# bms_108_Cell.net
KiCad netlist of a schematic drawn in EAGLE
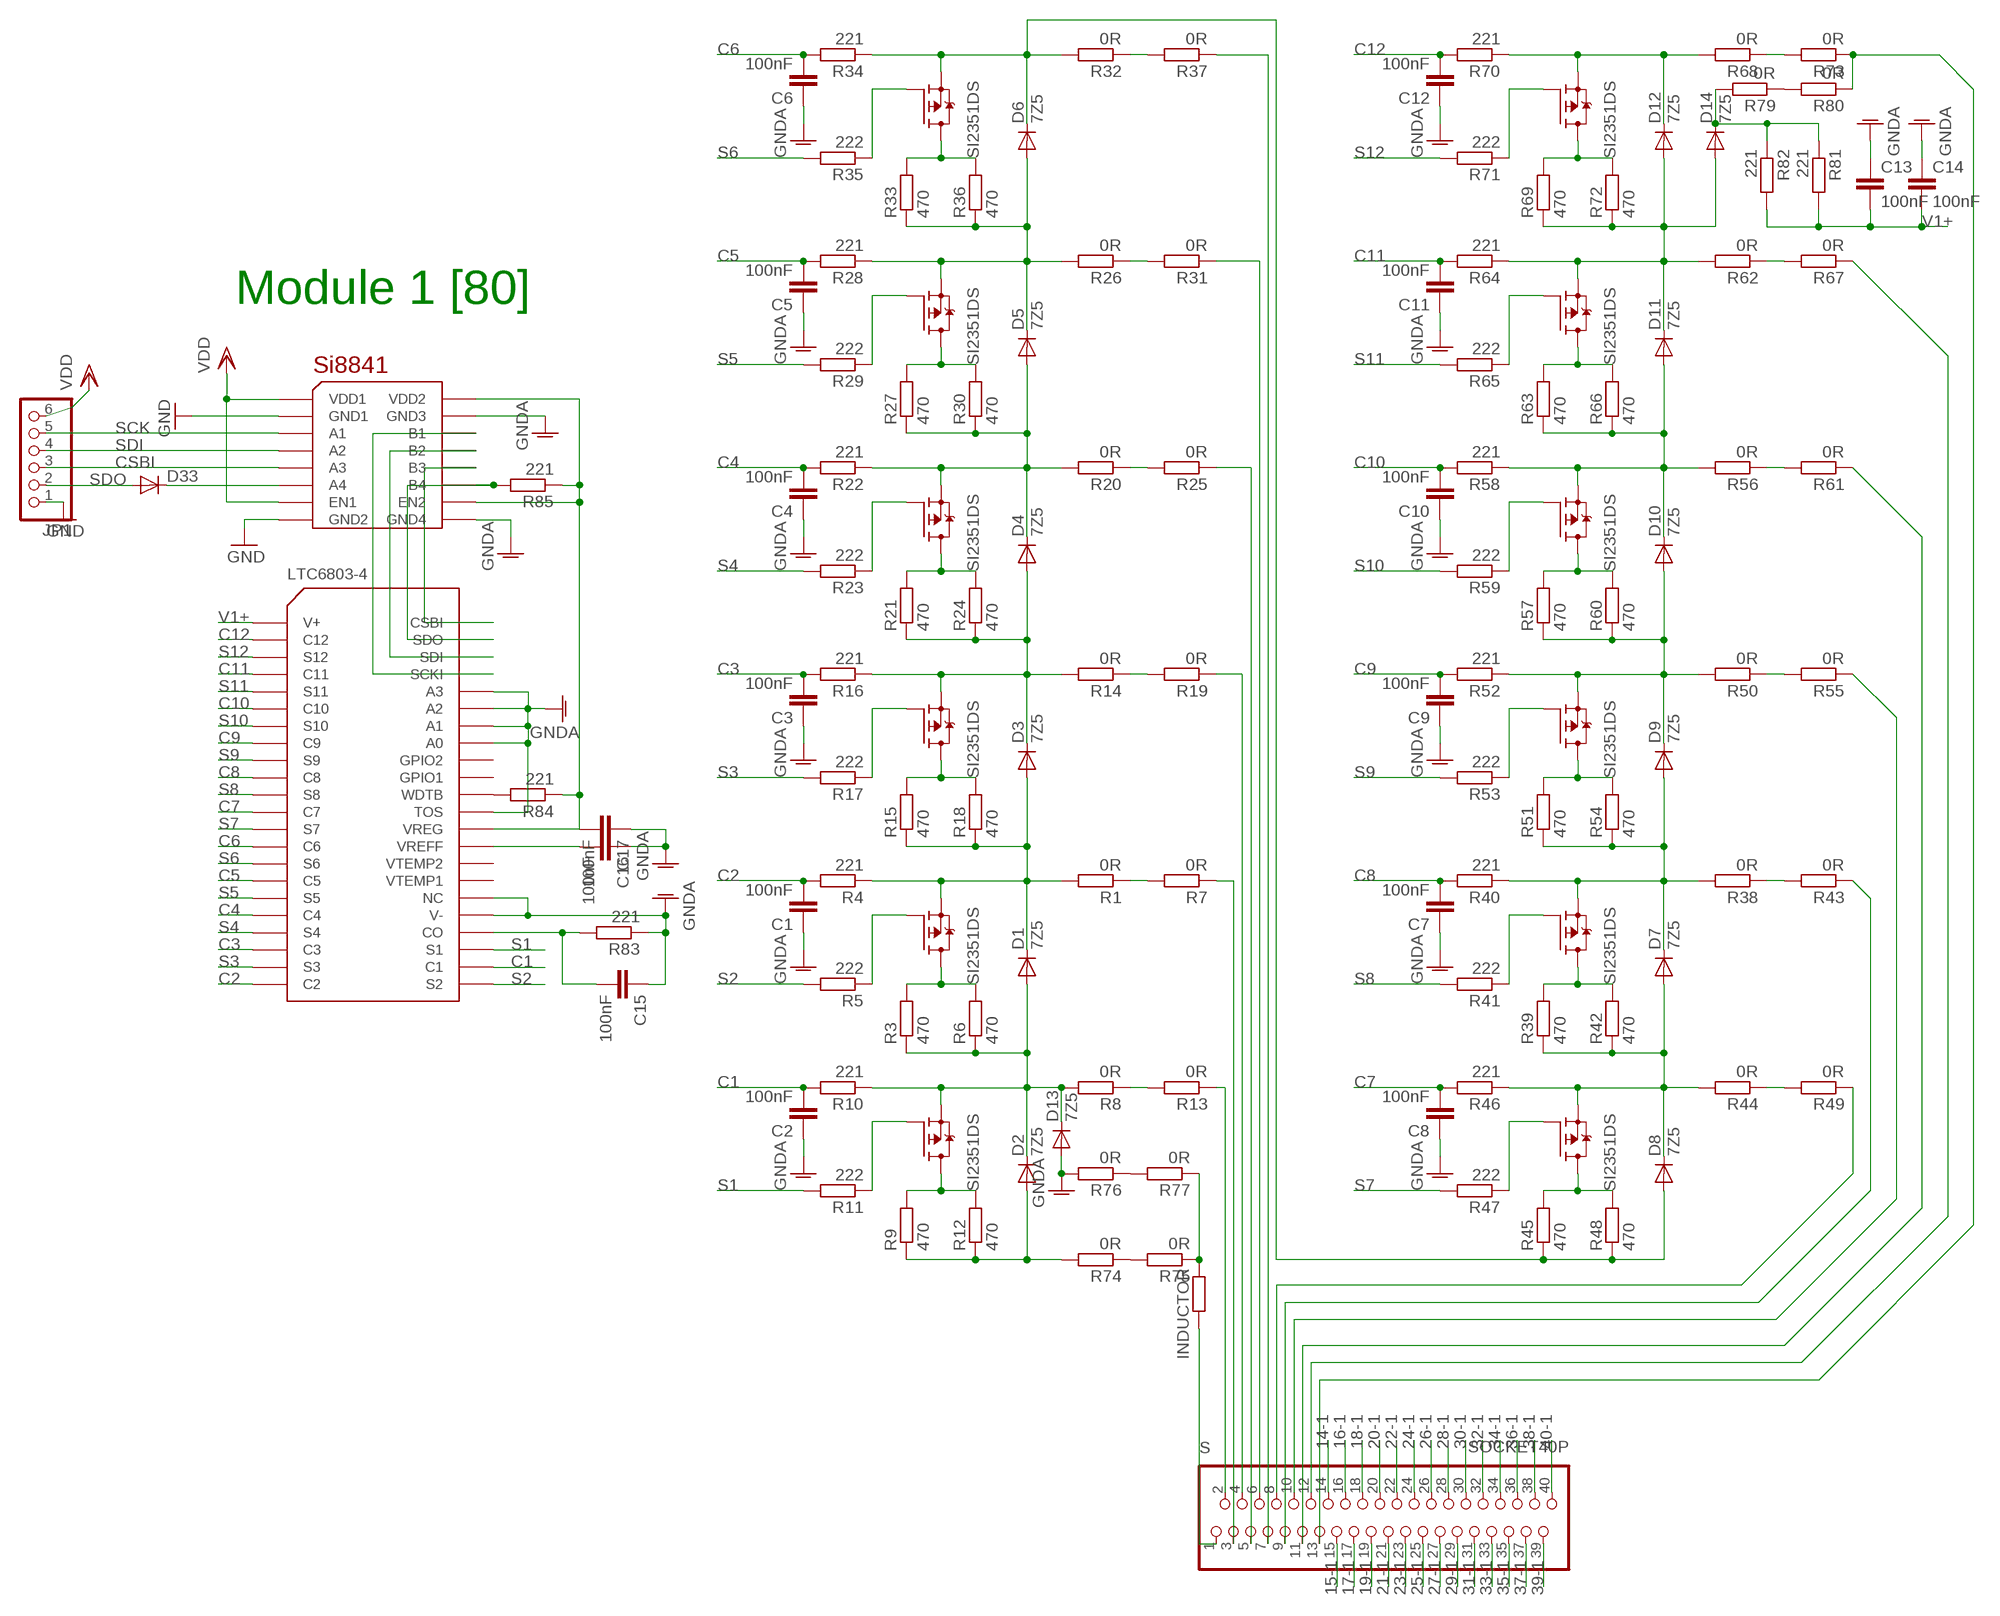
[diagram p0: schematic, sheet 1]
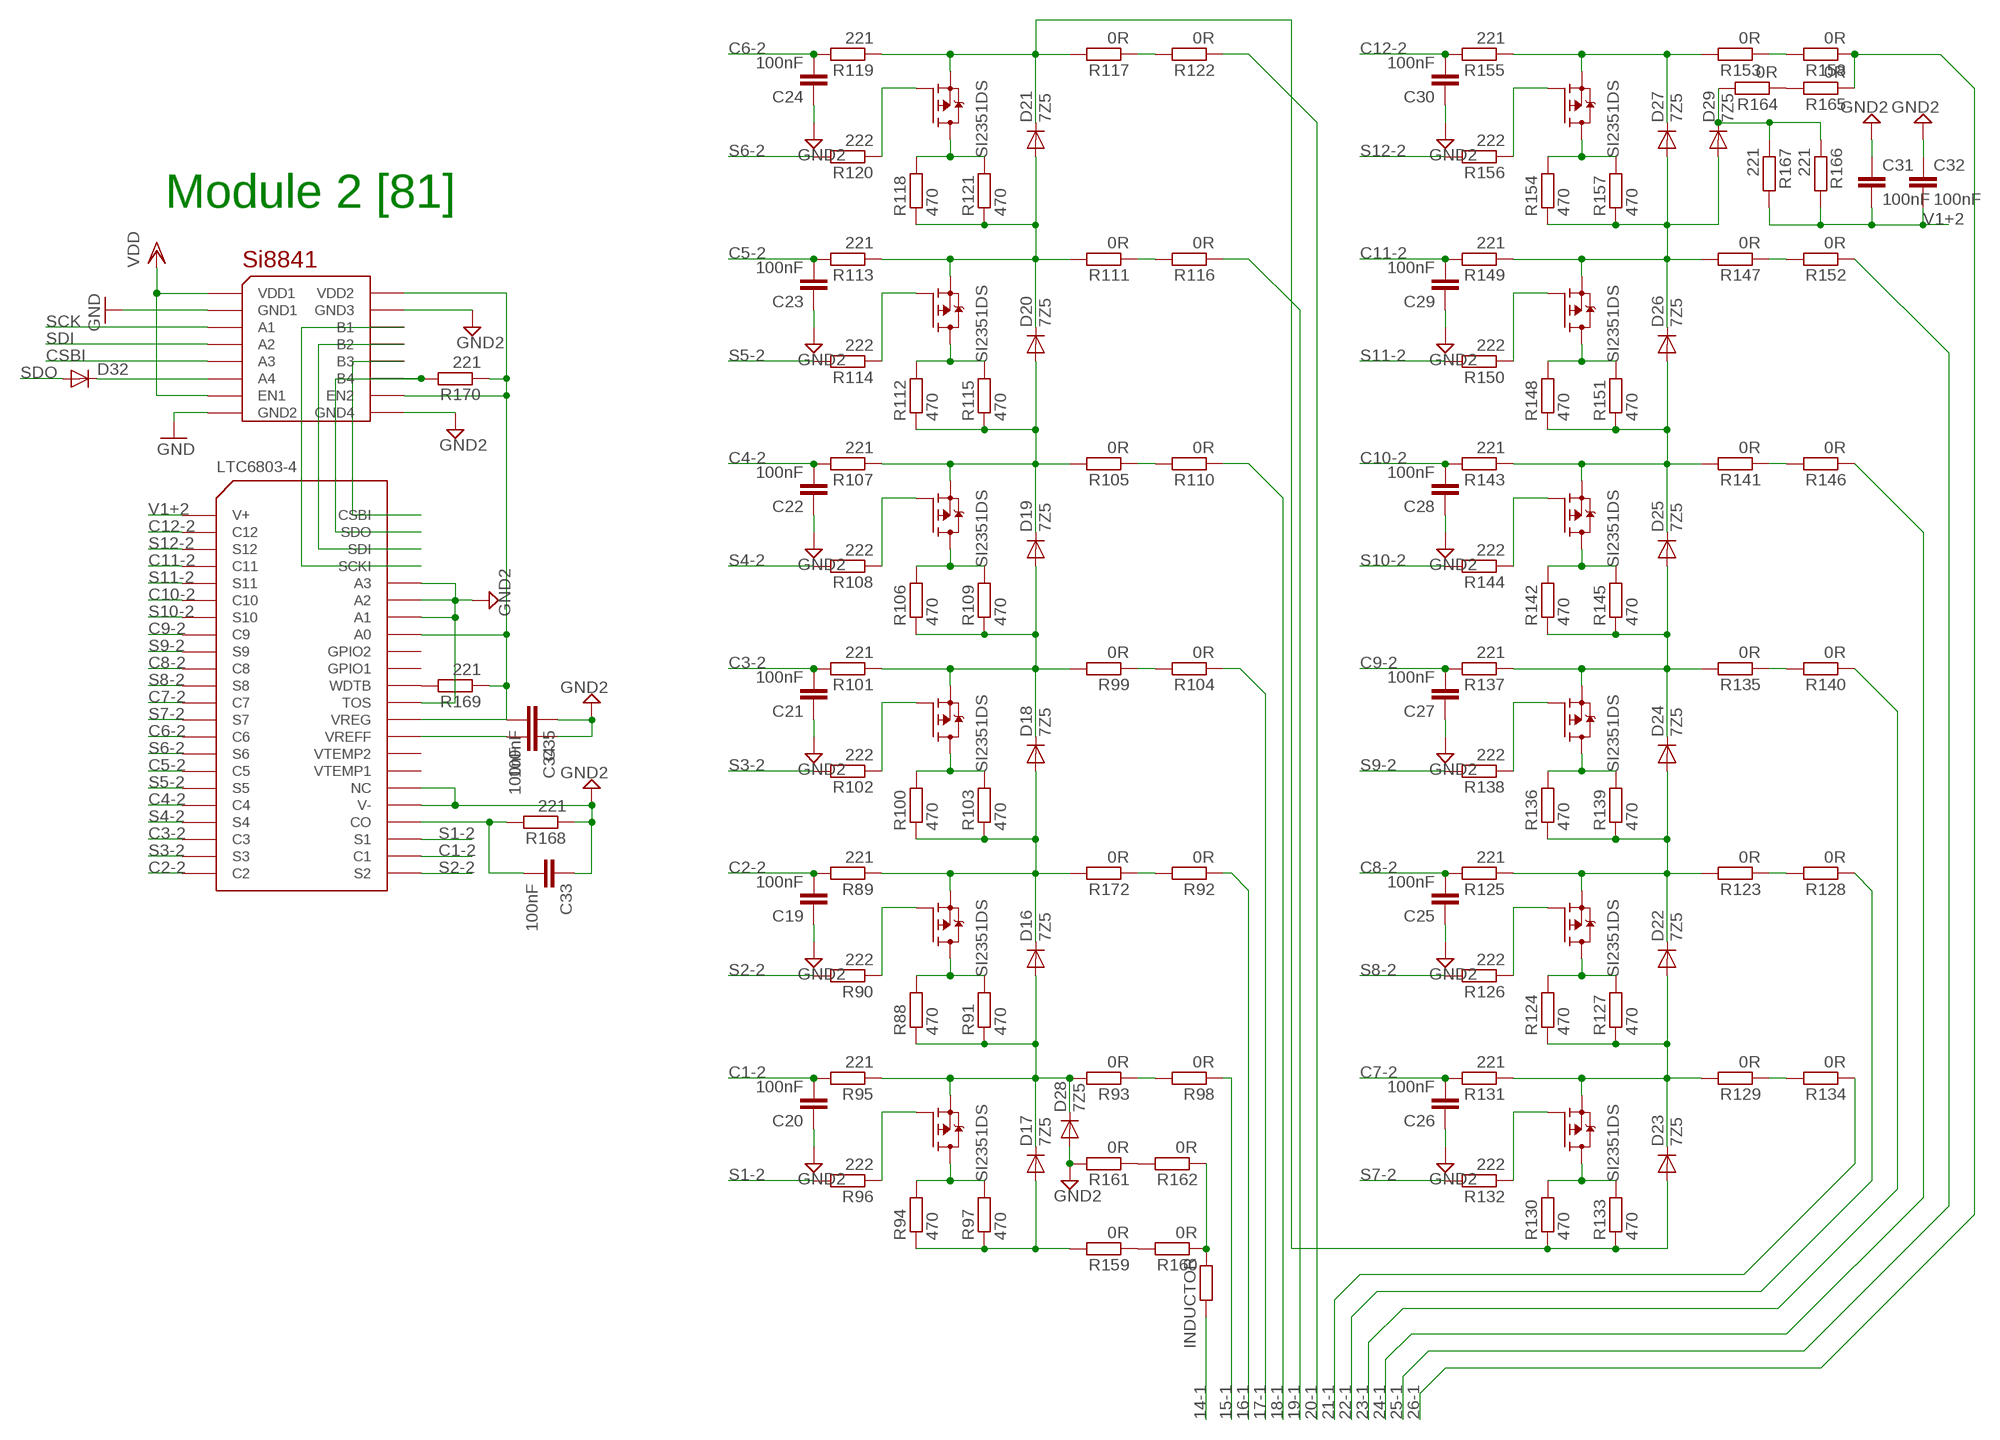
[diagram p1: schematic, sheet 2]
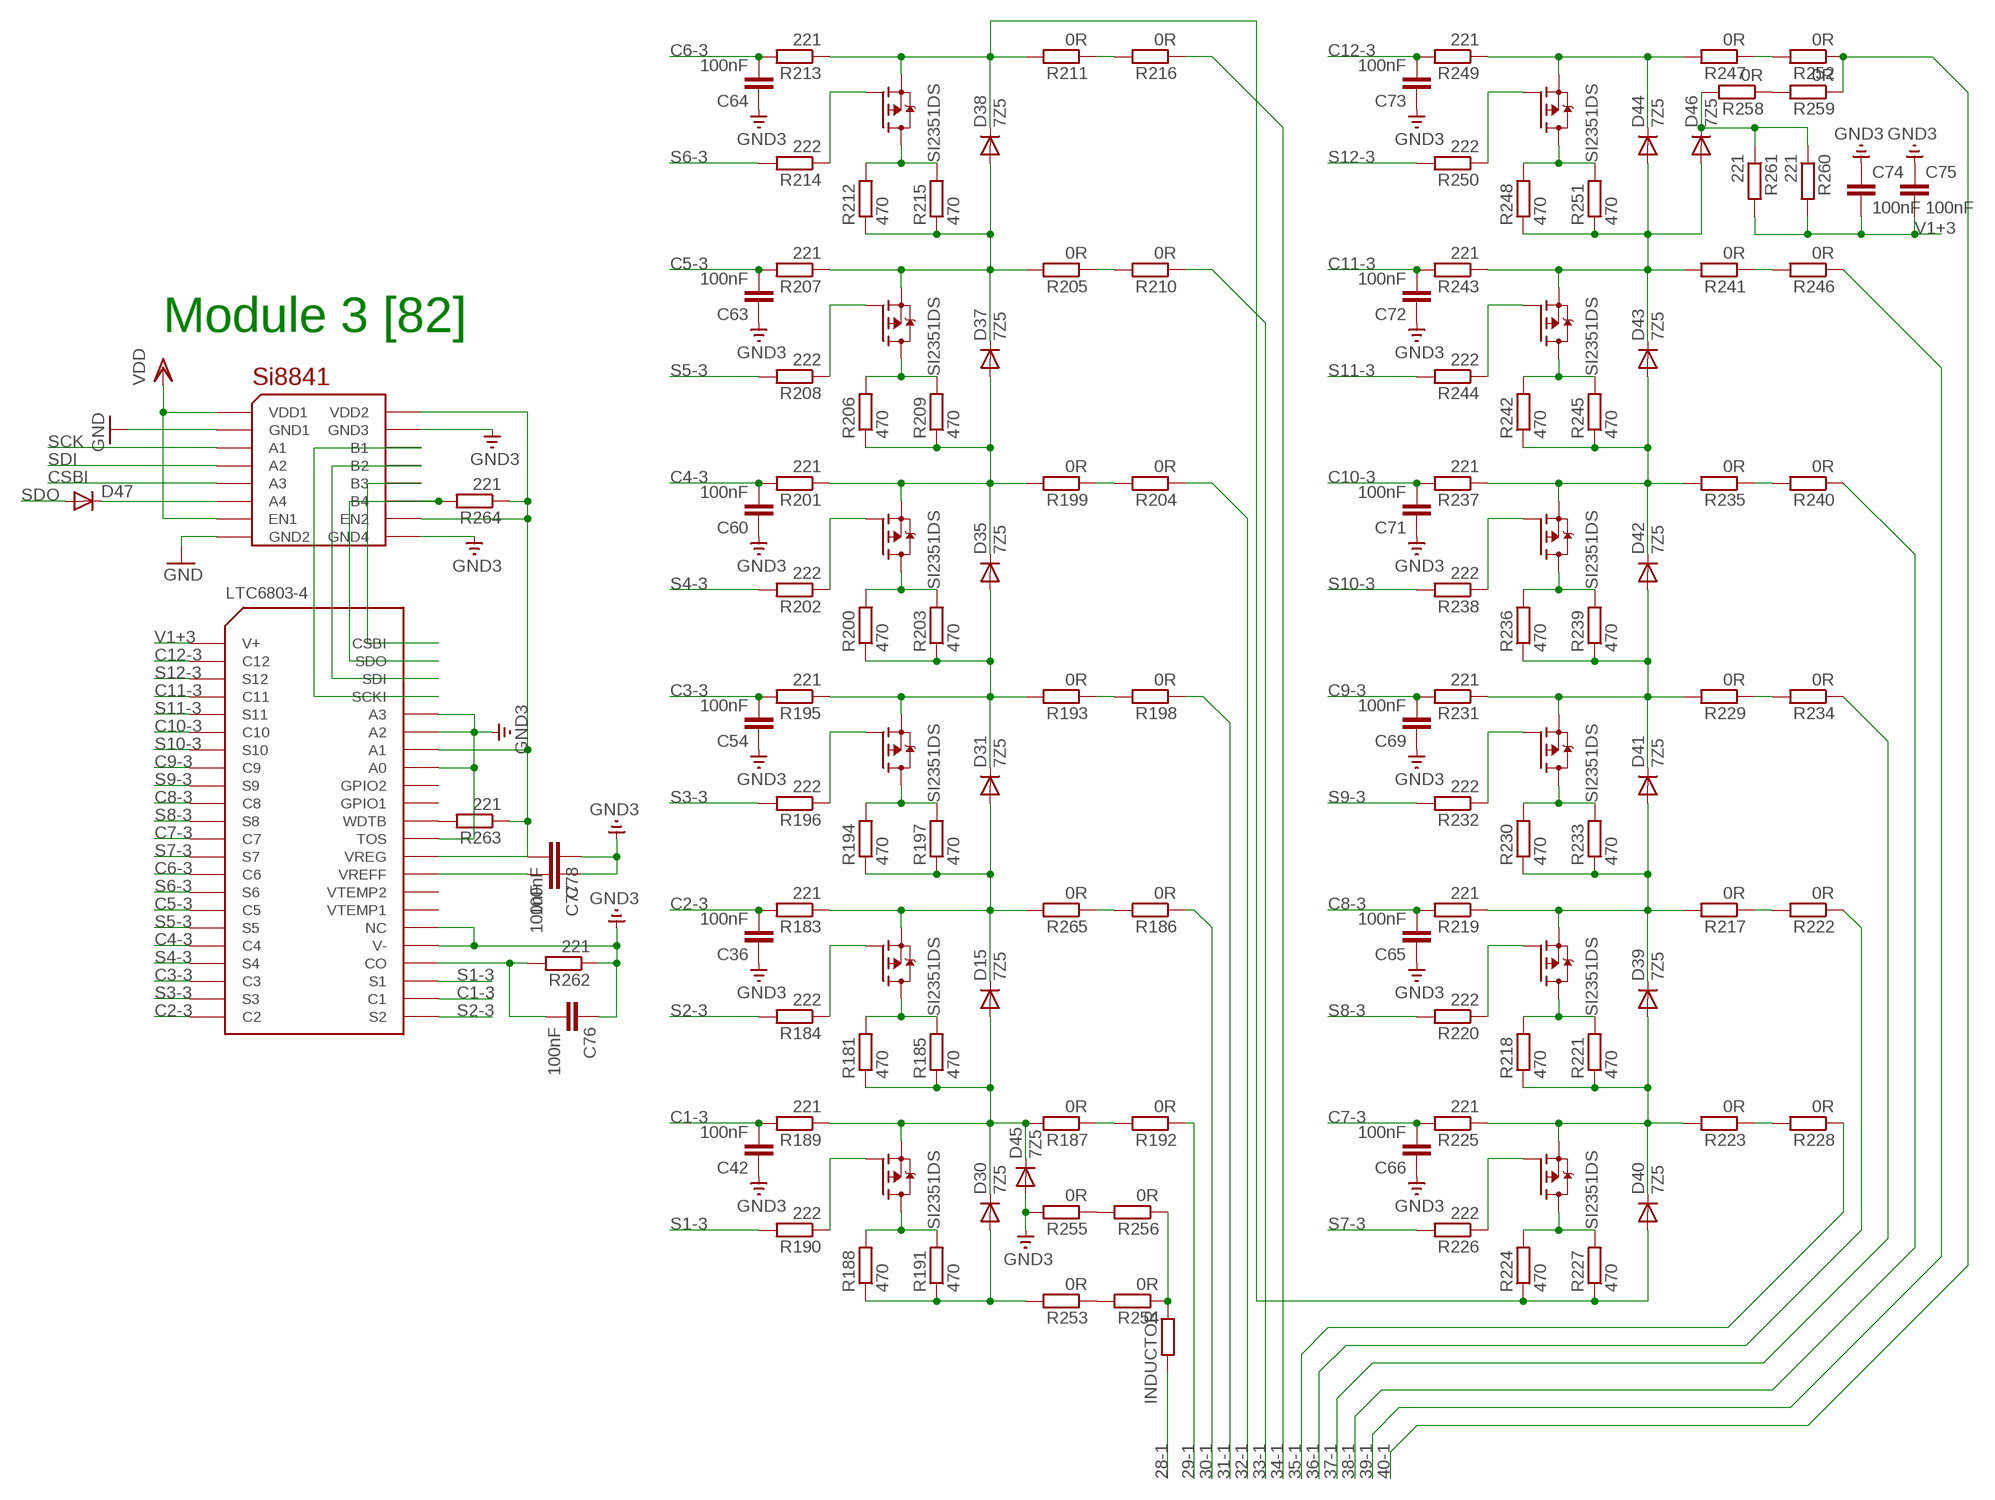
[diagram p2: schematic, sheet 3]
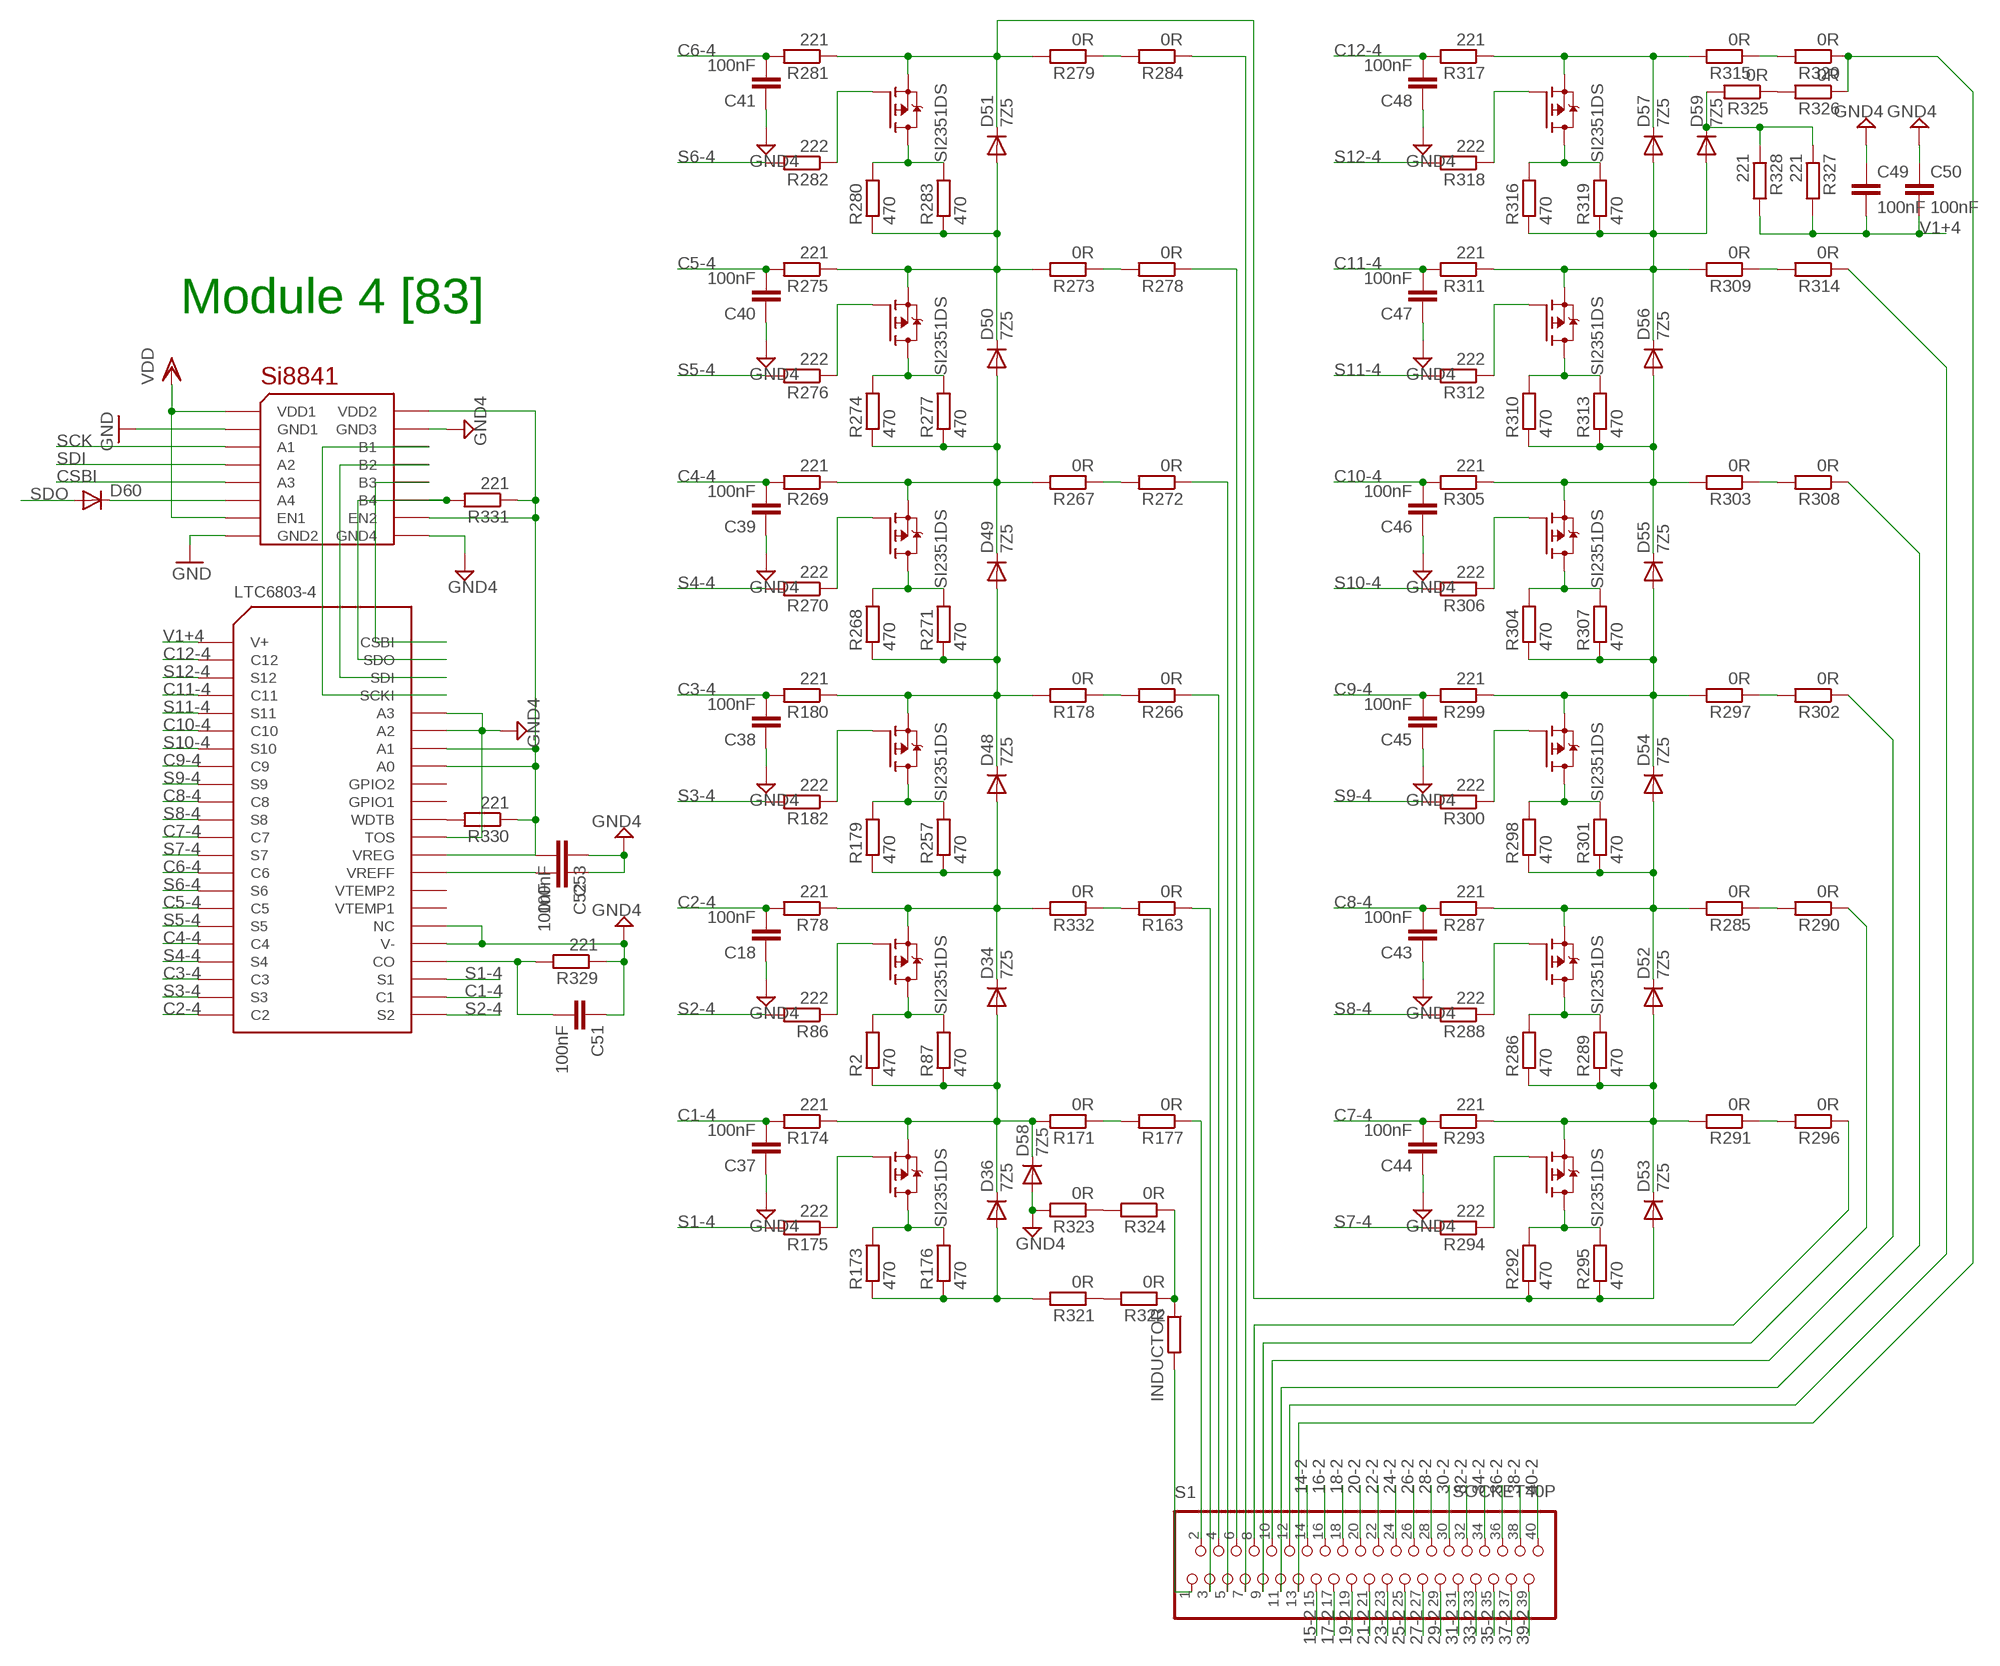
[diagram p3: schematic, sheet 4]
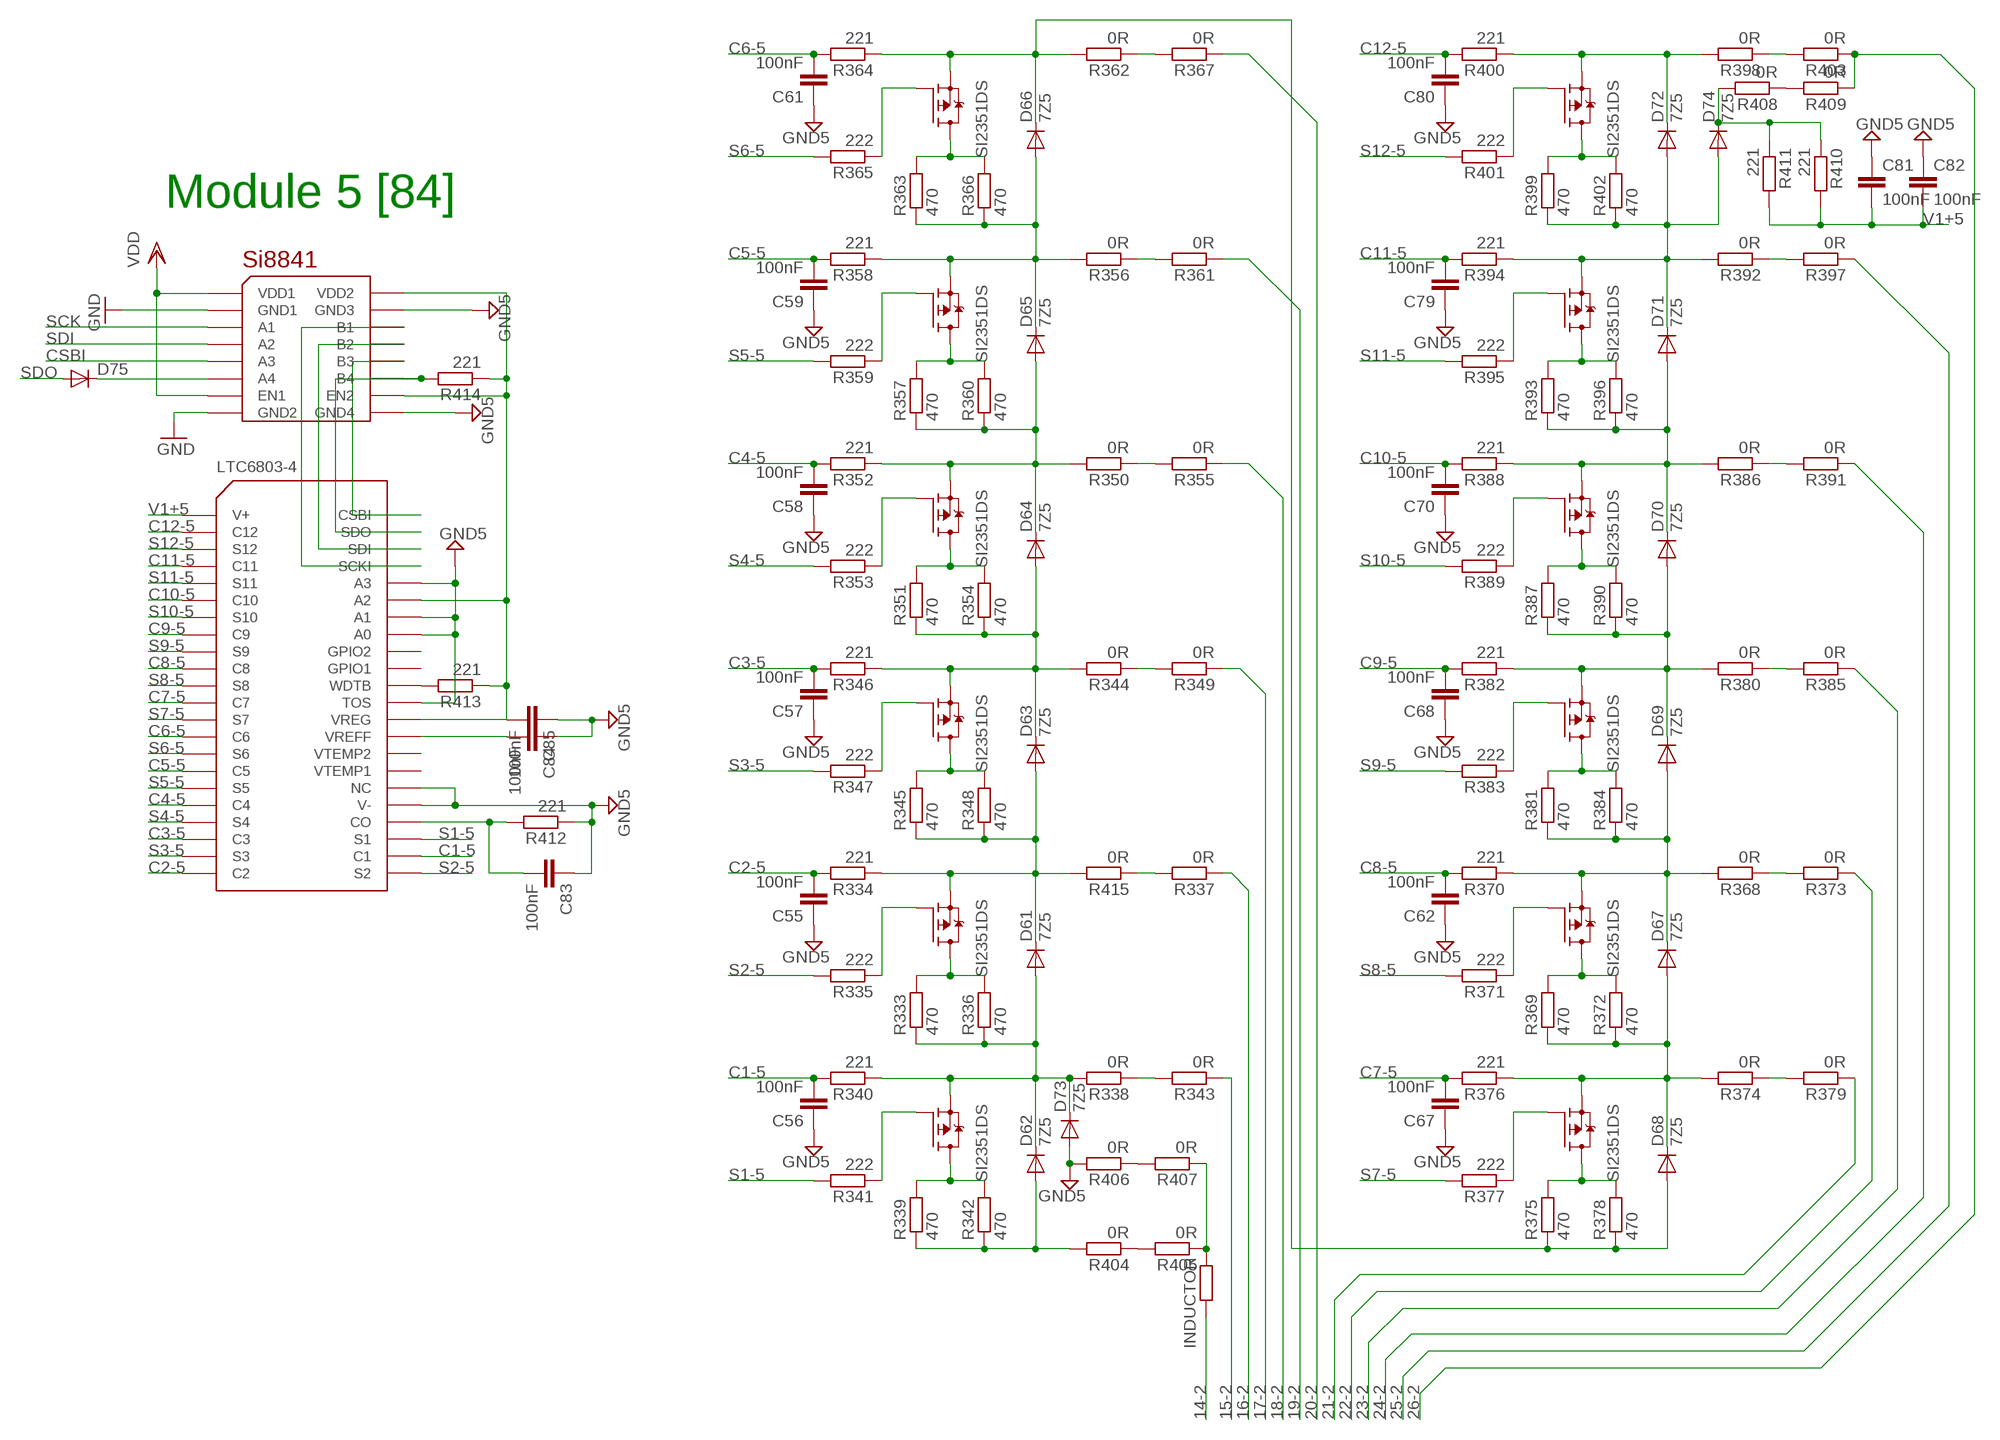
[diagram p4: schematic, sheet 5]
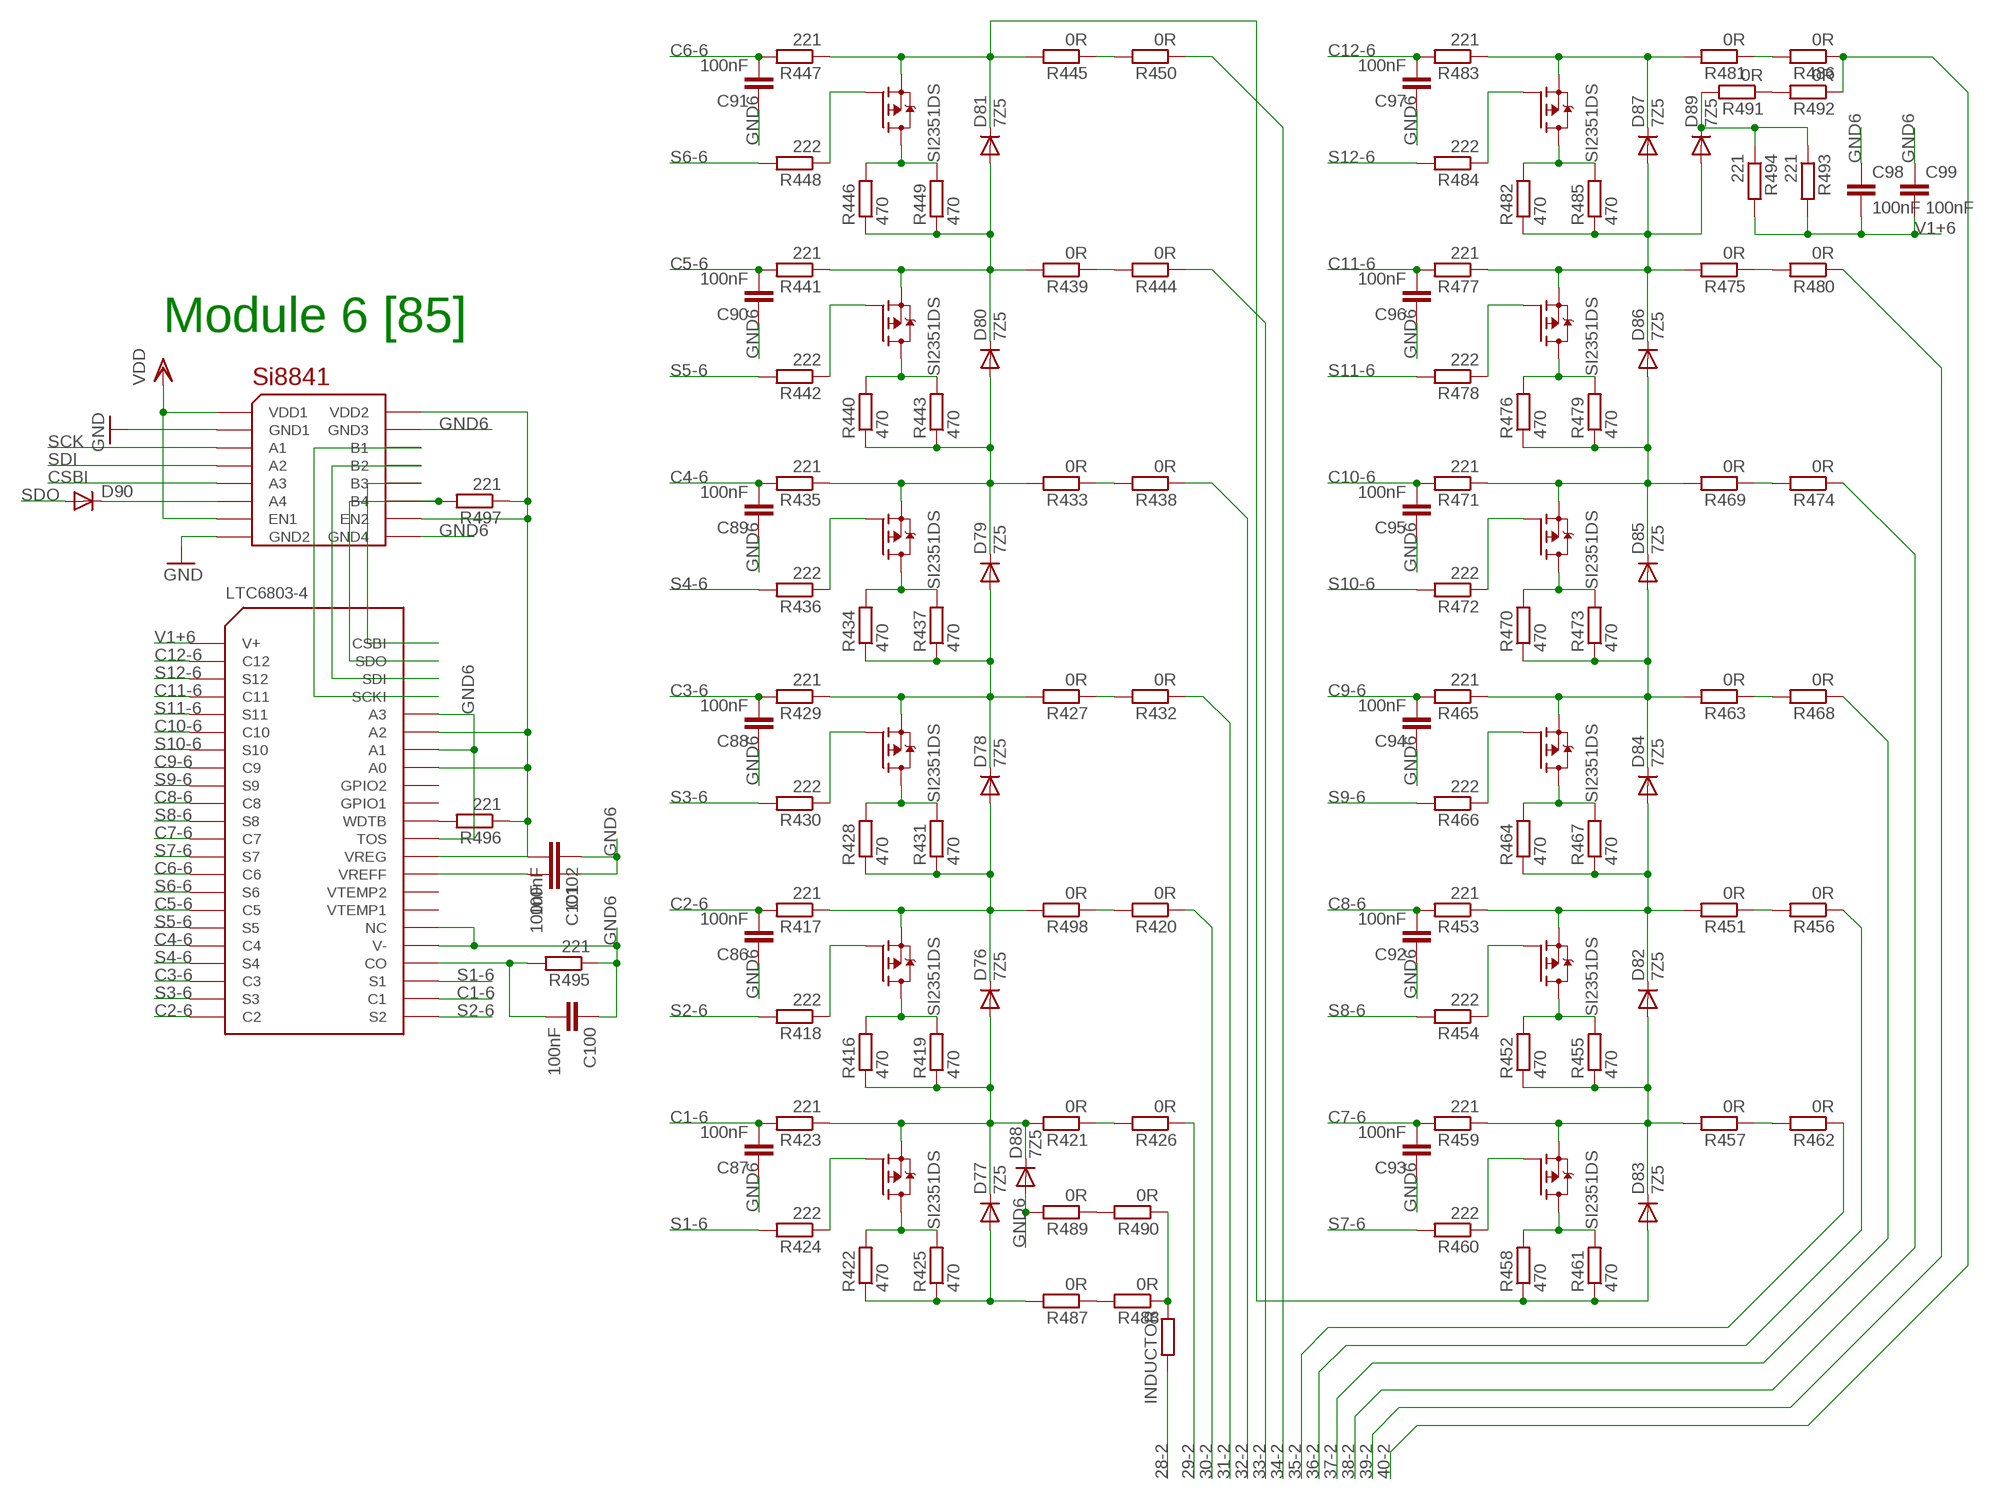
[diagram p5: schematic, sheet 6]
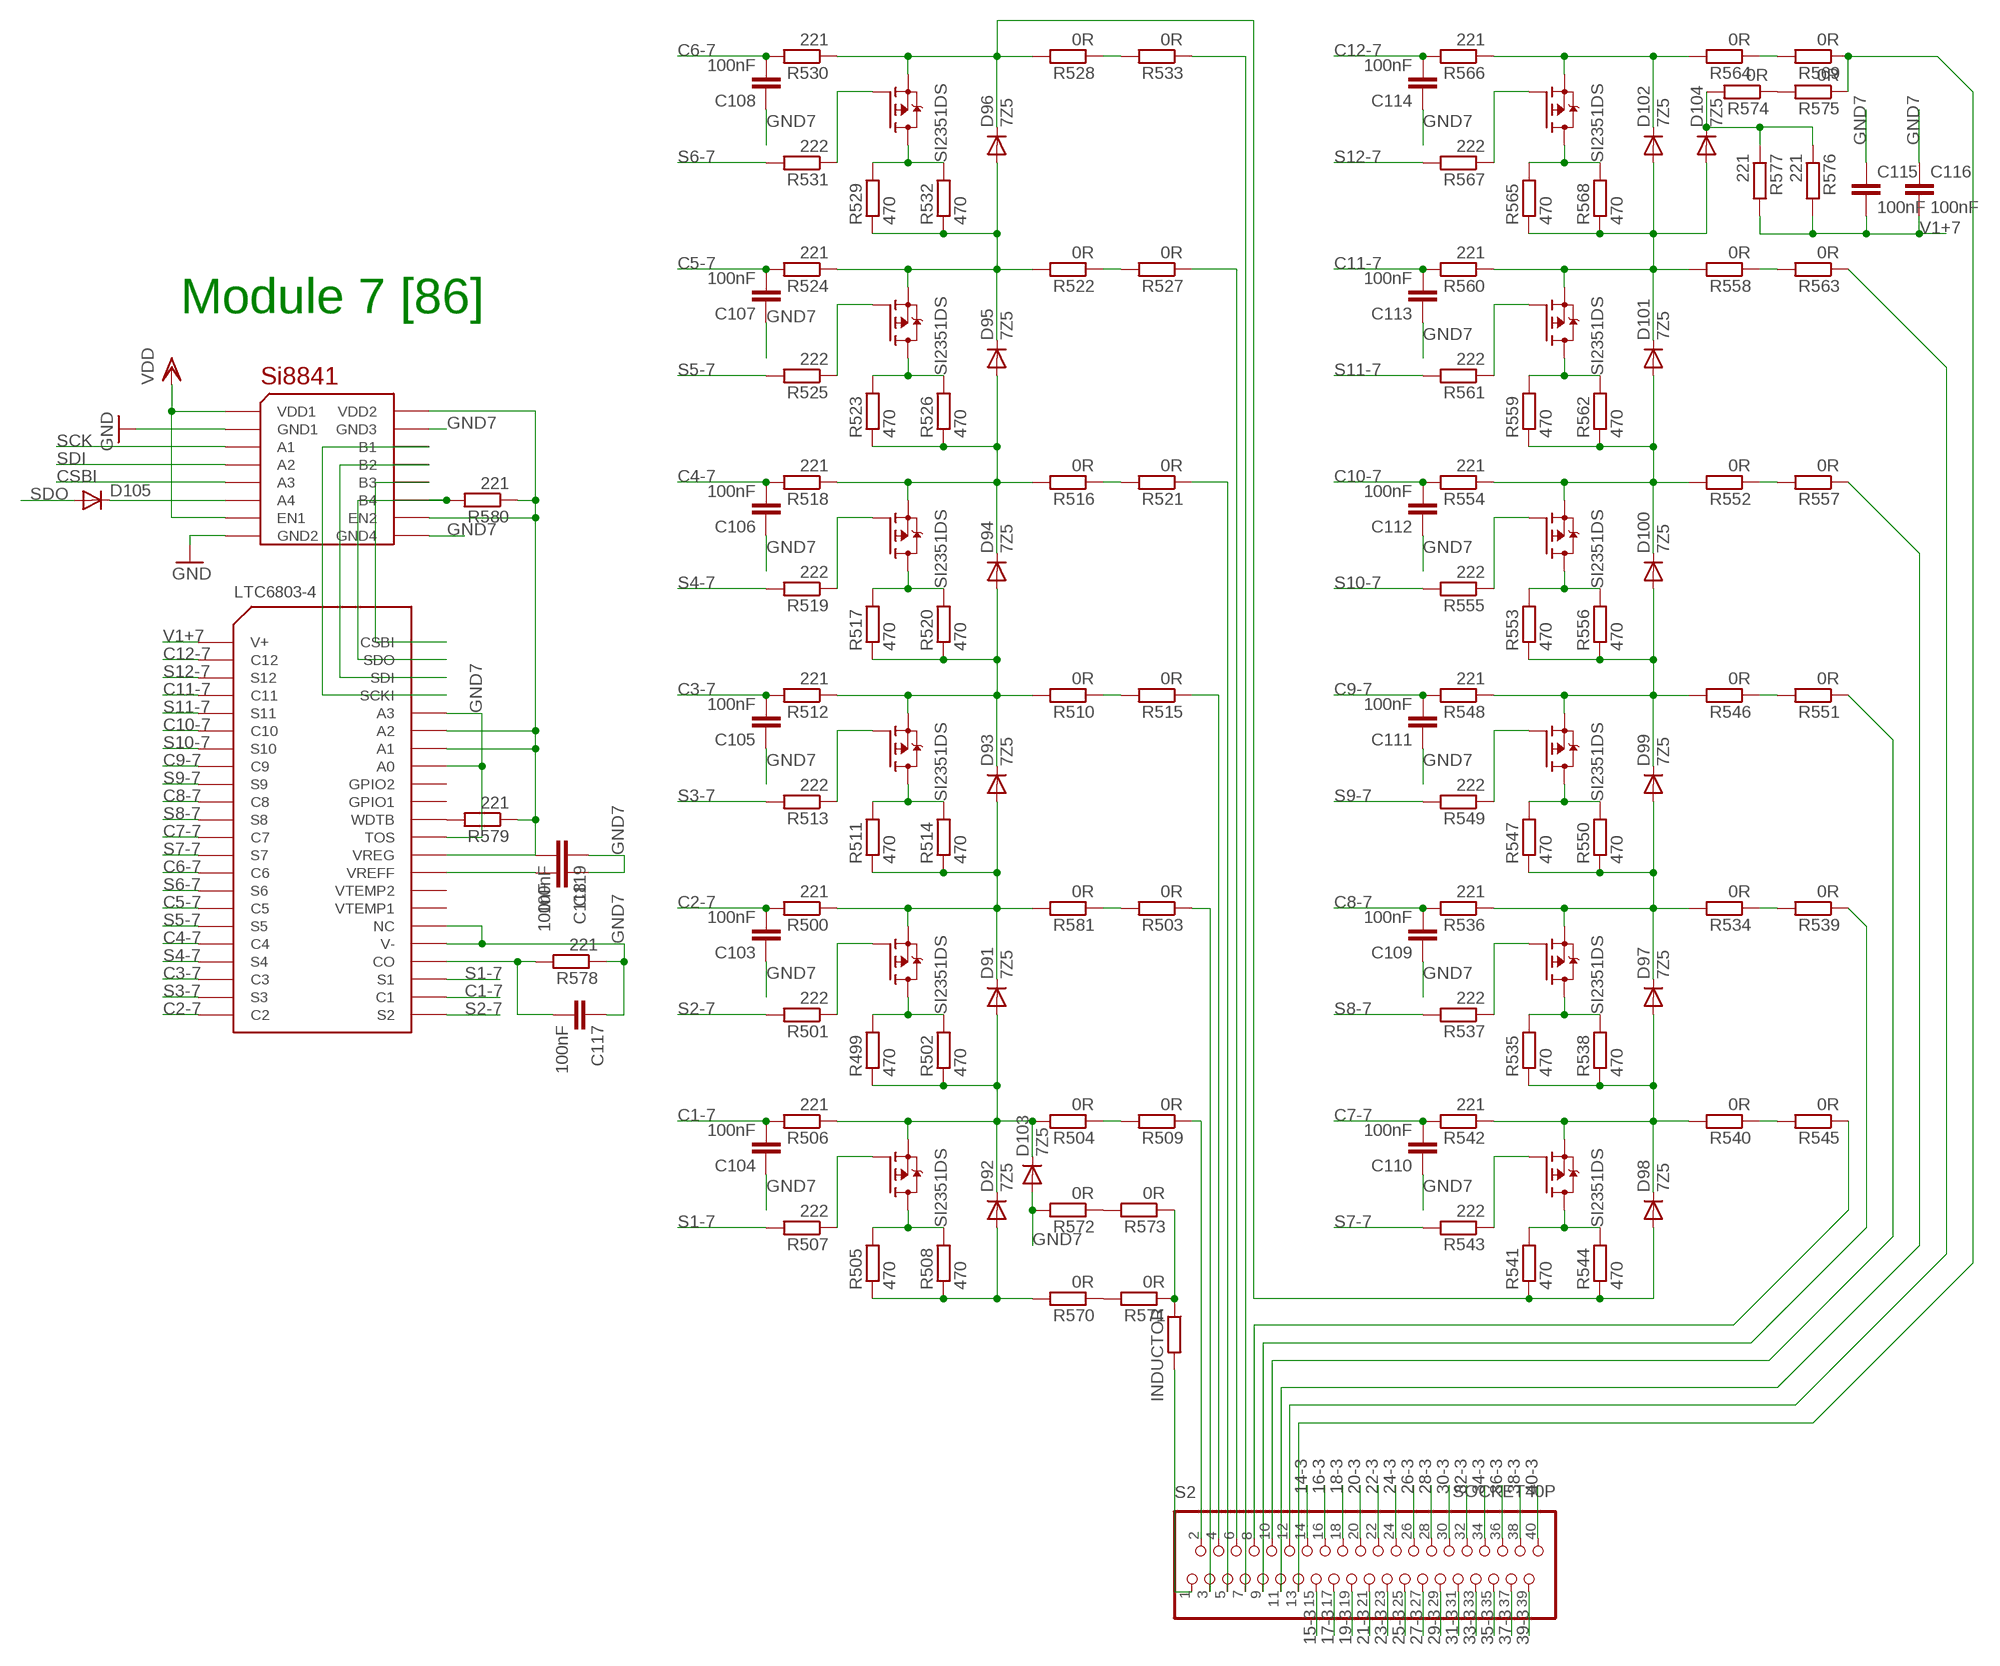
[diagram p6: schematic, sheet 7]
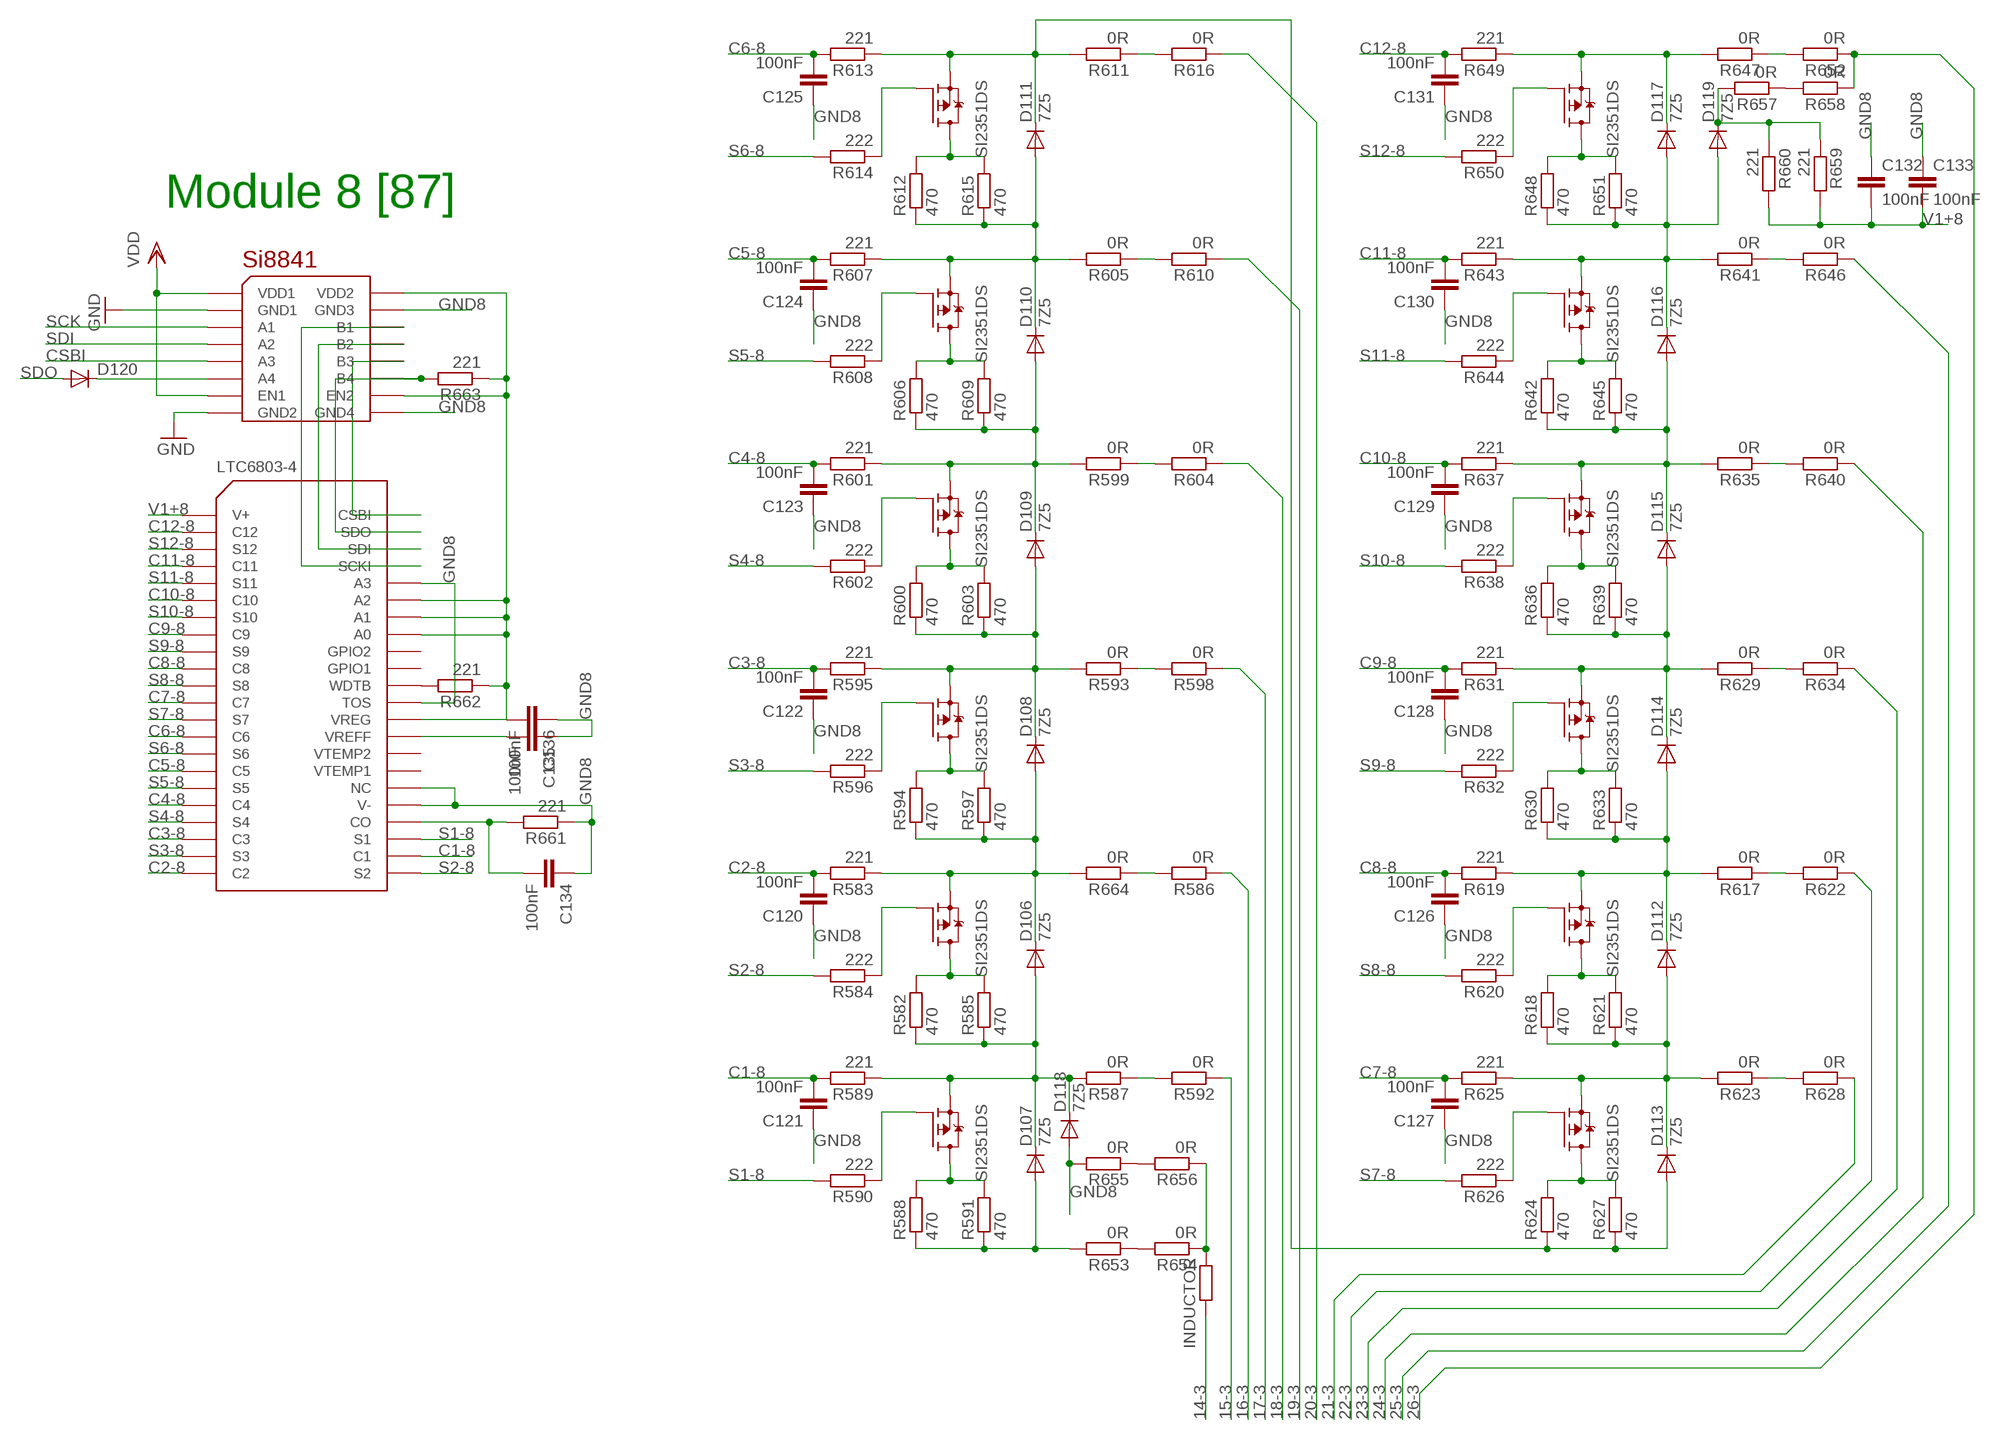
[diagram p7: schematic, sheet 8]
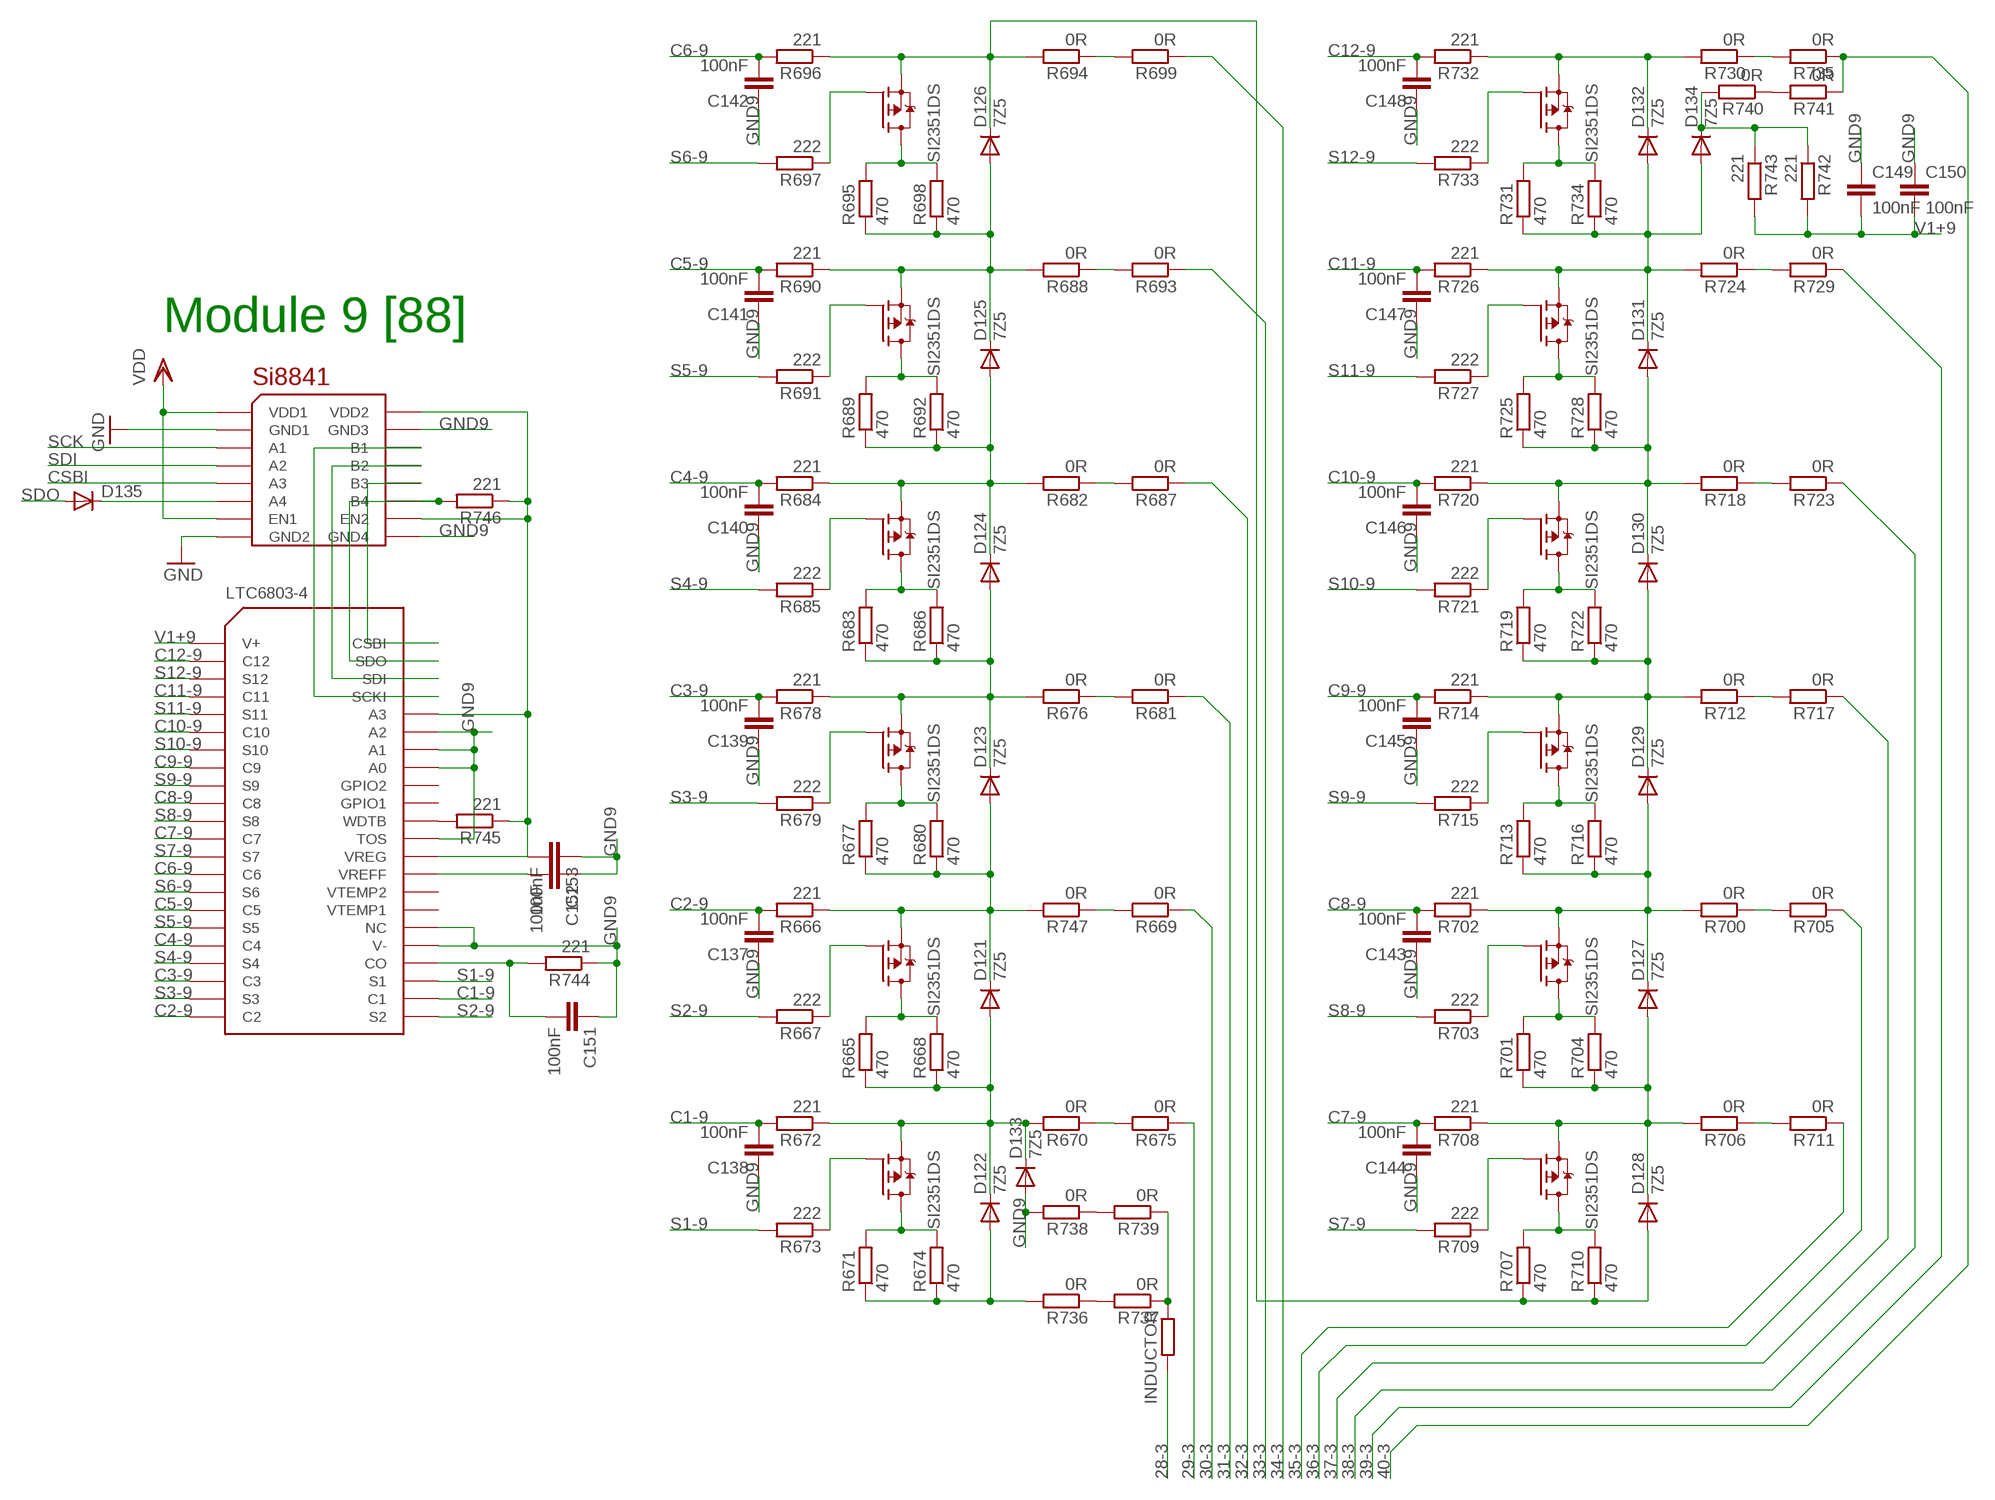
[diagram p8: schematic, sheet 9]

(export (version "E")
  (design (tool "Eeschema 10.0.6"))
  (components
    (comp (ref "C86")
      (value "100nF")
      (footprint "eagle-import:C0805K")
      (libsource (lib "eagle-import") (part "C-EUC0805K"))
    )
    (comp (ref "C87")
      (value "100nF")
      (footprint "eagle-import:C0805K")
      (libsource (lib "eagle-import") (part "C-EUC0805K"))
    )
    (comp (ref "C88")
      (value "100nF")
      (footprint "eagle-import:C0805K")
      (libsource (lib "eagle-import") (part "C-EUC0805K"))
    )
    (comp (ref "C89")
      (value "100nF")
      (footprint "eagle-import:C0805K")
      (libsource (lib "eagle-import") (part "C-EUC0805K"))
    )
    (comp (ref "C90")
      (value "100nF")
      (footprint "eagle-import:C0805K")
      (libsource (lib "eagle-import") (part "C-EUC0805K"))
    )
    (comp (ref "C91")
      (value "100nF")
      (footprint "eagle-import:C0805K")
      (libsource (lib "eagle-import") (part "C-EUC0805K"))
    )
    (comp (ref "C92")
      (value "100nF")
      (footprint "eagle-import:C0805K")
      (libsource (lib "eagle-import") (part "C-EUC0805K"))
    )
    (comp (ref "C93")
      (value "100nF")
      (footprint "eagle-import:C0805K")
      (libsource (lib "eagle-import") (part "C-EUC0805K"))
    )
    (comp (ref "C94")
      (value "100nF")
      (footprint "eagle-import:C0805K")
      (libsource (lib "eagle-import") (part "C-EUC0805K"))
    )
    (comp (ref "C95")
      (value "100nF")
      (footprint "eagle-import:C0805K")
      (libsource (lib "eagle-import") (part "C-EUC0805K"))
    )
    (comp (ref "C96")
      (value "100nF")
      (footprint "eagle-import:C0805K")
      (libsource (lib "eagle-import") (part "C-EUC0805K"))
    )
    (comp (ref "C97")
      (value "100nF")
      (footprint "eagle-import:C0805K")
      (libsource (lib "eagle-import") (part "C-EUC0805K"))
    )
    (comp (ref "C98")
      (value "100nF")
      (footprint "eagle-import:C0805K")
      (libsource (lib "eagle-import") (part "C-EUC0805K"))
    )
    (comp (ref "C99")
      (value "100nF")
      (footprint "eagle-import:C0805K")
      (libsource (lib "eagle-import") (part "C-EUC0805K"))
    )
    (comp (ref "C100")
      (value "100nF")
      (footprint "eagle-import:C0805K")
      (libsource (lib "eagle-import") (part "C-EUC0805K"))
    )
    (comp (ref "C101")
      (value "100nF")
      (footprint "eagle-import:C0805K")
      (libsource (lib "eagle-import") (part "C-EUC0805K"))
    )
    (comp (ref "C102")
      (value "100nF")
      (footprint "eagle-import:C0805K")
      (libsource (lib "eagle-import") (part "C-EUC0805K"))
    )
    (comp (ref "D76")
      (value "7Z5")
      (footprint "eagle-import:SMB")
      (libsource (lib "eagle-import") (part "DIODE-SMB"))
    )
    (comp (ref "D77")
      (value "7Z5")
      (footprint "eagle-import:SMB")
      (libsource (lib "eagle-import") (part "DIODE-SMB"))
    )
    (comp (ref "D78")
      (value "7Z5")
      (footprint "eagle-import:SMB")
      (libsource (lib "eagle-import") (part "DIODE-SMB"))
    )
    (comp (ref "D79")
      (value "7Z5")
      (footprint "eagle-import:SMB")
      (libsource (lib "eagle-import") (part "DIODE-SMB"))
    )
    (comp (ref "D80")
      (value "7Z5")
      (footprint "eagle-import:SMB")
      (libsource (lib "eagle-import") (part "DIODE-SMB"))
    )
    (comp (ref "D81")
      (value "7Z5")
      (footprint "eagle-import:SMB")
      (libsource (lib "eagle-import") (part "DIODE-SMB"))
    )
    (comp (ref "D82")
      (value "7Z5")
      (footprint "eagle-import:SMB")
      (libsource (lib "eagle-import") (part "DIODE-SMB"))
    )
    (comp (ref "D83")
      (value "7Z5")
      (footprint "eagle-import:SMB")
      (libsource (lib "eagle-import") (part "DIODE-SMB"))
    )
    (comp (ref "D84")
      (value "7Z5")
      (footprint "eagle-import:SMB")
      (libsource (lib "eagle-import") (part "DIODE-SMB"))
    )
    (comp (ref "D85")
      (value "7Z5")
      (footprint "eagle-import:SMB")
      (libsource (lib "eagle-import") (part "DIODE-SMB"))
    )
    (comp (ref "D86")
      (value "7Z5")
      (footprint "eagle-import:SMB")
      (libsource (lib "eagle-import") (part "DIODE-SMB"))
    )
    (comp (ref "D87")
      (value "7Z5")
      (footprint "eagle-import:SMB")
      (libsource (lib "eagle-import") (part "DIODE-SMB"))
    )
    (comp (ref "D88")
      (value "7Z5")
      (footprint "eagle-import:SMB")
      (libsource (lib "eagle-import") (part "DIODE-SMB"))
    )
    (comp (ref "D89")
      (value "7Z5")
      (footprint "eagle-import:SMB")
      (libsource (lib "eagle-import") (part "DIODE-SMB"))
    )
    (comp (ref "D90")
      (value "DIODE-SOD123")
      (footprint "eagle-import:SOD123")
      (libsource (lib "eagle-import") (part "DIODE-SOD123"))
    )
    (comp (ref "R416")
      (value "470")
      (footprint "eagle-import:R6332")
      (libsource (lib "eagle-import") (part "R-EU_R6332"))
    )
    (comp (ref "R417")
      (value "221")
      (footprint "eagle-import:R0805")
      (libsource (lib "eagle-import") (part "R-EU_R0805"))
    )
    (comp (ref "R418")
      (value "222")
      (footprint "eagle-import:R0805")
      (libsource (lib "eagle-import") (part "R-EU_R0805"))
    )
    (comp (ref "R419")
      (value "470")
      (footprint "eagle-import:R6332")
      (libsource (lib "eagle-import") (part "R-EU_R6332"))
    )
    (comp (ref "R420")
      (value "0R")
      (footprint "eagle-import:M1206")
      (libsource (lib "eagle-import") (part "R-EU_M1206"))
    )
    (comp (ref "R421")
      (value "0R")
      (footprint "eagle-import:M1206")
      (libsource (lib "eagle-import") (part "R-EU_M1206"))
    )
    (comp (ref "R422")
      (value "470")
      (footprint "eagle-import:R6332")
      (libsource (lib "eagle-import") (part "R-EU_R6332"))
    )
    (comp (ref "R423")
      (value "221")
      (footprint "eagle-import:R0805")
      (libsource (lib "eagle-import") (part "R-EU_R0805"))
    )
    (comp (ref "R424")
      (value "222")
      (footprint "eagle-import:R0805")
      (libsource (lib "eagle-import") (part "R-EU_R0805"))
    )
    (comp (ref "R425")
      (value "470")
      (footprint "eagle-import:R6332")
      (libsource (lib "eagle-import") (part "R-EU_R6332"))
    )
    (comp (ref "R426")
      (value "0R")
      (footprint "eagle-import:M1206")
      (libsource (lib "eagle-import") (part "R-EU_M1206"))
    )
    (comp (ref "R427")
      (value "0R")
      (footprint "eagle-import:M1206")
      (libsource (lib "eagle-import") (part "R-EU_M1206"))
    )
    (comp (ref "R428")
      (value "470")
      (footprint "eagle-import:R6332")
      (libsource (lib "eagle-import") (part "R-EU_R6332"))
    )
    (comp (ref "R429")
      (value "221")
      (footprint "eagle-import:R0805")
      (libsource (lib "eagle-import") (part "R-EU_R0805"))
    )
    (comp (ref "R430")
      (value "222")
      (footprint "eagle-import:R0805")
      (libsource (lib "eagle-import") (part "R-EU_R0805"))
    )
    (comp (ref "R431")
      (value "470")
      (footprint "eagle-import:R6332")
      (libsource (lib "eagle-import") (part "R-EU_R6332"))
    )
    (comp (ref "R432")
      (value "0R")
      (footprint "eagle-import:M1206")
      (libsource (lib "eagle-import") (part "R-EU_M1206"))
    )
    (comp (ref "R433")
      (value "0R")
      (footprint "eagle-import:M1206")
      (libsource (lib "eagle-import") (part "R-EU_M1206"))
    )
    (comp (ref "R434")
      (value "470")
      (footprint "eagle-import:R6332")
      (libsource (lib "eagle-import") (part "R-EU_R6332"))
    )
    (comp (ref "R435")
      (value "221")
      (footprint "eagle-import:R0805")
      (libsource (lib "eagle-import") (part "R-EU_R0805"))
    )
    (comp (ref "R436")
      (value "222")
      (footprint "eagle-import:R0805")
      (libsource (lib "eagle-import") (part "R-EU_R0805"))
    )
    (comp (ref "R437")
      (value "470")
      (footprint "eagle-import:R6332")
      (libsource (lib "eagle-import") (part "R-EU_R6332"))
    )
    (comp (ref "R438")
      (value "0R")
      (footprint "eagle-import:M1206")
      (libsource (lib "eagle-import") (part "R-EU_M1206"))
    )
    (comp (ref "R439")
      (value "0R")
      (footprint "eagle-import:M1206")
      (libsource (lib "eagle-import") (part "R-EU_M1206"))
    )
    (comp (ref "R440")
      (value "470")
      (footprint "eagle-import:R6332")
      (libsource (lib "eagle-import") (part "R-EU_R6332"))
    )
    (comp (ref "R441")
      (value "221")
      (footprint "eagle-import:R0805")
      (libsource (lib "eagle-import") (part "R-EU_R0805"))
    )
    (comp (ref "R442")
      (value "222")
      (footprint "eagle-import:R0805")
      (libsource (lib "eagle-import") (part "R-EU_R0805"))
    )
    (comp (ref "R443")
      (value "470")
      (footprint "eagle-import:R6332")
      (libsource (lib "eagle-import") (part "R-EU_R6332"))
    )
    (comp (ref "R444")
      (value "0R")
      (footprint "eagle-import:M1206")
      (libsource (lib "eagle-import") (part "R-EU_M1206"))
    )
    (comp (ref "R445")
      (value "0R")
      (footprint "eagle-import:M1206")
      (libsource (lib "eagle-import") (part "R-EU_M1206"))
    )
    (comp (ref "R446")
      (value "470")
      (footprint "eagle-import:R6332")
      (libsource (lib "eagle-import") (part "R-EU_R6332"))
    )
    (comp (ref "R447")
      (value "221")
      (footprint "eagle-import:R0805")
      (libsource (lib "eagle-import") (part "R-EU_R0805"))
    )
    (comp (ref "R448")
      (value "222")
      (footprint "eagle-import:R0805")
      (libsource (lib "eagle-import") (part "R-EU_R0805"))
    )
    (comp (ref "R449")
      (value "470")
      (footprint "eagle-import:R6332")
      (libsource (lib "eagle-import") (part "R-EU_R6332"))
    )
    (comp (ref "R450")
      (value "0R")
      (footprint "eagle-import:M1206")
      (libsource (lib "eagle-import") (part "R-EU_M1206"))
    )
    (comp (ref "R451")
      (value "0R")
      (footprint "eagle-import:M1206")
      (libsource (lib "eagle-import") (part "R-EU_M1206"))
    )
    (comp (ref "R452")
      (value "470")
      (footprint "eagle-import:R6332")
      (libsource (lib "eagle-import") (part "R-EU_R6332"))
    )
    (comp (ref "R453")
      (value "221")
      (footprint "eagle-import:R0805")
      (libsource (lib "eagle-import") (part "R-EU_R0805"))
    )
    (comp (ref "R454")
      (value "222")
      (footprint "eagle-import:R0805")
      (libsource (lib "eagle-import") (part "R-EU_R0805"))
    )
    (comp (ref "R455")
      (value "470")
      (footprint "eagle-import:R6332")
      (libsource (lib "eagle-import") (part "R-EU_R6332"))
    )
    (comp (ref "R456")
      (value "0R")
      (footprint "eagle-import:M1206")
      (libsource (lib "eagle-import") (part "R-EU_M1206"))
    )
    (comp (ref "R457")
      (value "0R")
      (footprint "eagle-import:M1206")
      (libsource (lib "eagle-import") (part "R-EU_M1206"))
    )
    (comp (ref "R458")
      (value "470")
      (footprint "eagle-import:R6332")
      (libsource (lib "eagle-import") (part "R-EU_R6332"))
    )
    (comp (ref "R459")
      (value "221")
      (footprint "eagle-import:R0805")
      (libsource (lib "eagle-import") (part "R-EU_R0805"))
    )
    (comp (ref "R460")
      (value "222")
      (footprint "eagle-import:R0805")
      (libsource (lib "eagle-import") (part "R-EU_R0805"))
    )
    (comp (ref "R461")
      (value "470")
      (footprint "eagle-import:R6332")
      (libsource (lib "eagle-import") (part "R-EU_R6332"))
    )
    (comp (ref "R462")
      (value "0R")
      (footprint "eagle-import:M1206")
      (libsource (lib "eagle-import") (part "R-EU_M1206"))
    )
    (comp (ref "R463")
      (value "0R")
      (footprint "eagle-import:M1206")
      (libsource (lib "eagle-import") (part "R-EU_M1206"))
    )
    (comp (ref "R464")
      (value "470")
      (footprint "eagle-import:R6332")
      (libsource (lib "eagle-import") (part "R-EU_R6332"))
    )
    (comp (ref "R465")
      (value "221")
      (footprint "eagle-import:R0805")
      (libsource (lib "eagle-import") (part "R-EU_R0805"))
    )
    (comp (ref "R466")
      (value "222")
      (footprint "eagle-import:R0805")
      (libsource (lib "eagle-import") (part "R-EU_R0805"))
    )
    (comp (ref "R467")
      (value "470")
      (footprint "eagle-import:R6332")
      (libsource (lib "eagle-import") (part "R-EU_R6332"))
    )
    (comp (ref "R468")
      (value "0R")
      (footprint "eagle-import:M1206")
      (libsource (lib "eagle-import") (part "R-EU_M1206"))
    )
    (comp (ref "R469")
      (value "0R")
      (footprint "eagle-import:M1206")
      (libsource (lib "eagle-import") (part "R-EU_M1206"))
    )
    (comp (ref "R470")
      (value "470")
      (footprint "eagle-import:R6332")
      (libsource (lib "eagle-import") (part "R-EU_R6332"))
    )
    (comp (ref "R471")
      (value "221")
      (footprint "eagle-import:R0805")
      (libsource (lib "eagle-import") (part "R-EU_R0805"))
    )
    (comp (ref "R472")
      (value "222")
      (footprint "eagle-import:R0805")
      (libsource (lib "eagle-import") (part "R-EU_R0805"))
    )
    (comp (ref "R473")
      (value "470")
      (footprint "eagle-import:R6332")
      (libsource (lib "eagle-import") (part "R-EU_R6332"))
    )
    (comp (ref "R474")
      (value "0R")
      (footprint "eagle-import:M1206")
      (libsource (lib "eagle-import") (part "R-EU_M1206"))
    )
    (comp (ref "R475")
      (value "0R")
      (footprint "eagle-import:M1206")
      (libsource (lib "eagle-import") (part "R-EU_M1206"))
    )
    (comp (ref "R476")
      (value "470")
      (footprint "eagle-import:R6332")
      (libsource (lib "eagle-import") (part "R-EU_R6332"))
    )
    (comp (ref "R477")
      (value "221")
      (footprint "eagle-import:R0805")
      (libsource (lib "eagle-import") (part "R-EU_R0805"))
    )
    (comp (ref "R478")
      (value "222")
      (footprint "eagle-import:R0805")
      (libsource (lib "eagle-import") (part "R-EU_R0805"))
    )
    (comp (ref "R479")
      (value "470")
      (footprint "eagle-import:R6332")
      (libsource (lib "eagle-import") (part "R-EU_R6332"))
    )
    (comp (ref "R480")
      (value "0R")
      (footprint "eagle-import:M1206")
      (libsource (lib "eagle-import") (part "R-EU_M1206"))
    )
    (comp (ref "R481")
      (value "0R")
      (footprint "eagle-import:M1206")
      (libsource (lib "eagle-import") (part "R-EU_M1206"))
    )
    (comp (ref "R482")
      (value "470")
      (footprint "eagle-import:R6332")
      (libsource (lib "eagle-import") (part "R-EU_R6332"))
    )
    (comp (ref "R483")
      (value "221")
      (footprint "eagle-import:R0805")
      (libsource (lib "eagle-import") (part "R-EU_R0805"))
    )
    (comp (ref "R484")
      (value "222")
      (footprint "eagle-import:R0805")
      (libsource (lib "eagle-import") (part "R-EU_R0805"))
    )
    (comp (ref "R485")
      (value "470")
      (footprint "eagle-import:R6332")
      (libsource (lib "eagle-import") (part "R-EU_R6332"))
    )
    (comp (ref "R486")
      (value "0R")
      (footprint "eagle-import:M1206")
      (libsource (lib "eagle-import") (part "R-EU_M1206"))
    )
    (comp (ref "R487")
      (value "0R")
      (footprint "eagle-import:M1206")
      (libsource (lib "eagle-import") (part "R-EU_M1206"))
    )
    (comp (ref "R488")
      (value "0R")
      (footprint "eagle-import:M1206")
      (libsource (lib "eagle-import") (part "R-EU_M1206"))
    )
    (comp (ref "R489")
      (value "0R")
      (footprint "eagle-import:M1206")
      (libsource (lib "eagle-import") (part "R-EU_M1206"))
    )
    (comp (ref "R490")
      (value "0R")
      (footprint "eagle-import:M1206")
      (libsource (lib "eagle-import") (part "R-EU_M1206"))
    )
    (comp (ref "R491")
      (value "0R")
      (footprint "eagle-import:M1206")
      (libsource (lib "eagle-import") (part "R-EU_M1206"))
    )
    (comp (ref "R492")
      (value "0R")
      (footprint "eagle-import:M1206")
      (libsource (lib "eagle-import") (part "R-EU_M1206"))
    )
    (comp (ref "R493")
      (value "221")
      (footprint "eagle-import:R0805")
      (libsource (lib "eagle-import") (part "R-EU_R0805"))
    )
    (comp (ref "R494")
      (value "221")
      (footprint "eagle-import:R0805")
      (libsource (lib "eagle-import") (part "R-EU_R0805"))
    )
    (comp (ref "R495")
      (value "221")
      (footprint "eagle-import:R0805")
      (libsource (lib "eagle-import") (part "R-EU_R0805"))
    )
    (comp (ref "R496")
      (value "221")
      (footprint "eagle-import:R0805")
      (libsource (lib "eagle-import") (part "R-EU_R0805"))
    )
    (comp (ref "R497")
      (value "221")
      (footprint "eagle-import:R0805")
      (libsource (lib "eagle-import") (part "R-EU_R0805"))
    )
    (comp (ref "R498")
      (value "0R")
      (footprint "eagle-import:M1206")
      (libsource (lib "eagle-import") (part "R-EU_M1206"))
    )
    (comp (ref "U$76")
      (value "LTC6803-4")
      (footprint "eagle-import:SSOP44")
      (libsource (lib "eagle-import") (part "LTC6803-4"))
    )
    (comp (ref "U$77")
      (value "SI8841")
      (footprint "eagle-import:SO16")
      (libsource (lib "eagle-import") (part "SI8841"))
    )
    (comp (ref "U$78")
      (value "SI2351DS")
      (footprint "eagle-import:SOT23")
      (libsource (lib "eagle-import") (part "SI2351DS"))
    )
    (comp (ref "U$79")
      (value "SI2351DS")
      (footprint "eagle-import:SOT23")
      (libsource (lib "eagle-import") (part "SI2351DS"))
    )
    (comp (ref "U$80")
      (value "SI2351DS")
      (footprint "eagle-import:SOT23")
      (libsource (lib "eagle-import") (part "SI2351DS"))
    )
    (comp (ref "U$81")
      (value "SI2351DS")
      (footprint "eagle-import:SOT23")
      (libsource (lib "eagle-import") (part "SI2351DS"))
    )
    (comp (ref "U$82")
      (value "SI2351DS")
      (footprint "eagle-import:SOT23")
      (libsource (lib "eagle-import") (part "SI2351DS"))
    )
    (comp (ref "U$83")
      (value "SI2351DS")
      (footprint "eagle-import:SOT23")
      (libsource (lib "eagle-import") (part "SI2351DS"))
    )
    (comp (ref "U$84")
      (value "SI2351DS")
      (footprint "eagle-import:SOT23")
      (libsource (lib "eagle-import") (part "SI2351DS"))
    )
    (comp (ref "U$85")
      (value "SI2351DS")
      (footprint "eagle-import:SOT23")
      (libsource (lib "eagle-import") (part "SI2351DS"))
    )
    (comp (ref "U$86")
      (value "SI2351DS")
      (footprint "eagle-import:SOT23")
      (libsource (lib "eagle-import") (part "SI2351DS"))
    )
    (comp (ref "U$87")
      (value "SI2351DS")
      (footprint "eagle-import:SOT23")
      (libsource (lib "eagle-import") (part "SI2351DS"))
    )
    (comp (ref "U$88")
      (value "SI2351DS")
      (footprint "eagle-import:SOT23")
      (libsource (lib "eagle-import") (part "SI2351DS"))
    )
    (comp (ref "U$89")
      (value "SI2351DS")
      (footprint "eagle-import:SOT23")
      (libsource (lib "eagle-import") (part "SI2351DS"))
    )
    (comp (ref "U$90")
      (value "INDUCTOR")
      (footprint "eagle-import:L2012C")
      (libsource (lib "eagle-import") (part "INDUCTOR"))
    )
    (comp (ref "C55")
      (value "100nF")
      (footprint "eagle-import:C0805K")
      (libsource (lib "eagle-import") (part "C-EUC0805K"))
    )
    (comp (ref "C56")
      (value "100nF")
      (footprint "eagle-import:C0805K")
      (libsource (lib "eagle-import") (part "C-EUC0805K"))
    )
    (comp (ref "C57")
      (value "100nF")
      (footprint "eagle-import:C0805K")
      (libsource (lib "eagle-import") (part "C-EUC0805K"))
    )
    (comp (ref "C58")
      (value "100nF")
      (footprint "eagle-import:C0805K")
      (libsource (lib "eagle-import") (part "C-EUC0805K"))
    )
    (comp (ref "C59")
      (value "100nF")
      (footprint "eagle-import:C0805K")
      (libsource (lib "eagle-import") (part "C-EUC0805K"))
    )
    (comp (ref "C61")
      (value "100nF")
      (footprint "eagle-import:C0805K")
      (libsource (lib "eagle-import") (part "C-EUC0805K"))
    )
    (comp (ref "C62")
      (value "100nF")
      (footprint "eagle-import:C0805K")
      (libsource (lib "eagle-import") (part "C-EUC0805K"))
    )
    (comp (ref "C67")
      (value "100nF")
      (footprint "eagle-import:C0805K")
      (libsource (lib "eagle-import") (part "C-EUC0805K"))
    )
    (comp (ref "C68")
      (value "100nF")
      (footprint "eagle-import:C0805K")
      (libsource (lib "eagle-import") (part "C-EUC0805K"))
    )
    (comp (ref "C70")
      (value "100nF")
      (footprint "eagle-import:C0805K")
      (libsource (lib "eagle-import") (part "C-EUC0805K"))
    )
    (comp (ref "C79")
      (value "100nF")
      (footprint "eagle-import:C0805K")
      (libsource (lib "eagle-import") (part "C-EUC0805K"))
    )
    (comp (ref "C80")
      (value "100nF")
      (footprint "eagle-import:C0805K")
      (libsource (lib "eagle-import") (part "C-EUC0805K"))
    )
    (comp (ref "C81")
      (value "100nF")
      (footprint "eagle-import:C0805K")
      (libsource (lib "eagle-import") (part "C-EUC0805K"))
    )
    (comp (ref "C82")
      (value "100nF")
      (footprint "eagle-import:C0805K")
      (libsource (lib "eagle-import") (part "C-EUC0805K"))
    )
    (comp (ref "C83")
      (value "100nF")
      (footprint "eagle-import:C0805K")
      (libsource (lib "eagle-import") (part "C-EUC0805K"))
    )
    (comp (ref "C84")
      (value "100nF")
      (footprint "eagle-import:C0805K")
      (libsource (lib "eagle-import") (part "C-EUC0805K"))
    )
    (comp (ref "C85")
      (value "100nF")
      (footprint "eagle-import:C0805K")
      (libsource (lib "eagle-import") (part "C-EUC0805K"))
    )
    (comp (ref "D61")
      (value "7Z5")
      (footprint "eagle-import:SMB")
      (libsource (lib "eagle-import") (part "DIODE-SMB"))
    )
    (comp (ref "D62")
      (value "7Z5")
      (footprint "eagle-import:SMB")
      (libsource (lib "eagle-import") (part "DIODE-SMB"))
    )
    (comp (ref "D63")
      (value "7Z5")
      (footprint "eagle-import:SMB")
      (libsource (lib "eagle-import") (part "DIODE-SMB"))
    )
    (comp (ref "D64")
      (value "7Z5")
      (footprint "eagle-import:SMB")
      (libsource (lib "eagle-import") (part "DIODE-SMB"))
    )
    (comp (ref "D65")
      (value "7Z5")
      (footprint "eagle-import:SMB")
      (libsource (lib "eagle-import") (part "DIODE-SMB"))
    )
    (comp (ref "D66")
      (value "7Z5")
      (footprint "eagle-import:SMB")
      (libsource (lib "eagle-import") (part "DIODE-SMB"))
    )
    (comp (ref "D67")
      (value "7Z5")
      (footprint "eagle-import:SMB")
      (libsource (lib "eagle-import") (part "DIODE-SMB"))
    )
    (comp (ref "D68")
      (value "7Z5")
      (footprint "eagle-import:SMB")
      (libsource (lib "eagle-import") (part "DIODE-SMB"))
    )
    (comp (ref "D69")
      (value "7Z5")
      (footprint "eagle-import:SMB")
      (libsource (lib "eagle-import") (part "DIODE-SMB"))
    )
    (comp (ref "D70")
      (value "7Z5")
      (footprint "eagle-import:SMB")
      (libsource (lib "eagle-import") (part "DIODE-SMB"))
    )
    (comp (ref "D71")
      (value "7Z5")
      (footprint "eagle-import:SMB")
      (libsource (lib "eagle-import") (part "DIODE-SMB"))
    )
    (comp (ref "D72")
      (value "7Z5")
      (footprint "eagle-import:SMB")
      (libsource (lib "eagle-import") (part "DIODE-SMB"))
    )
    (comp (ref "D73")
      (value "7Z5")
      (footprint "eagle-import:SMB")
      (libsource (lib "eagle-import") (part "DIODE-SMB"))
    )
    (comp (ref "D74")
      (value "7Z5")
      (footprint "eagle-import:SMB")
      (libsource (lib "eagle-import") (part "DIODE-SMB"))
    )
    (comp (ref "D75")
      (value "DIODE-SOD123")
      (footprint "eagle-import:SOD123")
      (libsource (lib "eagle-import") (part "DIODE-SOD123"))
    )
    (comp (ref "R333")
      (value "470")
      (footprint "eagle-import:R6332")
      (libsource (lib "eagle-import") (part "R-EU_R6332"))
    )
    (comp (ref "R334")
      (value "221")
      (footprint "eagle-import:R0805")
      (libsource (lib "eagle-import") (part "R-EU_R0805"))
    )
    (comp (ref "R335")
      (value "222")
      (footprint "eagle-import:R0805")
      (libsource (lib "eagle-import") (part "R-EU_R0805"))
    )
    (comp (ref "R336")
      (value "470")
      (footprint "eagle-import:R6332")
      (libsource (lib "eagle-import") (part "R-EU_R6332"))
    )
    (comp (ref "R337")
      (value "0R")
      (footprint "eagle-import:M1206")
      (libsource (lib "eagle-import") (part "R-EU_M1206"))
    )
    (comp (ref "R338")
      (value "0R")
      (footprint "eagle-import:M1206")
      (libsource (lib "eagle-import") (part "R-EU_M1206"))
    )
    (comp (ref "R339")
      (value "470")
      (footprint "eagle-import:R6332")
      (libsource (lib "eagle-import") (part "R-EU_R6332"))
    )
    (comp (ref "R340")
      (value "221")
      (footprint "eagle-import:R0805")
      (libsource (lib "eagle-import") (part "R-EU_R0805"))
    )
    (comp (ref "R341")
      (value "222")
      (footprint "eagle-import:R0805")
      (libsource (lib "eagle-import") (part "R-EU_R0805"))
    )
    (comp (ref "R342")
      (value "470")
      (footprint "eagle-import:R6332")
      (libsource (lib "eagle-import") (part "R-EU_R6332"))
    )
    (comp (ref "R343")
      (value "0R")
      (footprint "eagle-import:M1206")
      (libsource (lib "eagle-import") (part "R-EU_M1206"))
    )
    (comp (ref "R344")
      (value "0R")
      (footprint "eagle-import:M1206")
      (libsource (lib "eagle-import") (part "R-EU_M1206"))
    )
    (comp (ref "R345")
      (value "470")
      (footprint "eagle-import:R6332")
      (libsource (lib "eagle-import") (part "R-EU_R6332"))
    )
    (comp (ref "R346")
      (value "221")
      (footprint "eagle-import:R0805")
      (libsource (lib "eagle-import") (part "R-EU_R0805"))
    )
    (comp (ref "R347")
      (value "222")
      (footprint "eagle-import:R0805")
      (libsource (lib "eagle-import") (part "R-EU_R0805"))
    )
    (comp (ref "R348")
      (value "470")
      (footprint "eagle-import:R6332")
      (libsource (lib "eagle-import") (part "R-EU_R6332"))
    )
    (comp (ref "R349")
      (value "0R")
      (footprint "eagle-import:M1206")
      (libsource (lib "eagle-import") (part "R-EU_M1206"))
    )
    (comp (ref "R350")
      (value "0R")
      (footprint "eagle-import:M1206")
      (libsource (lib "eagle-import") (part "R-EU_M1206"))
    )
    (comp (ref "R351")
      (value "470")
      (footprint "eagle-import:R6332")
      (libsource (lib "eagle-import") (part "R-EU_R6332"))
    )
    (comp (ref "R352")
      (value "221")
      (footprint "eagle-import:R0805")
      (libsource (lib "eagle-import") (part "R-EU_R0805"))
    )
    (comp (ref "R353")
      (value "222")
      (footprint "eagle-import:R0805")
      (libsource (lib "eagle-import") (part "R-EU_R0805"))
    )
    (comp (ref "R354")
      (value "470")
      (footprint "eagle-import:R6332")
      (libsource (lib "eagle-import") (part "R-EU_R6332"))
    )
    (comp (ref "R355")
      (value "0R")
      (footprint "eagle-import:M1206")
      (libsource (lib "eagle-import") (part "R-EU_M1206"))
    )
    (comp (ref "R356")
      (value "0R")
      (footprint "eagle-import:M1206")
      (libsource (lib "eagle-import") (part "R-EU_M1206"))
    )
    (comp (ref "R357")
      (value "470")
      (footprint "eagle-import:R6332")
      (libsource (lib "eagle-import") (part "R-EU_R6332"))
    )
    (comp (ref "R358")
      (value "221")
      (footprint "eagle-import:R0805")
      (libsource (lib "eagle-import") (part "R-EU_R0805"))
    )
    (comp (ref "R359")
      (value "222")
      (footprint "eagle-import:R0805")
      (libsource (lib "eagle-import") (part "R-EU_R0805"))
    )
    (comp (ref "R360")
      (value "470")
      (footprint "eagle-import:R6332")
      (libsource (lib "eagle-import") (part "R-EU_R6332"))
    )
    (comp (ref "R361")
      (value "0R")
      (footprint "eagle-import:M1206")
      (libsource (lib "eagle-import") (part "R-EU_M1206"))
    )
    (comp (ref "R362")
      (value "0R")
      (footprint "eagle-import:M1206")
      (libsource (lib "eagle-import") (part "R-EU_M1206"))
    )
    (comp (ref "R363")
      (value "470")
      (footprint "eagle-import:R6332")
      (libsource (lib "eagle-import") (part "R-EU_R6332"))
    )
    (comp (ref "R364")
      (value "221")
      (footprint "eagle-import:R0805")
      (libsource (lib "eagle-import") (part "R-EU_R0805"))
    )
    (comp (ref "R365")
      (value "222")
      (footprint "eagle-import:R0805")
      (libsource (lib "eagle-import") (part "R-EU_R0805"))
    )
    (comp (ref "R366")
      (value "470")
      (footprint "eagle-import:R6332")
      (libsource (lib "eagle-import") (part "R-EU_R6332"))
    )
    (comp (ref "R367")
      (value "0R")
      (footprint "eagle-import:M1206")
      (libsource (lib "eagle-import") (part "R-EU_M1206"))
    )
    (comp (ref "R368")
      (value "0R")
      (footprint "eagle-import:M1206")
      (libsource (lib "eagle-import") (part "R-EU_M1206"))
    )
    (comp (ref "R369")
      (value "470")
      (footprint "eagle-import:R6332")
      (libsource (lib "eagle-import") (part "R-EU_R6332"))
    )
    (comp (ref "R370")
      (value "221")
      (footprint "eagle-import:R0805")
      (libsource (lib "eagle-import") (part "R-EU_R0805"))
    )
    (comp (ref "R371")
      (value "222")
      (footprint "eagle-import:R0805")
      (libsource (lib "eagle-import") (part "R-EU_R0805"))
    )
    (comp (ref "R372")
      (value "470")
      (footprint "eagle-import:R6332")
      (libsource (lib "eagle-import") (part "R-EU_R6332"))
    )
    (comp (ref "R373")
      (value "0R")
      (footprint "eagle-import:M1206")
      (libsource (lib "eagle-import") (part "R-EU_M1206"))
    )
    (comp (ref "R374")
      (value "0R")
      (footprint "eagle-import:M1206")
      (libsource (lib "eagle-import") (part "R-EU_M1206"))
    )
    (comp (ref "R375")
      (value "470")
      (footprint "eagle-import:R6332")
      (libsource (lib "eagle-import") (part "R-EU_R6332"))
    )
    (comp (ref "R376")
      (value "221")
      (footprint "eagle-import:R0805")
      (libsource (lib "eagle-import") (part "R-EU_R0805"))
    )
    (comp (ref "R377")
      (value "222")
      (footprint "eagle-import:R0805")
      (libsource (lib "eagle-import") (part "R-EU_R0805"))
    )
    (comp (ref "R378")
      (value "470")
      (footprint "eagle-import:R6332")
      (libsource (lib "eagle-import") (part "R-EU_R6332"))
    )
    (comp (ref "R379")
      (value "0R")
      (footprint "eagle-import:M1206")
      (libsource (lib "eagle-import") (part "R-EU_M1206"))
    )
    (comp (ref "R380")
      (value "0R")
      (footprint "eagle-import:M1206")
      (libsource (lib "eagle-import") (part "R-EU_M1206"))
    )
    (comp (ref "R381")
      (value "470")
      (footprint "eagle-import:R6332")
      (libsource (lib "eagle-import") (part "R-EU_R6332"))
    )
    (comp (ref "R382")
      (value "221")
      (footprint "eagle-import:R0805")
      (libsource (lib "eagle-import") (part "R-EU_R0805"))
    )
    (comp (ref "R383")
      (value "222")
      (footprint "eagle-import:R0805")
      (libsource (lib "eagle-import") (part "R-EU_R0805"))
    )
    (comp (ref "R384")
      (value "470")
      (footprint "eagle-import:R6332")
      (libsource (lib "eagle-import") (part "R-EU_R6332"))
    )
    (comp (ref "R385")
      (value "0R")
      (footprint "eagle-import:M1206")
      (libsource (lib "eagle-import") (part "R-EU_M1206"))
    )
    (comp (ref "R386")
      (value "0R")
      (footprint "eagle-import:M1206")
      (libsource (lib "eagle-import") (part "R-EU_M1206"))
    )
    (comp (ref "R387")
      (value "470")
      (footprint "eagle-import:R6332")
      (libsource (lib "eagle-import") (part "R-EU_R6332"))
    )
    (comp (ref "R388")
      (value "221")
      (footprint "eagle-import:R0805")
      (libsource (lib "eagle-import") (part "R-EU_R0805"))
    )
    (comp (ref "R389")
      (value "222")
      (footprint "eagle-import:R0805")
      (libsource (lib "eagle-import") (part "R-EU_R0805"))
    )
    (comp (ref "R390")
      (value "470")
      (footprint "eagle-import:R6332")
      (libsource (lib "eagle-import") (part "R-EU_R6332"))
    )
    (comp (ref "R391")
      (value "0R")
      (footprint "eagle-import:M1206")
      (libsource (lib "eagle-import") (part "R-EU_M1206"))
    )
    (comp (ref "R392")
      (value "0R")
      (footprint "eagle-import:M1206")
      (libsource (lib "eagle-import") (part "R-EU_M1206"))
    )
    (comp (ref "R393")
      (value "470")
      (footprint "eagle-import:R6332")
      (libsource (lib "eagle-import") (part "R-EU_R6332"))
    )
    (comp (ref "R394")
      (value "221")
      (footprint "eagle-import:R0805")
      (libsource (lib "eagle-import") (part "R-EU_R0805"))
    )
    (comp (ref "R395")
      (value "222")
      (footprint "eagle-import:R0805")
      (libsource (lib "eagle-import") (part "R-EU_R0805"))
    )
    (comp (ref "R396")
      (value "470")
      (footprint "eagle-import:R6332")
      (libsource (lib "eagle-import") (part "R-EU_R6332"))
    )
    (comp (ref "R397")
      (value "0R")
      (footprint "eagle-import:M1206")
      (libsource (lib "eagle-import") (part "R-EU_M1206"))
    )
    (comp (ref "R398")
      (value "0R")
      (footprint "eagle-import:M1206")
      (libsource (lib "eagle-import") (part "R-EU_M1206"))
    )
    (comp (ref "R399")
      (value "470")
      (footprint "eagle-import:R6332")
      (libsource (lib "eagle-import") (part "R-EU_R6332"))
    )
    (comp (ref "R400")
      (value "221")
      (footprint "eagle-import:R0805")
      (libsource (lib "eagle-import") (part "R-EU_R0805"))
    )
    (comp (ref "R401")
      (value "222")
      (footprint "eagle-import:R0805")
      (libsource (lib "eagle-import") (part "R-EU_R0805"))
    )
    (comp (ref "R402")
      (value "470")
      (footprint "eagle-import:R6332")
      (libsource (lib "eagle-import") (part "R-EU_R6332"))
    )
    (comp (ref "R403")
      (value "0R")
      (footprint "eagle-import:M1206")
      (libsource (lib "eagle-import") (part "R-EU_M1206"))
    )
    (comp (ref "R404")
      (value "0R")
      (footprint "eagle-import:M1206")
      (libsource (lib "eagle-import") (part "R-EU_M1206"))
    )
    (comp (ref "R405")
      (value "0R")
      (footprint "eagle-import:M1206")
      (libsource (lib "eagle-import") (part "R-EU_M1206"))
    )
    (comp (ref "R406")
      (value "0R")
      (footprint "eagle-import:M1206")
      (libsource (lib "eagle-import") (part "R-EU_M1206"))
    )
    (comp (ref "R407")
      (value "0R")
      (footprint "eagle-import:M1206")
      (libsource (lib "eagle-import") (part "R-EU_M1206"))
    )
    (comp (ref "R408")
      (value "0R")
      (footprint "eagle-import:M1206")
      (libsource (lib "eagle-import") (part "R-EU_M1206"))
    )
    (comp (ref "R409")
      (value "0R")
      (footprint "eagle-import:M1206")
      (libsource (lib "eagle-import") (part "R-EU_M1206"))
    )
    (comp (ref "R410")
      (value "221")
      (footprint "eagle-import:R0805")
      (libsource (lib "eagle-import") (part "R-EU_R0805"))
    )
    (comp (ref "R411")
      (value "221")
      (footprint "eagle-import:R0805")
      (libsource (lib "eagle-import") (part "R-EU_R0805"))
    )
    (comp (ref "R412")
      (value "221")
      (footprint "eagle-import:R0805")
      (libsource (lib "eagle-import") (part "R-EU_R0805"))
    )
    (comp (ref "R413")
      (value "221")
      (footprint "eagle-import:R0805")
      (libsource (lib "eagle-import") (part "R-EU_R0805"))
    )
    (comp (ref "R414")
      (value "221")
      (footprint "eagle-import:R0805")
      (libsource (lib "eagle-import") (part "R-EU_R0805"))
    )
    (comp (ref "R415")
      (value "0R")
      (footprint "eagle-import:M1206")
      (libsource (lib "eagle-import") (part "R-EU_M1206"))
    )
    (comp (ref "U$61")
      (value "LTC6803-4")
      (footprint "eagle-import:SSOP44")
      (libsource (lib "eagle-import") (part "LTC6803-4"))
    )
    (comp (ref "U$62")
      (value "SI8841")
      (footprint "eagle-import:SO16")
      (libsource (lib "eagle-import") (part "SI8841"))
    )
    (comp (ref "U$63")
      (value "SI2351DS")
      (footprint "eagle-import:SOT23")
      (libsource (lib "eagle-import") (part "SI2351DS"))
    )
    (comp (ref "U$64")
      (value "SI2351DS")
      (footprint "eagle-import:SOT23")
      (libsource (lib "eagle-import") (part "SI2351DS"))
    )
    (comp (ref "U$65")
      (value "SI2351DS")
      (footprint "eagle-import:SOT23")
      (libsource (lib "eagle-import") (part "SI2351DS"))
    )
    (comp (ref "U$66")
      (value "SI2351DS")
      (footprint "eagle-import:SOT23")
      (libsource (lib "eagle-import") (part "SI2351DS"))
    )
    (comp (ref "U$67")
      (value "SI2351DS")
      (footprint "eagle-import:SOT23")
      (libsource (lib "eagle-import") (part "SI2351DS"))
    )
    (comp (ref "U$68")
      (value "SI2351DS")
      (footprint "eagle-import:SOT23")
      (libsource (lib "eagle-import") (part "SI2351DS"))
    )
    (comp (ref "U$69")
      (value "SI2351DS")
      (footprint "eagle-import:SOT23")
      (libsource (lib "eagle-import") (part "SI2351DS"))
    )
    (comp (ref "U$70")
      (value "SI2351DS")
      (footprint "eagle-import:SOT23")
      (libsource (lib "eagle-import") (part "SI2351DS"))
    )
    (comp (ref "U$71")
      (value "SI2351DS")
      (footprint "eagle-import:SOT23")
      (libsource (lib "eagle-import") (part "SI2351DS"))
    )
    (comp (ref "U$72")
      (value "SI2351DS")
      (footprint "eagle-import:SOT23")
      (libsource (lib "eagle-import") (part "SI2351DS"))
    )
    (comp (ref "U$73")
      (value "SI2351DS")
      (footprint "eagle-import:SOT23")
      (libsource (lib "eagle-import") (part "SI2351DS"))
    )
    (comp (ref "U$74")
      (value "SI2351DS")
      (footprint "eagle-import:SOT23")
      (libsource (lib "eagle-import") (part "SI2351DS"))
    )
    (comp (ref "U$75")
      (value "INDUCTOR")
      (footprint "eagle-import:L2012C")
      (libsource (lib "eagle-import") (part "INDUCTOR"))
    )
    (comp (ref "C1")
      (value "100nF")
      (footprint "eagle-import:C0805K")
      (libsource (lib "eagle-import") (part "C-EUC0805K"))
    )
    (comp (ref "C2")
      (value "100nF")
      (footprint "eagle-import:C0805K")
      (libsource (lib "eagle-import") (part "C-EUC0805K"))
    )
    (comp (ref "C3")
      (value "100nF")
      (footprint "eagle-import:C0805K")
      (libsource (lib "eagle-import") (part "C-EUC0805K"))
    )
    (comp (ref "C4")
      (value "100nF")
      (footprint "eagle-import:C0805K")
      (libsource (lib "eagle-import") (part "C-EUC0805K"))
    )
    (comp (ref "C5")
      (value "100nF")
      (footprint "eagle-import:C0805K")
      (libsource (lib "eagle-import") (part "C-EUC0805K"))
    )
    (comp (ref "C6")
      (value "100nF")
      (footprint "eagle-import:C0805K")
      (libsource (lib "eagle-import") (part "C-EUC0805K"))
    )
    (comp (ref "C7")
      (value "100nF")
      (footprint "eagle-import:C0805K")
      (libsource (lib "eagle-import") (part "C-EUC0805K"))
    )
    (comp (ref "C8")
      (value "100nF")
      (footprint "eagle-import:C0805K")
      (libsource (lib "eagle-import") (part "C-EUC0805K"))
    )
    (comp (ref "C9")
      (value "100nF")
      (footprint "eagle-import:C0805K")
      (libsource (lib "eagle-import") (part "C-EUC0805K"))
    )
    (comp (ref "C10")
      (value "100nF")
      (footprint "eagle-import:C0805K")
      (libsource (lib "eagle-import") (part "C-EUC0805K"))
    )
    (comp (ref "C11")
      (value "100nF")
      (footprint "eagle-import:C0805K")
      (libsource (lib "eagle-import") (part "C-EUC0805K"))
    )
    (comp (ref "C12")
      (value "100nF")
      (footprint "eagle-import:C0805K")
      (libsource (lib "eagle-import") (part "C-EUC0805K"))
    )
    (comp (ref "C13")
      (value "100nF")
      (footprint "eagle-import:C0805K")
      (libsource (lib "eagle-import") (part "C-EUC0805K"))
    )
    (comp (ref "C14")
      (value "100nF")
      (footprint "eagle-import:C0805K")
      (libsource (lib "eagle-import") (part "C-EUC0805K"))
    )
    (comp (ref "C15")
      (value "100nF")
      (footprint "eagle-import:C0805K")
      (libsource (lib "eagle-import") (part "C-EUC0805K"))
    )
    (comp (ref "C16")
      (value "100nF")
      (footprint "eagle-import:C0805K")
      (libsource (lib "eagle-import") (part "C-EUC0805K"))
    )
    (comp (ref "C17")
      (value "100nF")
      (footprint "eagle-import:C0805K")
      (libsource (lib "eagle-import") (part "C-EUC0805K"))
    )
    (comp (ref "D1")
      (value "7Z5")
      (footprint "eagle-import:SMB")
      (libsource (lib "eagle-import") (part "DIODE-SMB"))
    )
    (comp (ref "D2")
      (value "7Z5")
      (footprint "eagle-import:SMB")
      (libsource (lib "eagle-import") (part "DIODE-SMB"))
    )
    (comp (ref "D3")
      (value "7Z5")
      (footprint "eagle-import:SMB")
      (libsource (lib "eagle-import") (part "DIODE-SMB"))
    )
    (comp (ref "D4")
      (value "7Z5")
      (footprint "eagle-import:SMB")
      (libsource (lib "eagle-import") (part "DIODE-SMB"))
    )
    (comp (ref "D5")
      (value "7Z5")
      (footprint "eagle-import:SMB")
      (libsource (lib "eagle-import") (part "DIODE-SMB"))
    )
    (comp (ref "D6")
      (value "7Z5")
      (footprint "eagle-import:SMB")
      (libsource (lib "eagle-import") (part "DIODE-SMB"))
    )
    (comp (ref "D7")
      (value "7Z5")
      (footprint "eagle-import:SMB")
      (libsource (lib "eagle-import") (part "DIODE-SMB"))
    )
    (comp (ref "D8")
      (value "7Z5")
      (footprint "eagle-import:SMB")
      (libsource (lib "eagle-import") (part "DIODE-SMB"))
    )
    (comp (ref "D9")
      (value "7Z5")
      (footprint "eagle-import:SMB")
      (libsource (lib "eagle-import") (part "DIODE-SMB"))
    )
    (comp (ref "D10")
      (value "7Z5")
      (footprint "eagle-import:SMB")
      (libsource (lib "eagle-import") (part "DIODE-SMB"))
    )
    (comp (ref "D11")
      (value "7Z5")
      (footprint "eagle-import:SMB")
      (libsource (lib "eagle-import") (part "DIODE-SMB"))
    )
    (comp (ref "D12")
      (value "7Z5")
      (footprint "eagle-import:SMB")
      (libsource (lib "eagle-import") (part "DIODE-SMB"))
    )
    (comp (ref "D13")
      (value "7Z5")
      (footprint "eagle-import:SMB")
      (libsource (lib "eagle-import") (part "DIODE-SMB"))
    )
    (comp (ref "D14")
      (value "7Z5")
      (footprint "eagle-import:SMB")
      (libsource (lib "eagle-import") (part "DIODE-SMB"))
    )
    (comp (ref "D33")
      (value "DIODE-SOD123")
      (footprint "eagle-import:SOD123")
      (libsource (lib "eagle-import") (part "DIODE-SOD123"))
    )
    (comp (ref "JP1")
      (value "PINHD-1X6")
      (footprint "eagle-import:1X06")
      (libsource (lib "eagle-import") (part "PINHD-1X6"))
    )
    (comp (ref "R1")
      (value "0R")
      (footprint "eagle-import:M1206")
      (libsource (lib "eagle-import") (part "R-EU_M1206"))
    )
    (comp (ref "R3")
      (value "470")
      (footprint "eagle-import:R6332")
      (libsource (lib "eagle-import") (part "R-EU_R6332"))
    )
    (comp (ref "R4")
      (value "221")
      (footprint "eagle-import:R0805")
      (libsource (lib "eagle-import") (part "R-EU_R0805"))
    )
    (comp (ref "R5")
      (value "222")
      (footprint "eagle-import:R0805")
      (libsource (lib "eagle-import") (part "R-EU_R0805"))
    )
    (comp (ref "R6")
      (value "470")
      (footprint "eagle-import:R6332")
      (libsource (lib "eagle-import") (part "R-EU_R6332"))
    )
    (comp (ref "R7")
      (value "0R")
      (footprint "eagle-import:M1206")
      (libsource (lib "eagle-import") (part "R-EU_M1206"))
    )
    (comp (ref "R8")
      (value "0R")
      (footprint "eagle-import:M1206")
      (libsource (lib "eagle-import") (part "R-EU_M1206"))
    )
    (comp (ref "R9")
      (value "470")
      (footprint "eagle-import:R6332")
      (libsource (lib "eagle-import") (part "R-EU_R6332"))
    )
    (comp (ref "R10")
      (value "221")
      (footprint "eagle-import:R0805")
      (libsource (lib "eagle-import") (part "R-EU_R0805"))
    )
    (comp (ref "R11")
      (value "222")
      (footprint "eagle-import:R0805")
      (libsource (lib "eagle-import") (part "R-EU_R0805"))
    )
    (comp (ref "R12")
      (value "470")
      (footprint "eagle-import:R6332")
      (libsource (lib "eagle-import") (part "R-EU_R6332"))
    )
    (comp (ref "R13")
      (value "0R")
      (footprint "eagle-import:M1206")
      (libsource (lib "eagle-import") (part "R-EU_M1206"))
    )
    (comp (ref "R14")
      (value "0R")
      (footprint "eagle-import:M1206")
      (libsource (lib "eagle-import") (part "R-EU_M1206"))
    )
    (comp (ref "R15")
      (value "470")
      (footprint "eagle-import:R6332")
      (libsource (lib "eagle-import") (part "R-EU_R6332"))
    )
    (comp (ref "R16")
      (value "221")
      (footprint "eagle-import:R0805")
      (libsource (lib "eagle-import") (part "R-EU_R0805"))
    )
    (comp (ref "R17")
      (value "222")
      (footprint "eagle-import:R0805")
      (libsource (lib "eagle-import") (part "R-EU_R0805"))
    )
    (comp (ref "R18")
      (value "470")
      (footprint "eagle-import:R6332")
      (libsource (lib "eagle-import") (part "R-EU_R6332"))
    )
    (comp (ref "R19")
      (value "0R")
      (footprint "eagle-import:M1206")
      (libsource (lib "eagle-import") (part "R-EU_M1206"))
    )
    (comp (ref "R20")
      (value "0R")
      (footprint "eagle-import:M1206")
      (libsource (lib "eagle-import") (part "R-EU_M1206"))
    )
    (comp (ref "R21")
      (value "470")
      (footprint "eagle-import:R6332")
      (libsource (lib "eagle-import") (part "R-EU_R6332"))
    )
    (comp (ref "R22")
      (value "221")
      (footprint "eagle-import:R0805")
      (libsource (lib "eagle-import") (part "R-EU_R0805"))
    )
    (comp (ref "R23")
      (value "222")
      (footprint "eagle-import:R0805")
      (libsource (lib "eagle-import") (part "R-EU_R0805"))
    )
    (comp (ref "R24")
      (value "470")
      (footprint "eagle-import:R6332")
      (libsource (lib "eagle-import") (part "R-EU_R6332"))
    )
    (comp (ref "R25")
      (value "0R")
      (footprint "eagle-import:M1206")
      (libsource (lib "eagle-import") (part "R-EU_M1206"))
    )
    (comp (ref "R26")
      (value "0R")
      (footprint "eagle-import:M1206")
      (libsource (lib "eagle-import") (part "R-EU_M1206"))
    )
    (comp (ref "R27")
      (value "470")
      (footprint "eagle-import:R6332")
      (libsource (lib "eagle-import") (part "R-EU_R6332"))
    )
    (comp (ref "R28")
      (value "221")
      (footprint "eagle-import:R0805")
      (libsource (lib "eagle-import") (part "R-EU_R0805"))
    )
    (comp (ref "R29")
      (value "222")
      (footprint "eagle-import:R0805")
      (libsource (lib "eagle-import") (part "R-EU_R0805"))
    )
    (comp (ref "R30")
      (value "470")
      (footprint "eagle-import:R6332")
      (libsource (lib "eagle-import") (part "R-EU_R6332"))
    )
    (comp (ref "R31")
      (value "0R")
      (footprint "eagle-import:M1206")
      (libsource (lib "eagle-import") (part "R-EU_M1206"))
    )
    (comp (ref "R32")
      (value "0R")
      (footprint "eagle-import:M1206")
      (libsource (lib "eagle-import") (part "R-EU_M1206"))
    )
    (comp (ref "R33")
      (value "470")
      (footprint "eagle-import:R6332")
      (libsource (lib "eagle-import") (part "R-EU_R6332"))
    )
    (comp (ref "R34")
      (value "221")
      (footprint "eagle-import:R0805")
      (libsource (lib "eagle-import") (part "R-EU_R0805"))
    )
    (comp (ref "R35")
      (value "222")
      (footprint "eagle-import:R0805")
      (libsource (lib "eagle-import") (part "R-EU_R0805"))
    )
    (comp (ref "R36")
      (value "470")
      (footprint "eagle-import:R6332")
      (libsource (lib "eagle-import") (part "R-EU_R6332"))
    )
    (comp (ref "R37")
      (value "0R")
      (footprint "eagle-import:M1206")
      (libsource (lib "eagle-import") (part "R-EU_M1206"))
    )
    (comp (ref "R38")
      (value "0R")
      (footprint "eagle-import:M1206")
      (libsource (lib "eagle-import") (part "R-EU_M1206"))
    )
    (comp (ref "R39")
      (value "470")
      (footprint "eagle-import:R6332")
      (libsource (lib "eagle-import") (part "R-EU_R6332"))
    )
    (comp (ref "R40")
      (value "221")
      (footprint "eagle-import:R0805")
      (libsource (lib "eagle-import") (part "R-EU_R0805"))
    )
    (comp (ref "R41")
      (value "222")
      (footprint "eagle-import:R0805")
      (libsource (lib "eagle-import") (part "R-EU_R0805"))
    )
    (comp (ref "R42")
      (value "470")
      (footprint "eagle-import:R6332")
      (libsource (lib "eagle-import") (part "R-EU_R6332"))
    )
    (comp (ref "R43")
      (value "0R")
      (footprint "eagle-import:M1206")
      (libsource (lib "eagle-import") (part "R-EU_M1206"))
    )
    (comp (ref "R44")
      (value "0R")
      (footprint "eagle-import:M1206")
      (libsource (lib "eagle-import") (part "R-EU_M1206"))
    )
    (comp (ref "R45")
      (value "470")
      (footprint "eagle-import:R6332")
      (libsource (lib "eagle-import") (part "R-EU_R6332"))
    )
    (comp (ref "R46")
      (value "221")
      (footprint "eagle-import:R0805")
      (libsource (lib "eagle-import") (part "R-EU_R0805"))
    )
    (comp (ref "R47")
      (value "222")
      (footprint "eagle-import:R0805")
      (libsource (lib "eagle-import") (part "R-EU_R0805"))
    )
    (comp (ref "R48")
      (value "470")
      (footprint "eagle-import:R6332")
      (libsource (lib "eagle-import") (part "R-EU_R6332"))
    )
    (comp (ref "R49")
      (value "0R")
      (footprint "eagle-import:M1206")
      (libsource (lib "eagle-import") (part "R-EU_M1206"))
    )
    (comp (ref "R50")
      (value "0R")
      (footprint "eagle-import:M1206")
      (libsource (lib "eagle-import") (part "R-EU_M1206"))
    )
    (comp (ref "R51")
      (value "470")
      (footprint "eagle-import:R6332")
      (libsource (lib "eagle-import") (part "R-EU_R6332"))
    )
    (comp (ref "R52")
      (value "221")
      (footprint "eagle-import:R0805")
      (libsource (lib "eagle-import") (part "R-EU_R0805"))
    )
    (comp (ref "R53")
      (value "222")
      (footprint "eagle-import:R0805")
      (libsource (lib "eagle-import") (part "R-EU_R0805"))
    )
    (comp (ref "R54")
      (value "470")
      (footprint "eagle-import:R6332")
      (libsource (lib "eagle-import") (part "R-EU_R6332"))
    )
    (comp (ref "R55")
      (value "0R")
      (footprint "eagle-import:M1206")
      (libsource (lib "eagle-import") (part "R-EU_M1206"))
    )
    (comp (ref "R56")
      (value "0R")
      (footprint "eagle-import:M1206")
      (libsource (lib "eagle-import") (part "R-EU_M1206"))
    )
    (comp (ref "R57")
      (value "470")
      (footprint "eagle-import:R6332")
      (libsource (lib "eagle-import") (part "R-EU_R6332"))
    )
    (comp (ref "R58")
      (value "221")
      (footprint "eagle-import:R0805")
      (libsource (lib "eagle-import") (part "R-EU_R0805"))
    )
    (comp (ref "R59")
      (value "222")
      (footprint "eagle-import:R0805")
      (libsource (lib "eagle-import") (part "R-EU_R0805"))
    )
    (comp (ref "R60")
      (value "470")
      (footprint "eagle-import:R6332")
      (libsource (lib "eagle-import") (part "R-EU_R6332"))
    )
    (comp (ref "R61")
      (value "0R")
      (footprint "eagle-import:M1206")
      (libsource (lib "eagle-import") (part "R-EU_M1206"))
    )
    (comp (ref "R62")
      (value "0R")
      (footprint "eagle-import:M1206")
      (libsource (lib "eagle-import") (part "R-EU_M1206"))
    )
    (comp (ref "R63")
      (value "470")
      (footprint "eagle-import:R6332")
      (libsource (lib "eagle-import") (part "R-EU_R6332"))
    )
    (comp (ref "R64")
      (value "221")
      (footprint "eagle-import:R0805")
      (libsource (lib "eagle-import") (part "R-EU_R0805"))
    )
    (comp (ref "R65")
      (value "222")
      (footprint "eagle-import:R0805")
      (libsource (lib "eagle-import") (part "R-EU_R0805"))
    )
    (comp (ref "R66")
      (value "470")
      (footprint "eagle-import:R6332")
      (libsource (lib "eagle-import") (part "R-EU_R6332"))
    )
    (comp (ref "R67")
      (value "0R")
      (footprint "eagle-import:M1206")
      (libsource (lib "eagle-import") (part "R-EU_M1206"))
    )
    (comp (ref "R68")
      (value "0R")
      (footprint "eagle-import:M1206")
      (libsource (lib "eagle-import") (part "R-EU_M1206"))
    )
    (comp (ref "R69")
      (value "470")
      (footprint "eagle-import:R6332")
      (libsource (lib "eagle-import") (part "R-EU_R6332"))
    )
    (comp (ref "R70")
      (value "221")
      (footprint "eagle-import:R0805")
      (libsource (lib "eagle-import") (part "R-EU_R0805"))
    )
    (comp (ref "R71")
      (value "222")
      (footprint "eagle-import:R0805")
      (libsource (lib "eagle-import") (part "R-EU_R0805"))
    )
    (comp (ref "R72")
      (value "470")
      (footprint "eagle-import:R6332")
      (libsource (lib "eagle-import") (part "R-EU_R6332"))
    )
    (comp (ref "R73")
      (value "0R")
      (footprint "eagle-import:M1206")
      (libsource (lib "eagle-import") (part "R-EU_M1206"))
    )
    (comp (ref "R74")
      (value "0R")
      (footprint "eagle-import:M1206")
      (libsource (lib "eagle-import") (part "R-EU_M1206"))
    )
    (comp (ref "R75")
      (value "0R")
      (footprint "eagle-import:M1206")
      (libsource (lib "eagle-import") (part "R-EU_M1206"))
    )
    (comp (ref "R76")
      (value "0R")
      (footprint "eagle-import:M1206")
      (libsource (lib "eagle-import") (part "R-EU_M1206"))
    )
    (comp (ref "R77")
      (value "0R")
      (footprint "eagle-import:M1206")
      (libsource (lib "eagle-import") (part "R-EU_M1206"))
    )
    (comp (ref "R79")
      (value "0R")
      (footprint "eagle-import:M1206")
      (libsource (lib "eagle-import") (part "R-EU_M1206"))
    )
    (comp (ref "R80")
      (value "0R")
      (footprint "eagle-import:M1206")
      (libsource (lib "eagle-import") (part "R-EU_M1206"))
    )
    (comp (ref "R81")
      (value "221")
      (footprint "eagle-import:R0805")
      (libsource (lib "eagle-import") (part "R-EU_R0805"))
    )
    (comp (ref "R82")
      (value "221")
      (footprint "eagle-import:R0805")
      (libsource (lib "eagle-import") (part "R-EU_R0805"))
    )
    (comp (ref "R83")
      (value "221")
      (footprint "eagle-import:R0805")
      (libsource (lib "eagle-import") (part "R-EU_R0805"))
    )
    (comp (ref "R84")
      (value "221")
      (footprint "eagle-import:R0805")
      (libsource (lib "eagle-import") (part "R-EU_R0805"))
    )
    (comp (ref "R85")
      (value "221")
      (footprint "eagle-import:R0805")
      (libsource (lib "eagle-import") (part "R-EU_R0805"))
    )
    (comp (ref "S")
      (value "SOCKET40P")
      (footprint "eagle-import:40PIN")
      (libsource (lib "eagle-import") (part "SOCKET40P"))
    )
    (comp (ref "U$1")
      (value "LTC6803-4")
      (footprint "eagle-import:SSOP44")
      (libsource (lib "eagle-import") (part "LTC6803-4"))
    )
    (comp (ref "U$2")
      (value "SI8841")
      (footprint "eagle-import:SO16")
      (libsource (lib "eagle-import") (part "SI8841"))
    )
    (comp (ref "U$3")
      (value "SI2351DS")
      (footprint "eagle-import:SOT23")
      (libsource (lib "eagle-import") (part "SI2351DS"))
    )
    (comp (ref "U$4")
      (value "SI2351DS")
      (footprint "eagle-import:SOT23")
      (libsource (lib "eagle-import") (part "SI2351DS"))
    )
    (comp (ref "U$5")
      (value "SI2351DS")
      (footprint "eagle-import:SOT23")
      (libsource (lib "eagle-import") (part "SI2351DS"))
    )
    (comp (ref "U$6")
      (value "SI2351DS")
      (footprint "eagle-import:SOT23")
      (libsource (lib "eagle-import") (part "SI2351DS"))
    )
    (comp (ref "U$7")
      (value "SI2351DS")
      (footprint "eagle-import:SOT23")
      (libsource (lib "eagle-import") (part "SI2351DS"))
    )
    (comp (ref "U$8")
      (value "SI2351DS")
      (footprint "eagle-import:SOT23")
      (libsource (lib "eagle-import") (part "SI2351DS"))
    )
    (comp (ref "U$9")
      (value "SI2351DS")
      (footprint "eagle-import:SOT23")
      (libsource (lib "eagle-import") (part "SI2351DS"))
    )
    (comp (ref "U$10")
      (value "SI2351DS")
      (footprint "eagle-import:SOT23")
      (libsource (lib "eagle-import") (part "SI2351DS"))
    )
    (comp (ref "U$11")
      (value "SI2351DS")
      (footprint "eagle-import:SOT23")
      (libsource (lib "eagle-import") (part "SI2351DS"))
    )
    (comp (ref "U$12")
      (value "SI2351DS")
      (footprint "eagle-import:SOT23")
      (libsource (lib "eagle-import") (part "SI2351DS"))
    )
    (comp (ref "U$13")
      (value "SI2351DS")
      (footprint "eagle-import:SOT23")
      (libsource (lib "eagle-import") (part "SI2351DS"))
    )
    (comp (ref "U$14")
      (value "SI2351DS")
      (footprint "eagle-import:SOT23")
      (libsource (lib "eagle-import") (part "SI2351DS"))
    )
    (comp (ref "U$15")
      (value "INDUCTOR")
      (footprint "eagle-import:L2012C")
      (libsource (lib "eagle-import") (part "INDUCTOR"))
    )
    (comp (ref "C120")
      (value "100nF")
      (footprint "eagle-import:C0805K")
      (libsource (lib "eagle-import") (part "C-EUC0805K"))
    )
    (comp (ref "C121")
      (value "100nF")
      (footprint "eagle-import:C0805K")
      (libsource (lib "eagle-import") (part "C-EUC0805K"))
    )
    (comp (ref "C122")
      (value "100nF")
      (footprint "eagle-import:C0805K")
      (libsource (lib "eagle-import") (part "C-EUC0805K"))
    )
    (comp (ref "C123")
      (value "100nF")
      (footprint "eagle-import:C0805K")
      (libsource (lib "eagle-import") (part "C-EUC0805K"))
    )
    (comp (ref "C124")
      (value "100nF")
      (footprint "eagle-import:C0805K")
      (libsource (lib "eagle-import") (part "C-EUC0805K"))
    )
    (comp (ref "C125")
      (value "100nF")
      (footprint "eagle-import:C0805K")
      (libsource (lib "eagle-import") (part "C-EUC0805K"))
    )
    (comp (ref "C126")
      (value "100nF")
      (footprint "eagle-import:C0805K")
      (libsource (lib "eagle-import") (part "C-EUC0805K"))
    )
    (comp (ref "C127")
      (value "100nF")
      (footprint "eagle-import:C0805K")
      (libsource (lib "eagle-import") (part "C-EUC0805K"))
    )
    (comp (ref "C128")
      (value "100nF")
      (footprint "eagle-import:C0805K")
      (libsource (lib "eagle-import") (part "C-EUC0805K"))
    )
    (comp (ref "C129")
      (value "100nF")
      (footprint "eagle-import:C0805K")
      (libsource (lib "eagle-import") (part "C-EUC0805K"))
    )
    (comp (ref "C130")
      (value "100nF")
      (footprint "eagle-import:C0805K")
      (libsource (lib "eagle-import") (part "C-EUC0805K"))
    )
    (comp (ref "C131")
      (value "100nF")
      (footprint "eagle-import:C0805K")
      (libsource (lib "eagle-import") (part "C-EUC0805K"))
    )
    (comp (ref "C132")
      (value "100nF")
      (footprint "eagle-import:C0805K")
      (libsource (lib "eagle-import") (part "C-EUC0805K"))
    )
    (comp (ref "C133")
      (value "100nF")
      (footprint "eagle-import:C0805K")
      (libsource (lib "eagle-import") (part "C-EUC0805K"))
    )
    (comp (ref "C134")
      (value "100nF")
      (footprint "eagle-import:C0805K")
      (libsource (lib "eagle-import") (part "C-EUC0805K"))
    )
    (comp (ref "C135")
      (value "100nF")
      (footprint "eagle-import:C0805K")
      (libsource (lib "eagle-import") (part "C-EUC0805K"))
    )
    (comp (ref "C136")
      (value "100nF")
      (footprint "eagle-import:C0805K")
      (libsource (lib "eagle-import") (part "C-EUC0805K"))
    )
    (comp (ref "D106")
      (value "7Z5")
      (footprint "eagle-import:SMB")
      (libsource (lib "eagle-import") (part "DIODE-SMB"))
    )
    (comp (ref "D107")
      (value "7Z5")
      (footprint "eagle-import:SMB")
      (libsource (lib "eagle-import") (part "DIODE-SMB"))
    )
    (comp (ref "D108")
      (value "7Z5")
      (footprint "eagle-import:SMB")
      (libsource (lib "eagle-import") (part "DIODE-SMB"))
    )
    (comp (ref "D109")
      (value "7Z5")
      (footprint "eagle-import:SMB")
      (libsource (lib "eagle-import") (part "DIODE-SMB"))
    )
    (comp (ref "D110")
      (value "7Z5")
      (footprint "eagle-import:SMB")
      (libsource (lib "eagle-import") (part "DIODE-SMB"))
    )
    (comp (ref "D111")
      (value "7Z5")
      (footprint "eagle-import:SMB")
      (libsource (lib "eagle-import") (part "DIODE-SMB"))
    )
    (comp (ref "D112")
      (value "7Z5")
      (footprint "eagle-import:SMB")
      (libsource (lib "eagle-import") (part "DIODE-SMB"))
    )
    (comp (ref "D113")
      (value "7Z5")
      (footprint "eagle-import:SMB")
      (libsource (lib "eagle-import") (part "DIODE-SMB"))
    )
    (comp (ref "D114")
      (value "7Z5")
      (footprint "eagle-import:SMB")
      (libsource (lib "eagle-import") (part "DIODE-SMB"))
    )
    (comp (ref "D115")
      (value "7Z5")
      (footprint "eagle-import:SMB")
      (libsource (lib "eagle-import") (part "DIODE-SMB"))
    )
    (comp (ref "D116")
      (value "7Z5")
      (footprint "eagle-import:SMB")
      (libsource (lib "eagle-import") (part "DIODE-SMB"))
    )
    (comp (ref "D117")
      (value "7Z5")
      (footprint "eagle-import:SMB")
      (libsource (lib "eagle-import") (part "DIODE-SMB"))
    )
    (comp (ref "D118")
      (value "7Z5")
      (footprint "eagle-import:SMB")
      (libsource (lib "eagle-import") (part "DIODE-SMB"))
    )
    (comp (ref "D119")
      (value "7Z5")
      (footprint "eagle-import:SMB")
      (libsource (lib "eagle-import") (part "DIODE-SMB"))
    )
    (comp (ref "D120")
      (value "DIODE-SOD123")
      (footprint "eagle-import:SOD123")
      (libsource (lib "eagle-import") (part "DIODE-SOD123"))
    )
    (comp (ref "R582")
      (value "470")
      (footprint "eagle-import:R6332")
      (libsource (lib "eagle-import") (part "R-EU_R6332"))
    )
    (comp (ref "R583")
      (value "221")
      (footprint "eagle-import:R0805")
      (libsource (lib "eagle-import") (part "R-EU_R0805"))
    )
    (comp (ref "R584")
      (value "222")
      (footprint "eagle-import:R0805")
      (libsource (lib "eagle-import") (part "R-EU_R0805"))
    )
    (comp (ref "R585")
      (value "470")
      (footprint "eagle-import:R6332")
      (libsource (lib "eagle-import") (part "R-EU_R6332"))
    )
    (comp (ref "R586")
      (value "0R")
      (footprint "eagle-import:M1206")
      (libsource (lib "eagle-import") (part "R-EU_M1206"))
    )
    (comp (ref "R587")
      (value "0R")
      (footprint "eagle-import:M1206")
      (libsource (lib "eagle-import") (part "R-EU_M1206"))
    )
    (comp (ref "R588")
      (value "470")
      (footprint "eagle-import:R6332")
      (libsource (lib "eagle-import") (part "R-EU_R6332"))
    )
    (comp (ref "R589")
      (value "221")
      (footprint "eagle-import:R0805")
      (libsource (lib "eagle-import") (part "R-EU_R0805"))
    )
    (comp (ref "R590")
      (value "222")
      (footprint "eagle-import:R0805")
      (libsource (lib "eagle-import") (part "R-EU_R0805"))
    )
    (comp (ref "R591")
      (value "470")
      (footprint "eagle-import:R6332")
      (libsource (lib "eagle-import") (part "R-EU_R6332"))
    )
    (comp (ref "R592")
      (value "0R")
      (footprint "eagle-import:M1206")
      (libsource (lib "eagle-import") (part "R-EU_M1206"))
    )
    (comp (ref "R593")
      (value "0R")
      (footprint "eagle-import:M1206")
      (libsource (lib "eagle-import") (part "R-EU_M1206"))
    )
    (comp (ref "R594")
      (value "470")
      (footprint "eagle-import:R6332")
      (libsource (lib "eagle-import") (part "R-EU_R6332"))
    )
    (comp (ref "R595")
      (value "221")
      (footprint "eagle-import:R0805")
      (libsource (lib "eagle-import") (part "R-EU_R0805"))
    )
    (comp (ref "R596")
      (value "222")
      (footprint "eagle-import:R0805")
      (libsource (lib "eagle-import") (part "R-EU_R0805"))
    )
    (comp (ref "R597")
      (value "470")
      (footprint "eagle-import:R6332")
      (libsource (lib "eagle-import") (part "R-EU_R6332"))
    )
    (comp (ref "R598")
      (value "0R")
      (footprint "eagle-import:M1206")
      (libsource (lib "eagle-import") (part "R-EU_M1206"))
    )
    (comp (ref "R599")
      (value "0R")
      (footprint "eagle-import:M1206")
      (libsource (lib "eagle-import") (part "R-EU_M1206"))
    )
    (comp (ref "R600")
      (value "470")
      (footprint "eagle-import:R6332")
      (libsource (lib "eagle-import") (part "R-EU_R6332"))
    )
    (comp (ref "R601")
      (value "221")
      (footprint "eagle-import:R0805")
      (libsource (lib "eagle-import") (part "R-EU_R0805"))
    )
    (comp (ref "R602")
      (value "222")
      (footprint "eagle-import:R0805")
      (libsource (lib "eagle-import") (part "R-EU_R0805"))
    )
    (comp (ref "R603")
      (value "470")
      (footprint "eagle-import:R6332")
      (libsource (lib "eagle-import") (part "R-EU_R6332"))
    )
    (comp (ref "R604")
      (value "0R")
      (footprint "eagle-import:M1206")
      (libsource (lib "eagle-import") (part "R-EU_M1206"))
    )
    (comp (ref "R605")
      (value "0R")
      (footprint "eagle-import:M1206")
      (libsource (lib "eagle-import") (part "R-EU_M1206"))
    )
    (comp (ref "R606")
      (value "470")
      (footprint "eagle-import:R6332")
      (libsource (lib "eagle-import") (part "R-EU_R6332"))
    )
    (comp (ref "R607")
      (value "221")
      (footprint "eagle-import:R0805")
      (libsource (lib "eagle-import") (part "R-EU_R0805"))
    )
    (comp (ref "R608")
      (value "222")
      (footprint "eagle-import:R0805")
      (libsource (lib "eagle-import") (part "R-EU_R0805"))
    )
    (comp (ref "R609")
      (value "470")
      (footprint "eagle-import:R6332")
      (libsource (lib "eagle-import") (part "R-EU_R6332"))
    )
    (comp (ref "R610")
      (value "0R")
      (footprint "eagle-import:M1206")
      (libsource (lib "eagle-import") (part "R-EU_M1206"))
    )
    (comp (ref "R611")
      (value "0R")
      (footprint "eagle-import:M1206")
      (libsource (lib "eagle-import") (part "R-EU_M1206"))
    )
    (comp (ref "R612")
      (value "470")
      (footprint "eagle-import:R6332")
      (libsource (lib "eagle-import") (part "R-EU_R6332"))
    )
    (comp (ref "R613")
      (value "221")
      (footprint "eagle-import:R0805")
      (libsource (lib "eagle-import") (part "R-EU_R0805"))
    )
    (comp (ref "R614")
      (value "222")
      (footprint "eagle-import:R0805")
      (libsource (lib "eagle-import") (part "R-EU_R0805"))
    )
    (comp (ref "R615")
      (value "470")
      (footprint "eagle-import:R6332")
      (libsource (lib "eagle-import") (part "R-EU_R6332"))
    )
    (comp (ref "R616")
      (value "0R")
      (footprint "eagle-import:M1206")
      (libsource (lib "eagle-import") (part "R-EU_M1206"))
    )
    (comp (ref "R617")
      (value "0R")
      (footprint "eagle-import:M1206")
      (libsource (lib "eagle-import") (part "R-EU_M1206"))
    )
    (comp (ref "R618")
      (value "470")
      (footprint "eagle-import:R6332")
      (libsource (lib "eagle-import") (part "R-EU_R6332"))
    )
    (comp (ref "R619")
      (value "221")
      (footprint "eagle-import:R0805")
      (libsource (lib "eagle-import") (part "R-EU_R0805"))
    )
    (comp (ref "R620")
      (value "222")
      (footprint "eagle-import:R0805")
      (libsource (lib "eagle-import") (part "R-EU_R0805"))
    )
    (comp (ref "R621")
      (value "470")
      (footprint "eagle-import:R6332")
      (libsource (lib "eagle-import") (part "R-EU_R6332"))
    )
    (comp (ref "R622")
      (value "0R")
      (footprint "eagle-import:M1206")
      (libsource (lib "eagle-import") (part "R-EU_M1206"))
    )
    (comp (ref "R623")
      (value "0R")
      (footprint "eagle-import:M1206")
      (libsource (lib "eagle-import") (part "R-EU_M1206"))
    )
    (comp (ref "R624")
      (value "470")
      (footprint "eagle-import:R6332")
      (libsource (lib "eagle-import") (part "R-EU_R6332"))
    )
    (comp (ref "R625")
      (value "221")
      (footprint "eagle-import:R0805")
      (libsource (lib "eagle-import") (part "R-EU_R0805"))
    )
    (comp (ref "R626")
      (value "222")
      (footprint "eagle-import:R0805")
      (libsource (lib "eagle-import") (part "R-EU_R0805"))
    )
    (comp (ref "R627")
      (value "470")
      (footprint "eagle-import:R6332")
      (libsource (lib "eagle-import") (part "R-EU_R6332"))
    )
    (comp (ref "R628")
      (value "0R")
      (footprint "eagle-import:M1206")
      (libsource (lib "eagle-import") (part "R-EU_M1206"))
    )
    (comp (ref "R629")
      (value "0R")
      (footprint "eagle-import:M1206")
      (libsource (lib "eagle-import") (part "R-EU_M1206"))
    )
    (comp (ref "R630")
      (value "470")
      (footprint "eagle-import:R6332")
      (libsource (lib "eagle-import") (part "R-EU_R6332"))
    )
    (comp (ref "R631")
      (value "221")
      (footprint "eagle-import:R0805")
      (libsource (lib "eagle-import") (part "R-EU_R0805"))
    )
    (comp (ref "R632")
      (value "222")
      (footprint "eagle-import:R0805")
      (libsource (lib "eagle-import") (part "R-EU_R0805"))
    )
    (comp (ref "R633")
      (value "470")
      (footprint "eagle-import:R6332")
      (libsource (lib "eagle-import") (part "R-EU_R6332"))
    )
    (comp (ref "R634")
      (value "0R")
      (footprint "eagle-import:M1206")
      (libsource (lib "eagle-import") (part "R-EU_M1206"))
    )
    (comp (ref "R635")
      (value "0R")
      (footprint "eagle-import:M1206")
      (libsource (lib "eagle-import") (part "R-EU_M1206"))
    )
    (comp (ref "R636")
      (value "470")
      (footprint "eagle-import:R6332")
      (libsource (lib "eagle-import") (part "R-EU_R6332"))
    )
    (comp (ref "R637")
      (value "221")
      (footprint "eagle-import:R0805")
      (libsource (lib "eagle-import") (part "R-EU_R0805"))
    )
    (comp (ref "R638")
      (value "222")
      (footprint "eagle-import:R0805")
      (libsource (lib "eagle-import") (part "R-EU_R0805"))
    )
    (comp (ref "R639")
      (value "470")
      (footprint "eagle-import:R6332")
      (libsource (lib "eagle-import") (part "R-EU_R6332"))
    )
    (comp (ref "R640")
      (value "0R")
      (footprint "eagle-import:M1206")
      (libsource (lib "eagle-import") (part "R-EU_M1206"))
    )
    (comp (ref "R641")
      (value "0R")
      (footprint "eagle-import:M1206")
      (libsource (lib "eagle-import") (part "R-EU_M1206"))
    )
    (comp (ref "R642")
      (value "470")
      (footprint "eagle-import:R6332")
      (libsource (lib "eagle-import") (part "R-EU_R6332"))
    )
    (comp (ref "R643")
      (value "221")
      (footprint "eagle-import:R0805")
      (libsource (lib "eagle-import") (part "R-EU_R0805"))
    )
    (comp (ref "R644")
      (value "222")
      (footprint "eagle-import:R0805")
      (libsource (lib "eagle-import") (part "R-EU_R0805"))
    )
    (comp (ref "R645")
      (value "470")
      (footprint "eagle-import:R6332")
      (libsource (lib "eagle-import") (part "R-EU_R6332"))
    )
    (comp (ref "R646")
      (value "0R")
      (footprint "eagle-import:M1206")
      (libsource (lib "eagle-import") (part "R-EU_M1206"))
    )
    (comp (ref "R647")
      (value "0R")
      (footprint "eagle-import:M1206")
      (libsource (lib "eagle-import") (part "R-EU_M1206"))
    )
    (comp (ref "R648")
      (value "470")
      (footprint "eagle-import:R6332")
      (libsource (lib "eagle-import") (part "R-EU_R6332"))
    )
    (comp (ref "R649")
      (value "221")
      (footprint "eagle-import:R0805")
      (libsource (lib "eagle-import") (part "R-EU_R0805"))
    )
    (comp (ref "R650")
      (value "222")
      (footprint "eagle-import:R0805")
      (libsource (lib "eagle-import") (part "R-EU_R0805"))
    )
    (comp (ref "R651")
      (value "470")
      (footprint "eagle-import:R6332")
      (libsource (lib "eagle-import") (part "R-EU_R6332"))
    )
    (comp (ref "R652")
      (value "0R")
      (footprint "eagle-import:M1206")
      (libsource (lib "eagle-import") (part "R-EU_M1206"))
    )
    (comp (ref "R653")
      (value "0R")
      (footprint "eagle-import:M1206")
      (libsource (lib "eagle-import") (part "R-EU_M1206"))
    )
    (comp (ref "R654")
      (value "0R")
      (footprint "eagle-import:M1206")
      (libsource (lib "eagle-import") (part "R-EU_M1206"))
    )
    (comp (ref "R655")
      (value "0R")
      (footprint "eagle-import:M1206")
      (libsource (lib "eagle-import") (part "R-EU_M1206"))
    )
    (comp (ref "R656")
      (value "0R")
      (footprint "eagle-import:M1206")
      (libsource (lib "eagle-import") (part "R-EU_M1206"))
    )
    (comp (ref "R657")
      (value "0R")
      (footprint "eagle-import:M1206")
      (libsource (lib "eagle-import") (part "R-EU_M1206"))
    )
    (comp (ref "R658")
      (value "0R")
      (footprint "eagle-import:M1206")
      (libsource (lib "eagle-import") (part "R-EU_M1206"))
    )
    (comp (ref "R659")
      (value "221")
      (footprint "eagle-import:R0805")
      (libsource (lib "eagle-import") (part "R-EU_R0805"))
    )
    (comp (ref "R660")
      (value "221")
      (footprint "eagle-import:R0805")
      (libsource (lib "eagle-import") (part "R-EU_R0805"))
    )
    (comp (ref "R661")
      (value "221")
      (footprint "eagle-import:R0805")
      (libsource (lib "eagle-import") (part "R-EU_R0805"))
    )
    (comp (ref "R662")
      (value "221")
      (footprint "eagle-import:R0805")
      (libsource (lib "eagle-import") (part "R-EU_R0805"))
    )
    (comp (ref "R663")
      (value "221")
      (footprint "eagle-import:R0805")
      (libsource (lib "eagle-import") (part "R-EU_R0805"))
    )
    (comp (ref "R664")
      (value "0R")
      (footprint "eagle-import:M1206")
      (libsource (lib "eagle-import") (part "R-EU_M1206"))
    )
    (comp (ref "U$106")
      (value "LTC6803-4")
      (footprint "eagle-import:SSOP44")
      (libsource (lib "eagle-import") (part "LTC6803-4"))
    )
    (comp (ref "U$107")
      (value "SI8841")
      (footprint "eagle-import:SO16")
      (libsource (lib "eagle-import") (part "SI8841"))
    )
    (comp (ref "U$108")
      (value "SI2351DS")
      (footprint "eagle-import:SOT23")
      (libsource (lib "eagle-import") (part "SI2351DS"))
    )
    (comp (ref "U$109")
      (value "SI2351DS")
      (footprint "eagle-import:SOT23")
      (libsource (lib "eagle-import") (part "SI2351DS"))
    )
    (comp (ref "U$110")
      (value "SI2351DS")
      (footprint "eagle-import:SOT23")
      (libsource (lib "eagle-import") (part "SI2351DS"))
    )
    (comp (ref "U$111")
      (value "SI2351DS")
      (footprint "eagle-import:SOT23")
      (libsource (lib "eagle-import") (part "SI2351DS"))
    )
    (comp (ref "U$112")
      (value "SI2351DS")
      (footprint "eagle-import:SOT23")
      (libsource (lib "eagle-import") (part "SI2351DS"))
    )
    (comp (ref "U$113")
      (value "SI2351DS")
      (footprint "eagle-import:SOT23")
      (libsource (lib "eagle-import") (part "SI2351DS"))
    )
    (comp (ref "U$114")
      (value "SI2351DS")
      (footprint "eagle-import:SOT23")
      (libsource (lib "eagle-import") (part "SI2351DS"))
    )
    (comp (ref "U$115")
      (value "SI2351DS")
      (footprint "eagle-import:SOT23")
      (libsource (lib "eagle-import") (part "SI2351DS"))
    )
    (comp (ref "U$116")
      (value "SI2351DS")
      (footprint "eagle-import:SOT23")
      (libsource (lib "eagle-import") (part "SI2351DS"))
    )
    (comp (ref "U$117")
      (value "SI2351DS")
      (footprint "eagle-import:SOT23")
      (libsource (lib "eagle-import") (part "SI2351DS"))
    )
    (comp (ref "U$118")
      (value "SI2351DS")
      (footprint "eagle-import:SOT23")
      (libsource (lib "eagle-import") (part "SI2351DS"))
    )
    (comp (ref "U$119")
      (value "SI2351DS")
      (footprint "eagle-import:SOT23")
      (libsource (lib "eagle-import") (part "SI2351DS"))
    )
    (comp (ref "U$120")
      (value "INDUCTOR")
      (footprint "eagle-import:L2012C")
      (libsource (lib "eagle-import") (part "INDUCTOR"))
    )
    (comp (ref "C137")
      (value "100nF")
      (footprint "eagle-import:C0805K")
      (libsource (lib "eagle-import") (part "C-EUC0805K"))
    )
    (comp (ref "C138")
      (value "100nF")
      (footprint "eagle-import:C0805K")
      (libsource (lib "eagle-import") (part "C-EUC0805K"))
    )
    (comp (ref "C139")
      (value "100nF")
      (footprint "eagle-import:C0805K")
      (libsource (lib "eagle-import") (part "C-EUC0805K"))
    )
    (comp (ref "C140")
      (value "100nF")
      (footprint "eagle-import:C0805K")
      (libsource (lib "eagle-import") (part "C-EUC0805K"))
    )
    (comp (ref "C141")
      (value "100nF")
      (footprint "eagle-import:C0805K")
      (libsource (lib "eagle-import") (part "C-EUC0805K"))
    )
    (comp (ref "C142")
      (value "100nF")
      (footprint "eagle-import:C0805K")
      (libsource (lib "eagle-import") (part "C-EUC0805K"))
    )
    (comp (ref "C143")
      (value "100nF")
      (footprint "eagle-import:C0805K")
      (libsource (lib "eagle-import") (part "C-EUC0805K"))
    )
    (comp (ref "C144")
      (value "100nF")
      (footprint "eagle-import:C0805K")
      (libsource (lib "eagle-import") (part "C-EUC0805K"))
    )
    (comp (ref "C145")
      (value "100nF")
      (footprint "eagle-import:C0805K")
      (libsource (lib "eagle-import") (part "C-EUC0805K"))
    )
    (comp (ref "C146")
      (value "100nF")
      (footprint "eagle-import:C0805K")
      (libsource (lib "eagle-import") (part "C-EUC0805K"))
    )
    (comp (ref "C147")
      (value "100nF")
      (footprint "eagle-import:C0805K")
      (libsource (lib "eagle-import") (part "C-EUC0805K"))
    )
    (comp (ref "C148")
      (value "100nF")
      (footprint "eagle-import:C0805K")
      (libsource (lib "eagle-import") (part "C-EUC0805K"))
    )
    (comp (ref "C149")
      (value "100nF")
      (footprint "eagle-import:C0805K")
      (libsource (lib "eagle-import") (part "C-EUC0805K"))
    )
    (comp (ref "C150")
      (value "100nF")
      (footprint "eagle-import:C0805K")
      (libsource (lib "eagle-import") (part "C-EUC0805K"))
    )
    (comp (ref "C151")
      (value "100nF")
      (footprint "eagle-import:C0805K")
      (libsource (lib "eagle-import") (part "C-EUC0805K"))
    )
    (comp (ref "C152")
      (value "100nF")
      (footprint "eagle-import:C0805K")
      (libsource (lib "eagle-import") (part "C-EUC0805K"))
    )
    (comp (ref "C153")
      (value "100nF")
      (footprint "eagle-import:C0805K")
      (libsource (lib "eagle-import") (part "C-EUC0805K"))
    )
    (comp (ref "D121")
      (value "7Z5")
      (footprint "eagle-import:SMB")
      (libsource (lib "eagle-import") (part "DIODE-SMB"))
    )
    (comp (ref "D122")
      (value "7Z5")
      (footprint "eagle-import:SMB")
      (libsource (lib "eagle-import") (part "DIODE-SMB"))
    )
    (comp (ref "D123")
      (value "7Z5")
      (footprint "eagle-import:SMB")
      (libsource (lib "eagle-import") (part "DIODE-SMB"))
    )
    (comp (ref "D124")
      (value "7Z5")
      (footprint "eagle-import:SMB")
      (libsource (lib "eagle-import") (part "DIODE-SMB"))
    )
    (comp (ref "D125")
      (value "7Z5")
      (footprint "eagle-import:SMB")
      (libsource (lib "eagle-import") (part "DIODE-SMB"))
    )
    (comp (ref "D126")
      (value "7Z5")
      (footprint "eagle-import:SMB")
      (libsource (lib "eagle-import") (part "DIODE-SMB"))
    )
    (comp (ref "D127")
      (value "7Z5")
      (footprint "eagle-import:SMB")
      (libsource (lib "eagle-import") (part "DIODE-SMB"))
    )
    (comp (ref "D128")
      (value "7Z5")
      (footprint "eagle-import:SMB")
      (libsource (lib "eagle-import") (part "DIODE-SMB"))
    )
    (comp (ref "D129")
      (value "7Z5")
      (footprint "eagle-import:SMB")
      (libsource (lib "eagle-import") (part "DIODE-SMB"))
    )
    (comp (ref "D130")
      (value "7Z5")
      (footprint "eagle-import:SMB")
      (libsource (lib "eagle-import") (part "DIODE-SMB"))
    )
    (comp (ref "D131")
      (value "7Z5")
      (footprint "eagle-import:SMB")
      (libsource (lib "eagle-import") (part "DIODE-SMB"))
    )
    (comp (ref "D132")
      (value "7Z5")
      (footprint "eagle-import:SMB")
      (libsource (lib "eagle-import") (part "DIODE-SMB"))
    )
    (comp (ref "D133")
      (value "7Z5")
      (footprint "eagle-import:SMB")
      (libsource (lib "eagle-import") (part "DIODE-SMB"))
    )
    (comp (ref "D134")
      (value "7Z5")
      (footprint "eagle-import:SMB")
      (libsource (lib "eagle-import") (part "DIODE-SMB"))
    )
    (comp (ref "D135")
      (value "DIODE-SOD123")
      (footprint "eagle-import:SOD123")
      (libsource (lib "eagle-import") (part "DIODE-SOD123"))
    )
    (comp (ref "R665")
      (value "470")
      (footprint "eagle-import:R6332")
      (libsource (lib "eagle-import") (part "R-EU_R6332"))
    )
    (comp (ref "R666")
      (value "221")
      (footprint "eagle-import:R0805")
      (libsource (lib "eagle-import") (part "R-EU_R0805"))
    )
    (comp (ref "R667")
      (value "222")
      (footprint "eagle-import:R0805")
      (libsource (lib "eagle-import") (part "R-EU_R0805"))
    )
    (comp (ref "R668")
      (value "470")
      (footprint "eagle-import:R6332")
      (libsource (lib "eagle-import") (part "R-EU_R6332"))
    )
    (comp (ref "R669")
      (value "0R")
      (footprint "eagle-import:M1206")
      (libsource (lib "eagle-import") (part "R-EU_M1206"))
    )
    (comp (ref "R670")
      (value "0R")
      (footprint "eagle-import:M1206")
      (libsource (lib "eagle-import") (part "R-EU_M1206"))
    )
    (comp (ref "R671")
      (value "470")
      (footprint "eagle-import:R6332")
      (libsource (lib "eagle-import") (part "R-EU_R6332"))
    )
    (comp (ref "R672")
      (value "221")
      (footprint "eagle-import:R0805")
      (libsource (lib "eagle-import") (part "R-EU_R0805"))
    )
    (comp (ref "R673")
      (value "222")
      (footprint "eagle-import:R0805")
      (libsource (lib "eagle-import") (part "R-EU_R0805"))
    )
    (comp (ref "R674")
      (value "470")
      (footprint "eagle-import:R6332")
      (libsource (lib "eagle-import") (part "R-EU_R6332"))
    )
    (comp (ref "R675")
      (value "0R")
      (footprint "eagle-import:M1206")
      (libsource (lib "eagle-import") (part "R-EU_M1206"))
    )
    (comp (ref "R676")
      (value "0R")
      (footprint "eagle-import:M1206")
      (libsource (lib "eagle-import") (part "R-EU_M1206"))
    )
    (comp (ref "R677")
      (value "470")
      (footprint "eagle-import:R6332")
      (libsource (lib "eagle-import") (part "R-EU_R6332"))
    )
    (comp (ref "R678")
      (value "221")
      (footprint "eagle-import:R0805")
      (libsource (lib "eagle-import") (part "R-EU_R0805"))
    )
    (comp (ref "R679")
      (value "222")
      (footprint "eagle-import:R0805")
      (libsource (lib "eagle-import") (part "R-EU_R0805"))
    )
    (comp (ref "R680")
      (value "470")
      (footprint "eagle-import:R6332")
      (libsource (lib "eagle-import") (part "R-EU_R6332"))
    )
    (comp (ref "R681")
      (value "0R")
      (footprint "eagle-import:M1206")
      (libsource (lib "eagle-import") (part "R-EU_M1206"))
    )
    (comp (ref "R682")
      (value "0R")
      (footprint "eagle-import:M1206")
      (libsource (lib "eagle-import") (part "R-EU_M1206"))
    )
    (comp (ref "R683")
      (value "470")
      (footprint "eagle-import:R6332")
      (libsource (lib "eagle-import") (part "R-EU_R6332"))
    )
    (comp (ref "R684")
      (value "221")
      (footprint "eagle-import:R0805")
      (libsource (lib "eagle-import") (part "R-EU_R0805"))
    )
    (comp (ref "R685")
      (value "222")
      (footprint "eagle-import:R0805")
      (libsource (lib "eagle-import") (part "R-EU_R0805"))
    )
    (comp (ref "R686")
      (value "470")
      (footprint "eagle-import:R6332")
      (libsource (lib "eagle-import") (part "R-EU_R6332"))
    )
    (comp (ref "R687")
      (value "0R")
      (footprint "eagle-import:M1206")
      (libsource (lib "eagle-import") (part "R-EU_M1206"))
    )
    (comp (ref "R688")
      (value "0R")
      (footprint "eagle-import:M1206")
      (libsource (lib "eagle-import") (part "R-EU_M1206"))
    )
    (comp (ref "R689")
      (value "470")
      (footprint "eagle-import:R6332")
      (libsource (lib "eagle-import") (part "R-EU_R6332"))
    )
    (comp (ref "R690")
      (value "221")
      (footprint "eagle-import:R0805")
      (libsource (lib "eagle-import") (part "R-EU_R0805"))
    )
    (comp (ref "R691")
      (value "222")
      (footprint "eagle-import:R0805")
      (libsource (lib "eagle-import") (part "R-EU_R0805"))
    )
    (comp (ref "R692")
      (value "470")
      (footprint "eagle-import:R6332")
      (libsource (lib "eagle-import") (part "R-EU_R6332"))
    )
    (comp (ref "R693")
      (value "0R")
      (footprint "eagle-import:M1206")
      (libsource (lib "eagle-import") (part "R-EU_M1206"))
    )
    (comp (ref "R694")
      (value "0R")
      (footprint "eagle-import:M1206")
      (libsource (lib "eagle-import") (part "R-EU_M1206"))
    )
    (comp (ref "R695")
      (value "470")
      (footprint "eagle-import:R6332")
      (libsource (lib "eagle-import") (part "R-EU_R6332"))
    )
    (comp (ref "R696")
      (value "221")
      (footprint "eagle-import:R0805")
      (libsource (lib "eagle-import") (part "R-EU_R0805"))
    )
    (comp (ref "R697")
      (value "222")
      (footprint "eagle-import:R0805")
      (libsource (lib "eagle-import") (part "R-EU_R0805"))
    )
    (comp (ref "R698")
      (value "470")
      (footprint "eagle-import:R6332")
      (libsource (lib "eagle-import") (part "R-EU_R6332"))
    )
    (comp (ref "R699")
      (value "0R")
      (footprint "eagle-import:M1206")
      (libsource (lib "eagle-import") (part "R-EU_M1206"))
    )
    (comp (ref "R700")
      (value "0R")
      (footprint "eagle-import:M1206")
      (libsource (lib "eagle-import") (part "R-EU_M1206"))
    )
    (comp (ref "R701")
      (value "470")
      (footprint "eagle-import:R6332")
      (libsource (lib "eagle-import") (part "R-EU_R6332"))
    )
    (comp (ref "R702")
      (value "221")
      (footprint "eagle-import:R0805")
      (libsource (lib "eagle-import") (part "R-EU_R0805"))
    )
    (comp (ref "R703")
      (value "222")
      (footprint "eagle-import:R0805")
      (libsource (lib "eagle-import") (part "R-EU_R0805"))
    )
    (comp (ref "R704")
      (value "470")
      (footprint "eagle-import:R6332")
      (libsource (lib "eagle-import") (part "R-EU_R6332"))
    )
    (comp (ref "R705")
      (value "0R")
      (footprint "eagle-import:M1206")
      (libsource (lib "eagle-import") (part "R-EU_M1206"))
    )
    (comp (ref "R706")
      (value "0R")
      (footprint "eagle-import:M1206")
      (libsource (lib "eagle-import") (part "R-EU_M1206"))
    )
    (comp (ref "R707")
      (value "470")
      (footprint "eagle-import:R6332")
      (libsource (lib "eagle-import") (part "R-EU_R6332"))
    )
    (comp (ref "R708")
      (value "221")
      (footprint "eagle-import:R0805")
      (libsource (lib "eagle-import") (part "R-EU_R0805"))
    )
    (comp (ref "R709")
      (value "222")
      (footprint "eagle-import:R0805")
      (libsource (lib "eagle-import") (part "R-EU_R0805"))
    )
    (comp (ref "R710")
      (value "470")
      (footprint "eagle-import:R6332")
      (libsource (lib "eagle-import") (part "R-EU_R6332"))
    )
    (comp (ref "R711")
      (value "0R")
      (footprint "eagle-import:M1206")
      (libsource (lib "eagle-import") (part "R-EU_M1206"))
    )
    (comp (ref "R712")
      (value "0R")
      (footprint "eagle-import:M1206")
      (libsource (lib "eagle-import") (part "R-EU_M1206"))
    )
    (comp (ref "R713")
      (value "470")
      (footprint "eagle-import:R6332")
      (libsource (lib "eagle-import") (part "R-EU_R6332"))
    )
    (comp (ref "R714")
      (value "221")
      (footprint "eagle-import:R0805")
      (libsource (lib "eagle-import") (part "R-EU_R0805"))
    )
    (comp (ref "R715")
      (value "222")
      (footprint "eagle-import:R0805")
      (libsource (lib "eagle-import") (part "R-EU_R0805"))
    )
    (comp (ref "R716")
      (value "470")
      (footprint "eagle-import:R6332")
      (libsource (lib "eagle-import") (part "R-EU_R6332"))
    )
    (comp (ref "R717")
      (value "0R")
      (footprint "eagle-import:M1206")
      (libsource (lib "eagle-import") (part "R-EU_M1206"))
    )
    (comp (ref "R718")
      (value "0R")
      (footprint "eagle-import:M1206")
      (libsource (lib "eagle-import") (part "R-EU_M1206"))
    )
    (comp (ref "R719")
      (value "470")
      (footprint "eagle-import:R6332")
      (libsource (lib "eagle-import") (part "R-EU_R6332"))
    )
    (comp (ref "R720")
      (value "221")
      (footprint "eagle-import:R0805")
      (libsource (lib "eagle-import") (part "R-EU_R0805"))
    )
    (comp (ref "R721")
      (value "222")
      (footprint "eagle-import:R0805")
      (libsource (lib "eagle-import") (part "R-EU_R0805"))
    )
    (comp (ref "R722")
      (value "470")
      (footprint "eagle-import:R6332")
      (libsource (lib "eagle-import") (part "R-EU_R6332"))
    )
    (comp (ref "R723")
      (value "0R")
      (footprint "eagle-import:M1206")
      (libsource (lib "eagle-import") (part "R-EU_M1206"))
    )
    (comp (ref "R724")
      (value "0R")
      (footprint "eagle-import:M1206")
      (libsource (lib "eagle-import") (part "R-EU_M1206"))
    )
    (comp (ref "R725")
      (value "470")
      (footprint "eagle-import:R6332")
      (libsource (lib "eagle-import") (part "R-EU_R6332"))
    )
    (comp (ref "R726")
      (value "221")
      (footprint "eagle-import:R0805")
      (libsource (lib "eagle-import") (part "R-EU_R0805"))
    )
    (comp (ref "R727")
      (value "222")
      (footprint "eagle-import:R0805")
      (libsource (lib "eagle-import") (part "R-EU_R0805"))
    )
    (comp (ref "R728")
      (value "470")
      (footprint "eagle-import:R6332")
      (libsource (lib "eagle-import") (part "R-EU_R6332"))
    )
    (comp (ref "R729")
      (value "0R")
      (footprint "eagle-import:M1206")
      (libsource (lib "eagle-import") (part "R-EU_M1206"))
    )
    (comp (ref "R730")
      (value "0R")
      (footprint "eagle-import:M1206")
      (libsource (lib "eagle-import") (part "R-EU_M1206"))
    )
    (comp (ref "R731")
      (value "470")
      (footprint "eagle-import:R6332")
      (libsource (lib "eagle-import") (part "R-EU_R6332"))
    )
    (comp (ref "R732")
      (value "221")
      (footprint "eagle-import:R0805")
      (libsource (lib "eagle-import") (part "R-EU_R0805"))
    )
    (comp (ref "R733")
      (value "222")
      (footprint "eagle-import:R0805")
      (libsource (lib "eagle-import") (part "R-EU_R0805"))
    )
    (comp (ref "R734")
      (value "470")
      (footprint "eagle-import:R6332")
      (libsource (lib "eagle-import") (part "R-EU_R6332"))
    )
    (comp (ref "R735")
      (value "0R")
      (footprint "eagle-import:M1206")
      (libsource (lib "eagle-import") (part "R-EU_M1206"))
    )
    (comp (ref "R736")
      (value "0R")
      (footprint "eagle-import:M1206")
      (libsource (lib "eagle-import") (part "R-EU_M1206"))
    )
    (comp (ref "R737")
      (value "0R")
      (footprint "eagle-import:M1206")
      (libsource (lib "eagle-import") (part "R-EU_M1206"))
    )
    (comp (ref "R738")
      (value "0R")
      (footprint "eagle-import:M1206")
      (libsource (lib "eagle-import") (part "R-EU_M1206"))
    )
    (comp (ref "R739")
      (value "0R")
      (footprint "eagle-import:M1206")
      (libsource (lib "eagle-import") (part "R-EU_M1206"))
    )
    (comp (ref "R740")
      (value "0R")
      (footprint "eagle-import:M1206")
      (libsource (lib "eagle-import") (part "R-EU_M1206"))
    )
    (comp (ref "R741")
      (value "0R")
      (footprint "eagle-import:M1206")
      (libsource (lib "eagle-import") (part "R-EU_M1206"))
    )
    (comp (ref "R742")
      (value "221")
      (footprint "eagle-import:R0805")
      (libsource (lib "eagle-import") (part "R-EU_R0805"))
    )
    (comp (ref "R743")
      (value "221")
      (footprint "eagle-import:R0805")
      (libsource (lib "eagle-import") (part "R-EU_R0805"))
    )
    (comp (ref "R744")
      (value "221")
      (footprint "eagle-import:R0805")
      (libsource (lib "eagle-import") (part "R-EU_R0805"))
    )
    (comp (ref "R745")
      (value "221")
      (footprint "eagle-import:R0805")
      (libsource (lib "eagle-import") (part "R-EU_R0805"))
    )
    (comp (ref "R746")
      (value "221")
      (footprint "eagle-import:R0805")
      (libsource (lib "eagle-import") (part "R-EU_R0805"))
    )
    (comp (ref "R747")
      (value "0R")
      (footprint "eagle-import:M1206")
      (libsource (lib "eagle-import") (part "R-EU_M1206"))
    )
    (comp (ref "U$121")
      (value "LTC6803-4")
      (footprint "eagle-import:SSOP44")
      (libsource (lib "eagle-import") (part "LTC6803-4"))
    )
    (comp (ref "U$122")
      (value "SI8841")
      (footprint "eagle-import:SO16")
      (libsource (lib "eagle-import") (part "SI8841"))
    )
    (comp (ref "U$123")
      (value "SI2351DS")
      (footprint "eagle-import:SOT23")
      (libsource (lib "eagle-import") (part "SI2351DS"))
    )
    (comp (ref "U$124")
      (value "SI2351DS")
      (footprint "eagle-import:SOT23")
      (libsource (lib "eagle-import") (part "SI2351DS"))
    )
    (comp (ref "U$125")
      (value "SI2351DS")
      (footprint "eagle-import:SOT23")
      (libsource (lib "eagle-import") (part "SI2351DS"))
    )
    (comp (ref "U$126")
      (value "SI2351DS")
      (footprint "eagle-import:SOT23")
      (libsource (lib "eagle-import") (part "SI2351DS"))
    )
    (comp (ref "U$127")
      (value "SI2351DS")
      (footprint "eagle-import:SOT23")
      (libsource (lib "eagle-import") (part "SI2351DS"))
    )
    (comp (ref "U$128")
      (value "SI2351DS")
      (footprint "eagle-import:SOT23")
      (libsource (lib "eagle-import") (part "SI2351DS"))
    )
    (comp (ref "U$129")
      (value "SI2351DS")
      (footprint "eagle-import:SOT23")
      (libsource (lib "eagle-import") (part "SI2351DS"))
    )
    (comp (ref "U$130")
      (value "SI2351DS")
      (footprint "eagle-import:SOT23")
      (libsource (lib "eagle-import") (part "SI2351DS"))
    )
    (comp (ref "U$131")
      (value "SI2351DS")
      (footprint "eagle-import:SOT23")
      (libsource (lib "eagle-import") (part "SI2351DS"))
    )
    (comp (ref "U$132")
      (value "SI2351DS")
      (footprint "eagle-import:SOT23")
      (libsource (lib "eagle-import") (part "SI2351DS"))
    )
    (comp (ref "U$133")
      (value "SI2351DS")
      (footprint "eagle-import:SOT23")
      (libsource (lib "eagle-import") (part "SI2351DS"))
    )
    (comp (ref "U$134")
      (value "SI2351DS")
      (footprint "eagle-import:SOT23")
      (libsource (lib "eagle-import") (part "SI2351DS"))
    )
    (comp (ref "U$135")
      (value "INDUCTOR")
      (footprint "eagle-import:L2012C")
      (libsource (lib "eagle-import") (part "INDUCTOR"))
    )
    (comp (ref "C19")
      (value "100nF")
      (footprint "eagle-import:C0805K")
      (libsource (lib "eagle-import") (part "C-EUC0805K"))
    )
    (comp (ref "C20")
      (value "100nF")
      (footprint "eagle-import:C0805K")
      (libsource (lib "eagle-import") (part "C-EUC0805K"))
    )
    (comp (ref "C21")
      (value "100nF")
      (footprint "eagle-import:C0805K")
      (libsource (lib "eagle-import") (part "C-EUC0805K"))
    )
    (comp (ref "C22")
      (value "100nF")
      (footprint "eagle-import:C0805K")
      (libsource (lib "eagle-import") (part "C-EUC0805K"))
    )
    (comp (ref "C23")
      (value "100nF")
      (footprint "eagle-import:C0805K")
      (libsource (lib "eagle-import") (part "C-EUC0805K"))
    )
    (comp (ref "C24")
      (value "100nF")
      (footprint "eagle-import:C0805K")
      (libsource (lib "eagle-import") (part "C-EUC0805K"))
    )
    (comp (ref "C25")
      (value "100nF")
      (footprint "eagle-import:C0805K")
      (libsource (lib "eagle-import") (part "C-EUC0805K"))
    )
    (comp (ref "C26")
      (value "100nF")
      (footprint "eagle-import:C0805K")
      (libsource (lib "eagle-import") (part "C-EUC0805K"))
    )
    (comp (ref "C27")
      (value "100nF")
      (footprint "eagle-import:C0805K")
      (libsource (lib "eagle-import") (part "C-EUC0805K"))
    )
    (comp (ref "C28")
      (value "100nF")
      (footprint "eagle-import:C0805K")
      (libsource (lib "eagle-import") (part "C-EUC0805K"))
    )
    (comp (ref "C29")
      (value "100nF")
      (footprint "eagle-import:C0805K")
      (libsource (lib "eagle-import") (part "C-EUC0805K"))
    )
    (comp (ref "C30")
      (value "100nF")
      (footprint "eagle-import:C0805K")
      (libsource (lib "eagle-import") (part "C-EUC0805K"))
    )
    (comp (ref "C31")
      (value "100nF")
      (footprint "eagle-import:C0805K")
      (libsource (lib "eagle-import") (part "C-EUC0805K"))
    )
    (comp (ref "C32")
      (value "100nF")
      (footprint "eagle-import:C0805K")
      (libsource (lib "eagle-import") (part "C-EUC0805K"))
    )
    (comp (ref "C33")
      (value "100nF")
      (footprint "eagle-import:C0805K")
      (libsource (lib "eagle-import") (part "C-EUC0805K"))
    )
    (comp (ref "C34")
      (value "100nF")
      (footprint "eagle-import:C0805K")
      (libsource (lib "eagle-import") (part "C-EUC0805K"))
    )
    (comp (ref "C35")
      (value "100nF")
      (footprint "eagle-import:C0805K")
      (libsource (lib "eagle-import") (part "C-EUC0805K"))
    )
    (comp (ref "D16")
      (value "7Z5")
      (footprint "eagle-import:SMB")
      (libsource (lib "eagle-import") (part "DIODE-SMB"))
    )
    (comp (ref "D17")
      (value "7Z5")
      (footprint "eagle-import:SMB")
      (libsource (lib "eagle-import") (part "DIODE-SMB"))
    )
    (comp (ref "D18")
      (value "7Z5")
      (footprint "eagle-import:SMB")
      (libsource (lib "eagle-import") (part "DIODE-SMB"))
    )
    (comp (ref "D19")
      (value "7Z5")
      (footprint "eagle-import:SMB")
      (libsource (lib "eagle-import") (part "DIODE-SMB"))
    )
    (comp (ref "D20")
      (value "7Z5")
      (footprint "eagle-import:SMB")
      (libsource (lib "eagle-import") (part "DIODE-SMB"))
    )
    (comp (ref "D21")
      (value "7Z5")
      (footprint "eagle-import:SMB")
      (libsource (lib "eagle-import") (part "DIODE-SMB"))
    )
    (comp (ref "D22")
      (value "7Z5")
      (footprint "eagle-import:SMB")
      (libsource (lib "eagle-import") (part "DIODE-SMB"))
    )
    (comp (ref "D23")
      (value "7Z5")
      (footprint "eagle-import:SMB")
      (libsource (lib "eagle-import") (part "DIODE-SMB"))
    )
    (comp (ref "D24")
      (value "7Z5")
      (footprint "eagle-import:SMB")
      (libsource (lib "eagle-import") (part "DIODE-SMB"))
    )
    (comp (ref "D25")
      (value "7Z5")
      (footprint "eagle-import:SMB")
      (libsource (lib "eagle-import") (part "DIODE-SMB"))
    )
    (comp (ref "D26")
      (value "7Z5")
      (footprint "eagle-import:SMB")
      (libsource (lib "eagle-import") (part "DIODE-SMB"))
    )
    (comp (ref "D27")
      (value "7Z5")
      (footprint "eagle-import:SMB")
      (libsource (lib "eagle-import") (part "DIODE-SMB"))
    )
    (comp (ref "D28")
      (value "7Z5")
      (footprint "eagle-import:SMB")
      (libsource (lib "eagle-import") (part "DIODE-SMB"))
    )
    (comp (ref "D29")
      (value "7Z5")
      (footprint "eagle-import:SMB")
      (libsource (lib "eagle-import") (part "DIODE-SMB"))
    )
    (comp (ref "D32")
      (value "DIODE-SOD123")
      (footprint "eagle-import:SOD123")
      (libsource (lib "eagle-import") (part "DIODE-SOD123"))
    )
    (comp (ref "R88")
      (value "470")
      (footprint "eagle-import:R6332")
      (libsource (lib "eagle-import") (part "R-EU_R6332"))
    )
    (comp (ref "R89")
      (value "221")
      (footprint "eagle-import:R0805")
      (libsource (lib "eagle-import") (part "R-EU_R0805"))
    )
    (comp (ref "R90")
      (value "222")
      (footprint "eagle-import:R0805")
      (libsource (lib "eagle-import") (part "R-EU_R0805"))
    )
    (comp (ref "R91")
      (value "470")
      (footprint "eagle-import:R6332")
      (libsource (lib "eagle-import") (part "R-EU_R6332"))
    )
    (comp (ref "R92")
      (value "0R")
      (footprint "eagle-import:M1206")
      (libsource (lib "eagle-import") (part "R-EU_M1206"))
    )
    (comp (ref "R93")
      (value "0R")
      (footprint "eagle-import:M1206")
      (libsource (lib "eagle-import") (part "R-EU_M1206"))
    )
    (comp (ref "R94")
      (value "470")
      (footprint "eagle-import:R6332")
      (libsource (lib "eagle-import") (part "R-EU_R6332"))
    )
    (comp (ref "R95")
      (value "221")
      (footprint "eagle-import:R0805")
      (libsource (lib "eagle-import") (part "R-EU_R0805"))
    )
    (comp (ref "R96")
      (value "222")
      (footprint "eagle-import:R0805")
      (libsource (lib "eagle-import") (part "R-EU_R0805"))
    )
    (comp (ref "R97")
      (value "470")
      (footprint "eagle-import:R6332")
      (libsource (lib "eagle-import") (part "R-EU_R6332"))
    )
    (comp (ref "R98")
      (value "0R")
      (footprint "eagle-import:M1206")
      (libsource (lib "eagle-import") (part "R-EU_M1206"))
    )
    (comp (ref "R99")
      (value "0R")
      (footprint "eagle-import:M1206")
      (libsource (lib "eagle-import") (part "R-EU_M1206"))
    )
    (comp (ref "R100")
      (value "470")
      (footprint "eagle-import:R6332")
      (libsource (lib "eagle-import") (part "R-EU_R6332"))
    )
    (comp (ref "R101")
      (value "221")
      (footprint "eagle-import:R0805")
      (libsource (lib "eagle-import") (part "R-EU_R0805"))
    )
    (comp (ref "R102")
      (value "222")
      (footprint "eagle-import:R0805")
      (libsource (lib "eagle-import") (part "R-EU_R0805"))
    )
    (comp (ref "R103")
      (value "470")
      (footprint "eagle-import:R6332")
      (libsource (lib "eagle-import") (part "R-EU_R6332"))
    )
    (comp (ref "R104")
      (value "0R")
      (footprint "eagle-import:M1206")
      (libsource (lib "eagle-import") (part "R-EU_M1206"))
    )
    (comp (ref "R105")
      (value "0R")
      (footprint "eagle-import:M1206")
      (libsource (lib "eagle-import") (part "R-EU_M1206"))
    )
    (comp (ref "R106")
      (value "470")
      (footprint "eagle-import:R6332")
      (libsource (lib "eagle-import") (part "R-EU_R6332"))
    )
    (comp (ref "R107")
      (value "221")
      (footprint "eagle-import:R0805")
      (libsource (lib "eagle-import") (part "R-EU_R0805"))
    )
    (comp (ref "R108")
      (value "222")
      (footprint "eagle-import:R0805")
      (libsource (lib "eagle-import") (part "R-EU_R0805"))
    )
    (comp (ref "R109")
      (value "470")
      (footprint "eagle-import:R6332")
      (libsource (lib "eagle-import") (part "R-EU_R6332"))
    )
    (comp (ref "R110")
      (value "0R")
      (footprint "eagle-import:M1206")
      (libsource (lib "eagle-import") (part "R-EU_M1206"))
    )
    (comp (ref "R111")
      (value "0R")
      (footprint "eagle-import:M1206")
      (libsource (lib "eagle-import") (part "R-EU_M1206"))
    )
    (comp (ref "R112")
      (value "470")
      (footprint "eagle-import:R6332")
      (libsource (lib "eagle-import") (part "R-EU_R6332"))
    )
    (comp (ref "R113")
      (value "221")
      (footprint "eagle-import:R0805")
      (libsource (lib "eagle-import") (part "R-EU_R0805"))
    )
    (comp (ref "R114")
      (value "222")
      (footprint "eagle-import:R0805")
      (libsource (lib "eagle-import") (part "R-EU_R0805"))
    )
    (comp (ref "R115")
      (value "470")
      (footprint "eagle-import:R6332")
      (libsource (lib "eagle-import") (part "R-EU_R6332"))
    )
    (comp (ref "R116")
      (value "0R")
      (footprint "eagle-import:M1206")
      (libsource (lib "eagle-import") (part "R-EU_M1206"))
    )
    (comp (ref "R117")
      (value "0R")
      (footprint "eagle-import:M1206")
      (libsource (lib "eagle-import") (part "R-EU_M1206"))
    )
    (comp (ref "R118")
      (value "470")
      (footprint "eagle-import:R6332")
      (libsource (lib "eagle-import") (part "R-EU_R6332"))
    )
    (comp (ref "R119")
      (value "221")
      (footprint "eagle-import:R0805")
      (libsource (lib "eagle-import") (part "R-EU_R0805"))
    )
    (comp (ref "R120")
      (value "222")
      (footprint "eagle-import:R0805")
      (libsource (lib "eagle-import") (part "R-EU_R0805"))
    )
    (comp (ref "R121")
      (value "470")
      (footprint "eagle-import:R6332")
      (libsource (lib "eagle-import") (part "R-EU_R6332"))
    )
    (comp (ref "R122")
      (value "0R")
      (footprint "eagle-import:M1206")
      (libsource (lib "eagle-import") (part "R-EU_M1206"))
    )
    (comp (ref "R123")
      (value "0R")
      (footprint "eagle-import:M1206")
      (libsource (lib "eagle-import") (part "R-EU_M1206"))
    )
    (comp (ref "R124")
      (value "470")
      (footprint "eagle-import:R6332")
      (libsource (lib "eagle-import") (part "R-EU_R6332"))
    )
    (comp (ref "R125")
      (value "221")
      (footprint "eagle-import:R0805")
      (libsource (lib "eagle-import") (part "R-EU_R0805"))
    )
    (comp (ref "R126")
      (value "222")
      (footprint "eagle-import:R0805")
      (libsource (lib "eagle-import") (part "R-EU_R0805"))
    )
    (comp (ref "R127")
      (value "470")
      (footprint "eagle-import:R6332")
      (libsource (lib "eagle-import") (part "R-EU_R6332"))
    )
    (comp (ref "R128")
      (value "0R")
      (footprint "eagle-import:M1206")
      (libsource (lib "eagle-import") (part "R-EU_M1206"))
    )
    (comp (ref "R129")
      (value "0R")
      (footprint "eagle-import:M1206")
      (libsource (lib "eagle-import") (part "R-EU_M1206"))
    )
    (comp (ref "R130")
      (value "470")
      (footprint "eagle-import:R6332")
      (libsource (lib "eagle-import") (part "R-EU_R6332"))
    )
    (comp (ref "R131")
      (value "221")
      (footprint "eagle-import:R0805")
      (libsource (lib "eagle-import") (part "R-EU_R0805"))
    )
    (comp (ref "R132")
      (value "222")
      (footprint "eagle-import:R0805")
      (libsource (lib "eagle-import") (part "R-EU_R0805"))
    )
    (comp (ref "R133")
      (value "470")
      (footprint "eagle-import:R6332")
      (libsource (lib "eagle-import") (part "R-EU_R6332"))
    )
    (comp (ref "R134")
      (value "0R")
      (footprint "eagle-import:M1206")
      (libsource (lib "eagle-import") (part "R-EU_M1206"))
    )
    (comp (ref "R135")
      (value "0R")
      (footprint "eagle-import:M1206")
      (libsource (lib "eagle-import") (part "R-EU_M1206"))
    )
    (comp (ref "R136")
      (value "470")
      (footprint "eagle-import:R6332")
      (libsource (lib "eagle-import") (part "R-EU_R6332"))
    )
    (comp (ref "R137")
      (value "221")
      (footprint "eagle-import:R0805")
      (libsource (lib "eagle-import") (part "R-EU_R0805"))
    )
    (comp (ref "R138")
      (value "222")
      (footprint "eagle-import:R0805")
      (libsource (lib "eagle-import") (part "R-EU_R0805"))
    )
    (comp (ref "R139")
      (value "470")
      (footprint "eagle-import:R6332")
      (libsource (lib "eagle-import") (part "R-EU_R6332"))
    )
    (comp (ref "R140")
      (value "0R")
      (footprint "eagle-import:M1206")
      (libsource (lib "eagle-import") (part "R-EU_M1206"))
    )
    (comp (ref "R141")
      (value "0R")
      (footprint "eagle-import:M1206")
      (libsource (lib "eagle-import") (part "R-EU_M1206"))
    )
    (comp (ref "R142")
      (value "470")
      (footprint "eagle-import:R6332")
      (libsource (lib "eagle-import") (part "R-EU_R6332"))
    )
    (comp (ref "R143")
      (value "221")
      (footprint "eagle-import:R0805")
      (libsource (lib "eagle-import") (part "R-EU_R0805"))
    )
    (comp (ref "R144")
      (value "222")
      (footprint "eagle-import:R0805")
      (libsource (lib "eagle-import") (part "R-EU_R0805"))
    )
    (comp (ref "R145")
      (value "470")
      (footprint "eagle-import:R6332")
      (libsource (lib "eagle-import") (part "R-EU_R6332"))
    )
    (comp (ref "R146")
      (value "0R")
      (footprint "eagle-import:M1206")
      (libsource (lib "eagle-import") (part "R-EU_M1206"))
    )
    (comp (ref "R147")
      (value "0R")
      (footprint "eagle-import:M1206")
      (libsource (lib "eagle-import") (part "R-EU_M1206"))
    )
    (comp (ref "R148")
      (value "470")
      (footprint "eagle-import:R6332")
      (libsource (lib "eagle-import") (part "R-EU_R6332"))
    )
    (comp (ref "R149")
      (value "221")
      (footprint "eagle-import:R0805")
      (libsource (lib "eagle-import") (part "R-EU_R0805"))
    )
    (comp (ref "R150")
      (value "222")
      (footprint "eagle-import:R0805")
      (libsource (lib "eagle-import") (part "R-EU_R0805"))
    )
    (comp (ref "R151")
      (value "470")
      (footprint "eagle-import:R6332")
      (libsource (lib "eagle-import") (part "R-EU_R6332"))
    )
    (comp (ref "R152")
      (value "0R")
      (footprint "eagle-import:M1206")
      (libsource (lib "eagle-import") (part "R-EU_M1206"))
    )
    (comp (ref "R153")
      (value "0R")
      (footprint "eagle-import:M1206")
      (libsource (lib "eagle-import") (part "R-EU_M1206"))
    )
    (comp (ref "R154")
      (value "470")
      (footprint "eagle-import:R6332")
      (libsource (lib "eagle-import") (part "R-EU_R6332"))
    )
    (comp (ref "R155")
      (value "221")
      (footprint "eagle-import:R0805")
      (libsource (lib "eagle-import") (part "R-EU_R0805"))
    )
    (comp (ref "R156")
      (value "222")
      (footprint "eagle-import:R0805")
      (libsource (lib "eagle-import") (part "R-EU_R0805"))
    )
    (comp (ref "R157")
      (value "470")
      (footprint "eagle-import:R6332")
      (libsource (lib "eagle-import") (part "R-EU_R6332"))
    )
    (comp (ref "R158")
      (value "0R")
      (footprint "eagle-import:M1206")
      (libsource (lib "eagle-import") (part "R-EU_M1206"))
    )
    (comp (ref "R159")
      (value "0R")
      (footprint "eagle-import:M1206")
      (libsource (lib "eagle-import") (part "R-EU_M1206"))
    )
    (comp (ref "R160")
      (value "0R")
      (footprint "eagle-import:M1206")
      (libsource (lib "eagle-import") (part "R-EU_M1206"))
    )
    (comp (ref "R161")
      (value "0R")
      (footprint "eagle-import:M1206")
      (libsource (lib "eagle-import") (part "R-EU_M1206"))
    )
    (comp (ref "R162")
      (value "0R")
      (footprint "eagle-import:M1206")
      (libsource (lib "eagle-import") (part "R-EU_M1206"))
    )
    (comp (ref "R164")
      (value "0R")
      (footprint "eagle-import:M1206")
      (libsource (lib "eagle-import") (part "R-EU_M1206"))
    )
    (comp (ref "R165")
      (value "0R")
      (footprint "eagle-import:M1206")
      (libsource (lib "eagle-import") (part "R-EU_M1206"))
    )
    (comp (ref "R166")
      (value "221")
      (footprint "eagle-import:R0805")
      (libsource (lib "eagle-import") (part "R-EU_R0805"))
    )
    (comp (ref "R167")
      (value "221")
      (footprint "eagle-import:R0805")
      (libsource (lib "eagle-import") (part "R-EU_R0805"))
    )
    (comp (ref "R168")
      (value "221")
      (footprint "eagle-import:R0805")
      (libsource (lib "eagle-import") (part "R-EU_R0805"))
    )
    (comp (ref "R169")
      (value "221")
      (footprint "eagle-import:R0805")
      (libsource (lib "eagle-import") (part "R-EU_R0805"))
    )
    (comp (ref "R170")
      (value "221")
      (footprint "eagle-import:R0805")
      (libsource (lib "eagle-import") (part "R-EU_R0805"))
    )
    (comp (ref "R172")
      (value "0R")
      (footprint "eagle-import:M1206")
      (libsource (lib "eagle-import") (part "R-EU_M1206"))
    )
    (comp (ref "U$16")
      (value "LTC6803-4")
      (footprint "eagle-import:SSOP44")
      (libsource (lib "eagle-import") (part "LTC6803-4"))
    )
    (comp (ref "U$17")
      (value "SI8841")
      (footprint "eagle-import:SO16")
      (libsource (lib "eagle-import") (part "SI8841"))
    )
    (comp (ref "U$18")
      (value "SI2351DS")
      (footprint "eagle-import:SOT23")
      (libsource (lib "eagle-import") (part "SI2351DS"))
    )
    (comp (ref "U$19")
      (value "SI2351DS")
      (footprint "eagle-import:SOT23")
      (libsource (lib "eagle-import") (part "SI2351DS"))
    )
    (comp (ref "U$20")
      (value "SI2351DS")
      (footprint "eagle-import:SOT23")
      (libsource (lib "eagle-import") (part "SI2351DS"))
    )
    (comp (ref "U$21")
      (value "SI2351DS")
      (footprint "eagle-import:SOT23")
      (libsource (lib "eagle-import") (part "SI2351DS"))
    )
    (comp (ref "U$22")
      (value "SI2351DS")
      (footprint "eagle-import:SOT23")
      (libsource (lib "eagle-import") (part "SI2351DS"))
    )
    (comp (ref "U$23")
      (value "SI2351DS")
      (footprint "eagle-import:SOT23")
      (libsource (lib "eagle-import") (part "SI2351DS"))
    )
    (comp (ref "U$24")
      (value "SI2351DS")
      (footprint "eagle-import:SOT23")
      (libsource (lib "eagle-import") (part "SI2351DS"))
    )
    (comp (ref "U$25")
      (value "SI2351DS")
      (footprint "eagle-import:SOT23")
      (libsource (lib "eagle-import") (part "SI2351DS"))
    )
    (comp (ref "U$26")
      (value "SI2351DS")
      (footprint "eagle-import:SOT23")
      (libsource (lib "eagle-import") (part "SI2351DS"))
    )
    (comp (ref "U$27")
      (value "SI2351DS")
      (footprint "eagle-import:SOT23")
      (libsource (lib "eagle-import") (part "SI2351DS"))
    )
    (comp (ref "U$28")
      (value "SI2351DS")
      (footprint "eagle-import:SOT23")
      (libsource (lib "eagle-import") (part "SI2351DS"))
    )
    (comp (ref "U$29")
      (value "SI2351DS")
      (footprint "eagle-import:SOT23")
      (libsource (lib "eagle-import") (part "SI2351DS"))
    )
    (comp (ref "U$30")
      (value "INDUCTOR")
      (footprint "eagle-import:L2012C")
      (libsource (lib "eagle-import") (part "INDUCTOR"))
    )
    (comp (ref "C18")
      (value "100nF")
      (footprint "eagle-import:C0805K")
      (libsource (lib "eagle-import") (part "C-EUC0805K"))
    )
    (comp (ref "C37")
      (value "100nF")
      (footprint "eagle-import:C0805K")
      (libsource (lib "eagle-import") (part "C-EUC0805K"))
    )
    (comp (ref "C38")
      (value "100nF")
      (footprint "eagle-import:C0805K")
      (libsource (lib "eagle-import") (part "C-EUC0805K"))
    )
    (comp (ref "C39")
      (value "100nF")
      (footprint "eagle-import:C0805K")
      (libsource (lib "eagle-import") (part "C-EUC0805K"))
    )
    (comp (ref "C40")
      (value "100nF")
      (footprint "eagle-import:C0805K")
      (libsource (lib "eagle-import") (part "C-EUC0805K"))
    )
    (comp (ref "C41")
      (value "100nF")
      (footprint "eagle-import:C0805K")
      (libsource (lib "eagle-import") (part "C-EUC0805K"))
    )
    (comp (ref "C43")
      (value "100nF")
      (footprint "eagle-import:C0805K")
      (libsource (lib "eagle-import") (part "C-EUC0805K"))
    )
    (comp (ref "C44")
      (value "100nF")
      (footprint "eagle-import:C0805K")
      (libsource (lib "eagle-import") (part "C-EUC0805K"))
    )
    (comp (ref "C45")
      (value "100nF")
      (footprint "eagle-import:C0805K")
      (libsource (lib "eagle-import") (part "C-EUC0805K"))
    )
    (comp (ref "C46")
      (value "100nF")
      (footprint "eagle-import:C0805K")
      (libsource (lib "eagle-import") (part "C-EUC0805K"))
    )
    (comp (ref "C47")
      (value "100nF")
      (footprint "eagle-import:C0805K")
      (libsource (lib "eagle-import") (part "C-EUC0805K"))
    )
    (comp (ref "C48")
      (value "100nF")
      (footprint "eagle-import:C0805K")
      (libsource (lib "eagle-import") (part "C-EUC0805K"))
    )
    (comp (ref "C49")
      (value "100nF")
      (footprint "eagle-import:C0805K")
      (libsource (lib "eagle-import") (part "C-EUC0805K"))
    )
    (comp (ref "C50")
      (value "100nF")
      (footprint "eagle-import:C0805K")
      (libsource (lib "eagle-import") (part "C-EUC0805K"))
    )
    (comp (ref "C51")
      (value "100nF")
      (footprint "eagle-import:C0805K")
      (libsource (lib "eagle-import") (part "C-EUC0805K"))
    )
    (comp (ref "C52")
      (value "100nF")
      (footprint "eagle-import:C0805K")
      (libsource (lib "eagle-import") (part "C-EUC0805K"))
    )
    (comp (ref "C53")
      (value "100nF")
      (footprint "eagle-import:C0805K")
      (libsource (lib "eagle-import") (part "C-EUC0805K"))
    )
    (comp (ref "D34")
      (value "7Z5")
      (footprint "eagle-import:SMB")
      (libsource (lib "eagle-import") (part "DIODE-SMB"))
    )
    (comp (ref "D36")
      (value "7Z5")
      (footprint "eagle-import:SMB")
      (libsource (lib "eagle-import") (part "DIODE-SMB"))
    )
    (comp (ref "D48")
      (value "7Z5")
      (footprint "eagle-import:SMB")
      (libsource (lib "eagle-import") (part "DIODE-SMB"))
    )
    (comp (ref "D49")
      (value "7Z5")
      (footprint "eagle-import:SMB")
      (libsource (lib "eagle-import") (part "DIODE-SMB"))
    )
    (comp (ref "D50")
      (value "7Z5")
      (footprint "eagle-import:SMB")
      (libsource (lib "eagle-import") (part "DIODE-SMB"))
    )
    (comp (ref "D51")
      (value "7Z5")
      (footprint "eagle-import:SMB")
      (libsource (lib "eagle-import") (part "DIODE-SMB"))
    )
    (comp (ref "D52")
      (value "7Z5")
      (footprint "eagle-import:SMB")
      (libsource (lib "eagle-import") (part "DIODE-SMB"))
    )
    (comp (ref "D53")
      (value "7Z5")
      (footprint "eagle-import:SMB")
      (libsource (lib "eagle-import") (part "DIODE-SMB"))
    )
    (comp (ref "D54")
      (value "7Z5")
      (footprint "eagle-import:SMB")
      (libsource (lib "eagle-import") (part "DIODE-SMB"))
    )
    (comp (ref "D55")
      (value "7Z5")
      (footprint "eagle-import:SMB")
      (libsource (lib "eagle-import") (part "DIODE-SMB"))
    )
    (comp (ref "D56")
      (value "7Z5")
      (footprint "eagle-import:SMB")
      (libsource (lib "eagle-import") (part "DIODE-SMB"))
    )
    (comp (ref "D57")
      (value "7Z5")
      (footprint "eagle-import:SMB")
      (libsource (lib "eagle-import") (part "DIODE-SMB"))
    )
    (comp (ref "D58")
      (value "7Z5")
      (footprint "eagle-import:SMB")
      (libsource (lib "eagle-import") (part "DIODE-SMB"))
    )
    (comp (ref "D59")
      (value "7Z5")
      (footprint "eagle-import:SMB")
      (libsource (lib "eagle-import") (part "DIODE-SMB"))
    )
    (comp (ref "D60")
      (value "DIODE-SOD123")
      (footprint "eagle-import:SOD123")
      (libsource (lib "eagle-import") (part "DIODE-SOD123"))
    )
    (comp (ref "R2")
      (value "470")
      (footprint "eagle-import:R6332")
      (libsource (lib "eagle-import") (part "R-EU_R6332"))
    )
    (comp (ref "R78")
      (value "221")
      (footprint "eagle-import:R0805")
      (libsource (lib "eagle-import") (part "R-EU_R0805"))
    )
    (comp (ref "R86")
      (value "222")
      (footprint "eagle-import:R0805")
      (libsource (lib "eagle-import") (part "R-EU_R0805"))
    )
    (comp (ref "R87")
      (value "470")
      (footprint "eagle-import:R6332")
      (libsource (lib "eagle-import") (part "R-EU_R6332"))
    )
    (comp (ref "R163")
      (value "0R")
      (footprint "eagle-import:M1206")
      (libsource (lib "eagle-import") (part "R-EU_M1206"))
    )
    (comp (ref "R171")
      (value "0R")
      (footprint "eagle-import:M1206")
      (libsource (lib "eagle-import") (part "R-EU_M1206"))
    )
    (comp (ref "R173")
      (value "470")
      (footprint "eagle-import:R6332")
      (libsource (lib "eagle-import") (part "R-EU_R6332"))
    )
    (comp (ref "R174")
      (value "221")
      (footprint "eagle-import:R0805")
      (libsource (lib "eagle-import") (part "R-EU_R0805"))
    )
    (comp (ref "R175")
      (value "222")
      (footprint "eagle-import:R0805")
      (libsource (lib "eagle-import") (part "R-EU_R0805"))
    )
    (comp (ref "R176")
      (value "470")
      (footprint "eagle-import:R6332")
      (libsource (lib "eagle-import") (part "R-EU_R6332"))
    )
    (comp (ref "R177")
      (value "0R")
      (footprint "eagle-import:M1206")
      (libsource (lib "eagle-import") (part "R-EU_M1206"))
    )
    (comp (ref "R178")
      (value "0R")
      (footprint "eagle-import:M1206")
      (libsource (lib "eagle-import") (part "R-EU_M1206"))
    )
    (comp (ref "R179")
      (value "470")
      (footprint "eagle-import:R6332")
      (libsource (lib "eagle-import") (part "R-EU_R6332"))
    )
    (comp (ref "R180")
      (value "221")
      (footprint "eagle-import:R0805")
      (libsource (lib "eagle-import") (part "R-EU_R0805"))
    )
    (comp (ref "R182")
      (value "222")
      (footprint "eagle-import:R0805")
      (libsource (lib "eagle-import") (part "R-EU_R0805"))
    )
    (comp (ref "R257")
      (value "470")
      (footprint "eagle-import:R6332")
      (libsource (lib "eagle-import") (part "R-EU_R6332"))
    )
    (comp (ref "R266")
      (value "0R")
      (footprint "eagle-import:M1206")
      (libsource (lib "eagle-import") (part "R-EU_M1206"))
    )
    (comp (ref "R267")
      (value "0R")
      (footprint "eagle-import:M1206")
      (libsource (lib "eagle-import") (part "R-EU_M1206"))
    )
    (comp (ref "R268")
      (value "470")
      (footprint "eagle-import:R6332")
      (libsource (lib "eagle-import") (part "R-EU_R6332"))
    )
    (comp (ref "R269")
      (value "221")
      (footprint "eagle-import:R0805")
      (libsource (lib "eagle-import") (part "R-EU_R0805"))
    )
    (comp (ref "R270")
      (value "222")
      (footprint "eagle-import:R0805")
      (libsource (lib "eagle-import") (part "R-EU_R0805"))
    )
    (comp (ref "R271")
      (value "470")
      (footprint "eagle-import:R6332")
      (libsource (lib "eagle-import") (part "R-EU_R6332"))
    )
    (comp (ref "R272")
      (value "0R")
      (footprint "eagle-import:M1206")
      (libsource (lib "eagle-import") (part "R-EU_M1206"))
    )
    (comp (ref "R273")
      (value "0R")
      (footprint "eagle-import:M1206")
      (libsource (lib "eagle-import") (part "R-EU_M1206"))
    )
    (comp (ref "R274")
      (value "470")
      (footprint "eagle-import:R6332")
      (libsource (lib "eagle-import") (part "R-EU_R6332"))
    )
    (comp (ref "R275")
      (value "221")
      (footprint "eagle-import:R0805")
      (libsource (lib "eagle-import") (part "R-EU_R0805"))
    )
    (comp (ref "R276")
      (value "222")
      (footprint "eagle-import:R0805")
      (libsource (lib "eagle-import") (part "R-EU_R0805"))
    )
    (comp (ref "R277")
      (value "470")
      (footprint "eagle-import:R6332")
      (libsource (lib "eagle-import") (part "R-EU_R6332"))
    )
    (comp (ref "R278")
      (value "0R")
      (footprint "eagle-import:M1206")
      (libsource (lib "eagle-import") (part "R-EU_M1206"))
    )
    (comp (ref "R279")
      (value "0R")
      (footprint "eagle-import:M1206")
      (libsource (lib "eagle-import") (part "R-EU_M1206"))
    )
    (comp (ref "R280")
      (value "470")
      (footprint "eagle-import:R6332")
      (libsource (lib "eagle-import") (part "R-EU_R6332"))
    )
    (comp (ref "R281")
      (value "221")
      (footprint "eagle-import:R0805")
      (libsource (lib "eagle-import") (part "R-EU_R0805"))
    )
    (comp (ref "R282")
      (value "222")
      (footprint "eagle-import:R0805")
      (libsource (lib "eagle-import") (part "R-EU_R0805"))
    )
    (comp (ref "R283")
      (value "470")
      (footprint "eagle-import:R6332")
      (libsource (lib "eagle-import") (part "R-EU_R6332"))
    )
    (comp (ref "R284")
      (value "0R")
      (footprint "eagle-import:M1206")
      (libsource (lib "eagle-import") (part "R-EU_M1206"))
    )
    (comp (ref "R285")
      (value "0R")
      (footprint "eagle-import:M1206")
      (libsource (lib "eagle-import") (part "R-EU_M1206"))
    )
    (comp (ref "R286")
      (value "470")
      (footprint "eagle-import:R6332")
      (libsource (lib "eagle-import") (part "R-EU_R6332"))
    )
    (comp (ref "R287")
      (value "221")
      (footprint "eagle-import:R0805")
      (libsource (lib "eagle-import") (part "R-EU_R0805"))
    )
    (comp (ref "R288")
      (value "222")
      (footprint "eagle-import:R0805")
      (libsource (lib "eagle-import") (part "R-EU_R0805"))
    )
    (comp (ref "R289")
      (value "470")
      (footprint "eagle-import:R6332")
      (libsource (lib "eagle-import") (part "R-EU_R6332"))
    )
    (comp (ref "R290")
      (value "0R")
      (footprint "eagle-import:M1206")
      (libsource (lib "eagle-import") (part "R-EU_M1206"))
    )
    (comp (ref "R291")
      (value "0R")
      (footprint "eagle-import:M1206")
      (libsource (lib "eagle-import") (part "R-EU_M1206"))
    )
    (comp (ref "R292")
      (value "470")
      (footprint "eagle-import:R6332")
      (libsource (lib "eagle-import") (part "R-EU_R6332"))
    )
    (comp (ref "R293")
      (value "221")
      (footprint "eagle-import:R0805")
      (libsource (lib "eagle-import") (part "R-EU_R0805"))
    )
    (comp (ref "R294")
      (value "222")
      (footprint "eagle-import:R0805")
      (libsource (lib "eagle-import") (part "R-EU_R0805"))
    )
    (comp (ref "R295")
      (value "470")
      (footprint "eagle-import:R6332")
      (libsource (lib "eagle-import") (part "R-EU_R6332"))
    )
    (comp (ref "R296")
      (value "0R")
      (footprint "eagle-import:M1206")
      (libsource (lib "eagle-import") (part "R-EU_M1206"))
    )
    (comp (ref "R297")
      (value "0R")
      (footprint "eagle-import:M1206")
      (libsource (lib "eagle-import") (part "R-EU_M1206"))
    )
    (comp (ref "R298")
      (value "470")
      (footprint "eagle-import:R6332")
      (libsource (lib "eagle-import") (part "R-EU_R6332"))
    )
    (comp (ref "R299")
      (value "221")
      (footprint "eagle-import:R0805")
      (libsource (lib "eagle-import") (part "R-EU_R0805"))
    )
    (comp (ref "R300")
      (value "222")
      (footprint "eagle-import:R0805")
      (libsource (lib "eagle-import") (part "R-EU_R0805"))
    )
    (comp (ref "R301")
      (value "470")
      (footprint "eagle-import:R6332")
      (libsource (lib "eagle-import") (part "R-EU_R6332"))
    )
    (comp (ref "R302")
      (value "0R")
      (footprint "eagle-import:M1206")
      (libsource (lib "eagle-import") (part "R-EU_M1206"))
    )
    (comp (ref "R303")
      (value "0R")
      (footprint "eagle-import:M1206")
      (libsource (lib "eagle-import") (part "R-EU_M1206"))
    )
    (comp (ref "R304")
      (value "470")
      (footprint "eagle-import:R6332")
      (libsource (lib "eagle-import") (part "R-EU_R6332"))
    )
    (comp (ref "R305")
      (value "221")
      (footprint "eagle-import:R0805")
      (libsource (lib "eagle-import") (part "R-EU_R0805"))
    )
    (comp (ref "R306")
      (value "222")
      (footprint "eagle-import:R0805")
      (libsource (lib "eagle-import") (part "R-EU_R0805"))
    )
    (comp (ref "R307")
      (value "470")
      (footprint "eagle-import:R6332")
      (libsource (lib "eagle-import") (part "R-EU_R6332"))
    )
    (comp (ref "R308")
      (value "0R")
      (footprint "eagle-import:M1206")
      (libsource (lib "eagle-import") (part "R-EU_M1206"))
    )
    (comp (ref "R309")
      (value "0R")
      (footprint "eagle-import:M1206")
      (libsource (lib "eagle-import") (part "R-EU_M1206"))
    )
    (comp (ref "R310")
      (value "470")
      (footprint "eagle-import:R6332")
      (libsource (lib "eagle-import") (part "R-EU_R6332"))
    )
    (comp (ref "R311")
      (value "221")
      (footprint "eagle-import:R0805")
      (libsource (lib "eagle-import") (part "R-EU_R0805"))
    )
    (comp (ref "R312")
      (value "222")
      (footprint "eagle-import:R0805")
      (libsource (lib "eagle-import") (part "R-EU_R0805"))
    )
    (comp (ref "R313")
      (value "470")
      (footprint "eagle-import:R6332")
      (libsource (lib "eagle-import") (part "R-EU_R6332"))
    )
    (comp (ref "R314")
      (value "0R")
      (footprint "eagle-import:M1206")
      (libsource (lib "eagle-import") (part "R-EU_M1206"))
    )
    (comp (ref "R315")
      (value "0R")
      (footprint "eagle-import:M1206")
      (libsource (lib "eagle-import") (part "R-EU_M1206"))
    )
    (comp (ref "R316")
      (value "470")
      (footprint "eagle-import:R6332")
      (libsource (lib "eagle-import") (part "R-EU_R6332"))
    )
    (comp (ref "R317")
      (value "221")
      (footprint "eagle-import:R0805")
      (libsource (lib "eagle-import") (part "R-EU_R0805"))
    )
    (comp (ref "R318")
      (value "222")
      (footprint "eagle-import:R0805")
      (libsource (lib "eagle-import") (part "R-EU_R0805"))
    )
    (comp (ref "R319")
      (value "470")
      (footprint "eagle-import:R6332")
      (libsource (lib "eagle-import") (part "R-EU_R6332"))
    )
    (comp (ref "R320")
      (value "0R")
      (footprint "eagle-import:M1206")
      (libsource (lib "eagle-import") (part "R-EU_M1206"))
    )
    (comp (ref "R321")
      (value "0R")
      (footprint "eagle-import:M1206")
      (libsource (lib "eagle-import") (part "R-EU_M1206"))
    )
    (comp (ref "R322")
      (value "0R")
      (footprint "eagle-import:M1206")
      (libsource (lib "eagle-import") (part "R-EU_M1206"))
    )
    (comp (ref "R323")
      (value "0R")
      (footprint "eagle-import:M1206")
      (libsource (lib "eagle-import") (part "R-EU_M1206"))
    )
    (comp (ref "R324")
      (value "0R")
      (footprint "eagle-import:M1206")
      (libsource (lib "eagle-import") (part "R-EU_M1206"))
    )
    (comp (ref "R325")
      (value "0R")
      (footprint "eagle-import:M1206")
      (libsource (lib "eagle-import") (part "R-EU_M1206"))
    )
    (comp (ref "R326")
      (value "0R")
      (footprint "eagle-import:M1206")
      (libsource (lib "eagle-import") (part "R-EU_M1206"))
    )
    (comp (ref "R327")
      (value "221")
      (footprint "eagle-import:R0805")
      (libsource (lib "eagle-import") (part "R-EU_R0805"))
    )
    (comp (ref "R328")
      (value "221")
      (footprint "eagle-import:R0805")
      (libsource (lib "eagle-import") (part "R-EU_R0805"))
    )
    (comp (ref "R329")
      (value "221")
      (footprint "eagle-import:R0805")
      (libsource (lib "eagle-import") (part "R-EU_R0805"))
    )
    (comp (ref "R330")
      (value "221")
      (footprint "eagle-import:R0805")
      (libsource (lib "eagle-import") (part "R-EU_R0805"))
    )
    (comp (ref "R331")
      (value "221")
      (footprint "eagle-import:R0805")
      (libsource (lib "eagle-import") (part "R-EU_R0805"))
    )
    (comp (ref "R332")
      (value "0R")
      (footprint "eagle-import:M1206")
      (libsource (lib "eagle-import") (part "R-EU_M1206"))
    )
    (comp (ref "S1")
      (value "SOCKET40P")
      (footprint "eagle-import:40PIN")
      (libsource (lib "eagle-import") (part "SOCKET40P"))
    )
    (comp (ref "U$31")
      (value "LTC6803-4")
      (footprint "eagle-import:SSOP44")
      (libsource (lib "eagle-import") (part "LTC6803-4"))
    )
    (comp (ref "U$32")
      (value "SI8841")
      (footprint "eagle-import:SO16")
      (libsource (lib "eagle-import") (part "SI8841"))
    )
    (comp (ref "U$33")
      (value "SI2351DS")
      (footprint "eagle-import:SOT23")
      (libsource (lib "eagle-import") (part "SI2351DS"))
    )
    (comp (ref "U$43")
      (value "SI2351DS")
      (footprint "eagle-import:SOT23")
      (libsource (lib "eagle-import") (part "SI2351DS"))
    )
    (comp (ref "U$44")
      (value "SI2351DS")
      (footprint "eagle-import:SOT23")
      (libsource (lib "eagle-import") (part "SI2351DS"))
    )
    (comp (ref "U$51")
      (value "SI2351DS")
      (footprint "eagle-import:SOT23")
      (libsource (lib "eagle-import") (part "SI2351DS"))
    )
    (comp (ref "U$52")
      (value "SI2351DS")
      (footprint "eagle-import:SOT23")
      (libsource (lib "eagle-import") (part "SI2351DS"))
    )
    (comp (ref "U$53")
      (value "SI2351DS")
      (footprint "eagle-import:SOT23")
      (libsource (lib "eagle-import") (part "SI2351DS"))
    )
    (comp (ref "U$54")
      (value "SI2351DS")
      (footprint "eagle-import:SOT23")
      (libsource (lib "eagle-import") (part "SI2351DS"))
    )
    (comp (ref "U$55")
      (value "SI2351DS")
      (footprint "eagle-import:SOT23")
      (libsource (lib "eagle-import") (part "SI2351DS"))
    )
    (comp (ref "U$56")
      (value "SI2351DS")
      (footprint "eagle-import:SOT23")
      (libsource (lib "eagle-import") (part "SI2351DS"))
    )
    (comp (ref "U$57")
      (value "SI2351DS")
      (footprint "eagle-import:SOT23")
      (libsource (lib "eagle-import") (part "SI2351DS"))
    )
    (comp (ref "U$58")
      (value "SI2351DS")
      (footprint "eagle-import:SOT23")
      (libsource (lib "eagle-import") (part "SI2351DS"))
    )
    (comp (ref "U$59")
      (value "SI2351DS")
      (footprint "eagle-import:SOT23")
      (libsource (lib "eagle-import") (part "SI2351DS"))
    )
    (comp (ref "U$60")
      (value "INDUCTOR")
      (footprint "eagle-import:L2012C")
      (libsource (lib "eagle-import") (part "INDUCTOR"))
    )
    (comp (ref "C103")
      (value "100nF")
      (footprint "eagle-import:C0805K")
      (libsource (lib "eagle-import") (part "C-EUC0805K"))
    )
    (comp (ref "C104")
      (value "100nF")
      (footprint "eagle-import:C0805K")
      (libsource (lib "eagle-import") (part "C-EUC0805K"))
    )
    (comp (ref "C105")
      (value "100nF")
      (footprint "eagle-import:C0805K")
      (libsource (lib "eagle-import") (part "C-EUC0805K"))
    )
    (comp (ref "C106")
      (value "100nF")
      (footprint "eagle-import:C0805K")
      (libsource (lib "eagle-import") (part "C-EUC0805K"))
    )
    (comp (ref "C107")
      (value "100nF")
      (footprint "eagle-import:C0805K")
      (libsource (lib "eagle-import") (part "C-EUC0805K"))
    )
    (comp (ref "C108")
      (value "100nF")
      (footprint "eagle-import:C0805K")
      (libsource (lib "eagle-import") (part "C-EUC0805K"))
    )
    (comp (ref "C109")
      (value "100nF")
      (footprint "eagle-import:C0805K")
      (libsource (lib "eagle-import") (part "C-EUC0805K"))
    )
    (comp (ref "C110")
      (value "100nF")
      (footprint "eagle-import:C0805K")
      (libsource (lib "eagle-import") (part "C-EUC0805K"))
    )
    (comp (ref "C111")
      (value "100nF")
      (footprint "eagle-import:C0805K")
      (libsource (lib "eagle-import") (part "C-EUC0805K"))
    )
    (comp (ref "C112")
      (value "100nF")
      (footprint "eagle-import:C0805K")
      (libsource (lib "eagle-import") (part "C-EUC0805K"))
    )
    (comp (ref "C113")
      (value "100nF")
      (footprint "eagle-import:C0805K")
      (libsource (lib "eagle-import") (part "C-EUC0805K"))
    )
    (comp (ref "C114")
      (value "100nF")
      (footprint "eagle-import:C0805K")
      (libsource (lib "eagle-import") (part "C-EUC0805K"))
    )
    (comp (ref "C115")
      (value "100nF")
      (footprint "eagle-import:C0805K")
      (libsource (lib "eagle-import") (part "C-EUC0805K"))
    )
    (comp (ref "C116")
      (value "100nF")
      (footprint "eagle-import:C0805K")
      (libsource (lib "eagle-import") (part "C-EUC0805K"))
    )
    (comp (ref "C117")
      (value "100nF")
      (footprint "eagle-import:C0805K")
      (libsource (lib "eagle-import") (part "C-EUC0805K"))
    )
    (comp (ref "C118")
      (value "100nF")
      (footprint "eagle-import:C0805K")
      (libsource (lib "eagle-import") (part "C-EUC0805K"))
    )
    (comp (ref "C119")
      (value "100nF")
      (footprint "eagle-import:C0805K")
      (libsource (lib "eagle-import") (part "C-EUC0805K"))
    )
    (comp (ref "D91")
      (value "7Z5")
      (footprint "eagle-import:SMB")
      (libsource (lib "eagle-import") (part "DIODE-SMB"))
    )
    (comp (ref "D92")
      (value "7Z5")
      (footprint "eagle-import:SMB")
      (libsource (lib "eagle-import") (part "DIODE-SMB"))
    )
    (comp (ref "D93")
      (value "7Z5")
      (footprint "eagle-import:SMB")
      (libsource (lib "eagle-import") (part "DIODE-SMB"))
    )
    (comp (ref "D94")
      (value "7Z5")
      (footprint "eagle-import:SMB")
      (libsource (lib "eagle-import") (part "DIODE-SMB"))
    )
    (comp (ref "D95")
      (value "7Z5")
      (footprint "eagle-import:SMB")
      (libsource (lib "eagle-import") (part "DIODE-SMB"))
    )
    (comp (ref "D96")
      (value "7Z5")
      (footprint "eagle-import:SMB")
      (libsource (lib "eagle-import") (part "DIODE-SMB"))
    )
    (comp (ref "D97")
      (value "7Z5")
      (footprint "eagle-import:SMB")
      (libsource (lib "eagle-import") (part "DIODE-SMB"))
    )
    (comp (ref "D98")
      (value "7Z5")
      (footprint "eagle-import:SMB")
      (libsource (lib "eagle-import") (part "DIODE-SMB"))
    )
    (comp (ref "D99")
      (value "7Z5")
      (footprint "eagle-import:SMB")
      (libsource (lib "eagle-import") (part "DIODE-SMB"))
    )
    (comp (ref "D100")
      (value "7Z5")
      (footprint "eagle-import:SMB")
      (libsource (lib "eagle-import") (part "DIODE-SMB"))
    )
    (comp (ref "D101")
      (value "7Z5")
      (footprint "eagle-import:SMB")
      (libsource (lib "eagle-import") (part "DIODE-SMB"))
    )
    (comp (ref "D102")
      (value "7Z5")
      (footprint "eagle-import:SMB")
      (libsource (lib "eagle-import") (part "DIODE-SMB"))
    )
    (comp (ref "D103")
      (value "7Z5")
      (footprint "eagle-import:SMB")
      (libsource (lib "eagle-import") (part "DIODE-SMB"))
    )
    (comp (ref "D104")
      (value "7Z5")
      (footprint "eagle-import:SMB")
      (libsource (lib "eagle-import") (part "DIODE-SMB"))
    )
    (comp (ref "D105")
      (value "DIODE-SOD123")
      (footprint "eagle-import:SOD123")
      (libsource (lib "eagle-import") (part "DIODE-SOD123"))
    )
    (comp (ref "R499")
      (value "470")
      (footprint "eagle-import:R6332")
      (libsource (lib "eagle-import") (part "R-EU_R6332"))
    )
    (comp (ref "R500")
      (value "221")
      (footprint "eagle-import:R0805")
      (libsource (lib "eagle-import") (part "R-EU_R0805"))
    )
    (comp (ref "R501")
      (value "222")
      (footprint "eagle-import:R0805")
      (libsource (lib "eagle-import") (part "R-EU_R0805"))
    )
    (comp (ref "R502")
      (value "470")
      (footprint "eagle-import:R6332")
      (libsource (lib "eagle-import") (part "R-EU_R6332"))
    )
    (comp (ref "R503")
      (value "0R")
      (footprint "eagle-import:M1206")
      (libsource (lib "eagle-import") (part "R-EU_M1206"))
    )
    (comp (ref "R504")
      (value "0R")
      (footprint "eagle-import:M1206")
      (libsource (lib "eagle-import") (part "R-EU_M1206"))
    )
    (comp (ref "R505")
      (value "470")
      (footprint "eagle-import:R6332")
      (libsource (lib "eagle-import") (part "R-EU_R6332"))
    )
    (comp (ref "R506")
      (value "221")
      (footprint "eagle-import:R0805")
      (libsource (lib "eagle-import") (part "R-EU_R0805"))
    )
    (comp (ref "R507")
      (value "222")
      (footprint "eagle-import:R0805")
      (libsource (lib "eagle-import") (part "R-EU_R0805"))
    )
    (comp (ref "R508")
      (value "470")
      (footprint "eagle-import:R6332")
      (libsource (lib "eagle-import") (part "R-EU_R6332"))
    )
    (comp (ref "R509")
      (value "0R")
      (footprint "eagle-import:M1206")
      (libsource (lib "eagle-import") (part "R-EU_M1206"))
    )
    (comp (ref "R510")
      (value "0R")
      (footprint "eagle-import:M1206")
      (libsource (lib "eagle-import") (part "R-EU_M1206"))
    )
    (comp (ref "R511")
      (value "470")
      (footprint "eagle-import:R6332")
      (libsource (lib "eagle-import") (part "R-EU_R6332"))
    )
    (comp (ref "R512")
      (value "221")
      (footprint "eagle-import:R0805")
      (libsource (lib "eagle-import") (part "R-EU_R0805"))
    )
    (comp (ref "R513")
      (value "222")
      (footprint "eagle-import:R0805")
      (libsource (lib "eagle-import") (part "R-EU_R0805"))
    )
    (comp (ref "R514")
      (value "470")
      (footprint "eagle-import:R6332")
      (libsource (lib "eagle-import") (part "R-EU_R6332"))
    )
    (comp (ref "R515")
      (value "0R")
      (footprint "eagle-import:M1206")
      (libsource (lib "eagle-import") (part "R-EU_M1206"))
    )
    (comp (ref "R516")
      (value "0R")
      (footprint "eagle-import:M1206")
      (libsource (lib "eagle-import") (part "R-EU_M1206"))
    )
    (comp (ref "R517")
      (value "470")
      (footprint "eagle-import:R6332")
      (libsource (lib "eagle-import") (part "R-EU_R6332"))
    )
    (comp (ref "R518")
      (value "221")
      (footprint "eagle-import:R0805")
      (libsource (lib "eagle-import") (part "R-EU_R0805"))
    )
    (comp (ref "R519")
      (value "222")
      (footprint "eagle-import:R0805")
      (libsource (lib "eagle-import") (part "R-EU_R0805"))
    )
    (comp (ref "R520")
      (value "470")
      (footprint "eagle-import:R6332")
      (libsource (lib "eagle-import") (part "R-EU_R6332"))
    )
    (comp (ref "R521")
      (value "0R")
      (footprint "eagle-import:M1206")
      (libsource (lib "eagle-import") (part "R-EU_M1206"))
    )
    (comp (ref "R522")
      (value "0R")
      (footprint "eagle-import:M1206")
      (libsource (lib "eagle-import") (part "R-EU_M1206"))
    )
    (comp (ref "R523")
      (value "470")
      (footprint "eagle-import:R6332")
      (libsource (lib "eagle-import") (part "R-EU_R6332"))
    )
    (comp (ref "R524")
      (value "221")
      (footprint "eagle-import:R0805")
      (libsource (lib "eagle-import") (part "R-EU_R0805"))
    )
    (comp (ref "R525")
      (value "222")
      (footprint "eagle-import:R0805")
      (libsource (lib "eagle-import") (part "R-EU_R0805"))
    )
    (comp (ref "R526")
      (value "470")
      (footprint "eagle-import:R6332")
      (libsource (lib "eagle-import") (part "R-EU_R6332"))
    )
    (comp (ref "R527")
      (value "0R")
      (footprint "eagle-import:M1206")
      (libsource (lib "eagle-import") (part "R-EU_M1206"))
    )
    (comp (ref "R528")
      (value "0R")
      (footprint "eagle-import:M1206")
      (libsource (lib "eagle-import") (part "R-EU_M1206"))
    )
    (comp (ref "R529")
      (value "470")
      (footprint "eagle-import:R6332")
      (libsource (lib "eagle-import") (part "R-EU_R6332"))
    )
    (comp (ref "R530")
      (value "221")
      (footprint "eagle-import:R0805")
      (libsource (lib "eagle-import") (part "R-EU_R0805"))
    )
    (comp (ref "R531")
      (value "222")
      (footprint "eagle-import:R0805")
      (libsource (lib "eagle-import") (part "R-EU_R0805"))
    )
    (comp (ref "R532")
      (value "470")
      (footprint "eagle-import:R6332")
      (libsource (lib "eagle-import") (part "R-EU_R6332"))
    )
    (comp (ref "R533")
      (value "0R")
      (footprint "eagle-import:M1206")
      (libsource (lib "eagle-import") (part "R-EU_M1206"))
    )
    (comp (ref "R534")
      (value "0R")
      (footprint "eagle-import:M1206")
      (libsource (lib "eagle-import") (part "R-EU_M1206"))
    )
    (comp (ref "R535")
      (value "470")
      (footprint "eagle-import:R6332")
      (libsource (lib "eagle-import") (part "R-EU_R6332"))
    )
    (comp (ref "R536")
      (value "221")
      (footprint "eagle-import:R0805")
      (libsource (lib "eagle-import") (part "R-EU_R0805"))
    )
    (comp (ref "R537")
      (value "222")
      (footprint "eagle-import:R0805")
      (libsource (lib "eagle-import") (part "R-EU_R0805"))
    )
    (comp (ref "R538")
      (value "470")
      (footprint "eagle-import:R6332")
      (libsource (lib "eagle-import") (part "R-EU_R6332"))
    )
    (comp (ref "R539")
      (value "0R")
      (footprint "eagle-import:M1206")
      (libsource (lib "eagle-import") (part "R-EU_M1206"))
    )
    (comp (ref "R540")
      (value "0R")
      (footprint "eagle-import:M1206")
      (libsource (lib "eagle-import") (part "R-EU_M1206"))
    )
    (comp (ref "R541")
      (value "470")
      (footprint "eagle-import:R6332")
      (libsource (lib "eagle-import") (part "R-EU_R6332"))
    )
    (comp (ref "R542")
      (value "221")
      (footprint "eagle-import:R0805")
      (libsource (lib "eagle-import") (part "R-EU_R0805"))
    )
    (comp (ref "R543")
      (value "222")
      (footprint "eagle-import:R0805")
      (libsource (lib "eagle-import") (part "R-EU_R0805"))
    )
    (comp (ref "R544")
      (value "470")
      (footprint "eagle-import:R6332")
      (libsource (lib "eagle-import") (part "R-EU_R6332"))
    )
    (comp (ref "R545")
      (value "0R")
      (footprint "eagle-import:M1206")
      (libsource (lib "eagle-import") (part "R-EU_M1206"))
    )
    (comp (ref "R546")
      (value "0R")
      (footprint "eagle-import:M1206")
      (libsource (lib "eagle-import") (part "R-EU_M1206"))
    )
    (comp (ref "R547")
      (value "470")
      (footprint "eagle-import:R6332")
      (libsource (lib "eagle-import") (part "R-EU_R6332"))
    )
    (comp (ref "R548")
      (value "221")
      (footprint "eagle-import:R0805")
      (libsource (lib "eagle-import") (part "R-EU_R0805"))
    )
    (comp (ref "R549")
      (value "222")
      (footprint "eagle-import:R0805")
      (libsource (lib "eagle-import") (part "R-EU_R0805"))
    )
    (comp (ref "R550")
      (value "470")
      (footprint "eagle-import:R6332")
      (libsource (lib "eagle-import") (part "R-EU_R6332"))
    )
    (comp (ref "R551")
      (value "0R")
      (footprint "eagle-import:M1206")
      (libsource (lib "eagle-import") (part "R-EU_M1206"))
    )
    (comp (ref "R552")
      (value "0R")
      (footprint "eagle-import:M1206")
      (libsource (lib "eagle-import") (part "R-EU_M1206"))
    )
    (comp (ref "R553")
      (value "470")
      (footprint "eagle-import:R6332")
      (libsource (lib "eagle-import") (part "R-EU_R6332"))
    )
    (comp (ref "R554")
      (value "221")
      (footprint "eagle-import:R0805")
      (libsource (lib "eagle-import") (part "R-EU_R0805"))
    )
    (comp (ref "R555")
      (value "222")
      (footprint "eagle-import:R0805")
      (libsource (lib "eagle-import") (part "R-EU_R0805"))
    )
    (comp (ref "R556")
      (value "470")
      (footprint "eagle-import:R6332")
      (libsource (lib "eagle-import") (part "R-EU_R6332"))
    )
    (comp (ref "R557")
      (value "0R")
      (footprint "eagle-import:M1206")
      (libsource (lib "eagle-import") (part "R-EU_M1206"))
    )
    (comp (ref "R558")
      (value "0R")
      (footprint "eagle-import:M1206")
      (libsource (lib "eagle-import") (part "R-EU_M1206"))
    )
    (comp (ref "R559")
      (value "470")
      (footprint "eagle-import:R6332")
      (libsource (lib "eagle-import") (part "R-EU_R6332"))
    )
    (comp (ref "R560")
      (value "221")
      (footprint "eagle-import:R0805")
      (libsource (lib "eagle-import") (part "R-EU_R0805"))
    )
    (comp (ref "R561")
      (value "222")
      (footprint "eagle-import:R0805")
      (libsource (lib "eagle-import") (part "R-EU_R0805"))
    )
    (comp (ref "R562")
      (value "470")
      (footprint "eagle-import:R6332")
      (libsource (lib "eagle-import") (part "R-EU_R6332"))
    )
    (comp (ref "R563")
      (value "0R")
      (footprint "eagle-import:M1206")
      (libsource (lib "eagle-import") (part "R-EU_M1206"))
    )
    (comp (ref "R564")
      (value "0R")
      (footprint "eagle-import:M1206")
      (libsource (lib "eagle-import") (part "R-EU_M1206"))
    )
    (comp (ref "R565")
      (value "470")
      (footprint "eagle-import:R6332")
      (libsource (lib "eagle-import") (part "R-EU_R6332"))
    )
    (comp (ref "R566")
      (value "221")
      (footprint "eagle-import:R0805")
      (libsource (lib "eagle-import") (part "R-EU_R0805"))
    )
    (comp (ref "R567")
      (value "222")
      (footprint "eagle-import:R0805")
      (libsource (lib "eagle-import") (part "R-EU_R0805"))
    )
    (comp (ref "R568")
      (value "470")
      (footprint "eagle-import:R6332")
      (libsource (lib "eagle-import") (part "R-EU_R6332"))
    )
    (comp (ref "R569")
      (value "0R")
      (footprint "eagle-import:M1206")
      (libsource (lib "eagle-import") (part "R-EU_M1206"))
    )
    (comp (ref "R570")
      (value "0R")
      (footprint "eagle-import:M1206")
      (libsource (lib "eagle-import") (part "R-EU_M1206"))
    )
    (comp (ref "R571")
      (value "0R")
      (footprint "eagle-import:M1206")
      (libsource (lib "eagle-import") (part "R-EU_M1206"))
    )
    (comp (ref "R572")
      (value "0R")
      (footprint "eagle-import:M1206")
      (libsource (lib "eagle-import") (part "R-EU_M1206"))
    )
    (comp (ref "R573")
      (value "0R")
      (footprint "eagle-import:M1206")
      (libsource (lib "eagle-import") (part "R-EU_M1206"))
    )
    (comp (ref "R574")
      (value "0R")
      (footprint "eagle-import:M1206")
      (libsource (lib "eagle-import") (part "R-EU_M1206"))
    )
    (comp (ref "R575")
      (value "0R")
      (footprint "eagle-import:M1206")
      (libsource (lib "eagle-import") (part "R-EU_M1206"))
    )
    (comp (ref "R576")
      (value "221")
      (footprint "eagle-import:R0805")
      (libsource (lib "eagle-import") (part "R-EU_R0805"))
    )
    (comp (ref "R577")
      (value "221")
      (footprint "eagle-import:R0805")
      (libsource (lib "eagle-import") (part "R-EU_R0805"))
    )
    (comp (ref "R578")
      (value "221")
      (footprint "eagle-import:R0805")
      (libsource (lib "eagle-import") (part "R-EU_R0805"))
    )
    (comp (ref "R579")
      (value "221")
      (footprint "eagle-import:R0805")
      (libsource (lib "eagle-import") (part "R-EU_R0805"))
    )
    (comp (ref "R580")
      (value "221")
      (footprint "eagle-import:R0805")
      (libsource (lib "eagle-import") (part "R-EU_R0805"))
    )
    (comp (ref "R581")
      (value "0R")
      (footprint "eagle-import:M1206")
      (libsource (lib "eagle-import") (part "R-EU_M1206"))
    )
    (comp (ref "S2")
      (value "SOCKET40P")
      (footprint "eagle-import:40PIN")
      (libsource (lib "eagle-import") (part "SOCKET40P"))
    )
    (comp (ref "U$91")
      (value "LTC6803-4")
      (footprint "eagle-import:SSOP44")
      (libsource (lib "eagle-import") (part "LTC6803-4"))
    )
    (comp (ref "U$92")
      (value "SI8841")
      (footprint "eagle-import:SO16")
      (libsource (lib "eagle-import") (part "SI8841"))
    )
    (comp (ref "U$93")
      (value "SI2351DS")
      (footprint "eagle-import:SOT23")
      (libsource (lib "eagle-import") (part "SI2351DS"))
    )
    (comp (ref "U$94")
      (value "SI2351DS")
      (footprint "eagle-import:SOT23")
      (libsource (lib "eagle-import") (part "SI2351DS"))
    )
    (comp (ref "U$95")
      (value "SI2351DS")
      (footprint "eagle-import:SOT23")
      (libsource (lib "eagle-import") (part "SI2351DS"))
    )
    (comp (ref "U$96")
      (value "SI2351DS")
      (footprint "eagle-import:SOT23")
      (libsource (lib "eagle-import") (part "SI2351DS"))
    )
    (comp (ref "U$97")
      (value "SI2351DS")
      (footprint "eagle-import:SOT23")
      (libsource (lib "eagle-import") (part "SI2351DS"))
    )
    (comp (ref "U$98")
      (value "SI2351DS")
      (footprint "eagle-import:SOT23")
      (libsource (lib "eagle-import") (part "SI2351DS"))
    )
    (comp (ref "U$99")
      (value "SI2351DS")
      (footprint "eagle-import:SOT23")
      (libsource (lib "eagle-import") (part "SI2351DS"))
    )
    (comp (ref "U$100")
      (value "SI2351DS")
      (footprint "eagle-import:SOT23")
      (libsource (lib "eagle-import") (part "SI2351DS"))
    )
    (comp (ref "U$101")
      (value "SI2351DS")
      (footprint "eagle-import:SOT23")
      (libsource (lib "eagle-import") (part "SI2351DS"))
    )
    (comp (ref "U$102")
      (value "SI2351DS")
      (footprint "eagle-import:SOT23")
      (libsource (lib "eagle-import") (part "SI2351DS"))
    )
    (comp (ref "U$103")
      (value "SI2351DS")
      (footprint "eagle-import:SOT23")
      (libsource (lib "eagle-import") (part "SI2351DS"))
    )
    (comp (ref "U$104")
      (value "SI2351DS")
      (footprint "eagle-import:SOT23")
      (libsource (lib "eagle-import") (part "SI2351DS"))
    )
    (comp (ref "U$105")
      (value "INDUCTOR")
      (footprint "eagle-import:L2012C")
      (libsource (lib "eagle-import") (part "INDUCTOR"))
    )
    (comp (ref "C36")
      (value "100nF")
      (footprint "eagle-import:C0805K")
      (libsource (lib "eagle-import") (part "C-EUC0805K"))
    )
    (comp (ref "C42")
      (value "100nF")
      (footprint "eagle-import:C0805K")
      (libsource (lib "eagle-import") (part "C-EUC0805K"))
    )
    (comp (ref "C54")
      (value "100nF")
      (footprint "eagle-import:C0805K")
      (libsource (lib "eagle-import") (part "C-EUC0805K"))
    )
    (comp (ref "C60")
      (value "100nF")
      (footprint "eagle-import:C0805K")
      (libsource (lib "eagle-import") (part "C-EUC0805K"))
    )
    (comp (ref "C63")
      (value "100nF")
      (footprint "eagle-import:C0805K")
      (libsource (lib "eagle-import") (part "C-EUC0805K"))
    )
    (comp (ref "C64")
      (value "100nF")
      (footprint "eagle-import:C0805K")
      (libsource (lib "eagle-import") (part "C-EUC0805K"))
    )
    (comp (ref "C65")
      (value "100nF")
      (footprint "eagle-import:C0805K")
      (libsource (lib "eagle-import") (part "C-EUC0805K"))
    )
    (comp (ref "C66")
      (value "100nF")
      (footprint "eagle-import:C0805K")
      (libsource (lib "eagle-import") (part "C-EUC0805K"))
    )
    (comp (ref "C69")
      (value "100nF")
      (footprint "eagle-import:C0805K")
      (libsource (lib "eagle-import") (part "C-EUC0805K"))
    )
    (comp (ref "C71")
      (value "100nF")
      (footprint "eagle-import:C0805K")
      (libsource (lib "eagle-import") (part "C-EUC0805K"))
    )
    (comp (ref "C72")
      (value "100nF")
      (footprint "eagle-import:C0805K")
      (libsource (lib "eagle-import") (part "C-EUC0805K"))
    )
    (comp (ref "C73")
      (value "100nF")
      (footprint "eagle-import:C0805K")
      (libsource (lib "eagle-import") (part "C-EUC0805K"))
    )
    (comp (ref "C74")
      (value "100nF")
      (footprint "eagle-import:C0805K")
      (libsource (lib "eagle-import") (part "C-EUC0805K"))
    )
    (comp (ref "C75")
      (value "100nF")
      (footprint "eagle-import:C0805K")
      (libsource (lib "eagle-import") (part "C-EUC0805K"))
    )
    (comp (ref "C76")
      (value "100nF")
      (footprint "eagle-import:C0805K")
      (libsource (lib "eagle-import") (part "C-EUC0805K"))
    )
    (comp (ref "C77")
      (value "100nF")
      (footprint "eagle-import:C0805K")
      (libsource (lib "eagle-import") (part "C-EUC0805K"))
    )
    (comp (ref "C78")
      (value "100nF")
      (footprint "eagle-import:C0805K")
      (libsource (lib "eagle-import") (part "C-EUC0805K"))
    )
    (comp (ref "D15")
      (value "7Z5")
      (footprint "eagle-import:SMB")
      (libsource (lib "eagle-import") (part "DIODE-SMB"))
    )
    (comp (ref "D30")
      (value "7Z5")
      (footprint "eagle-import:SMB")
      (libsource (lib "eagle-import") (part "DIODE-SMB"))
    )
    (comp (ref "D31")
      (value "7Z5")
      (footprint "eagle-import:SMB")
      (libsource (lib "eagle-import") (part "DIODE-SMB"))
    )
    (comp (ref "D35")
      (value "7Z5")
      (footprint "eagle-import:SMB")
      (libsource (lib "eagle-import") (part "DIODE-SMB"))
    )
    (comp (ref "D37")
      (value "7Z5")
      (footprint "eagle-import:SMB")
      (libsource (lib "eagle-import") (part "DIODE-SMB"))
    )
    (comp (ref "D38")
      (value "7Z5")
      (footprint "eagle-import:SMB")
      (libsource (lib "eagle-import") (part "DIODE-SMB"))
    )
    (comp (ref "D39")
      (value "7Z5")
      (footprint "eagle-import:SMB")
      (libsource (lib "eagle-import") (part "DIODE-SMB"))
    )
    (comp (ref "D40")
      (value "7Z5")
      (footprint "eagle-import:SMB")
      (libsource (lib "eagle-import") (part "DIODE-SMB"))
    )
    (comp (ref "D41")
      (value "7Z5")
      (footprint "eagle-import:SMB")
      (libsource (lib "eagle-import") (part "DIODE-SMB"))
    )
    (comp (ref "D42")
      (value "7Z5")
      (footprint "eagle-import:SMB")
      (libsource (lib "eagle-import") (part "DIODE-SMB"))
    )
    (comp (ref "D43")
      (value "7Z5")
      (footprint "eagle-import:SMB")
      (libsource (lib "eagle-import") (part "DIODE-SMB"))
    )
    (comp (ref "D44")
      (value "7Z5")
      (footprint "eagle-import:SMB")
      (libsource (lib "eagle-import") (part "DIODE-SMB"))
    )
    (comp (ref "D45")
      (value "7Z5")
      (footprint "eagle-import:SMB")
      (libsource (lib "eagle-import") (part "DIODE-SMB"))
    )
    (comp (ref "D46")
      (value "7Z5")
      (footprint "eagle-import:SMB")
      (libsource (lib "eagle-import") (part "DIODE-SMB"))
    )
    (comp (ref "D47")
      (value "DIODE-SOD123")
      (footprint "eagle-import:SOD123")
      (libsource (lib "eagle-import") (part "DIODE-SOD123"))
    )
    (comp (ref "R181")
      (value "470")
      (footprint "eagle-import:R6332")
      (libsource (lib "eagle-import") (part "R-EU_R6332"))
    )
    (comp (ref "R183")
      (value "221")
      (footprint "eagle-import:R0805")
      (libsource (lib "eagle-import") (part "R-EU_R0805"))
    )
    (comp (ref "R184")
      (value "222")
      (footprint "eagle-import:R0805")
      (libsource (lib "eagle-import") (part "R-EU_R0805"))
    )
    (comp (ref "R185")
      (value "470")
      (footprint "eagle-import:R6332")
      (libsource (lib "eagle-import") (part "R-EU_R6332"))
    )
    (comp (ref "R186")
      (value "0R")
      (footprint "eagle-import:M1206")
      (libsource (lib "eagle-import") (part "R-EU_M1206"))
    )
    (comp (ref "R187")
      (value "0R")
      (footprint "eagle-import:M1206")
      (libsource (lib "eagle-import") (part "R-EU_M1206"))
    )
    (comp (ref "R188")
      (value "470")
      (footprint "eagle-import:R6332")
      (libsource (lib "eagle-import") (part "R-EU_R6332"))
    )
    (comp (ref "R189")
      (value "221")
      (footprint "eagle-import:R0805")
      (libsource (lib "eagle-import") (part "R-EU_R0805"))
    )
    (comp (ref "R190")
      (value "222")
      (footprint "eagle-import:R0805")
      (libsource (lib "eagle-import") (part "R-EU_R0805"))
    )
    (comp (ref "R191")
      (value "470")
      (footprint "eagle-import:R6332")
      (libsource (lib "eagle-import") (part "R-EU_R6332"))
    )
    (comp (ref "R192")
      (value "0R")
      (footprint "eagle-import:M1206")
      (libsource (lib "eagle-import") (part "R-EU_M1206"))
    )
    (comp (ref "R193")
      (value "0R")
      (footprint "eagle-import:M1206")
      (libsource (lib "eagle-import") (part "R-EU_M1206"))
    )
    (comp (ref "R194")
      (value "470")
      (footprint "eagle-import:R6332")
      (libsource (lib "eagle-import") (part "R-EU_R6332"))
    )
    (comp (ref "R195")
      (value "221")
      (footprint "eagle-import:R0805")
      (libsource (lib "eagle-import") (part "R-EU_R0805"))
    )
    (comp (ref "R196")
      (value "222")
      (footprint "eagle-import:R0805")
      (libsource (lib "eagle-import") (part "R-EU_R0805"))
    )
    (comp (ref "R197")
      (value "470")
      (footprint "eagle-import:R6332")
      (libsource (lib "eagle-import") (part "R-EU_R6332"))
    )
    (comp (ref "R198")
      (value "0R")
      (footprint "eagle-import:M1206")
      (libsource (lib "eagle-import") (part "R-EU_M1206"))
    )
    (comp (ref "R199")
      (value "0R")
      (footprint "eagle-import:M1206")
      (libsource (lib "eagle-import") (part "R-EU_M1206"))
    )
    (comp (ref "R200")
      (value "470")
      (footprint "eagle-import:R6332")
      (libsource (lib "eagle-import") (part "R-EU_R6332"))
    )
    (comp (ref "R201")
      (value "221")
      (footprint "eagle-import:R0805")
      (libsource (lib "eagle-import") (part "R-EU_R0805"))
    )
    (comp (ref "R202")
      (value "222")
      (footprint "eagle-import:R0805")
      (libsource (lib "eagle-import") (part "R-EU_R0805"))
    )
    (comp (ref "R203")
      (value "470")
      (footprint "eagle-import:R6332")
      (libsource (lib "eagle-import") (part "R-EU_R6332"))
    )
    (comp (ref "R204")
      (value "0R")
      (footprint "eagle-import:M1206")
      (libsource (lib "eagle-import") (part "R-EU_M1206"))
    )
    (comp (ref "R205")
      (value "0R")
      (footprint "eagle-import:M1206")
      (libsource (lib "eagle-import") (part "R-EU_M1206"))
    )
    (comp (ref "R206")
      (value "470")
      (footprint "eagle-import:R6332")
      (libsource (lib "eagle-import") (part "R-EU_R6332"))
    )
    (comp (ref "R207")
      (value "221")
      (footprint "eagle-import:R0805")
      (libsource (lib "eagle-import") (part "R-EU_R0805"))
    )
    (comp (ref "R208")
      (value "222")
      (footprint "eagle-import:R0805")
      (libsource (lib "eagle-import") (part "R-EU_R0805"))
    )
    (comp (ref "R209")
      (value "470")
      (footprint "eagle-import:R6332")
      (libsource (lib "eagle-import") (part "R-EU_R6332"))
    )
    (comp (ref "R210")
      (value "0R")
      (footprint "eagle-import:M1206")
      (libsource (lib "eagle-import") (part "R-EU_M1206"))
    )
    (comp (ref "R211")
      (value "0R")
      (footprint "eagle-import:M1206")
      (libsource (lib "eagle-import") (part "R-EU_M1206"))
    )
    (comp (ref "R212")
      (value "470")
      (footprint "eagle-import:R6332")
      (libsource (lib "eagle-import") (part "R-EU_R6332"))
    )
    (comp (ref "R213")
      (value "221")
      (footprint "eagle-import:R0805")
      (libsource (lib "eagle-import") (part "R-EU_R0805"))
    )
    (comp (ref "R214")
      (value "222")
      (footprint "eagle-import:R0805")
      (libsource (lib "eagle-import") (part "R-EU_R0805"))
    )
    (comp (ref "R215")
      (value "470")
      (footprint "eagle-import:R6332")
      (libsource (lib "eagle-import") (part "R-EU_R6332"))
    )
    (comp (ref "R216")
      (value "0R")
      (footprint "eagle-import:M1206")
      (libsource (lib "eagle-import") (part "R-EU_M1206"))
    )
    (comp (ref "R217")
      (value "0R")
      (footprint "eagle-import:M1206")
      (libsource (lib "eagle-import") (part "R-EU_M1206"))
    )
    (comp (ref "R218")
      (value "470")
      (footprint "eagle-import:R6332")
      (libsource (lib "eagle-import") (part "R-EU_R6332"))
    )
    (comp (ref "R219")
      (value "221")
      (footprint "eagle-import:R0805")
      (libsource (lib "eagle-import") (part "R-EU_R0805"))
    )
    (comp (ref "R220")
      (value "222")
      (footprint "eagle-import:R0805")
      (libsource (lib "eagle-import") (part "R-EU_R0805"))
    )
    (comp (ref "R221")
      (value "470")
      (footprint "eagle-import:R6332")
      (libsource (lib "eagle-import") (part "R-EU_R6332"))
    )
    (comp (ref "R222")
      (value "0R")
      (footprint "eagle-import:M1206")
      (libsource (lib "eagle-import") (part "R-EU_M1206"))
    )
    (comp (ref "R223")
      (value "0R")
      (footprint "eagle-import:M1206")
      (libsource (lib "eagle-import") (part "R-EU_M1206"))
    )
    (comp (ref "R224")
      (value "470")
      (footprint "eagle-import:R6332")
      (libsource (lib "eagle-import") (part "R-EU_R6332"))
    )
    (comp (ref "R225")
      (value "221")
      (footprint "eagle-import:R0805")
      (libsource (lib "eagle-import") (part "R-EU_R0805"))
    )
    (comp (ref "R226")
      (value "222")
      (footprint "eagle-import:R0805")
      (libsource (lib "eagle-import") (part "R-EU_R0805"))
    )
    (comp (ref "R227")
      (value "470")
      (footprint "eagle-import:R6332")
      (libsource (lib "eagle-import") (part "R-EU_R6332"))
    )
    (comp (ref "R228")
      (value "0R")
      (footprint "eagle-import:M1206")
      (libsource (lib "eagle-import") (part "R-EU_M1206"))
    )
    (comp (ref "R229")
      (value "0R")
      (footprint "eagle-import:M1206")
      (libsource (lib "eagle-import") (part "R-EU_M1206"))
    )
    (comp (ref "R230")
      (value "470")
      (footprint "eagle-import:R6332")
      (libsource (lib "eagle-import") (part "R-EU_R6332"))
    )
    (comp (ref "R231")
      (value "221")
      (footprint "eagle-import:R0805")
      (libsource (lib "eagle-import") (part "R-EU_R0805"))
    )
    (comp (ref "R232")
      (value "222")
      (footprint "eagle-import:R0805")
      (libsource (lib "eagle-import") (part "R-EU_R0805"))
    )
    (comp (ref "R233")
      (value "470")
      (footprint "eagle-import:R6332")
      (libsource (lib "eagle-import") (part "R-EU_R6332"))
    )
    (comp (ref "R234")
      (value "0R")
      (footprint "eagle-import:M1206")
      (libsource (lib "eagle-import") (part "R-EU_M1206"))
    )
    (comp (ref "R235")
      (value "0R")
      (footprint "eagle-import:M1206")
      (libsource (lib "eagle-import") (part "R-EU_M1206"))
    )
    (comp (ref "R236")
      (value "470")
      (footprint "eagle-import:R6332")
      (libsource (lib "eagle-import") (part "R-EU_R6332"))
    )
    (comp (ref "R237")
      (value "221")
      (footprint "eagle-import:R0805")
      (libsource (lib "eagle-import") (part "R-EU_R0805"))
    )
    (comp (ref "R238")
      (value "222")
      (footprint "eagle-import:R0805")
      (libsource (lib "eagle-import") (part "R-EU_R0805"))
    )
    (comp (ref "R239")
      (value "470")
      (footprint "eagle-import:R6332")
      (libsource (lib "eagle-import") (part "R-EU_R6332"))
    )
    (comp (ref "R240")
      (value "0R")
      (footprint "eagle-import:M1206")
      (libsource (lib "eagle-import") (part "R-EU_M1206"))
    )
    (comp (ref "R241")
      (value "0R")
      (footprint "eagle-import:M1206")
      (libsource (lib "eagle-import") (part "R-EU_M1206"))
    )
    (comp (ref "R242")
      (value "470")
      (footprint "eagle-import:R6332")
      (libsource (lib "eagle-import") (part "R-EU_R6332"))
    )
    (comp (ref "R243")
      (value "221")
      (footprint "eagle-import:R0805")
      (libsource (lib "eagle-import") (part "R-EU_R0805"))
    )
    (comp (ref "R244")
      (value "222")
      (footprint "eagle-import:R0805")
      (libsource (lib "eagle-import") (part "R-EU_R0805"))
    )
    (comp (ref "R245")
      (value "470")
      (footprint "eagle-import:R6332")
      (libsource (lib "eagle-import") (part "R-EU_R6332"))
    )
    (comp (ref "R246")
      (value "0R")
      (footprint "eagle-import:M1206")
      (libsource (lib "eagle-import") (part "R-EU_M1206"))
    )
    (comp (ref "R247")
      (value "0R")
      (footprint "eagle-import:M1206")
      (libsource (lib "eagle-import") (part "R-EU_M1206"))
    )
    (comp (ref "R248")
      (value "470")
      (footprint "eagle-import:R6332")
      (libsource (lib "eagle-import") (part "R-EU_R6332"))
    )
    (comp (ref "R249")
      (value "221")
      (footprint "eagle-import:R0805")
      (libsource (lib "eagle-import") (part "R-EU_R0805"))
    )
    (comp (ref "R250")
      (value "222")
      (footprint "eagle-import:R0805")
      (libsource (lib "eagle-import") (part "R-EU_R0805"))
    )
    (comp (ref "R251")
      (value "470")
      (footprint "eagle-import:R6332")
      (libsource (lib "eagle-import") (part "R-EU_R6332"))
    )
    (comp (ref "R252")
      (value "0R")
      (footprint "eagle-import:M1206")
      (libsource (lib "eagle-import") (part "R-EU_M1206"))
    )
    (comp (ref "R253")
      (value "0R")
      (footprint "eagle-import:M1206")
      (libsource (lib "eagle-import") (part "R-EU_M1206"))
    )
    (comp (ref "R254")
      (value "0R")
      (footprint "eagle-import:M1206")
      (libsource (lib "eagle-import") (part "R-EU_M1206"))
    )
    (comp (ref "R255")
      (value "0R")
      (footprint "eagle-import:M1206")
      (libsource (lib "eagle-import") (part "R-EU_M1206"))
    )
    (comp (ref "R256")
      (value "0R")
      (footprint "eagle-import:M1206")
      (libsource (lib "eagle-import") (part "R-EU_M1206"))
    )
    (comp (ref "R258")
      (value "0R")
      (footprint "eagle-import:M1206")
      (libsource (lib "eagle-import") (part "R-EU_M1206"))
    )
    (comp (ref "R259")
      (value "0R")
      (footprint "eagle-import:M1206")
      (libsource (lib "eagle-import") (part "R-EU_M1206"))
    )
    (comp (ref "R260")
      (value "221")
      (footprint "eagle-import:R0805")
      (libsource (lib "eagle-import") (part "R-EU_R0805"))
    )
    (comp (ref "R261")
      (value "221")
      (footprint "eagle-import:R0805")
      (libsource (lib "eagle-import") (part "R-EU_R0805"))
    )
    (comp (ref "R262")
      (value "221")
      (footprint "eagle-import:R0805")
      (libsource (lib "eagle-import") (part "R-EU_R0805"))
    )
    (comp (ref "R263")
      (value "221")
      (footprint "eagle-import:R0805")
      (libsource (lib "eagle-import") (part "R-EU_R0805"))
    )
    (comp (ref "R264")
      (value "221")
      (footprint "eagle-import:R0805")
      (libsource (lib "eagle-import") (part "R-EU_R0805"))
    )
    (comp (ref "R265")
      (value "0R")
      (footprint "eagle-import:M1206")
      (libsource (lib "eagle-import") (part "R-EU_M1206"))
    )
    (comp (ref "U$34")
      (value "LTC6803-4")
      (footprint "eagle-import:SSOP44")
      (libsource (lib "eagle-import") (part "LTC6803-4"))
    )
    (comp (ref "U$35")
      (value "SI8841")
      (footprint "eagle-import:SO16")
      (libsource (lib "eagle-import") (part "SI8841"))
    )
    (comp (ref "U$36")
      (value "SI2351DS")
      (footprint "eagle-import:SOT23")
      (libsource (lib "eagle-import") (part "SI2351DS"))
    )
    (comp (ref "U$37")
      (value "SI2351DS")
      (footprint "eagle-import:SOT23")
      (libsource (lib "eagle-import") (part "SI2351DS"))
    )
    (comp (ref "U$38")
      (value "SI2351DS")
      (footprint "eagle-import:SOT23")
      (libsource (lib "eagle-import") (part "SI2351DS"))
    )
    (comp (ref "U$39")
      (value "SI2351DS")
      (footprint "eagle-import:SOT23")
      (libsource (lib "eagle-import") (part "SI2351DS"))
    )
    (comp (ref "U$40")
      (value "SI2351DS")
      (footprint "eagle-import:SOT23")
      (libsource (lib "eagle-import") (part "SI2351DS"))
    )
    (comp (ref "U$41")
      (value "SI2351DS")
      (footprint "eagle-import:SOT23")
      (libsource (lib "eagle-import") (part "SI2351DS"))
    )
    (comp (ref "U$42")
      (value "SI2351DS")
      (footprint "eagle-import:SOT23")
      (libsource (lib "eagle-import") (part "SI2351DS"))
    )
    (comp (ref "U$45")
      (value "SI2351DS")
      (footprint "eagle-import:SOT23")
      (libsource (lib "eagle-import") (part "SI2351DS"))
    )
    (comp (ref "U$46")
      (value "SI2351DS")
      (footprint "eagle-import:SOT23")
      (libsource (lib "eagle-import") (part "SI2351DS"))
    )
    (comp (ref "U$47")
      (value "SI2351DS")
      (footprint "eagle-import:SOT23")
      (libsource (lib "eagle-import") (part "SI2351DS"))
    )
    (comp (ref "U$48")
      (value "SI2351DS")
      (footprint "eagle-import:SOT23")
      (libsource (lib "eagle-import") (part "SI2351DS"))
    )
    (comp (ref "U$49")
      (value "SI2351DS")
      (footprint "eagle-import:SOT23")
      (libsource (lib "eagle-import") (part "SI2351DS"))
    )
    (comp (ref "U$50")
      (value "INDUCTOR")
      (footprint "eagle-import:L2012C")
      (libsource (lib "eagle-import") (part "INDUCTOR"))
    )
  )
  (nets
    (net (code "1") (name "14-1") (class "Default")
      (node (ref "S") (pin "14") (pinfunction "14_14") (pintype "passive"))
      (node (ref "U$30") (pin "2") (pinfunction "2_2") (pintype "passive"))
    )
    (net (code "2") (name "14-2") (class "Default")
      (node (ref "S1") (pin "14") (pinfunction "14_14") (pintype "passive"))
      (node (ref "U$75") (pin "2") (pinfunction "2_2") (pintype "passive"))
    )
    (net (code "3") (name "14-3") (class "Default")
      (node (ref "S2") (pin "14") (pinfunction "14_14") (pintype "passive"))
      (node (ref "U$120") (pin "2") (pinfunction "2_2") (pintype "passive"))
    )
    (net (code "4") (name "15-1") (class "Default")
      (node (ref "R98") (pin "1") (pinfunction "1_1") (pintype "passive"))
      (node (ref "S") (pin "15") (pinfunction "15_15") (pintype "passive"))
    )
    (net (code "5") (name "15-2") (class "Default")
      (node (ref "R343") (pin "1") (pinfunction "1_1") (pintype "passive"))
      (node (ref "S1") (pin "15") (pinfunction "15_15") (pintype "passive"))
    )
    (net (code "6") (name "15-3") (class "Default")
      (node (ref "R592") (pin "1") (pinfunction "1_1") (pintype "passive"))
      (node (ref "S2") (pin "15") (pinfunction "15_15") (pintype "passive"))
    )
    (net (code "7") (name "16-1") (class "Default")
      (node (ref "R92") (pin "1") (pinfunction "1_1") (pintype "passive"))
      (node (ref "S") (pin "16") (pinfunction "16_16") (pintype "passive"))
    )
    (net (code "8") (name "16-2") (class "Default")
      (node (ref "R337") (pin "1") (pinfunction "1_1") (pintype "passive"))
      (node (ref "S1") (pin "16") (pinfunction "16_16") (pintype "passive"))
    )
    (net (code "9") (name "16-3") (class "Default")
      (node (ref "R586") (pin "1") (pinfunction "1_1") (pintype "passive"))
      (node (ref "S2") (pin "16") (pinfunction "16_16") (pintype "passive"))
    )
    (net (code "10") (name "17-1") (class "Default")
      (node (ref "R104") (pin "1") (pinfunction "1_1") (pintype "passive"))
      (node (ref "S") (pin "17") (pinfunction "17_17") (pintype "passive"))
    )
    (net (code "11") (name "17-2") (class "Default")
      (node (ref "R349") (pin "1") (pinfunction "1_1") (pintype "passive"))
      (node (ref "S1") (pin "17") (pinfunction "17_17") (pintype "passive"))
    )
    (net (code "12") (name "17-3") (class "Default")
      (node (ref "R598") (pin "1") (pinfunction "1_1") (pintype "passive"))
      (node (ref "S2") (pin "17") (pinfunction "17_17") (pintype "passive"))
    )
    (net (code "13") (name "18-1") (class "Default")
      (node (ref "R110") (pin "1") (pinfunction "1_1") (pintype "passive"))
      (node (ref "S") (pin "18") (pinfunction "18_18") (pintype "passive"))
    )
    (net (code "14") (name "18-2") (class "Default")
      (node (ref "R355") (pin "1") (pinfunction "1_1") (pintype "passive"))
      (node (ref "S1") (pin "18") (pinfunction "18_18") (pintype "passive"))
    )
    (net (code "15") (name "18-3") (class "Default")
      (node (ref "R604") (pin "1") (pinfunction "1_1") (pintype "passive"))
      (node (ref "S2") (pin "18") (pinfunction "18_18") (pintype "passive"))
    )
    (net (code "16") (name "19-1") (class "Default")
      (node (ref "R116") (pin "1") (pinfunction "1_1") (pintype "passive"))
      (node (ref "S") (pin "19") (pinfunction "19_19") (pintype "passive"))
    )
    (net (code "17") (name "19-2") (class "Default")
      (node (ref "R361") (pin "1") (pinfunction "1_1") (pintype "passive"))
      (node (ref "S1") (pin "19") (pinfunction "19_19") (pintype "passive"))
    )
    (net (code "18") (name "19-3") (class "Default")
      (node (ref "R610") (pin "1") (pinfunction "1_1") (pintype "passive"))
      (node (ref "S2") (pin "19") (pinfunction "19_19") (pintype "passive"))
    )
    (net (code "19") (name "20-1") (class "Default")
      (node (ref "R122") (pin "1") (pinfunction "1_1") (pintype "passive"))
      (node (ref "S") (pin "20") (pinfunction "20_20") (pintype "passive"))
    )
    (net (code "20") (name "20-2") (class "Default")
      (node (ref "R367") (pin "1") (pinfunction "1_1") (pintype "passive"))
      (node (ref "S1") (pin "20") (pinfunction "20_20") (pintype "passive"))
    )
    (net (code "21") (name "20-3") (class "Default")
      (node (ref "R616") (pin "1") (pinfunction "1_1") (pintype "passive"))
      (node (ref "S2") (pin "20") (pinfunction "20_20") (pintype "passive"))
    )
    (net (code "22") (name "21-1") (class "Default")
      (node (ref "R134") (pin "1") (pinfunction "1_1") (pintype "passive"))
      (node (ref "S") (pin "21") (pinfunction "21_21") (pintype "passive"))
    )
    (net (code "23") (name "21-2") (class "Default")
      (node (ref "R379") (pin "1") (pinfunction "1_1") (pintype "passive"))
      (node (ref "S1") (pin "21") (pinfunction "21_21") (pintype "passive"))
    )
    (net (code "24") (name "21-3") (class "Default")
      (node (ref "R628") (pin "1") (pinfunction "1_1") (pintype "passive"))
      (node (ref "S2") (pin "21") (pinfunction "21_21") (pintype "passive"))
    )
    (net (code "25") (name "22-1") (class "Default")
      (node (ref "R128") (pin "1") (pinfunction "1_1") (pintype "passive"))
      (node (ref "S") (pin "22") (pinfunction "22_22") (pintype "passive"))
    )
    (net (code "26") (name "22-2") (class "Default")
      (node (ref "R373") (pin "1") (pinfunction "1_1") (pintype "passive"))
      (node (ref "S1") (pin "22") (pinfunction "22_22") (pintype "passive"))
    )
    (net (code "27") (name "22-3") (class "Default")
      (node (ref "R622") (pin "1") (pinfunction "1_1") (pintype "passive"))
      (node (ref "S2") (pin "22") (pinfunction "22_22") (pintype "passive"))
    )
    (net (code "28") (name "23-1") (class "Default")
      (node (ref "R140") (pin "1") (pinfunction "1_1") (pintype "passive"))
      (node (ref "S") (pin "23") (pinfunction "23_23") (pintype "passive"))
    )
    (net (code "29") (name "23-2") (class "Default")
      (node (ref "R385") (pin "1") (pinfunction "1_1") (pintype "passive"))
      (node (ref "S1") (pin "23") (pinfunction "23_23") (pintype "passive"))
    )
    (net (code "30") (name "23-3") (class "Default")
      (node (ref "R634") (pin "1") (pinfunction "1_1") (pintype "passive"))
      (node (ref "S2") (pin "23") (pinfunction "23_23") (pintype "passive"))
    )
    (net (code "31") (name "24-1") (class "Default")
      (node (ref "R146") (pin "1") (pinfunction "1_1") (pintype "passive"))
      (node (ref "S") (pin "24") (pinfunction "24_24") (pintype "passive"))
    )
    (net (code "32") (name "24-2") (class "Default")
      (node (ref "R391") (pin "1") (pinfunction "1_1") (pintype "passive"))
      (node (ref "S1") (pin "24") (pinfunction "24_24") (pintype "passive"))
    )
    (net (code "33") (name "24-3") (class "Default")
      (node (ref "R640") (pin "1") (pinfunction "1_1") (pintype "passive"))
      (node (ref "S2") (pin "24") (pinfunction "24_24") (pintype "passive"))
    )
    (net (code "34") (name "25-1") (class "Default")
      (node (ref "R152") (pin "1") (pinfunction "1_1") (pintype "passive"))
      (node (ref "S") (pin "25") (pinfunction "25_25") (pintype "passive"))
    )
    (net (code "35") (name "25-2") (class "Default")
      (node (ref "R397") (pin "1") (pinfunction "1_1") (pintype "passive"))
      (node (ref "S1") (pin "25") (pinfunction "25_25") (pintype "passive"))
    )
    (net (code "36") (name "25-3") (class "Default")
      (node (ref "R646") (pin "1") (pinfunction "1_1") (pintype "passive"))
      (node (ref "S2") (pin "25") (pinfunction "25_25") (pintype "passive"))
    )
    (net (code "37") (name "26-1") (class "Default")
      (node (ref "R158") (pin "1") (pinfunction "1_1") (pintype "passive"))
      (node (ref "R165") (pin "1") (pinfunction "1_1") (pintype "passive"))
      (node (ref "S") (pin "26") (pinfunction "26_26") (pintype "passive"))
    )
    (net (code "38") (name "26-2") (class "Default")
      (node (ref "R403") (pin "1") (pinfunction "1_1") (pintype "passive"))
      (node (ref "R409") (pin "1") (pinfunction "1_1") (pintype "passive"))
      (node (ref "S1") (pin "26") (pinfunction "26_26") (pintype "passive"))
    )
    (net (code "39") (name "26-3") (class "Default")
      (node (ref "R652") (pin "1") (pinfunction "1_1") (pintype "passive"))
      (node (ref "R658") (pin "1") (pinfunction "1_1") (pintype "passive"))
      (node (ref "S2") (pin "26") (pinfunction "26_26") (pintype "passive"))
    )
    (net (code "40") (name "27-1") (class "Default")
      (node (ref "S") (pin "27") (pinfunction "27_27") (pintype "passive"))
    )
    (net (code "41") (name "27-2") (class "Default")
      (node (ref "S1") (pin "27") (pinfunction "27_27") (pintype "passive"))
    )
    (net (code "42") (name "27-3") (class "Default")
      (node (ref "S2") (pin "27") (pinfunction "27_27") (pintype "passive"))
    )
    (net (code "43") (name "28-1") (class "Default")
      (node (ref "S") (pin "28") (pinfunction "28_28") (pintype "passive"))
      (node (ref "U$50") (pin "2") (pinfunction "2_2") (pintype "passive"))
    )
    (net (code "44") (name "28-2") (class "Default")
      (node (ref "S1") (pin "28") (pinfunction "28_28") (pintype "passive"))
      (node (ref "U$90") (pin "2") (pinfunction "2_2") (pintype "passive"))
    )
    (net (code "45") (name "28-3") (class "Default")
      (node (ref "S2") (pin "28") (pinfunction "28_28") (pintype "passive"))
      (node (ref "U$135") (pin "2") (pinfunction "2_2") (pintype "passive"))
    )
    (net (code "46") (name "29-1") (class "Default")
      (node (ref "R192") (pin "1") (pinfunction "1_1") (pintype "passive"))
      (node (ref "S") (pin "29") (pinfunction "29_29") (pintype "passive"))
    )
    (net (code "47") (name "29-2") (class "Default")
      (node (ref "R426") (pin "1") (pinfunction "1_1") (pintype "passive"))
      (node (ref "S1") (pin "29") (pinfunction "29_29") (pintype "passive"))
    )
    (net (code "48") (name "29-3") (class "Default")
      (node (ref "R675") (pin "1") (pinfunction "1_1") (pintype "passive"))
      (node (ref "S2") (pin "29") (pinfunction "29_29") (pintype "passive"))
    )
    (net (code "49") (name "30-1") (class "Default")
      (node (ref "R186") (pin "1") (pinfunction "1_1") (pintype "passive"))
      (node (ref "S") (pin "30") (pinfunction "30_30") (pintype "passive"))
    )
    (net (code "50") (name "30-2") (class "Default")
      (node (ref "R420") (pin "1") (pinfunction "1_1") (pintype "passive"))
      (node (ref "S1") (pin "30") (pinfunction "30_30") (pintype "passive"))
    )
    (net (code "51") (name "30-3") (class "Default")
      (node (ref "R669") (pin "1") (pinfunction "1_1") (pintype "passive"))
      (node (ref "S2") (pin "30") (pinfunction "30_30") (pintype "passive"))
    )
    (net (code "52") (name "31-1") (class "Default")
      (node (ref "R198") (pin "1") (pinfunction "1_1") (pintype "passive"))
      (node (ref "S") (pin "31") (pinfunction "31_31") (pintype "passive"))
    )
    (net (code "53") (name "31-2") (class "Default")
      (node (ref "R432") (pin "1") (pinfunction "1_1") (pintype "passive"))
      (node (ref "S1") (pin "31") (pinfunction "31_31") (pintype "passive"))
    )
    (net (code "54") (name "31-3") (class "Default")
      (node (ref "R681") (pin "1") (pinfunction "1_1") (pintype "passive"))
      (node (ref "S2") (pin "31") (pinfunction "31_31") (pintype "passive"))
    )
    (net (code "55") (name "32-1") (class "Default")
      (node (ref "R204") (pin "1") (pinfunction "1_1") (pintype "passive"))
      (node (ref "S") (pin "32") (pinfunction "32_32") (pintype "passive"))
    )
    (net (code "56") (name "32-2") (class "Default")
      (node (ref "R438") (pin "1") (pinfunction "1_1") (pintype "passive"))
      (node (ref "S1") (pin "32") (pinfunction "32_32") (pintype "passive"))
    )
    (net (code "57") (name "32-3") (class "Default")
      (node (ref "R687") (pin "1") (pinfunction "1_1") (pintype "passive"))
      (node (ref "S2") (pin "32") (pinfunction "32_32") (pintype "passive"))
    )
    (net (code "58") (name "33-1") (class "Default")
      (node (ref "R210") (pin "1") (pinfunction "1_1") (pintype "passive"))
      (node (ref "S") (pin "33") (pinfunction "33_33") (pintype "passive"))
    )
    (net (code "59") (name "33-2") (class "Default")
      (node (ref "R444") (pin "1") (pinfunction "1_1") (pintype "passive"))
      (node (ref "S1") (pin "33") (pinfunction "33_33") (pintype "passive"))
    )
    (net (code "60") (name "33-3") (class "Default")
      (node (ref "R693") (pin "1") (pinfunction "1_1") (pintype "passive"))
      (node (ref "S2") (pin "33") (pinfunction "33_33") (pintype "passive"))
    )
    (net (code "61") (name "34-1") (class "Default")
      (node (ref "R216") (pin "1") (pinfunction "1_1") (pintype "passive"))
      (node (ref "S") (pin "34") (pinfunction "34_34") (pintype "passive"))
    )
    (net (code "62") (name "34-2") (class "Default")
      (node (ref "R450") (pin "1") (pinfunction "1_1") (pintype "passive"))
      (node (ref "S1") (pin "34") (pinfunction "34_34") (pintype "passive"))
    )
    (net (code "63") (name "34-3") (class "Default")
      (node (ref "R699") (pin "1") (pinfunction "1_1") (pintype "passive"))
      (node (ref "S2") (pin "34") (pinfunction "34_34") (pintype "passive"))
    )
    (net (code "64") (name "35-1") (class "Default")
      (node (ref "R228") (pin "1") (pinfunction "1_1") (pintype "passive"))
      (node (ref "S") (pin "35") (pinfunction "35_35") (pintype "passive"))
    )
    (net (code "65") (name "35-2") (class "Default")
      (node (ref "R462") (pin "1") (pinfunction "1_1") (pintype "passive"))
      (node (ref "S1") (pin "35") (pinfunction "35_35") (pintype "passive"))
    )
    (net (code "66") (name "35-3") (class "Default")
      (node (ref "R711") (pin "1") (pinfunction "1_1") (pintype "passive"))
      (node (ref "S2") (pin "35") (pinfunction "35_35") (pintype "passive"))
    )
    (net (code "67") (name "36-1") (class "Default")
      (node (ref "R222") (pin "1") (pinfunction "1_1") (pintype "passive"))
      (node (ref "S") (pin "36") (pinfunction "36_36") (pintype "passive"))
    )
    (net (code "68") (name "36-2") (class "Default")
      (node (ref "R456") (pin "1") (pinfunction "1_1") (pintype "passive"))
      (node (ref "S1") (pin "36") (pinfunction "36_36") (pintype "passive"))
    )
    (net (code "69") (name "36-3") (class "Default")
      (node (ref "R705") (pin "1") (pinfunction "1_1") (pintype "passive"))
      (node (ref "S2") (pin "36") (pinfunction "36_36") (pintype "passive"))
    )
    (net (code "70") (name "37-1") (class "Default")
      (node (ref "R234") (pin "1") (pinfunction "1_1") (pintype "passive"))
      (node (ref "S") (pin "37") (pinfunction "37_37") (pintype "passive"))
    )
    (net (code "71") (name "37-2") (class "Default")
      (node (ref "R468") (pin "1") (pinfunction "1_1") (pintype "passive"))
      (node (ref "S1") (pin "37") (pinfunction "37_37") (pintype "passive"))
    )
    (net (code "72") (name "37-3") (class "Default")
      (node (ref "R717") (pin "1") (pinfunction "1_1") (pintype "passive"))
      (node (ref "S2") (pin "37") (pinfunction "37_37") (pintype "passive"))
    )
    (net (code "73") (name "38-1") (class "Default")
      (node (ref "R240") (pin "1") (pinfunction "1_1") (pintype "passive"))
      (node (ref "S") (pin "38") (pinfunction "38_38") (pintype "passive"))
    )
    (net (code "74") (name "38-2") (class "Default")
      (node (ref "R474") (pin "1") (pinfunction "1_1") (pintype "passive"))
      (node (ref "S1") (pin "38") (pinfunction "38_38") (pintype "passive"))
    )
    (net (code "75") (name "38-3") (class "Default")
      (node (ref "R723") (pin "1") (pinfunction "1_1") (pintype "passive"))
      (node (ref "S2") (pin "38") (pinfunction "38_38") (pintype "passive"))
    )
    (net (code "76") (name "39-1") (class "Default")
      (node (ref "R246") (pin "1") (pinfunction "1_1") (pintype "passive"))
      (node (ref "S") (pin "39") (pinfunction "39_39") (pintype "passive"))
    )
    (net (code "77") (name "39-2") (class "Default")
      (node (ref "R480") (pin "1") (pinfunction "1_1") (pintype "passive"))
      (node (ref "S1") (pin "39") (pinfunction "39_39") (pintype "passive"))
    )
    (net (code "78") (name "39-3") (class "Default")
      (node (ref "R729") (pin "1") (pinfunction "1_1") (pintype "passive"))
      (node (ref "S2") (pin "39") (pinfunction "39_39") (pintype "passive"))
    )
    (net (code "79") (name "40-1") (class "Default")
      (node (ref "R252") (pin "1") (pinfunction "1_1") (pintype "passive"))
      (node (ref "R259") (pin "1") (pinfunction "1_1") (pintype "passive"))
      (node (ref "S") (pin "40") (pinfunction "40_40") (pintype "passive"))
    )
    (net (code "80") (name "40-2") (class "Default")
      (node (ref "R486") (pin "1") (pinfunction "1_1") (pintype "passive"))
      (node (ref "R492") (pin "1") (pinfunction "1_1") (pintype "passive"))
      (node (ref "S1") (pin "40") (pinfunction "40_40") (pintype "passive"))
    )
    (net (code "81") (name "40-3") (class "Default")
      (node (ref "R735") (pin "1") (pinfunction "1_1") (pintype "passive"))
      (node (ref "R741") (pin "1") (pinfunction "1_1") (pintype "passive"))
      (node (ref "S2") (pin "40") (pinfunction "40_40") (pintype "passive"))
    )
    (net (code "82") (name "C1") (class "Default")
      (node (ref "C2") (pin "2") (pinfunction "2_2") (pintype "passive"))
      (node (ref "R10") (pin "2") (pinfunction "2_2") (pintype "passive"))
      (node (ref "U$1") (pin "24") (pinfunction "C1_24") (pintype "bidirectional"))
    )
    (net (code "83") (name "C1-2") (class "Default")
      (node (ref "C20") (pin "2") (pinfunction "2_2") (pintype "passive"))
      (node (ref "R95") (pin "2") (pinfunction "2_2") (pintype "passive"))
      (node (ref "U$16") (pin "24") (pinfunction "C1_24") (pintype "bidirectional"))
    )
    (net (code "84") (name "C1-3") (class "Default")
      (node (ref "C42") (pin "2") (pinfunction "2_2") (pintype "passive"))
      (node (ref "R189") (pin "2") (pinfunction "2_2") (pintype "passive"))
      (node (ref "U$34") (pin "24") (pinfunction "C1_24") (pintype "bidirectional"))
    )
    (net (code "85") (name "C1-4") (class "Default")
      (node (ref "C37") (pin "2") (pinfunction "2_2") (pintype "passive"))
      (node (ref "R174") (pin "2") (pinfunction "2_2") (pintype "passive"))
      (node (ref "U$31") (pin "24") (pinfunction "C1_24") (pintype "bidirectional"))
    )
    (net (code "86") (name "C1-5") (class "Default")
      (node (ref "C56") (pin "2") (pinfunction "2_2") (pintype "passive"))
      (node (ref "R340") (pin "2") (pinfunction "2_2") (pintype "passive"))
      (node (ref "U$61") (pin "24") (pinfunction "C1_24") (pintype "bidirectional"))
    )
    (net (code "87") (name "C1-6") (class "Default")
      (node (ref "C87") (pin "2") (pinfunction "2_2") (pintype "passive"))
      (node (ref "R423") (pin "2") (pinfunction "2_2") (pintype "passive"))
      (node (ref "U$76") (pin "24") (pinfunction "C1_24") (pintype "bidirectional"))
    )
    (net (code "88") (name "C1-7") (class "Default")
      (node (ref "C104") (pin "2") (pinfunction "2_2") (pintype "passive"))
      (node (ref "R506") (pin "2") (pinfunction "2_2") (pintype "passive"))
      (node (ref "U$91") (pin "24") (pinfunction "C1_24") (pintype "bidirectional"))
    )
    (net (code "89") (name "C1-8") (class "Default")
      (node (ref "C121") (pin "2") (pinfunction "2_2") (pintype "passive"))
      (node (ref "R589") (pin "2") (pinfunction "2_2") (pintype "passive"))
      (node (ref "U$106") (pin "24") (pinfunction "C1_24") (pintype "bidirectional"))
    )
    (net (code "90") (name "C1-9") (class "Default")
      (node (ref "C138") (pin "2") (pinfunction "2_2") (pintype "passive"))
      (node (ref "R672") (pin "2") (pinfunction "2_2") (pintype "passive"))
      (node (ref "U$121") (pin "24") (pinfunction "C1_24") (pintype "bidirectional"))
    )
    (net (code "91") (name "C2") (class "Default")
      (node (ref "C1") (pin "2") (pinfunction "2_2") (pintype "passive"))
      (node (ref "R4") (pin "2") (pinfunction "2_2") (pintype "passive"))
      (node (ref "U$1") (pin "P$22") (pinfunction "C2_P$22") (pintype "bidirectional"))
    )
    (net (code "92") (name "C2-2") (class "Default")
      (node (ref "C19") (pin "2") (pinfunction "2_2") (pintype "passive"))
      (node (ref "R89") (pin "2") (pinfunction "2_2") (pintype "passive"))
      (node (ref "U$16") (pin "P$22") (pinfunction "C2_P$22") (pintype "bidirectional"))
    )
    (net (code "93") (name "C2-3") (class "Default")
      (node (ref "C36") (pin "2") (pinfunction "2_2") (pintype "passive"))
      (node (ref "R183") (pin "2") (pinfunction "2_2") (pintype "passive"))
      (node (ref "U$34") (pin "P$22") (pinfunction "C2_P$22") (pintype "bidirectional"))
    )
    (net (code "94") (name "C2-4") (class "Default")
      (node (ref "C18") (pin "2") (pinfunction "2_2") (pintype "passive"))
      (node (ref "R78") (pin "2") (pinfunction "2_2") (pintype "passive"))
      (node (ref "U$31") (pin "P$22") (pinfunction "C2_P$22") (pintype "bidirectional"))
    )
    (net (code "95") (name "C2-5") (class "Default")
      (node (ref "C55") (pin "2") (pinfunction "2_2") (pintype "passive"))
      (node (ref "R334") (pin "2") (pinfunction "2_2") (pintype "passive"))
      (node (ref "U$61") (pin "P$22") (pinfunction "C2_P$22") (pintype "bidirectional"))
    )
    (net (code "96") (name "C2-6") (class "Default")
      (node (ref "C86") (pin "2") (pinfunction "2_2") (pintype "passive"))
      (node (ref "R417") (pin "2") (pinfunction "2_2") (pintype "passive"))
      (node (ref "U$76") (pin "P$22") (pinfunction "C2_P$22") (pintype "bidirectional"))
    )
    (net (code "97") (name "C2-7") (class "Default")
      (node (ref "C103") (pin "2") (pinfunction "2_2") (pintype "passive"))
      (node (ref "R500") (pin "2") (pinfunction "2_2") (pintype "passive"))
      (node (ref "U$91") (pin "P$22") (pinfunction "C2_P$22") (pintype "bidirectional"))
    )
    (net (code "98") (name "C2-8") (class "Default")
      (node (ref "C120") (pin "2") (pinfunction "2_2") (pintype "passive"))
      (node (ref "R583") (pin "2") (pinfunction "2_2") (pintype "passive"))
      (node (ref "U$106") (pin "P$22") (pinfunction "C2_P$22") (pintype "bidirectional"))
    )
    (net (code "99") (name "C2-9") (class "Default")
      (node (ref "C137") (pin "2") (pinfunction "2_2") (pintype "passive"))
      (node (ref "R666") (pin "2") (pinfunction "2_2") (pintype "passive"))
      (node (ref "U$121") (pin "P$22") (pinfunction "C2_P$22") (pintype "bidirectional"))
    )
    (net (code "100") (name "C3") (class "Default")
      (node (ref "C3") (pin "2") (pinfunction "2_2") (pintype "passive"))
      (node (ref "R16") (pin "2") (pinfunction "2_2") (pintype "passive"))
      (node (ref "U$1") (pin "P$20") (pinfunction "C3_P$20") (pintype "bidirectional"))
    )
    (net (code "101") (name "C3-2") (class "Default")
      (node (ref "C21") (pin "2") (pinfunction "2_2") (pintype "passive"))
      (node (ref "R101") (pin "2") (pinfunction "2_2") (pintype "passive"))
      (node (ref "U$16") (pin "P$20") (pinfunction "C3_P$20") (pintype "bidirectional"))
    )
    (net (code "102") (name "C3-3") (class "Default")
      (node (ref "C54") (pin "2") (pinfunction "2_2") (pintype "passive"))
      (node (ref "R195") (pin "2") (pinfunction "2_2") (pintype "passive"))
      (node (ref "U$34") (pin "P$20") (pinfunction "C3_P$20") (pintype "bidirectional"))
    )
    (net (code "103") (name "C3-4") (class "Default")
      (node (ref "C38") (pin "2") (pinfunction "2_2") (pintype "passive"))
      (node (ref "R180") (pin "2") (pinfunction "2_2") (pintype "passive"))
      (node (ref "U$31") (pin "P$20") (pinfunction "C3_P$20") (pintype "bidirectional"))
    )
    (net (code "104") (name "C3-5") (class "Default")
      (node (ref "C57") (pin "2") (pinfunction "2_2") (pintype "passive"))
      (node (ref "R346") (pin "2") (pinfunction "2_2") (pintype "passive"))
      (node (ref "U$61") (pin "P$20") (pinfunction "C3_P$20") (pintype "bidirectional"))
    )
    (net (code "105") (name "C3-6") (class "Default")
      (node (ref "C88") (pin "2") (pinfunction "2_2") (pintype "passive"))
      (node (ref "R429") (pin "2") (pinfunction "2_2") (pintype "passive"))
      (node (ref "U$76") (pin "P$20") (pinfunction "C3_P$20") (pintype "bidirectional"))
    )
    (net (code "106") (name "C3-7") (class "Default")
      (node (ref "C105") (pin "2") (pinfunction "2_2") (pintype "passive"))
      (node (ref "R512") (pin "2") (pinfunction "2_2") (pintype "passive"))
      (node (ref "U$91") (pin "P$20") (pinfunction "C3_P$20") (pintype "bidirectional"))
    )
    (net (code "107") (name "C3-8") (class "Default")
      (node (ref "C122") (pin "2") (pinfunction "2_2") (pintype "passive"))
      (node (ref "R595") (pin "2") (pinfunction "2_2") (pintype "passive"))
      (node (ref "U$106") (pin "P$20") (pinfunction "C3_P$20") (pintype "bidirectional"))
    )
    (net (code "108") (name "C3-9") (class "Default")
      (node (ref "C139") (pin "2") (pinfunction "2_2") (pintype "passive"))
      (node (ref "R678") (pin "2") (pinfunction "2_2") (pintype "passive"))
      (node (ref "U$121") (pin "P$20") (pinfunction "C3_P$20") (pintype "bidirectional"))
    )
    (net (code "109") (name "C4") (class "Default")
      (node (ref "C4") (pin "2") (pinfunction "2_2") (pintype "passive"))
      (node (ref "R22") (pin "2") (pinfunction "2_2") (pintype "passive"))
      (node (ref "U$1") (pin "P$18") (pinfunction "C4_P$18") (pintype "bidirectional"))
    )
    (net (code "110") (name "C4-2") (class "Default")
      (node (ref "C22") (pin "2") (pinfunction "2_2") (pintype "passive"))
      (node (ref "R107") (pin "2") (pinfunction "2_2") (pintype "passive"))
      (node (ref "U$16") (pin "P$18") (pinfunction "C4_P$18") (pintype "bidirectional"))
    )
    (net (code "111") (name "C4-3") (class "Default")
      (node (ref "C60") (pin "2") (pinfunction "2_2") (pintype "passive"))
      (node (ref "R201") (pin "2") (pinfunction "2_2") (pintype "passive"))
      (node (ref "U$34") (pin "P$18") (pinfunction "C4_P$18") (pintype "bidirectional"))
    )
    (net (code "112") (name "C4-4") (class "Default")
      (node (ref "C39") (pin "2") (pinfunction "2_2") (pintype "passive"))
      (node (ref "R269") (pin "2") (pinfunction "2_2") (pintype "passive"))
      (node (ref "U$31") (pin "P$18") (pinfunction "C4_P$18") (pintype "bidirectional"))
    )
    (net (code "113") (name "C4-5") (class "Default")
      (node (ref "C58") (pin "2") (pinfunction "2_2") (pintype "passive"))
      (node (ref "R352") (pin "2") (pinfunction "2_2") (pintype "passive"))
      (node (ref "U$61") (pin "P$18") (pinfunction "C4_P$18") (pintype "bidirectional"))
    )
    (net (code "114") (name "C4-6") (class "Default")
      (node (ref "C89") (pin "2") (pinfunction "2_2") (pintype "passive"))
      (node (ref "R435") (pin "2") (pinfunction "2_2") (pintype "passive"))
      (node (ref "U$76") (pin "P$18") (pinfunction "C4_P$18") (pintype "bidirectional"))
    )
    (net (code "115") (name "C4-7") (class "Default")
      (node (ref "C106") (pin "2") (pinfunction "2_2") (pintype "passive"))
      (node (ref "R518") (pin "2") (pinfunction "2_2") (pintype "passive"))
      (node (ref "U$91") (pin "P$18") (pinfunction "C4_P$18") (pintype "bidirectional"))
    )
    (net (code "116") (name "C4-8") (class "Default")
      (node (ref "C123") (pin "2") (pinfunction "2_2") (pintype "passive"))
      (node (ref "R601") (pin "2") (pinfunction "2_2") (pintype "passive"))
      (node (ref "U$106") (pin "P$18") (pinfunction "C4_P$18") (pintype "bidirectional"))
    )
    (net (code "117") (name "C4-9") (class "Default")
      (node (ref "C140") (pin "2") (pinfunction "2_2") (pintype "passive"))
      (node (ref "R684") (pin "2") (pinfunction "2_2") (pintype "passive"))
      (node (ref "U$121") (pin "P$18") (pinfunction "C4_P$18") (pintype "bidirectional"))
    )
    (net (code "118") (name "C5") (class "Default")
      (node (ref "C5") (pin "2") (pinfunction "2_2") (pintype "passive"))
      (node (ref "R28") (pin "2") (pinfunction "2_2") (pintype "passive"))
      (node (ref "U$1") (pin "P$16") (pinfunction "C5_P$16") (pintype "bidirectional"))
    )
    (net (code "119") (name "C5-2") (class "Default")
      (node (ref "C23") (pin "2") (pinfunction "2_2") (pintype "passive"))
      (node (ref "R113") (pin "2") (pinfunction "2_2") (pintype "passive"))
      (node (ref "U$16") (pin "P$16") (pinfunction "C5_P$16") (pintype "bidirectional"))
    )
    (net (code "120") (name "C5-3") (class "Default")
      (node (ref "C63") (pin "2") (pinfunction "2_2") (pintype "passive"))
      (node (ref "R207") (pin "2") (pinfunction "2_2") (pintype "passive"))
      (node (ref "U$34") (pin "P$16") (pinfunction "C5_P$16") (pintype "bidirectional"))
    )
    (net (code "121") (name "C5-4") (class "Default")
      (node (ref "C40") (pin "2") (pinfunction "2_2") (pintype "passive"))
      (node (ref "R275") (pin "2") (pinfunction "2_2") (pintype "passive"))
      (node (ref "U$31") (pin "P$16") (pinfunction "C5_P$16") (pintype "bidirectional"))
    )
    (net (code "122") (name "C5-5") (class "Default")
      (node (ref "C59") (pin "2") (pinfunction "2_2") (pintype "passive"))
      (node (ref "R358") (pin "2") (pinfunction "2_2") (pintype "passive"))
      (node (ref "U$61") (pin "P$16") (pinfunction "C5_P$16") (pintype "bidirectional"))
    )
    (net (code "123") (name "C5-6") (class "Default")
      (node (ref "C90") (pin "2") (pinfunction "2_2") (pintype "passive"))
      (node (ref "R441") (pin "2") (pinfunction "2_2") (pintype "passive"))
      (node (ref "U$76") (pin "P$16") (pinfunction "C5_P$16") (pintype "bidirectional"))
    )
    (net (code "124") (name "C5-7") (class "Default")
      (node (ref "C107") (pin "2") (pinfunction "2_2") (pintype "passive"))
      (node (ref "R524") (pin "2") (pinfunction "2_2") (pintype "passive"))
      (node (ref "U$91") (pin "P$16") (pinfunction "C5_P$16") (pintype "bidirectional"))
    )
    (net (code "125") (name "C5-8") (class "Default")
      (node (ref "C124") (pin "2") (pinfunction "2_2") (pintype "passive"))
      (node (ref "R607") (pin "2") (pinfunction "2_2") (pintype "passive"))
      (node (ref "U$106") (pin "P$16") (pinfunction "C5_P$16") (pintype "bidirectional"))
    )
    (net (code "126") (name "C5-9") (class "Default")
      (node (ref "C141") (pin "2") (pinfunction "2_2") (pintype "passive"))
      (node (ref "R690") (pin "2") (pinfunction "2_2") (pintype "passive"))
      (node (ref "U$121") (pin "P$16") (pinfunction "C5_P$16") (pintype "bidirectional"))
    )
    (net (code "127") (name "C6") (class "Default")
      (node (ref "C6") (pin "2") (pinfunction "2_2") (pintype "passive"))
      (node (ref "R34") (pin "2") (pinfunction "2_2") (pintype "passive"))
      (node (ref "U$1") (pin "P$14") (pinfunction "C6_P$14") (pintype "bidirectional"))
    )
    (net (code "128") (name "C6-2") (class "Default")
      (node (ref "C24") (pin "2") (pinfunction "2_2") (pintype "passive"))
      (node (ref "R119") (pin "2") (pinfunction "2_2") (pintype "passive"))
      (node (ref "U$16") (pin "P$14") (pinfunction "C6_P$14") (pintype "bidirectional"))
    )
    (net (code "129") (name "C6-3") (class "Default")
      (node (ref "C64") (pin "2") (pinfunction "2_2") (pintype "passive"))
      (node (ref "R213") (pin "2") (pinfunction "2_2") (pintype "passive"))
      (node (ref "U$34") (pin "P$14") (pinfunction "C6_P$14") (pintype "bidirectional"))
    )
    (net (code "130") (name "C6-4") (class "Default")
      (node (ref "C41") (pin "2") (pinfunction "2_2") (pintype "passive"))
      (node (ref "R281") (pin "2") (pinfunction "2_2") (pintype "passive"))
      (node (ref "U$31") (pin "P$14") (pinfunction "C6_P$14") (pintype "bidirectional"))
    )
    (net (code "131") (name "C6-5") (class "Default")
      (node (ref "C61") (pin "2") (pinfunction "2_2") (pintype "passive"))
      (node (ref "R364") (pin "2") (pinfunction "2_2") (pintype "passive"))
      (node (ref "U$61") (pin "P$14") (pinfunction "C6_P$14") (pintype "bidirectional"))
    )
    (net (code "132") (name "C6-6") (class "Default")
      (node (ref "C91") (pin "2") (pinfunction "2_2") (pintype "passive"))
      (node (ref "R447") (pin "2") (pinfunction "2_2") (pintype "passive"))
      (node (ref "U$76") (pin "P$14") (pinfunction "C6_P$14") (pintype "bidirectional"))
    )
    (net (code "133") (name "C6-7") (class "Default")
      (node (ref "C108") (pin "2") (pinfunction "2_2") (pintype "passive"))
      (node (ref "R530") (pin "2") (pinfunction "2_2") (pintype "passive"))
      (node (ref "U$91") (pin "P$14") (pinfunction "C6_P$14") (pintype "bidirectional"))
    )
    (net (code "134") (name "C6-8") (class "Default")
      (node (ref "C125") (pin "2") (pinfunction "2_2") (pintype "passive"))
      (node (ref "R613") (pin "2") (pinfunction "2_2") (pintype "passive"))
      (node (ref "U$106") (pin "P$14") (pinfunction "C6_P$14") (pintype "bidirectional"))
    )
    (net (code "135") (name "C6-9") (class "Default")
      (node (ref "C142") (pin "2") (pinfunction "2_2") (pintype "passive"))
      (node (ref "R696") (pin "2") (pinfunction "2_2") (pintype "passive"))
      (node (ref "U$121") (pin "P$14") (pinfunction "C6_P$14") (pintype "bidirectional"))
    )
    (net (code "136") (name "C7") (class "Default")
      (node (ref "C8") (pin "2") (pinfunction "2_2") (pintype "passive"))
      (node (ref "R46") (pin "2") (pinfunction "2_2") (pintype "passive"))
      (node (ref "U$1") (pin "P$12") (pinfunction "C7_P$12") (pintype "bidirectional"))
    )
    (net (code "137") (name "C7-2") (class "Default")
      (node (ref "C26") (pin "2") (pinfunction "2_2") (pintype "passive"))
      (node (ref "R131") (pin "2") (pinfunction "2_2") (pintype "passive"))
      (node (ref "U$16") (pin "P$12") (pinfunction "C7_P$12") (pintype "bidirectional"))
    )
    (net (code "138") (name "C7-3") (class "Default")
      (node (ref "C66") (pin "2") (pinfunction "2_2") (pintype "passive"))
      (node (ref "R225") (pin "2") (pinfunction "2_2") (pintype "passive"))
      (node (ref "U$34") (pin "P$12") (pinfunction "C7_P$12") (pintype "bidirectional"))
    )
    (net (code "139") (name "C7-4") (class "Default")
      (node (ref "C44") (pin "2") (pinfunction "2_2") (pintype "passive"))
      (node (ref "R293") (pin "2") (pinfunction "2_2") (pintype "passive"))
      (node (ref "U$31") (pin "P$12") (pinfunction "C7_P$12") (pintype "bidirectional"))
    )
    (net (code "140") (name "C7-5") (class "Default")
      (node (ref "C67") (pin "2") (pinfunction "2_2") (pintype "passive"))
      (node (ref "R376") (pin "2") (pinfunction "2_2") (pintype "passive"))
      (node (ref "U$61") (pin "P$12") (pinfunction "C7_P$12") (pintype "bidirectional"))
    )
    (net (code "141") (name "C7-6") (class "Default")
      (node (ref "C93") (pin "2") (pinfunction "2_2") (pintype "passive"))
      (node (ref "R459") (pin "2") (pinfunction "2_2") (pintype "passive"))
      (node (ref "U$76") (pin "P$12") (pinfunction "C7_P$12") (pintype "bidirectional"))
    )
    (net (code "142") (name "C7-7") (class "Default")
      (node (ref "C110") (pin "2") (pinfunction "2_2") (pintype "passive"))
      (node (ref "R542") (pin "2") (pinfunction "2_2") (pintype "passive"))
      (node (ref "U$91") (pin "P$12") (pinfunction "C7_P$12") (pintype "bidirectional"))
    )
    (net (code "143") (name "C7-8") (class "Default")
      (node (ref "C127") (pin "2") (pinfunction "2_2") (pintype "passive"))
      (node (ref "R625") (pin "2") (pinfunction "2_2") (pintype "passive"))
      (node (ref "U$106") (pin "P$12") (pinfunction "C7_P$12") (pintype "bidirectional"))
    )
    (net (code "144") (name "C7-9") (class "Default")
      (node (ref "C144") (pin "2") (pinfunction "2_2") (pintype "passive"))
      (node (ref "R708") (pin "2") (pinfunction "2_2") (pintype "passive"))
      (node (ref "U$121") (pin "P$12") (pinfunction "C7_P$12") (pintype "bidirectional"))
    )
    (net (code "145") (name "C8") (class "Default")
      (node (ref "C7") (pin "2") (pinfunction "2_2") (pintype "passive"))
      (node (ref "R40") (pin "2") (pinfunction "2_2") (pintype "passive"))
      (node (ref "U$1") (pin "P$10") (pinfunction "C8_P$10") (pintype "bidirectional"))
    )
    (net (code "146") (name "C8-2") (class "Default")
      (node (ref "C25") (pin "2") (pinfunction "2_2") (pintype "passive"))
      (node (ref "R125") (pin "2") (pinfunction "2_2") (pintype "passive"))
      (node (ref "U$16") (pin "P$10") (pinfunction "C8_P$10") (pintype "bidirectional"))
    )
    (net (code "147") (name "C8-3") (class "Default")
      (node (ref "C65") (pin "2") (pinfunction "2_2") (pintype "passive"))
      (node (ref "R219") (pin "2") (pinfunction "2_2") (pintype "passive"))
      (node (ref "U$34") (pin "P$10") (pinfunction "C8_P$10") (pintype "bidirectional"))
    )
    (net (code "148") (name "C8-4") (class "Default")
      (node (ref "C43") (pin "2") (pinfunction "2_2") (pintype "passive"))
      (node (ref "R287") (pin "2") (pinfunction "2_2") (pintype "passive"))
      (node (ref "U$31") (pin "P$10") (pinfunction "C8_P$10") (pintype "bidirectional"))
    )
    (net (code "149") (name "C8-5") (class "Default")
      (node (ref "C62") (pin "2") (pinfunction "2_2") (pintype "passive"))
      (node (ref "R370") (pin "2") (pinfunction "2_2") (pintype "passive"))
      (node (ref "U$61") (pin "P$10") (pinfunction "C8_P$10") (pintype "bidirectional"))
    )
    (net (code "150") (name "C8-6") (class "Default")
      (node (ref "C92") (pin "2") (pinfunction "2_2") (pintype "passive"))
      (node (ref "R453") (pin "2") (pinfunction "2_2") (pintype "passive"))
      (node (ref "U$76") (pin "P$10") (pinfunction "C8_P$10") (pintype "bidirectional"))
    )
    (net (code "151") (name "C8-7") (class "Default")
      (node (ref "C109") (pin "2") (pinfunction "2_2") (pintype "passive"))
      (node (ref "R536") (pin "2") (pinfunction "2_2") (pintype "passive"))
      (node (ref "U$91") (pin "P$10") (pinfunction "C8_P$10") (pintype "bidirectional"))
    )
    (net (code "152") (name "C8-8") (class "Default")
      (node (ref "C126") (pin "2") (pinfunction "2_2") (pintype "passive"))
      (node (ref "R619") (pin "2") (pinfunction "2_2") (pintype "passive"))
      (node (ref "U$106") (pin "P$10") (pinfunction "C8_P$10") (pintype "bidirectional"))
    )
    (net (code "153") (name "C8-9") (class "Default")
      (node (ref "C143") (pin "2") (pinfunction "2_2") (pintype "passive"))
      (node (ref "R702") (pin "2") (pinfunction "2_2") (pintype "passive"))
      (node (ref "U$121") (pin "P$10") (pinfunction "C8_P$10") (pintype "bidirectional"))
    )
    (net (code "154") (name "C9") (class "Default")
      (node (ref "C9") (pin "2") (pinfunction "2_2") (pintype "passive"))
      (node (ref "R52") (pin "2") (pinfunction "2_2") (pintype "passive"))
      (node (ref "U$1") (pin "P$8") (pinfunction "C9_P$8") (pintype "bidirectional"))
    )
    (net (code "155") (name "C9-2") (class "Default")
      (node (ref "C27") (pin "2") (pinfunction "2_2") (pintype "passive"))
      (node (ref "R137") (pin "2") (pinfunction "2_2") (pintype "passive"))
      (node (ref "U$16") (pin "P$8") (pinfunction "C9_P$8") (pintype "bidirectional"))
    )
    (net (code "156") (name "C9-3") (class "Default")
      (node (ref "C69") (pin "2") (pinfunction "2_2") (pintype "passive"))
      (node (ref "R231") (pin "2") (pinfunction "2_2") (pintype "passive"))
      (node (ref "U$34") (pin "P$8") (pinfunction "C9_P$8") (pintype "bidirectional"))
    )
    (net (code "157") (name "C9-4") (class "Default")
      (node (ref "C45") (pin "2") (pinfunction "2_2") (pintype "passive"))
      (node (ref "R299") (pin "2") (pinfunction "2_2") (pintype "passive"))
      (node (ref "U$31") (pin "P$8") (pinfunction "C9_P$8") (pintype "bidirectional"))
    )
    (net (code "158") (name "C9-5") (class "Default")
      (node (ref "C68") (pin "2") (pinfunction "2_2") (pintype "passive"))
      (node (ref "R382") (pin "2") (pinfunction "2_2") (pintype "passive"))
      (node (ref "U$61") (pin "P$8") (pinfunction "C9_P$8") (pintype "bidirectional"))
    )
    (net (code "159") (name "C9-6") (class "Default")
      (node (ref "C94") (pin "2") (pinfunction "2_2") (pintype "passive"))
      (node (ref "R465") (pin "2") (pinfunction "2_2") (pintype "passive"))
      (node (ref "U$76") (pin "P$8") (pinfunction "C9_P$8") (pintype "bidirectional"))
    )
    (net (code "160") (name "C9-7") (class "Default")
      (node (ref "C111") (pin "2") (pinfunction "2_2") (pintype "passive"))
      (node (ref "R548") (pin "2") (pinfunction "2_2") (pintype "passive"))
      (node (ref "U$91") (pin "P$8") (pinfunction "C9_P$8") (pintype "bidirectional"))
    )
    (net (code "161") (name "C9-8") (class "Default")
      (node (ref "C128") (pin "2") (pinfunction "2_2") (pintype "passive"))
      (node (ref "R631") (pin "2") (pinfunction "2_2") (pintype "passive"))
      (node (ref "U$106") (pin "P$8") (pinfunction "C9_P$8") (pintype "bidirectional"))
    )
    (net (code "162") (name "C9-9") (class "Default")
      (node (ref "C145") (pin "2") (pinfunction "2_2") (pintype "passive"))
      (node (ref "R714") (pin "2") (pinfunction "2_2") (pintype "passive"))
      (node (ref "U$121") (pin "P$8") (pinfunction "C9_P$8") (pintype "bidirectional"))
    )
    (net (code "163") (name "C10") (class "Default")
      (node (ref "C10") (pin "2") (pinfunction "2_2") (pintype "passive"))
      (node (ref "R58") (pin "2") (pinfunction "2_2") (pintype "passive"))
      (node (ref "U$1") (pin "P$6") (pinfunction "C10_P$6") (pintype "bidirectional"))
    )
    (net (code "164") (name "C10-2") (class "Default")
      (node (ref "C28") (pin "2") (pinfunction "2_2") (pintype "passive"))
      (node (ref "R143") (pin "2") (pinfunction "2_2") (pintype "passive"))
      (node (ref "U$16") (pin "P$6") (pinfunction "C10_P$6") (pintype "bidirectional"))
    )
    (net (code "165") (name "C10-3") (class "Default")
      (node (ref "C71") (pin "2") (pinfunction "2_2") (pintype "passive"))
      (node (ref "R237") (pin "2") (pinfunction "2_2") (pintype "passive"))
      (node (ref "U$34") (pin "P$6") (pinfunction "C10_P$6") (pintype "bidirectional"))
    )
    (net (code "166") (name "C10-4") (class "Default")
      (node (ref "C46") (pin "2") (pinfunction "2_2") (pintype "passive"))
      (node (ref "R305") (pin "2") (pinfunction "2_2") (pintype "passive"))
      (node (ref "U$31") (pin "P$6") (pinfunction "C10_P$6") (pintype "bidirectional"))
    )
    (net (code "167") (name "C10-5") (class "Default")
      (node (ref "C70") (pin "2") (pinfunction "2_2") (pintype "passive"))
      (node (ref "R388") (pin "2") (pinfunction "2_2") (pintype "passive"))
      (node (ref "U$61") (pin "P$6") (pinfunction "C10_P$6") (pintype "bidirectional"))
    )
    (net (code "168") (name "C10-6") (class "Default")
      (node (ref "C95") (pin "2") (pinfunction "2_2") (pintype "passive"))
      (node (ref "R471") (pin "2") (pinfunction "2_2") (pintype "passive"))
      (node (ref "U$76") (pin "P$6") (pinfunction "C10_P$6") (pintype "bidirectional"))
    )
    (net (code "169") (name "C10-7") (class "Default")
      (node (ref "C112") (pin "2") (pinfunction "2_2") (pintype "passive"))
      (node (ref "R554") (pin "2") (pinfunction "2_2") (pintype "passive"))
      (node (ref "U$91") (pin "P$6") (pinfunction "C10_P$6") (pintype "bidirectional"))
    )
    (net (code "170") (name "C10-8") (class "Default")
      (node (ref "C129") (pin "2") (pinfunction "2_2") (pintype "passive"))
      (node (ref "R637") (pin "2") (pinfunction "2_2") (pintype "passive"))
      (node (ref "U$106") (pin "P$6") (pinfunction "C10_P$6") (pintype "bidirectional"))
    )
    (net (code "171") (name "C10-9") (class "Default")
      (node (ref "C146") (pin "2") (pinfunction "2_2") (pintype "passive"))
      (node (ref "R720") (pin "2") (pinfunction "2_2") (pintype "passive"))
      (node (ref "U$121") (pin "P$6") (pinfunction "C10_P$6") (pintype "bidirectional"))
    )
    (net (code "172") (name "C11") (class "Default")
      (node (ref "C11") (pin "2") (pinfunction "2_2") (pintype "passive"))
      (node (ref "R64") (pin "2") (pinfunction "2_2") (pintype "passive"))
      (node (ref "U$1") (pin "P$4") (pinfunction "C11_P$4") (pintype "bidirectional"))
    )
    (net (code "173") (name "C11-2") (class "Default")
      (node (ref "C29") (pin "2") (pinfunction "2_2") (pintype "passive"))
      (node (ref "R149") (pin "2") (pinfunction "2_2") (pintype "passive"))
      (node (ref "U$16") (pin "P$4") (pinfunction "C11_P$4") (pintype "bidirectional"))
    )
    (net (code "174") (name "C11-3") (class "Default")
      (node (ref "C72") (pin "2") (pinfunction "2_2") (pintype "passive"))
      (node (ref "R243") (pin "2") (pinfunction "2_2") (pintype "passive"))
      (node (ref "U$34") (pin "P$4") (pinfunction "C11_P$4") (pintype "bidirectional"))
    )
    (net (code "175") (name "C11-4") (class "Default")
      (node (ref "C47") (pin "2") (pinfunction "2_2") (pintype "passive"))
      (node (ref "R311") (pin "2") (pinfunction "2_2") (pintype "passive"))
      (node (ref "U$31") (pin "P$4") (pinfunction "C11_P$4") (pintype "bidirectional"))
    )
    (net (code "176") (name "C11-5") (class "Default")
      (node (ref "C79") (pin "2") (pinfunction "2_2") (pintype "passive"))
      (node (ref "R394") (pin "2") (pinfunction "2_2") (pintype "passive"))
      (node (ref "U$61") (pin "P$4") (pinfunction "C11_P$4") (pintype "bidirectional"))
    )
    (net (code "177") (name "C11-6") (class "Default")
      (node (ref "C96") (pin "2") (pinfunction "2_2") (pintype "passive"))
      (node (ref "R477") (pin "2") (pinfunction "2_2") (pintype "passive"))
      (node (ref "U$76") (pin "P$4") (pinfunction "C11_P$4") (pintype "bidirectional"))
    )
    (net (code "178") (name "C11-7") (class "Default")
      (node (ref "C113") (pin "2") (pinfunction "2_2") (pintype "passive"))
      (node (ref "R560") (pin "2") (pinfunction "2_2") (pintype "passive"))
      (node (ref "U$91") (pin "P$4") (pinfunction "C11_P$4") (pintype "bidirectional"))
    )
    (net (code "179") (name "C11-8") (class "Default")
      (node (ref "C130") (pin "2") (pinfunction "2_2") (pintype "passive"))
      (node (ref "R643") (pin "2") (pinfunction "2_2") (pintype "passive"))
      (node (ref "U$106") (pin "P$4") (pinfunction "C11_P$4") (pintype "bidirectional"))
    )
    (net (code "180") (name "C11-9") (class "Default")
      (node (ref "C147") (pin "2") (pinfunction "2_2") (pintype "passive"))
      (node (ref "R726") (pin "2") (pinfunction "2_2") (pintype "passive"))
      (node (ref "U$121") (pin "P$4") (pinfunction "C11_P$4") (pintype "bidirectional"))
    )
    (net (code "181") (name "C12") (class "Default")
      (node (ref "C12") (pin "2") (pinfunction "2_2") (pintype "passive"))
      (node (ref "R70") (pin "2") (pinfunction "2_2") (pintype "passive"))
      (node (ref "U$1") (pin "P$2") (pinfunction "C12_P$2") (pintype "bidirectional"))
    )
    (net (code "182") (name "C12-2") (class "Default")
      (node (ref "C30") (pin "2") (pinfunction "2_2") (pintype "passive"))
      (node (ref "R155") (pin "2") (pinfunction "2_2") (pintype "passive"))
      (node (ref "U$16") (pin "P$2") (pinfunction "C12_P$2") (pintype "bidirectional"))
    )
    (net (code "183") (name "C12-3") (class "Default")
      (node (ref "C73") (pin "2") (pinfunction "2_2") (pintype "passive"))
      (node (ref "R249") (pin "2") (pinfunction "2_2") (pintype "passive"))
      (node (ref "U$34") (pin "P$2") (pinfunction "C12_P$2") (pintype "bidirectional"))
    )
    (net (code "184") (name "C12-4") (class "Default")
      (node (ref "C48") (pin "2") (pinfunction "2_2") (pintype "passive"))
      (node (ref "R317") (pin "2") (pinfunction "2_2") (pintype "passive"))
      (node (ref "U$31") (pin "P$2") (pinfunction "C12_P$2") (pintype "bidirectional"))
    )
    (net (code "185") (name "C12-5") (class "Default")
      (node (ref "C80") (pin "2") (pinfunction "2_2") (pintype "passive"))
      (node (ref "R400") (pin "2") (pinfunction "2_2") (pintype "passive"))
      (node (ref "U$61") (pin "P$2") (pinfunction "C12_P$2") (pintype "bidirectional"))
    )
    (net (code "186") (name "C12-6") (class "Default")
      (node (ref "C97") (pin "2") (pinfunction "2_2") (pintype "passive"))
      (node (ref "R483") (pin "2") (pinfunction "2_2") (pintype "passive"))
      (node (ref "U$76") (pin "P$2") (pinfunction "C12_P$2") (pintype "bidirectional"))
    )
    (net (code "187") (name "C12-7") (class "Default")
      (node (ref "C114") (pin "2") (pinfunction "2_2") (pintype "passive"))
      (node (ref "R566") (pin "2") (pinfunction "2_2") (pintype "passive"))
      (node (ref "U$91") (pin "P$2") (pinfunction "C12_P$2") (pintype "bidirectional"))
    )
    (net (code "188") (name "C12-8") (class "Default")
      (node (ref "C131") (pin "2") (pinfunction "2_2") (pintype "passive"))
      (node (ref "R649") (pin "2") (pinfunction "2_2") (pintype "passive"))
      (node (ref "U$106") (pin "P$2") (pinfunction "C12_P$2") (pintype "bidirectional"))
    )
    (net (code "189") (name "C12-9") (class "Default")
      (node (ref "C148") (pin "2") (pinfunction "2_2") (pintype "passive"))
      (node (ref "R732") (pin "2") (pinfunction "2_2") (pintype "passive"))
      (node (ref "U$121") (pin "P$2") (pinfunction "C12_P$2") (pintype "bidirectional"))
    )
    (net (code "190") (name "CSBI") (class "Default")
      (node (ref "JP1") (pin "3") (pinfunction "3_3") (pintype "passive"))
      (node (ref "U$107") (pin "5") (pinfunction "A3_5") (pintype "bidirectional"))
      (node (ref "U$122") (pin "5") (pinfunction "A3_5") (pintype "bidirectional"))
      (node (ref "U$17") (pin "5") (pinfunction "A3_5") (pintype "bidirectional"))
      (node (ref "U$2") (pin "5") (pinfunction "A3_5") (pintype "bidirectional"))
      (node (ref "U$32") (pin "5") (pinfunction "A3_5") (pintype "bidirectional"))
      (node (ref "U$35") (pin "5") (pinfunction "A3_5") (pintype "bidirectional"))
      (node (ref "U$62") (pin "5") (pinfunction "A3_5") (pintype "bidirectional"))
      (node (ref "U$77") (pin "5") (pinfunction "A3_5") (pintype "bidirectional"))
      (node (ref "U$92") (pin "5") (pinfunction "A3_5") (pintype "bidirectional"))
    )
    (net (code "191") (name "GND") (class "Default")
      (node (ref "JP1") (pin "1") (pinfunction "1_1") (pintype "passive"))
      (node (ref "U$107") (pin "2") (pinfunction "GND1_2") (pintype "bidirectional"))
      (node (ref "U$107") (pin "8") (pinfunction "GND2_8") (pintype "bidirectional"))
      (node (ref "U$122") (pin "2") (pinfunction "GND1_2") (pintype "bidirectional"))
      (node (ref "U$122") (pin "8") (pinfunction "GND2_8") (pintype "bidirectional"))
      (node (ref "U$17") (pin "2") (pinfunction "GND1_2") (pintype "bidirectional"))
      (node (ref "U$17") (pin "8") (pinfunction "GND2_8") (pintype "bidirectional"))
      (node (ref "U$2") (pin "2") (pinfunction "GND1_2") (pintype "bidirectional"))
      (node (ref "U$2") (pin "8") (pinfunction "GND2_8") (pintype "bidirectional"))
      (node (ref "U$32") (pin "2") (pinfunction "GND1_2") (pintype "bidirectional"))
      (node (ref "U$32") (pin "8") (pinfunction "GND2_8") (pintype "bidirectional"))
      (node (ref "U$35") (pin "2") (pinfunction "GND1_2") (pintype "bidirectional"))
      (node (ref "U$35") (pin "8") (pinfunction "GND2_8") (pintype "bidirectional"))
      (node (ref "U$62") (pin "2") (pinfunction "GND1_2") (pintype "bidirectional"))
      (node (ref "U$62") (pin "8") (pinfunction "GND2_8") (pintype "bidirectional"))
      (node (ref "U$77") (pin "2") (pinfunction "GND1_2") (pintype "bidirectional"))
      (node (ref "U$77") (pin "8") (pinfunction "GND2_8") (pintype "bidirectional"))
      (node (ref "U$92") (pin "2") (pinfunction "GND1_2") (pintype "bidirectional"))
      (node (ref "U$92") (pin "8") (pinfunction "GND2_8") (pintype "bidirectional"))
    )
    (net (code "192") (name "GND2") (class "Default")
      (node (ref "C19") (pin "1") (pinfunction "1_1") (pintype "passive"))
      (node (ref "C20") (pin "1") (pinfunction "1_1") (pintype "passive"))
      (node (ref "C21") (pin "1") (pinfunction "1_1") (pintype "passive"))
      (node (ref "C22") (pin "1") (pinfunction "1_1") (pintype "passive"))
      (node (ref "C23") (pin "1") (pinfunction "1_1") (pintype "passive"))
      (node (ref "C24") (pin "1") (pinfunction "1_1") (pintype "passive"))
      (node (ref "C25") (pin "1") (pinfunction "1_1") (pintype "passive"))
      (node (ref "C26") (pin "1") (pinfunction "1_1") (pintype "passive"))
      (node (ref "C27") (pin "1") (pinfunction "1_1") (pintype "passive"))
      (node (ref "C28") (pin "1") (pinfunction "1_1") (pintype "passive"))
      (node (ref "C29") (pin "1") (pinfunction "1_1") (pintype "passive"))
      (node (ref "C30") (pin "1") (pinfunction "1_1") (pintype "passive"))
      (node (ref "C31") (pin "1") (pinfunction "1_1") (pintype "passive"))
      (node (ref "C32") (pin "1") (pinfunction "1_1") (pintype "passive"))
      (node (ref "C33") (pin "1") (pinfunction "1_1") (pintype "passive"))
      (node (ref "C34") (pin "1") (pinfunction "1_1") (pintype "passive"))
      (node (ref "C35") (pin "1") (pinfunction "1_1") (pintype "passive"))
      (node (ref "D28") (pin "A") (pinfunction "A_A") (pintype "passive"))
      (node (ref "R161") (pin "2") (pinfunction "2_2") (pintype "passive"))
      (node (ref "R168") (pin "1") (pinfunction "1_1") (pintype "passive"))
      (node (ref "U$16") (pin "27") (pinfunction "V-_27") (pintype "bidirectional"))
      (node (ref "U$16") (pin "28") (pinfunction "NC_28") (pintype "bidirectional"))
      (node (ref "U$16") (pin "33") (pinfunction "TOS_33") (pintype "bidirectional"))
      (node (ref "U$16") (pin "38") (pinfunction "A1_38") (pintype "bidirectional"))
      (node (ref "U$16") (pin "39") (pinfunction "A2_39") (pintype "bidirectional"))
      (node (ref "U$16") (pin "40") (pinfunction "A3_40") (pintype "bidirectional"))
      (node (ref "U$17") (pin "15") (pinfunction "GND3_15") (pintype "bidirectional"))
      (node (ref "U$17") (pin "9") (pinfunction "GND4_9") (pintype "bidirectional"))
    )
    (net (code "193") (name "GND3") (class "Default")
      (node (ref "C36") (pin "1") (pinfunction "1_1") (pintype "passive"))
      (node (ref "C42") (pin "1") (pinfunction "1_1") (pintype "passive"))
      (node (ref "C54") (pin "1") (pinfunction "1_1") (pintype "passive"))
      (node (ref "C60") (pin "1") (pinfunction "1_1") (pintype "passive"))
      (node (ref "C63") (pin "1") (pinfunction "1_1") (pintype "passive"))
      (node (ref "C64") (pin "1") (pinfunction "1_1") (pintype "passive"))
      (node (ref "C65") (pin "1") (pinfunction "1_1") (pintype "passive"))
      (node (ref "C66") (pin "1") (pinfunction "1_1") (pintype "passive"))
      (node (ref "C69") (pin "1") (pinfunction "1_1") (pintype "passive"))
      (node (ref "C71") (pin "1") (pinfunction "1_1") (pintype "passive"))
      (node (ref "C72") (pin "1") (pinfunction "1_1") (pintype "passive"))
      (node (ref "C73") (pin "1") (pinfunction "1_1") (pintype "passive"))
      (node (ref "C74") (pin "1") (pinfunction "1_1") (pintype "passive"))
      (node (ref "C75") (pin "1") (pinfunction "1_1") (pintype "passive"))
      (node (ref "C76") (pin "1") (pinfunction "1_1") (pintype "passive"))
      (node (ref "C77") (pin "1") (pinfunction "1_1") (pintype "passive"))
      (node (ref "C78") (pin "1") (pinfunction "1_1") (pintype "passive"))
      (node (ref "D45") (pin "A") (pinfunction "A_A") (pintype "passive"))
      (node (ref "R255") (pin "2") (pinfunction "2_2") (pintype "passive"))
      (node (ref "R262") (pin "1") (pinfunction "1_1") (pintype "passive"))
      (node (ref "U$34") (pin "27") (pinfunction "V-_27") (pintype "bidirectional"))
      (node (ref "U$34") (pin "28") (pinfunction "NC_28") (pintype "bidirectional"))
      (node (ref "U$34") (pin "33") (pinfunction "TOS_33") (pintype "bidirectional"))
      (node (ref "U$34") (pin "37") (pinfunction "A0_37") (pintype "bidirectional"))
      (node (ref "U$34") (pin "39") (pinfunction "A2_39") (pintype "bidirectional"))
      (node (ref "U$34") (pin "40") (pinfunction "A3_40") (pintype "bidirectional"))
      (node (ref "U$35") (pin "15") (pinfunction "GND3_15") (pintype "bidirectional"))
      (node (ref "U$35") (pin "9") (pinfunction "GND4_9") (pintype "bidirectional"))
    )
    (net (code "194") (name "GND4") (class "Default")
      (node (ref "C18") (pin "1") (pinfunction "1_1") (pintype "passive"))
      (node (ref "C37") (pin "1") (pinfunction "1_1") (pintype "passive"))
      (node (ref "C38") (pin "1") (pinfunction "1_1") (pintype "passive"))
      (node (ref "C39") (pin "1") (pinfunction "1_1") (pintype "passive"))
      (node (ref "C40") (pin "1") (pinfunction "1_1") (pintype "passive"))
      (node (ref "C41") (pin "1") (pinfunction "1_1") (pintype "passive"))
      (node (ref "C43") (pin "1") (pinfunction "1_1") (pintype "passive"))
      (node (ref "C44") (pin "1") (pinfunction "1_1") (pintype "passive"))
      (node (ref "C45") (pin "1") (pinfunction "1_1") (pintype "passive"))
      (node (ref "C46") (pin "1") (pinfunction "1_1") (pintype "passive"))
      (node (ref "C47") (pin "1") (pinfunction "1_1") (pintype "passive"))
      (node (ref "C48") (pin "1") (pinfunction "1_1") (pintype "passive"))
      (node (ref "C49") (pin "1") (pinfunction "1_1") (pintype "passive"))
      (node (ref "C50") (pin "1") (pinfunction "1_1") (pintype "passive"))
      (node (ref "C51") (pin "1") (pinfunction "1_1") (pintype "passive"))
      (node (ref "C52") (pin "1") (pinfunction "1_1") (pintype "passive"))
      (node (ref "C53") (pin "1") (pinfunction "1_1") (pintype "passive"))
      (node (ref "D58") (pin "A") (pinfunction "A_A") (pintype "passive"))
      (node (ref "R323") (pin "2") (pinfunction "2_2") (pintype "passive"))
      (node (ref "R329") (pin "1") (pinfunction "1_1") (pintype "passive"))
      (node (ref "U$31") (pin "27") (pinfunction "V-_27") (pintype "bidirectional"))
      (node (ref "U$31") (pin "28") (pinfunction "NC_28") (pintype "bidirectional"))
      (node (ref "U$31") (pin "33") (pinfunction "TOS_33") (pintype "bidirectional"))
      (node (ref "U$31") (pin "39") (pinfunction "A2_39") (pintype "bidirectional"))
      (node (ref "U$31") (pin "40") (pinfunction "A3_40") (pintype "bidirectional"))
      (node (ref "U$32") (pin "15") (pinfunction "GND3_15") (pintype "bidirectional"))
      (node (ref "U$32") (pin "9") (pinfunction "GND4_9") (pintype "bidirectional"))
    )
    (net (code "195") (name "GND5") (class "Default")
      (node (ref "C55") (pin "1") (pinfunction "1_1") (pintype "passive"))
      (node (ref "C56") (pin "1") (pinfunction "1_1") (pintype "passive"))
      (node (ref "C57") (pin "1") (pinfunction "1_1") (pintype "passive"))
      (node (ref "C58") (pin "1") (pinfunction "1_1") (pintype "passive"))
      (node (ref "C59") (pin "1") (pinfunction "1_1") (pintype "passive"))
      (node (ref "C61") (pin "1") (pinfunction "1_1") (pintype "passive"))
      (node (ref "C62") (pin "1") (pinfunction "1_1") (pintype "passive"))
      (node (ref "C67") (pin "1") (pinfunction "1_1") (pintype "passive"))
      (node (ref "C68") (pin "1") (pinfunction "1_1") (pintype "passive"))
      (node (ref "C70") (pin "1") (pinfunction "1_1") (pintype "passive"))
      (node (ref "C79") (pin "1") (pinfunction "1_1") (pintype "passive"))
      (node (ref "C80") (pin "1") (pinfunction "1_1") (pintype "passive"))
      (node (ref "C81") (pin "1") (pinfunction "1_1") (pintype "passive"))
      (node (ref "C82") (pin "1") (pinfunction "1_1") (pintype "passive"))
      (node (ref "C83") (pin "1") (pinfunction "1_1") (pintype "passive"))
      (node (ref "C84") (pin "1") (pinfunction "1_1") (pintype "passive"))
      (node (ref "C85") (pin "1") (pinfunction "1_1") (pintype "passive"))
      (node (ref "D73") (pin "A") (pinfunction "A_A") (pintype "passive"))
      (node (ref "R406") (pin "2") (pinfunction "2_2") (pintype "passive"))
      (node (ref "R412") (pin "1") (pinfunction "1_1") (pintype "passive"))
      (node (ref "U$61") (pin "27") (pinfunction "V-_27") (pintype "bidirectional"))
      (node (ref "U$61") (pin "28") (pinfunction "NC_28") (pintype "bidirectional"))
      (node (ref "U$61") (pin "33") (pinfunction "TOS_33") (pintype "bidirectional"))
      (node (ref "U$61") (pin "37") (pinfunction "A0_37") (pintype "bidirectional"))
      (node (ref "U$61") (pin "38") (pinfunction "A1_38") (pintype "bidirectional"))
      (node (ref "U$61") (pin "40") (pinfunction "A3_40") (pintype "bidirectional"))
      (node (ref "U$62") (pin "15") (pinfunction "GND3_15") (pintype "bidirectional"))
      (node (ref "U$62") (pin "9") (pinfunction "GND4_9") (pintype "bidirectional"))
    )
    (net (code "196") (name "GND6") (class "Default")
      (node (ref "C100") (pin "1") (pinfunction "1_1") (pintype "passive"))
      (node (ref "C101") (pin "1") (pinfunction "1_1") (pintype "passive"))
      (node (ref "C102") (pin "1") (pinfunction "1_1") (pintype "passive"))
      (node (ref "C86") (pin "1") (pinfunction "1_1") (pintype "passive"))
      (node (ref "C87") (pin "1") (pinfunction "1_1") (pintype "passive"))
      (node (ref "C88") (pin "1") (pinfunction "1_1") (pintype "passive"))
      (node (ref "C89") (pin "1") (pinfunction "1_1") (pintype "passive"))
      (node (ref "C90") (pin "1") (pinfunction "1_1") (pintype "passive"))
      (node (ref "C91") (pin "1") (pinfunction "1_1") (pintype "passive"))
      (node (ref "C92") (pin "1") (pinfunction "1_1") (pintype "passive"))
      (node (ref "C93") (pin "1") (pinfunction "1_1") (pintype "passive"))
      (node (ref "C94") (pin "1") (pinfunction "1_1") (pintype "passive"))
      (node (ref "C95") (pin "1") (pinfunction "1_1") (pintype "passive"))
      (node (ref "C96") (pin "1") (pinfunction "1_1") (pintype "passive"))
      (node (ref "C97") (pin "1") (pinfunction "1_1") (pintype "passive"))
      (node (ref "C98") (pin "1") (pinfunction "1_1") (pintype "passive"))
      (node (ref "C99") (pin "1") (pinfunction "1_1") (pintype "passive"))
      (node (ref "D88") (pin "A") (pinfunction "A_A") (pintype "passive"))
      (node (ref "R489") (pin "2") (pinfunction "2_2") (pintype "passive"))
      (node (ref "R495") (pin "1") (pinfunction "1_1") (pintype "passive"))
      (node (ref "U$76") (pin "27") (pinfunction "V-_27") (pintype "bidirectional"))
      (node (ref "U$76") (pin "28") (pinfunction "NC_28") (pintype "bidirectional"))
      (node (ref "U$76") (pin "33") (pinfunction "TOS_33") (pintype "bidirectional"))
      (node (ref "U$76") (pin "38") (pinfunction "A1_38") (pintype "bidirectional"))
      (node (ref "U$76") (pin "40") (pinfunction "A3_40") (pintype "bidirectional"))
      (node (ref "U$77") (pin "15") (pinfunction "GND3_15") (pintype "bidirectional"))
      (node (ref "U$77") (pin "9") (pinfunction "GND4_9") (pintype "bidirectional"))
    )
    (net (code "197") (name "GND7") (class "Default")
      (node (ref "C103") (pin "1") (pinfunction "1_1") (pintype "passive"))
      (node (ref "C104") (pin "1") (pinfunction "1_1") (pintype "passive"))
      (node (ref "C105") (pin "1") (pinfunction "1_1") (pintype "passive"))
      (node (ref "C106") (pin "1") (pinfunction "1_1") (pintype "passive"))
      (node (ref "C107") (pin "1") (pinfunction "1_1") (pintype "passive"))
      (node (ref "C108") (pin "1") (pinfunction "1_1") (pintype "passive"))
      (node (ref "C109") (pin "1") (pinfunction "1_1") (pintype "passive"))
      (node (ref "C110") (pin "1") (pinfunction "1_1") (pintype "passive"))
      (node (ref "C111") (pin "1") (pinfunction "1_1") (pintype "passive"))
      (node (ref "C112") (pin "1") (pinfunction "1_1") (pintype "passive"))
      (node (ref "C113") (pin "1") (pinfunction "1_1") (pintype "passive"))
      (node (ref "C114") (pin "1") (pinfunction "1_1") (pintype "passive"))
      (node (ref "C115") (pin "1") (pinfunction "1_1") (pintype "passive"))
      (node (ref "C116") (pin "1") (pinfunction "1_1") (pintype "passive"))
      (node (ref "C117") (pin "1") (pinfunction "1_1") (pintype "passive"))
      (node (ref "C118") (pin "1") (pinfunction "1_1") (pintype "passive"))
      (node (ref "C119") (pin "1") (pinfunction "1_1") (pintype "passive"))
      (node (ref "D103") (pin "A") (pinfunction "A_A") (pintype "passive"))
      (node (ref "R572") (pin "2") (pinfunction "2_2") (pintype "passive"))
      (node (ref "R578") (pin "1") (pinfunction "1_1") (pintype "passive"))
      (node (ref "U$91") (pin "27") (pinfunction "V-_27") (pintype "bidirectional"))
      (node (ref "U$91") (pin "28") (pinfunction "NC_28") (pintype "bidirectional"))
      (node (ref "U$91") (pin "33") (pinfunction "TOS_33") (pintype "bidirectional"))
      (node (ref "U$91") (pin "37") (pinfunction "A0_37") (pintype "bidirectional"))
      (node (ref "U$91") (pin "40") (pinfunction "A3_40") (pintype "bidirectional"))
      (node (ref "U$92") (pin "15") (pinfunction "GND3_15") (pintype "bidirectional"))
      (node (ref "U$92") (pin "9") (pinfunction "GND4_9") (pintype "bidirectional"))
    )
    (net (code "198") (name "GND8") (class "Default")
      (node (ref "C120") (pin "1") (pinfunction "1_1") (pintype "passive"))
      (node (ref "C121") (pin "1") (pinfunction "1_1") (pintype "passive"))
      (node (ref "C122") (pin "1") (pinfunction "1_1") (pintype "passive"))
      (node (ref "C123") (pin "1") (pinfunction "1_1") (pintype "passive"))
      (node (ref "C124") (pin "1") (pinfunction "1_1") (pintype "passive"))
      (node (ref "C125") (pin "1") (pinfunction "1_1") (pintype "passive"))
      (node (ref "C126") (pin "1") (pinfunction "1_1") (pintype "passive"))
      (node (ref "C127") (pin "1") (pinfunction "1_1") (pintype "passive"))
      (node (ref "C128") (pin "1") (pinfunction "1_1") (pintype "passive"))
      (node (ref "C129") (pin "1") (pinfunction "1_1") (pintype "passive"))
      (node (ref "C130") (pin "1") (pinfunction "1_1") (pintype "passive"))
      (node (ref "C131") (pin "1") (pinfunction "1_1") (pintype "passive"))
      (node (ref "C132") (pin "1") (pinfunction "1_1") (pintype "passive"))
      (node (ref "C133") (pin "1") (pinfunction "1_1") (pintype "passive"))
      (node (ref "C134") (pin "1") (pinfunction "1_1") (pintype "passive"))
      (node (ref "C135") (pin "1") (pinfunction "1_1") (pintype "passive"))
      (node (ref "C136") (pin "1") (pinfunction "1_1") (pintype "passive"))
      (node (ref "D118") (pin "A") (pinfunction "A_A") (pintype "passive"))
      (node (ref "R655") (pin "2") (pinfunction "2_2") (pintype "passive"))
      (node (ref "R661") (pin "1") (pinfunction "1_1") (pintype "passive"))
      (node (ref "U$106") (pin "27") (pinfunction "V-_27") (pintype "bidirectional"))
      (node (ref "U$106") (pin "28") (pinfunction "NC_28") (pintype "bidirectional"))
      (node (ref "U$106") (pin "33") (pinfunction "TOS_33") (pintype "bidirectional"))
      (node (ref "U$106") (pin "40") (pinfunction "A3_40") (pintype "bidirectional"))
      (node (ref "U$107") (pin "15") (pinfunction "GND3_15") (pintype "bidirectional"))
      (node (ref "U$107") (pin "9") (pinfunction "GND4_9") (pintype "bidirectional"))
    )
    (net (code "199") (name "GND9") (class "Default")
      (node (ref "C137") (pin "1") (pinfunction "1_1") (pintype "passive"))
      (node (ref "C138") (pin "1") (pinfunction "1_1") (pintype "passive"))
      (node (ref "C139") (pin "1") (pinfunction "1_1") (pintype "passive"))
      (node (ref "C140") (pin "1") (pinfunction "1_1") (pintype "passive"))
      (node (ref "C141") (pin "1") (pinfunction "1_1") (pintype "passive"))
      (node (ref "C142") (pin "1") (pinfunction "1_1") (pintype "passive"))
      (node (ref "C143") (pin "1") (pinfunction "1_1") (pintype "passive"))
      (node (ref "C144") (pin "1") (pinfunction "1_1") (pintype "passive"))
      (node (ref "C145") (pin "1") (pinfunction "1_1") (pintype "passive"))
      (node (ref "C146") (pin "1") (pinfunction "1_1") (pintype "passive"))
      (node (ref "C147") (pin "1") (pinfunction "1_1") (pintype "passive"))
      (node (ref "C148") (pin "1") (pinfunction "1_1") (pintype "passive"))
      (node (ref "C149") (pin "1") (pinfunction "1_1") (pintype "passive"))
      (node (ref "C150") (pin "1") (pinfunction "1_1") (pintype "passive"))
      (node (ref "C151") (pin "1") (pinfunction "1_1") (pintype "passive"))
      (node (ref "C152") (pin "1") (pinfunction "1_1") (pintype "passive"))
      (node (ref "C153") (pin "1") (pinfunction "1_1") (pintype "passive"))
      (node (ref "D133") (pin "A") (pinfunction "A_A") (pintype "passive"))
      (node (ref "R738") (pin "2") (pinfunction "2_2") (pintype "passive"))
      (node (ref "R744") (pin "1") (pinfunction "1_1") (pintype "passive"))
      (node (ref "U$121") (pin "27") (pinfunction "V-_27") (pintype "bidirectional"))
      (node (ref "U$121") (pin "28") (pinfunction "NC_28") (pintype "bidirectional"))
      (node (ref "U$121") (pin "33") (pinfunction "TOS_33") (pintype "bidirectional"))
      (node (ref "U$121") (pin "37") (pinfunction "A0_37") (pintype "bidirectional"))
      (node (ref "U$121") (pin "38") (pinfunction "A1_38") (pintype "bidirectional"))
      (node (ref "U$121") (pin "39") (pinfunction "A2_39") (pintype "bidirectional"))
      (node (ref "U$122") (pin "15") (pinfunction "GND3_15") (pintype "bidirectional"))
      (node (ref "U$122") (pin "9") (pinfunction "GND4_9") (pintype "bidirectional"))
    )
    (net (code "200") (name "GNDA") (class "Default")
      (node (ref "C1") (pin "1") (pinfunction "1_1") (pintype "passive"))
      (node (ref "C10") (pin "1") (pinfunction "1_1") (pintype "passive"))
      (node (ref "C11") (pin "1") (pinfunction "1_1") (pintype "passive"))
      (node (ref "C12") (pin "1") (pinfunction "1_1") (pintype "passive"))
      (node (ref "C13") (pin "1") (pinfunction "1_1") (pintype "passive"))
      (node (ref "C14") (pin "1") (pinfunction "1_1") (pintype "passive"))
      (node (ref "C15") (pin "1") (pinfunction "1_1") (pintype "passive"))
      (node (ref "C16") (pin "1") (pinfunction "1_1") (pintype "passive"))
      (node (ref "C17") (pin "1") (pinfunction "1_1") (pintype "passive"))
      (node (ref "C2") (pin "1") (pinfunction "1_1") (pintype "passive"))
      (node (ref "C3") (pin "1") (pinfunction "1_1") (pintype "passive"))
      (node (ref "C4") (pin "1") (pinfunction "1_1") (pintype "passive"))
      (node (ref "C5") (pin "1") (pinfunction "1_1") (pintype "passive"))
      (node (ref "C6") (pin "1") (pinfunction "1_1") (pintype "passive"))
      (node (ref "C7") (pin "1") (pinfunction "1_1") (pintype "passive"))
      (node (ref "C8") (pin "1") (pinfunction "1_1") (pintype "passive"))
      (node (ref "C9") (pin "1") (pinfunction "1_1") (pintype "passive"))
      (node (ref "D13") (pin "A") (pinfunction "A_A") (pintype "passive"))
      (node (ref "R76") (pin "2") (pinfunction "2_2") (pintype "passive"))
      (node (ref "R83") (pin "1") (pinfunction "1_1") (pintype "passive"))
      (node (ref "U$1") (pin "27") (pinfunction "V-_27") (pintype "bidirectional"))
      (node (ref "U$1") (pin "28") (pinfunction "NC_28") (pintype "bidirectional"))
      (node (ref "U$1") (pin "33") (pinfunction "TOS_33") (pintype "bidirectional"))
      (node (ref "U$1") (pin "37") (pinfunction "A0_37") (pintype "bidirectional"))
      (node (ref "U$1") (pin "38") (pinfunction "A1_38") (pintype "bidirectional"))
      (node (ref "U$1") (pin "39") (pinfunction "A2_39") (pintype "bidirectional"))
      (node (ref "U$1") (pin "40") (pinfunction "A3_40") (pintype "bidirectional"))
      (node (ref "U$2") (pin "15") (pinfunction "GND3_15") (pintype "bidirectional"))
      (node (ref "U$2") (pin "9") (pinfunction "GND4_9") (pintype "bidirectional"))
    )
    (net (code "201") (name "Net-(D2-PadA)") (class "Default")
      (node (ref "D2") (pin "A") (pinfunction "A_A") (pintype "passive"))
      (node (ref "R12") (pin "1") (pinfunction "1_1") (pintype "passive"))
      (node (ref "R74") (pin "2") (pinfunction "2_2") (pintype "passive"))
      (node (ref "R9") (pin "1") (pinfunction "1_1") (pintype "passive"))
    )
    (net (code "202") (name "Net-(D14-PadC)") (class "Default")
      (node (ref "D14") (pin "C") (pinfunction "C_C") (pintype "passive"))
      (node (ref "R79") (pin "2") (pinfunction "2_2") (pintype "passive"))
      (node (ref "R81") (pin "1") (pinfunction "1_1") (pintype "passive"))
      (node (ref "R82") (pin "1") (pinfunction "1_1") (pintype "passive"))
    )
    (net (code "203") (name "Net-(D17-PadA)") (class "Default")
      (node (ref "D17") (pin "A") (pinfunction "A_A") (pintype "passive"))
      (node (ref "R159") (pin "2") (pinfunction "2_2") (pintype "passive"))
      (node (ref "R94") (pin "1") (pinfunction "1_1") (pintype "passive"))
      (node (ref "R97") (pin "1") (pinfunction "1_1") (pintype "passive"))
    )
    (net (code "204") (name "Net-(D29-PadC)") (class "Default")
      (node (ref "D29") (pin "C") (pinfunction "C_C") (pintype "passive"))
      (node (ref "R164") (pin "2") (pinfunction "2_2") (pintype "passive"))
      (node (ref "R166") (pin "1") (pinfunction "1_1") (pintype "passive"))
      (node (ref "R167") (pin "1") (pinfunction "1_1") (pintype "passive"))
    )
    (net (code "205") (name "Net-(D30-PadA)") (class "Default")
      (node (ref "D30") (pin "A") (pinfunction "A_A") (pintype "passive"))
      (node (ref "R188") (pin "1") (pinfunction "1_1") (pintype "passive"))
      (node (ref "R191") (pin "1") (pinfunction "1_1") (pintype "passive"))
      (node (ref "R253") (pin "2") (pinfunction "2_2") (pintype "passive"))
    )
    (net (code "206") (name "Net-(D36-PadA)") (class "Default")
      (node (ref "D36") (pin "A") (pinfunction "A_A") (pintype "passive"))
      (node (ref "R173") (pin "1") (pinfunction "1_1") (pintype "passive"))
      (node (ref "R176") (pin "1") (pinfunction "1_1") (pintype "passive"))
      (node (ref "R321") (pin "2") (pinfunction "2_2") (pintype "passive"))
    )
    (net (code "207") (name "Net-(D46-PadC)") (class "Default")
      (node (ref "D46") (pin "C") (pinfunction "C_C") (pintype "passive"))
      (node (ref "R258") (pin "2") (pinfunction "2_2") (pintype "passive"))
      (node (ref "R260") (pin "1") (pinfunction "1_1") (pintype "passive"))
      (node (ref "R261") (pin "1") (pinfunction "1_1") (pintype "passive"))
    )
    (net (code "208") (name "Net-(D59-PadC)") (class "Default")
      (node (ref "D59") (pin "C") (pinfunction "C_C") (pintype "passive"))
      (node (ref "R325") (pin "2") (pinfunction "2_2") (pintype "passive"))
      (node (ref "R327") (pin "1") (pinfunction "1_1") (pintype "passive"))
      (node (ref "R328") (pin "1") (pinfunction "1_1") (pintype "passive"))
    )
    (net (code "209") (name "Net-(D62-PadA)") (class "Default")
      (node (ref "D62") (pin "A") (pinfunction "A_A") (pintype "passive"))
      (node (ref "R339") (pin "1") (pinfunction "1_1") (pintype "passive"))
      (node (ref "R342") (pin "1") (pinfunction "1_1") (pintype "passive"))
      (node (ref "R404") (pin "2") (pinfunction "2_2") (pintype "passive"))
    )
    (net (code "210") (name "Net-(D74-PadC)") (class "Default")
      (node (ref "D74") (pin "C") (pinfunction "C_C") (pintype "passive"))
      (node (ref "R408") (pin "2") (pinfunction "2_2") (pintype "passive"))
      (node (ref "R410") (pin "1") (pinfunction "1_1") (pintype "passive"))
      (node (ref "R411") (pin "1") (pinfunction "1_1") (pintype "passive"))
    )
    (net (code "211") (name "Net-(D77-PadA)") (class "Default")
      (node (ref "D77") (pin "A") (pinfunction "A_A") (pintype "passive"))
      (node (ref "R422") (pin "1") (pinfunction "1_1") (pintype "passive"))
      (node (ref "R425") (pin "1") (pinfunction "1_1") (pintype "passive"))
      (node (ref "R487") (pin "2") (pinfunction "2_2") (pintype "passive"))
    )
    (net (code "212") (name "Net-(D89-PadC)") (class "Default")
      (node (ref "D89") (pin "C") (pinfunction "C_C") (pintype "passive"))
      (node (ref "R491") (pin "2") (pinfunction "2_2") (pintype "passive"))
      (node (ref "R493") (pin "1") (pinfunction "1_1") (pintype "passive"))
      (node (ref "R494") (pin "1") (pinfunction "1_1") (pintype "passive"))
    )
    (net (code "213") (name "Net-(D92-PadA)") (class "Default")
      (node (ref "D92") (pin "A") (pinfunction "A_A") (pintype "passive"))
      (node (ref "R505") (pin "1") (pinfunction "1_1") (pintype "passive"))
      (node (ref "R508") (pin "1") (pinfunction "1_1") (pintype "passive"))
      (node (ref "R570") (pin "2") (pinfunction "2_2") (pintype "passive"))
    )
    (net (code "214") (name "Net-(D104-PadC)") (class "Default")
      (node (ref "D104") (pin "C") (pinfunction "C_C") (pintype "passive"))
      (node (ref "R574") (pin "2") (pinfunction "2_2") (pintype "passive"))
      (node (ref "R576") (pin "1") (pinfunction "1_1") (pintype "passive"))
      (node (ref "R577") (pin "1") (pinfunction "1_1") (pintype "passive"))
    )
    (net (code "215") (name "Net-(D107-PadA)") (class "Default")
      (node (ref "D107") (pin "A") (pinfunction "A_A") (pintype "passive"))
      (node (ref "R588") (pin "1") (pinfunction "1_1") (pintype "passive"))
      (node (ref "R591") (pin "1") (pinfunction "1_1") (pintype "passive"))
      (node (ref "R653") (pin "2") (pinfunction "2_2") (pintype "passive"))
    )
    (net (code "216") (name "Net-(D119-PadC)") (class "Default")
      (node (ref "D119") (pin "C") (pinfunction "C_C") (pintype "passive"))
      (node (ref "R657") (pin "2") (pinfunction "2_2") (pintype "passive"))
      (node (ref "R659") (pin "1") (pinfunction "1_1") (pintype "passive"))
      (node (ref "R660") (pin "1") (pinfunction "1_1") (pintype "passive"))
    )
    (net (code "217") (name "Net-(D122-PadA)") (class "Default")
      (node (ref "D122") (pin "A") (pinfunction "A_A") (pintype "passive"))
      (node (ref "R671") (pin "1") (pinfunction "1_1") (pintype "passive"))
      (node (ref "R674") (pin "1") (pinfunction "1_1") (pintype "passive"))
      (node (ref "R736") (pin "2") (pinfunction "2_2") (pintype "passive"))
    )
    (net (code "218") (name "Net-(D134-PadC)") (class "Default")
      (node (ref "D134") (pin "C") (pinfunction "C_C") (pintype "passive"))
      (node (ref "R740") (pin "2") (pinfunction "2_2") (pintype "passive"))
      (node (ref "R742") (pin "1") (pinfunction "1_1") (pintype "passive"))
      (node (ref "R743") (pin "1") (pinfunction "1_1") (pintype "passive"))
    )
    (net (code "219") (name "Net-(R1-Pad1)") (class "Default")
      (node (ref "R1") (pin "1") (pinfunction "1_1") (pintype "passive"))
      (node (ref "R7") (pin "2") (pinfunction "2_2") (pintype "passive"))
    )
    (net (code "220") (name "Net-(R7-Pad1)") (class "Default")
      (node (ref "R7") (pin "1") (pinfunction "1_1") (pintype "passive"))
      (node (ref "S") (pin "3") (pinfunction "3_3") (pintype "passive"))
    )
    (net (code "221") (name "Net-(R13-Pad1)") (class "Default")
      (node (ref "R13") (pin "1") (pinfunction "1_1") (pintype "passive"))
      (node (ref "S") (pin "2") (pinfunction "2_2") (pintype "passive"))
    )
    (net (code "222") (name "Net-(R13-Pad2)") (class "Default")
      (node (ref "R13") (pin "2") (pinfunction "2_2") (pintype "passive"))
      (node (ref "R8") (pin "1") (pinfunction "1_1") (pintype "passive"))
    )
    (net (code "223") (name "Net-(R14-Pad1)") (class "Default")
      (node (ref "R14") (pin "1") (pinfunction "1_1") (pintype "passive"))
      (node (ref "R19") (pin "2") (pinfunction "2_2") (pintype "passive"))
    )
    (net (code "224") (name "Net-(R19-Pad1)") (class "Default")
      (node (ref "R19") (pin "1") (pinfunction "1_1") (pintype "passive"))
      (node (ref "S") (pin "4") (pinfunction "4_4") (pintype "passive"))
    )
    (net (code "225") (name "Net-(R20-Pad1)") (class "Default")
      (node (ref "R20") (pin "1") (pinfunction "1_1") (pintype "passive"))
      (node (ref "R25") (pin "2") (pinfunction "2_2") (pintype "passive"))
    )
    (net (code "226") (name "Net-(R25-Pad1)") (class "Default")
      (node (ref "R25") (pin "1") (pinfunction "1_1") (pintype "passive"))
      (node (ref "S") (pin "5") (pinfunction "5_5") (pintype "passive"))
    )
    (net (code "227") (name "Net-(R26-Pad1)") (class "Default")
      (node (ref "R26") (pin "1") (pinfunction "1_1") (pintype "passive"))
      (node (ref "R31") (pin "2") (pinfunction "2_2") (pintype "passive"))
    )
    (net (code "228") (name "Net-(R31-Pad1)") (class "Default")
      (node (ref "R31") (pin "1") (pinfunction "1_1") (pintype "passive"))
      (node (ref "S") (pin "6") (pinfunction "6_6") (pintype "passive"))
    )
    (net (code "229") (name "Net-(R32-Pad1)") (class "Default")
      (node (ref "R32") (pin "1") (pinfunction "1_1") (pintype "passive"))
      (node (ref "R37") (pin "2") (pinfunction "2_2") (pintype "passive"))
    )
    (net (code "230") (name "Net-(R37-Pad1)") (class "Default")
      (node (ref "R37") (pin "1") (pinfunction "1_1") (pintype "passive"))
      (node (ref "S") (pin "7") (pinfunction "7_7") (pintype "passive"))
    )
    (net (code "231") (name "Net-(R38-Pad1)") (class "Default")
      (node (ref "R38") (pin "1") (pinfunction "1_1") (pintype "passive"))
      (node (ref "R43") (pin "2") (pinfunction "2_2") (pintype "passive"))
    )
    (net (code "232") (name "Net-(R43-Pad1)") (class "Default")
      (node (ref "R43") (pin "1") (pinfunction "1_1") (pintype "passive"))
      (node (ref "S") (pin "9") (pinfunction "9_9") (pintype "passive"))
    )
    (net (code "233") (name "Net-(R44-Pad1)") (class "Default")
      (node (ref "R44") (pin "1") (pinfunction "1_1") (pintype "passive"))
      (node (ref "R49") (pin "2") (pinfunction "2_2") (pintype "passive"))
    )
    (net (code "234") (name "Net-(R49-Pad1)") (class "Default")
      (node (ref "R49") (pin "1") (pinfunction "1_1") (pintype "passive"))
      (node (ref "S") (pin "8") (pinfunction "8_8") (pintype "passive"))
    )
    (net (code "235") (name "Net-(R50-Pad1)") (class "Default")
      (node (ref "R50") (pin "1") (pinfunction "1_1") (pintype "passive"))
      (node (ref "R55") (pin "2") (pinfunction "2_2") (pintype "passive"))
    )
    (net (code "236") (name "Net-(R55-Pad1)") (class "Default")
      (node (ref "R55") (pin "1") (pinfunction "1_1") (pintype "passive"))
      (node (ref "S") (pin "10") (pinfunction "10_10") (pintype "passive"))
    )
    (net (code "237") (name "Net-(R56-Pad1)") (class "Default")
      (node (ref "R56") (pin "1") (pinfunction "1_1") (pintype "passive"))
      (node (ref "R61") (pin "2") (pinfunction "2_2") (pintype "passive"))
    )
    (net (code "238") (name "Net-(R61-Pad1)") (class "Default")
      (node (ref "R61") (pin "1") (pinfunction "1_1") (pintype "passive"))
      (node (ref "S") (pin "11") (pinfunction "11_11") (pintype "passive"))
    )
    (net (code "239") (name "Net-(R62-Pad1)") (class "Default")
      (node (ref "R62") (pin "1") (pinfunction "1_1") (pintype "passive"))
      (node (ref "R67") (pin "2") (pinfunction "2_2") (pintype "passive"))
    )
    (net (code "240") (name "Net-(R67-Pad1)") (class "Default")
      (node (ref "R67") (pin "1") (pinfunction "1_1") (pintype "passive"))
      (node (ref "S") (pin "12") (pinfunction "12_12") (pintype "passive"))
    )
    (net (code "241") (name "Net-(R68-Pad1)") (class "Default")
      (node (ref "R68") (pin "1") (pinfunction "1_1") (pintype "passive"))
      (node (ref "R73") (pin "2") (pinfunction "2_2") (pintype "passive"))
    )
    (net (code "242") (name "Net-(R73-Pad1)") (class "Default")
      (node (ref "R73") (pin "1") (pinfunction "1_1") (pintype "passive"))
      (node (ref "R80") (pin "1") (pinfunction "1_1") (pintype "passive"))
      (node (ref "S") (pin "13") (pinfunction "13_13") (pintype "passive"))
    )
    (net (code "243") (name "Net-(R74-Pad1)") (class "Default")
      (node (ref "R74") (pin "1") (pinfunction "1_1") (pintype "passive"))
      (node (ref "R75") (pin "2") (pinfunction "2_2") (pintype "passive"))
    )
    (net (code "244") (name "Net-(R75-Pad1)") (class "Default")
      (node (ref "R75") (pin "1") (pinfunction "1_1") (pintype "passive"))
      (node (ref "R77") (pin "1") (pinfunction "1_1") (pintype "passive"))
      (node (ref "U$15") (pin "1") (pinfunction "1_1") (pintype "passive"))
    )
    (net (code "245") (name "Net-(R76-Pad1)") (class "Default")
      (node (ref "R76") (pin "1") (pinfunction "1_1") (pintype "passive"))
      (node (ref "R77") (pin "2") (pinfunction "2_2") (pintype "passive"))
    )
    (net (code "246") (name "Net-(R79-Pad1)") (class "Default")
      (node (ref "R79") (pin "1") (pinfunction "1_1") (pintype "passive"))
      (node (ref "R80") (pin "2") (pinfunction "2_2") (pintype "passive"))
    )
    (net (code "247") (name "Net-(R93-Pad1)") (class "Default")
      (node (ref "R93") (pin "1") (pinfunction "1_1") (pintype "passive"))
      (node (ref "R98") (pin "2") (pinfunction "2_2") (pintype "passive"))
    )
    (net (code "248") (name "Net-(R104-Pad2)") (class "Default")
      (node (ref "R104") (pin "2") (pinfunction "2_2") (pintype "passive"))
      (node (ref "R99") (pin "1") (pinfunction "1_1") (pintype "passive"))
    )
    (net (code "249") (name "Net-(R105-Pad1)") (class "Default")
      (node (ref "R105") (pin "1") (pinfunction "1_1") (pintype "passive"))
      (node (ref "R110") (pin "2") (pinfunction "2_2") (pintype "passive"))
    )
    (net (code "250") (name "Net-(R111-Pad1)") (class "Default")
      (node (ref "R111") (pin "1") (pinfunction "1_1") (pintype "passive"))
      (node (ref "R116") (pin "2") (pinfunction "2_2") (pintype "passive"))
    )
    (net (code "251") (name "Net-(R117-Pad1)") (class "Default")
      (node (ref "R117") (pin "1") (pinfunction "1_1") (pintype "passive"))
      (node (ref "R122") (pin "2") (pinfunction "2_2") (pintype "passive"))
    )
    (net (code "252") (name "Net-(R123-Pad1)") (class "Default")
      (node (ref "R123") (pin "1") (pinfunction "1_1") (pintype "passive"))
      (node (ref "R128") (pin "2") (pinfunction "2_2") (pintype "passive"))
    )
    (net (code "253") (name "Net-(R129-Pad1)") (class "Default")
      (node (ref "R129") (pin "1") (pinfunction "1_1") (pintype "passive"))
      (node (ref "R134") (pin "2") (pinfunction "2_2") (pintype "passive"))
    )
    (net (code "254") (name "Net-(R135-Pad1)") (class "Default")
      (node (ref "R135") (pin "1") (pinfunction "1_1") (pintype "passive"))
      (node (ref "R140") (pin "2") (pinfunction "2_2") (pintype "passive"))
    )
    (net (code "255") (name "Net-(R141-Pad1)") (class "Default")
      (node (ref "R141") (pin "1") (pinfunction "1_1") (pintype "passive"))
      (node (ref "R146") (pin "2") (pinfunction "2_2") (pintype "passive"))
    )
    (net (code "256") (name "Net-(R147-Pad1)") (class "Default")
      (node (ref "R147") (pin "1") (pinfunction "1_1") (pintype "passive"))
      (node (ref "R152") (pin "2") (pinfunction "2_2") (pintype "passive"))
    )
    (net (code "257") (name "Net-(R153-Pad1)") (class "Default")
      (node (ref "R153") (pin "1") (pinfunction "1_1") (pintype "passive"))
      (node (ref "R158") (pin "2") (pinfunction "2_2") (pintype "passive"))
    )
    (net (code "258") (name "Net-(R159-Pad1)") (class "Default")
      (node (ref "R159") (pin "1") (pinfunction "1_1") (pintype "passive"))
      (node (ref "R160") (pin "2") (pinfunction "2_2") (pintype "passive"))
    )
    (net (code "259") (name "Net-(R160-Pad1)") (class "Default")
      (node (ref "R160") (pin "1") (pinfunction "1_1") (pintype "passive"))
      (node (ref "R162") (pin "1") (pinfunction "1_1") (pintype "passive"))
      (node (ref "U$30") (pin "1") (pinfunction "1_1") (pintype "passive"))
    )
    (net (code "260") (name "Net-(R161-Pad1)") (class "Default")
      (node (ref "R161") (pin "1") (pinfunction "1_1") (pintype "passive"))
      (node (ref "R162") (pin "2") (pinfunction "2_2") (pintype "passive"))
    )
    (net (code "261") (name "Net-(R163-Pad1)") (class "Default")
      (node (ref "R163") (pin "1") (pinfunction "1_1") (pintype "passive"))
      (node (ref "S1") (pin "3") (pinfunction "3_3") (pintype "passive"))
    )
    (net (code "262") (name "Net-(R163-Pad2)") (class "Default")
      (node (ref "R163") (pin "2") (pinfunction "2_2") (pintype "passive"))
      (node (ref "R332") (pin "1") (pinfunction "1_1") (pintype "passive"))
    )
    (net (code "263") (name "Net-(R164-Pad1)") (class "Default")
      (node (ref "R164") (pin "1") (pinfunction "1_1") (pintype "passive"))
      (node (ref "R165") (pin "2") (pinfunction "2_2") (pintype "passive"))
    )
    (net (code "264") (name "Net-(R171-Pad1)") (class "Default")
      (node (ref "R171") (pin "1") (pinfunction "1_1") (pintype "passive"))
      (node (ref "R177") (pin "2") (pinfunction "2_2") (pintype "passive"))
    )
    (net (code "265") (name "Net-(R172-Pad1)") (class "Default")
      (node (ref "R172") (pin "1") (pinfunction "1_1") (pintype "passive"))
      (node (ref "R92") (pin "2") (pinfunction "2_2") (pintype "passive"))
    )
    (net (code "266") (name "Net-(R177-Pad1)") (class "Default")
      (node (ref "R177") (pin "1") (pinfunction "1_1") (pintype "passive"))
      (node (ref "S1") (pin "2") (pinfunction "2_2") (pintype "passive"))
    )
    (net (code "267") (name "Net-(R178-Pad1)") (class "Default")
      (node (ref "R178") (pin "1") (pinfunction "1_1") (pintype "passive"))
      (node (ref "R266") (pin "2") (pinfunction "2_2") (pintype "passive"))
    )
    (net (code "268") (name "Net-(R186-Pad2)") (class "Default")
      (node (ref "R186") (pin "2") (pinfunction "2_2") (pintype "passive"))
      (node (ref "R265") (pin "1") (pinfunction "1_1") (pintype "passive"))
    )
    (net (code "269") (name "Net-(R187-Pad1)") (class "Default")
      (node (ref "R187") (pin "1") (pinfunction "1_1") (pintype "passive"))
      (node (ref "R192") (pin "2") (pinfunction "2_2") (pintype "passive"))
    )
    (net (code "270") (name "Net-(R193-Pad1)") (class "Default")
      (node (ref "R193") (pin "1") (pinfunction "1_1") (pintype "passive"))
      (node (ref "R198") (pin "2") (pinfunction "2_2") (pintype "passive"))
    )
    (net (code "271") (name "Net-(R199-Pad1)") (class "Default")
      (node (ref "R199") (pin "1") (pinfunction "1_1") (pintype "passive"))
      (node (ref "R204") (pin "2") (pinfunction "2_2") (pintype "passive"))
    )
    (net (code "272") (name "Net-(R205-Pad1)") (class "Default")
      (node (ref "R205") (pin "1") (pinfunction "1_1") (pintype "passive"))
      (node (ref "R210") (pin "2") (pinfunction "2_2") (pintype "passive"))
    )
    (net (code "273") (name "Net-(R211-Pad1)") (class "Default")
      (node (ref "R211") (pin "1") (pinfunction "1_1") (pintype "passive"))
      (node (ref "R216") (pin "2") (pinfunction "2_2") (pintype "passive"))
    )
    (net (code "274") (name "Net-(R217-Pad1)") (class "Default")
      (node (ref "R217") (pin "1") (pinfunction "1_1") (pintype "passive"))
      (node (ref "R222") (pin "2") (pinfunction "2_2") (pintype "passive"))
    )
    (net (code "275") (name "Net-(R223-Pad1)") (class "Default")
      (node (ref "R223") (pin "1") (pinfunction "1_1") (pintype "passive"))
      (node (ref "R228") (pin "2") (pinfunction "2_2") (pintype "passive"))
    )
    (net (code "276") (name "Net-(R229-Pad1)") (class "Default")
      (node (ref "R229") (pin "1") (pinfunction "1_1") (pintype "passive"))
      (node (ref "R234") (pin "2") (pinfunction "2_2") (pintype "passive"))
    )
    (net (code "277") (name "Net-(R235-Pad1)") (class "Default")
      (node (ref "R235") (pin "1") (pinfunction "1_1") (pintype "passive"))
      (node (ref "R240") (pin "2") (pinfunction "2_2") (pintype "passive"))
    )
    (net (code "278") (name "Net-(R241-Pad1)") (class "Default")
      (node (ref "R241") (pin "1") (pinfunction "1_1") (pintype "passive"))
      (node (ref "R246") (pin "2") (pinfunction "2_2") (pintype "passive"))
    )
    (net (code "279") (name "Net-(R247-Pad1)") (class "Default")
      (node (ref "R247") (pin "1") (pinfunction "1_1") (pintype "passive"))
      (node (ref "R252") (pin "2") (pinfunction "2_2") (pintype "passive"))
    )
    (net (code "280") (name "Net-(R253-Pad1)") (class "Default")
      (node (ref "R253") (pin "1") (pinfunction "1_1") (pintype "passive"))
      (node (ref "R254") (pin "2") (pinfunction "2_2") (pintype "passive"))
    )
    (net (code "281") (name "Net-(R254-Pad1)") (class "Default")
      (node (ref "R254") (pin "1") (pinfunction "1_1") (pintype "passive"))
      (node (ref "R256") (pin "1") (pinfunction "1_1") (pintype "passive"))
      (node (ref "U$50") (pin "1") (pinfunction "1_1") (pintype "passive"))
    )
    (net (code "282") (name "Net-(R255-Pad1)") (class "Default")
      (node (ref "R255") (pin "1") (pinfunction "1_1") (pintype "passive"))
      (node (ref "R256") (pin "2") (pinfunction "2_2") (pintype "passive"))
    )
    (net (code "283") (name "Net-(R258-Pad1)") (class "Default")
      (node (ref "R258") (pin "1") (pinfunction "1_1") (pintype "passive"))
      (node (ref "R259") (pin "2") (pinfunction "2_2") (pintype "passive"))
    )
    (net (code "284") (name "Net-(R266-Pad1)") (class "Default")
      (node (ref "R266") (pin "1") (pinfunction "1_1") (pintype "passive"))
      (node (ref "S1") (pin "4") (pinfunction "4_4") (pintype "passive"))
    )
    (net (code "285") (name "Net-(R267-Pad1)") (class "Default")
      (node (ref "R267") (pin "1") (pinfunction "1_1") (pintype "passive"))
      (node (ref "R272") (pin "2") (pinfunction "2_2") (pintype "passive"))
    )
    (net (code "286") (name "Net-(R272-Pad1)") (class "Default")
      (node (ref "R272") (pin "1") (pinfunction "1_1") (pintype "passive"))
      (node (ref "S1") (pin "5") (pinfunction "5_5") (pintype "passive"))
    )
    (net (code "287") (name "Net-(R273-Pad1)") (class "Default")
      (node (ref "R273") (pin "1") (pinfunction "1_1") (pintype "passive"))
      (node (ref "R278") (pin "2") (pinfunction "2_2") (pintype "passive"))
    )
    (net (code "288") (name "Net-(R278-Pad1)") (class "Default")
      (node (ref "R278") (pin "1") (pinfunction "1_1") (pintype "passive"))
      (node (ref "S1") (pin "6") (pinfunction "6_6") (pintype "passive"))
    )
    (net (code "289") (name "Net-(R279-Pad1)") (class "Default")
      (node (ref "R279") (pin "1") (pinfunction "1_1") (pintype "passive"))
      (node (ref "R284") (pin "2") (pinfunction "2_2") (pintype "passive"))
    )
    (net (code "290") (name "Net-(R284-Pad1)") (class "Default")
      (node (ref "R284") (pin "1") (pinfunction "1_1") (pintype "passive"))
      (node (ref "S1") (pin "7") (pinfunction "7_7") (pintype "passive"))
    )
    (net (code "291") (name "Net-(R285-Pad1)") (class "Default")
      (node (ref "R285") (pin "1") (pinfunction "1_1") (pintype "passive"))
      (node (ref "R290") (pin "2") (pinfunction "2_2") (pintype "passive"))
    )
    (net (code "292") (name "Net-(R290-Pad1)") (class "Default")
      (node (ref "R290") (pin "1") (pinfunction "1_1") (pintype "passive"))
      (node (ref "S1") (pin "9") (pinfunction "9_9") (pintype "passive"))
    )
    (net (code "293") (name "Net-(R291-Pad1)") (class "Default")
      (node (ref "R291") (pin "1") (pinfunction "1_1") (pintype "passive"))
      (node (ref "R296") (pin "2") (pinfunction "2_2") (pintype "passive"))
    )
    (net (code "294") (name "Net-(R296-Pad1)") (class "Default")
      (node (ref "R296") (pin "1") (pinfunction "1_1") (pintype "passive"))
      (node (ref "S1") (pin "8") (pinfunction "8_8") (pintype "passive"))
    )
    (net (code "295") (name "Net-(R297-Pad1)") (class "Default")
      (node (ref "R297") (pin "1") (pinfunction "1_1") (pintype "passive"))
      (node (ref "R302") (pin "2") (pinfunction "2_2") (pintype "passive"))
    )
    (net (code "296") (name "Net-(R302-Pad1)") (class "Default")
      (node (ref "R302") (pin "1") (pinfunction "1_1") (pintype "passive"))
      (node (ref "S1") (pin "10") (pinfunction "10_10") (pintype "passive"))
    )
    (net (code "297") (name "Net-(R303-Pad1)") (class "Default")
      (node (ref "R303") (pin "1") (pinfunction "1_1") (pintype "passive"))
      (node (ref "R308") (pin "2") (pinfunction "2_2") (pintype "passive"))
    )
    (net (code "298") (name "Net-(R308-Pad1)") (class "Default")
      (node (ref "R308") (pin "1") (pinfunction "1_1") (pintype "passive"))
      (node (ref "S1") (pin "11") (pinfunction "11_11") (pintype "passive"))
    )
    (net (code "299") (name "Net-(R309-Pad1)") (class "Default")
      (node (ref "R309") (pin "1") (pinfunction "1_1") (pintype "passive"))
      (node (ref "R314") (pin "2") (pinfunction "2_2") (pintype "passive"))
    )
    (net (code "300") (name "Net-(R314-Pad1)") (class "Default")
      (node (ref "R314") (pin "1") (pinfunction "1_1") (pintype "passive"))
      (node (ref "S1") (pin "12") (pinfunction "12_12") (pintype "passive"))
    )
    (net (code "301") (name "Net-(R315-Pad1)") (class "Default")
      (node (ref "R315") (pin "1") (pinfunction "1_1") (pintype "passive"))
      (node (ref "R320") (pin "2") (pinfunction "2_2") (pintype "passive"))
    )
    (net (code "302") (name "Net-(R320-Pad1)") (class "Default")
      (node (ref "R320") (pin "1") (pinfunction "1_1") (pintype "passive"))
      (node (ref "R326") (pin "1") (pinfunction "1_1") (pintype "passive"))
      (node (ref "S1") (pin "13") (pinfunction "13_13") (pintype "passive"))
    )
    (net (code "303") (name "Net-(R321-Pad1)") (class "Default")
      (node (ref "R321") (pin "1") (pinfunction "1_1") (pintype "passive"))
      (node (ref "R322") (pin "2") (pinfunction "2_2") (pintype "passive"))
    )
    (net (code "304") (name "Net-(R322-Pad1)") (class "Default")
      (node (ref "R322") (pin "1") (pinfunction "1_1") (pintype "passive"))
      (node (ref "R324") (pin "1") (pinfunction "1_1") (pintype "passive"))
      (node (ref "U$60") (pin "1") (pinfunction "1_1") (pintype "passive"))
    )
    (net (code "305") (name "Net-(R323-Pad1)") (class "Default")
      (node (ref "R323") (pin "1") (pinfunction "1_1") (pintype "passive"))
      (node (ref "R324") (pin "2") (pinfunction "2_2") (pintype "passive"))
    )
    (net (code "306") (name "Net-(R325-Pad1)") (class "Default")
      (node (ref "R325") (pin "1") (pinfunction "1_1") (pintype "passive"))
      (node (ref "R326") (pin "2") (pinfunction "2_2") (pintype "passive"))
    )
    (net (code "307") (name "Net-(R337-Pad2)") (class "Default")
      (node (ref "R337") (pin "2") (pinfunction "2_2") (pintype "passive"))
      (node (ref "R415") (pin "1") (pinfunction "1_1") (pintype "passive"))
    )
    (net (code "308") (name "Net-(R338-Pad1)") (class "Default")
      (node (ref "R338") (pin "1") (pinfunction "1_1") (pintype "passive"))
      (node (ref "R343") (pin "2") (pinfunction "2_2") (pintype "passive"))
    )
    (net (code "309") (name "Net-(R344-Pad1)") (class "Default")
      (node (ref "R344") (pin "1") (pinfunction "1_1") (pintype "passive"))
      (node (ref "R349") (pin "2") (pinfunction "2_2") (pintype "passive"))
    )
    (net (code "310") (name "Net-(R350-Pad1)") (class "Default")
      (node (ref "R350") (pin "1") (pinfunction "1_1") (pintype "passive"))
      (node (ref "R355") (pin "2") (pinfunction "2_2") (pintype "passive"))
    )
    (net (code "311") (name "Net-(R356-Pad1)") (class "Default")
      (node (ref "R356") (pin "1") (pinfunction "1_1") (pintype "passive"))
      (node (ref "R361") (pin "2") (pinfunction "2_2") (pintype "passive"))
    )
    (net (code "312") (name "Net-(R362-Pad1)") (class "Default")
      (node (ref "R362") (pin "1") (pinfunction "1_1") (pintype "passive"))
      (node (ref "R367") (pin "2") (pinfunction "2_2") (pintype "passive"))
    )
    (net (code "313") (name "Net-(R368-Pad1)") (class "Default")
      (node (ref "R368") (pin "1") (pinfunction "1_1") (pintype "passive"))
      (node (ref "R373") (pin "2") (pinfunction "2_2") (pintype "passive"))
    )
    (net (code "314") (name "Net-(R374-Pad1)") (class "Default")
      (node (ref "R374") (pin "1") (pinfunction "1_1") (pintype "passive"))
      (node (ref "R379") (pin "2") (pinfunction "2_2") (pintype "passive"))
    )
    (net (code "315") (name "Net-(R380-Pad1)") (class "Default")
      (node (ref "R380") (pin "1") (pinfunction "1_1") (pintype "passive"))
      (node (ref "R385") (pin "2") (pinfunction "2_2") (pintype "passive"))
    )
    (net (code "316") (name "Net-(R386-Pad1)") (class "Default")
      (node (ref "R386") (pin "1") (pinfunction "1_1") (pintype "passive"))
      (node (ref "R391") (pin "2") (pinfunction "2_2") (pintype "passive"))
    )
    (net (code "317") (name "Net-(R392-Pad1)") (class "Default")
      (node (ref "R392") (pin "1") (pinfunction "1_1") (pintype "passive"))
      (node (ref "R397") (pin "2") (pinfunction "2_2") (pintype "passive"))
    )
    (net (code "318") (name "Net-(R398-Pad1)") (class "Default")
      (node (ref "R398") (pin "1") (pinfunction "1_1") (pintype "passive"))
      (node (ref "R403") (pin "2") (pinfunction "2_2") (pintype "passive"))
    )
    (net (code "319") (name "Net-(R404-Pad1)") (class "Default")
      (node (ref "R404") (pin "1") (pinfunction "1_1") (pintype "passive"))
      (node (ref "R405") (pin "2") (pinfunction "2_2") (pintype "passive"))
    )
    (net (code "320") (name "Net-(R405-Pad1)") (class "Default")
      (node (ref "R405") (pin "1") (pinfunction "1_1") (pintype "passive"))
      (node (ref "R407") (pin "1") (pinfunction "1_1") (pintype "passive"))
      (node (ref "U$75") (pin "1") (pinfunction "1_1") (pintype "passive"))
    )
    (net (code "321") (name "Net-(R406-Pad1)") (class "Default")
      (node (ref "R406") (pin "1") (pinfunction "1_1") (pintype "passive"))
      (node (ref "R407") (pin "2") (pinfunction "2_2") (pintype "passive"))
    )
    (net (code "322") (name "Net-(R408-Pad1)") (class "Default")
      (node (ref "R408") (pin "1") (pinfunction "1_1") (pintype "passive"))
      (node (ref "R409") (pin "2") (pinfunction "2_2") (pintype "passive"))
    )
    (net (code "323") (name "Net-(R420-Pad2)") (class "Default")
      (node (ref "R420") (pin "2") (pinfunction "2_2") (pintype "passive"))
      (node (ref "R498") (pin "1") (pinfunction "1_1") (pintype "passive"))
    )
    (net (code "324") (name "Net-(R421-Pad1)") (class "Default")
      (node (ref "R421") (pin "1") (pinfunction "1_1") (pintype "passive"))
      (node (ref "R426") (pin "2") (pinfunction "2_2") (pintype "passive"))
    )
    (net (code "325") (name "Net-(R427-Pad1)") (class "Default")
      (node (ref "R427") (pin "1") (pinfunction "1_1") (pintype "passive"))
      (node (ref "R432") (pin "2") (pinfunction "2_2") (pintype "passive"))
    )
    (net (code "326") (name "Net-(R433-Pad1)") (class "Default")
      (node (ref "R433") (pin "1") (pinfunction "1_1") (pintype "passive"))
      (node (ref "R438") (pin "2") (pinfunction "2_2") (pintype "passive"))
    )
    (net (code "327") (name "Net-(R439-Pad1)") (class "Default")
      (node (ref "R439") (pin "1") (pinfunction "1_1") (pintype "passive"))
      (node (ref "R444") (pin "2") (pinfunction "2_2") (pintype "passive"))
    )
    (net (code "328") (name "Net-(R445-Pad1)") (class "Default")
      (node (ref "R445") (pin "1") (pinfunction "1_1") (pintype "passive"))
      (node (ref "R450") (pin "2") (pinfunction "2_2") (pintype "passive"))
    )
    (net (code "329") (name "Net-(R451-Pad1)") (class "Default")
      (node (ref "R451") (pin "1") (pinfunction "1_1") (pintype "passive"))
      (node (ref "R456") (pin "2") (pinfunction "2_2") (pintype "passive"))
    )
    (net (code "330") (name "Net-(R457-Pad1)") (class "Default")
      (node (ref "R457") (pin "1") (pinfunction "1_1") (pintype "passive"))
      (node (ref "R462") (pin "2") (pinfunction "2_2") (pintype "passive"))
    )
    (net (code "331") (name "Net-(R463-Pad1)") (class "Default")
      (node (ref "R463") (pin "1") (pinfunction "1_1") (pintype "passive"))
      (node (ref "R468") (pin "2") (pinfunction "2_2") (pintype "passive"))
    )
    (net (code "332") (name "Net-(R469-Pad1)") (class "Default")
      (node (ref "R469") (pin "1") (pinfunction "1_1") (pintype "passive"))
      (node (ref "R474") (pin "2") (pinfunction "2_2") (pintype "passive"))
    )
    (net (code "333") (name "Net-(R475-Pad1)") (class "Default")
      (node (ref "R475") (pin "1") (pinfunction "1_1") (pintype "passive"))
      (node (ref "R480") (pin "2") (pinfunction "2_2") (pintype "passive"))
    )
    (net (code "334") (name "Net-(R481-Pad1)") (class "Default")
      (node (ref "R481") (pin "1") (pinfunction "1_1") (pintype "passive"))
      (node (ref "R486") (pin "2") (pinfunction "2_2") (pintype "passive"))
    )
    (net (code "335") (name "Net-(R487-Pad1)") (class "Default")
      (node (ref "R487") (pin "1") (pinfunction "1_1") (pintype "passive"))
      (node (ref "R488") (pin "2") (pinfunction "2_2") (pintype "passive"))
    )
    (net (code "336") (name "Net-(R488-Pad1)") (class "Default")
      (node (ref "R488") (pin "1") (pinfunction "1_1") (pintype "passive"))
      (node (ref "R490") (pin "1") (pinfunction "1_1") (pintype "passive"))
      (node (ref "U$90") (pin "1") (pinfunction "1_1") (pintype "passive"))
    )
    (net (code "337") (name "Net-(R489-Pad1)") (class "Default")
      (node (ref "R489") (pin "1") (pinfunction "1_1") (pintype "passive"))
      (node (ref "R490") (pin "2") (pinfunction "2_2") (pintype "passive"))
    )
    (net (code "338") (name "Net-(R491-Pad1)") (class "Default")
      (node (ref "R491") (pin "1") (pinfunction "1_1") (pintype "passive"))
      (node (ref "R492") (pin "2") (pinfunction "2_2") (pintype "passive"))
    )
    (net (code "339") (name "Net-(R503-Pad1)") (class "Default")
      (node (ref "R503") (pin "1") (pinfunction "1_1") (pintype "passive"))
      (node (ref "S2") (pin "3") (pinfunction "3_3") (pintype "passive"))
    )
    (net (code "340") (name "Net-(R503-Pad2)") (class "Default")
      (node (ref "R503") (pin "2") (pinfunction "2_2") (pintype "passive"))
      (node (ref "R581") (pin "1") (pinfunction "1_1") (pintype "passive"))
    )
    (net (code "341") (name "Net-(R504-Pad1)") (class "Default")
      (node (ref "R504") (pin "1") (pinfunction "1_1") (pintype "passive"))
      (node (ref "R509") (pin "2") (pinfunction "2_2") (pintype "passive"))
    )
    (net (code "342") (name "Net-(R509-Pad1)") (class "Default")
      (node (ref "R509") (pin "1") (pinfunction "1_1") (pintype "passive"))
      (node (ref "S2") (pin "2") (pinfunction "2_2") (pintype "passive"))
    )
    (net (code "343") (name "Net-(R510-Pad1)") (class "Default")
      (node (ref "R510") (pin "1") (pinfunction "1_1") (pintype "passive"))
      (node (ref "R515") (pin "2") (pinfunction "2_2") (pintype "passive"))
    )
    (net (code "344") (name "Net-(R515-Pad1)") (class "Default")
      (node (ref "R515") (pin "1") (pinfunction "1_1") (pintype "passive"))
      (node (ref "S2") (pin "4") (pinfunction "4_4") (pintype "passive"))
    )
    (net (code "345") (name "Net-(R516-Pad1)") (class "Default")
      (node (ref "R516") (pin "1") (pinfunction "1_1") (pintype "passive"))
      (node (ref "R521") (pin "2") (pinfunction "2_2") (pintype "passive"))
    )
    (net (code "346") (name "Net-(R521-Pad1)") (class "Default")
      (node (ref "R521") (pin "1") (pinfunction "1_1") (pintype "passive"))
      (node (ref "S2") (pin "5") (pinfunction "5_5") (pintype "passive"))
    )
    (net (code "347") (name "Net-(R522-Pad1)") (class "Default")
      (node (ref "R522") (pin "1") (pinfunction "1_1") (pintype "passive"))
      (node (ref "R527") (pin "2") (pinfunction "2_2") (pintype "passive"))
    )
    (net (code "348") (name "Net-(R527-Pad1)") (class "Default")
      (node (ref "R527") (pin "1") (pinfunction "1_1") (pintype "passive"))
      (node (ref "S2") (pin "6") (pinfunction "6_6") (pintype "passive"))
    )
    (net (code "349") (name "Net-(R528-Pad1)") (class "Default")
      (node (ref "R528") (pin "1") (pinfunction "1_1") (pintype "passive"))
      (node (ref "R533") (pin "2") (pinfunction "2_2") (pintype "passive"))
    )
    (net (code "350") (name "Net-(R533-Pad1)") (class "Default")
      (node (ref "R533") (pin "1") (pinfunction "1_1") (pintype "passive"))
      (node (ref "S2") (pin "7") (pinfunction "7_7") (pintype "passive"))
    )
    (net (code "351") (name "Net-(R534-Pad1)") (class "Default")
      (node (ref "R534") (pin "1") (pinfunction "1_1") (pintype "passive"))
      (node (ref "R539") (pin "2") (pinfunction "2_2") (pintype "passive"))
    )
    (net (code "352") (name "Net-(R539-Pad1)") (class "Default")
      (node (ref "R539") (pin "1") (pinfunction "1_1") (pintype "passive"))
      (node (ref "S2") (pin "9") (pinfunction "9_9") (pintype "passive"))
    )
    (net (code "353") (name "Net-(R540-Pad1)") (class "Default")
      (node (ref "R540") (pin "1") (pinfunction "1_1") (pintype "passive"))
      (node (ref "R545") (pin "2") (pinfunction "2_2") (pintype "passive"))
    )
    (net (code "354") (name "Net-(R545-Pad1)") (class "Default")
      (node (ref "R545") (pin "1") (pinfunction "1_1") (pintype "passive"))
      (node (ref "S2") (pin "8") (pinfunction "8_8") (pintype "passive"))
    )
    (net (code "355") (name "Net-(R546-Pad1)") (class "Default")
      (node (ref "R546") (pin "1") (pinfunction "1_1") (pintype "passive"))
      (node (ref "R551") (pin "2") (pinfunction "2_2") (pintype "passive"))
    )
    (net (code "356") (name "Net-(R551-Pad1)") (class "Default")
      (node (ref "R551") (pin "1") (pinfunction "1_1") (pintype "passive"))
      (node (ref "S2") (pin "10") (pinfunction "10_10") (pintype "passive"))
    )
    (net (code "357") (name "Net-(R552-Pad1)") (class "Default")
      (node (ref "R552") (pin "1") (pinfunction "1_1") (pintype "passive"))
      (node (ref "R557") (pin "2") (pinfunction "2_2") (pintype "passive"))
    )
    (net (code "358") (name "Net-(R557-Pad1)") (class "Default")
      (node (ref "R557") (pin "1") (pinfunction "1_1") (pintype "passive"))
      (node (ref "S2") (pin "11") (pinfunction "11_11") (pintype "passive"))
    )
    (net (code "359") (name "Net-(R558-Pad1)") (class "Default")
      (node (ref "R558") (pin "1") (pinfunction "1_1") (pintype "passive"))
      (node (ref "R563") (pin "2") (pinfunction "2_2") (pintype "passive"))
    )
    (net (code "360") (name "Net-(R563-Pad1)") (class "Default")
      (node (ref "R563") (pin "1") (pinfunction "1_1") (pintype "passive"))
      (node (ref "S2") (pin "12") (pinfunction "12_12") (pintype "passive"))
    )
    (net (code "361") (name "Net-(R564-Pad1)") (class "Default")
      (node (ref "R564") (pin "1") (pinfunction "1_1") (pintype "passive"))
      (node (ref "R569") (pin "2") (pinfunction "2_2") (pintype "passive"))
    )
    (net (code "362") (name "Net-(R569-Pad1)") (class "Default")
      (node (ref "R569") (pin "1") (pinfunction "1_1") (pintype "passive"))
      (node (ref "R575") (pin "1") (pinfunction "1_1") (pintype "passive"))
      (node (ref "S2") (pin "13") (pinfunction "13_13") (pintype "passive"))
    )
    (net (code "363") (name "Net-(R570-Pad1)") (class "Default")
      (node (ref "R570") (pin "1") (pinfunction "1_1") (pintype "passive"))
      (node (ref "R571") (pin "2") (pinfunction "2_2") (pintype "passive"))
    )
    (net (code "364") (name "Net-(R571-Pad1)") (class "Default")
      (node (ref "R571") (pin "1") (pinfunction "1_1") (pintype "passive"))
      (node (ref "R573") (pin "1") (pinfunction "1_1") (pintype "passive"))
      (node (ref "U$105") (pin "1") (pinfunction "1_1") (pintype "passive"))
    )
    (net (code "365") (name "Net-(R572-Pad1)") (class "Default")
      (node (ref "R572") (pin "1") (pinfunction "1_1") (pintype "passive"))
      (node (ref "R573") (pin "2") (pinfunction "2_2") (pintype "passive"))
    )
    (net (code "366") (name "Net-(R574-Pad1)") (class "Default")
      (node (ref "R574") (pin "1") (pinfunction "1_1") (pintype "passive"))
      (node (ref "R575") (pin "2") (pinfunction "2_2") (pintype "passive"))
    )
    (net (code "367") (name "Net-(R586-Pad2)") (class "Default")
      (node (ref "R586") (pin "2") (pinfunction "2_2") (pintype "passive"))
      (node (ref "R664") (pin "1") (pinfunction "1_1") (pintype "passive"))
    )
    (net (code "368") (name "Net-(R587-Pad1)") (class "Default")
      (node (ref "R587") (pin "1") (pinfunction "1_1") (pintype "passive"))
      (node (ref "R592") (pin "2") (pinfunction "2_2") (pintype "passive"))
    )
    (net (code "369") (name "Net-(R593-Pad1)") (class "Default")
      (node (ref "R593") (pin "1") (pinfunction "1_1") (pintype "passive"))
      (node (ref "R598") (pin "2") (pinfunction "2_2") (pintype "passive"))
    )
    (net (code "370") (name "Net-(R599-Pad1)") (class "Default")
      (node (ref "R599") (pin "1") (pinfunction "1_1") (pintype "passive"))
      (node (ref "R604") (pin "2") (pinfunction "2_2") (pintype "passive"))
    )
    (net (code "371") (name "Net-(R605-Pad1)") (class "Default")
      (node (ref "R605") (pin "1") (pinfunction "1_1") (pintype "passive"))
      (node (ref "R610") (pin "2") (pinfunction "2_2") (pintype "passive"))
    )
    (net (code "372") (name "Net-(R611-Pad1)") (class "Default")
      (node (ref "R611") (pin "1") (pinfunction "1_1") (pintype "passive"))
      (node (ref "R616") (pin "2") (pinfunction "2_2") (pintype "passive"))
    )
    (net (code "373") (name "Net-(R617-Pad1)") (class "Default")
      (node (ref "R617") (pin "1") (pinfunction "1_1") (pintype "passive"))
      (node (ref "R622") (pin "2") (pinfunction "2_2") (pintype "passive"))
    )
    (net (code "374") (name "Net-(R623-Pad1)") (class "Default")
      (node (ref "R623") (pin "1") (pinfunction "1_1") (pintype "passive"))
      (node (ref "R628") (pin "2") (pinfunction "2_2") (pintype "passive"))
    )
    (net (code "375") (name "Net-(R629-Pad1)") (class "Default")
      (node (ref "R629") (pin "1") (pinfunction "1_1") (pintype "passive"))
      (node (ref "R634") (pin "2") (pinfunction "2_2") (pintype "passive"))
    )
    (net (code "376") (name "Net-(R635-Pad1)") (class "Default")
      (node (ref "R635") (pin "1") (pinfunction "1_1") (pintype "passive"))
      (node (ref "R640") (pin "2") (pinfunction "2_2") (pintype "passive"))
    )
    (net (code "377") (name "Net-(R641-Pad1)") (class "Default")
      (node (ref "R641") (pin "1") (pinfunction "1_1") (pintype "passive"))
      (node (ref "R646") (pin "2") (pinfunction "2_2") (pintype "passive"))
    )
    (net (code "378") (name "Net-(R647-Pad1)") (class "Default")
      (node (ref "R647") (pin "1") (pinfunction "1_1") (pintype "passive"))
      (node (ref "R652") (pin "2") (pinfunction "2_2") (pintype "passive"))
    )
    (net (code "379") (name "Net-(R653-Pad1)") (class "Default")
      (node (ref "R653") (pin "1") (pinfunction "1_1") (pintype "passive"))
      (node (ref "R654") (pin "2") (pinfunction "2_2") (pintype "passive"))
    )
    (net (code "380") (name "Net-(R654-Pad1)") (class "Default")
      (node (ref "R654") (pin "1") (pinfunction "1_1") (pintype "passive"))
      (node (ref "R656") (pin "1") (pinfunction "1_1") (pintype "passive"))
      (node (ref "U$120") (pin "1") (pinfunction "1_1") (pintype "passive"))
    )
    (net (code "381") (name "Net-(R655-Pad1)") (class "Default")
      (node (ref "R655") (pin "1") (pinfunction "1_1") (pintype "passive"))
      (node (ref "R656") (pin "2") (pinfunction "2_2") (pintype "passive"))
    )
    (net (code "382") (name "Net-(R657-Pad1)") (class "Default")
      (node (ref "R657") (pin "1") (pinfunction "1_1") (pintype "passive"))
      (node (ref "R658") (pin "2") (pinfunction "2_2") (pintype "passive"))
    )
    (net (code "383") (name "Net-(R669-Pad2)") (class "Default")
      (node (ref "R669") (pin "2") (pinfunction "2_2") (pintype "passive"))
      (node (ref "R747") (pin "1") (pinfunction "1_1") (pintype "passive"))
    )
    (net (code "384") (name "Net-(R670-Pad1)") (class "Default")
      (node (ref "R670") (pin "1") (pinfunction "1_1") (pintype "passive"))
      (node (ref "R675") (pin "2") (pinfunction "2_2") (pintype "passive"))
    )
    (net (code "385") (name "Net-(R676-Pad1)") (class "Default")
      (node (ref "R676") (pin "1") (pinfunction "1_1") (pintype "passive"))
      (node (ref "R681") (pin "2") (pinfunction "2_2") (pintype "passive"))
    )
    (net (code "386") (name "Net-(R682-Pad1)") (class "Default")
      (node (ref "R682") (pin "1") (pinfunction "1_1") (pintype "passive"))
      (node (ref "R687") (pin "2") (pinfunction "2_2") (pintype "passive"))
    )
    (net (code "387") (name "Net-(R688-Pad1)") (class "Default")
      (node (ref "R688") (pin "1") (pinfunction "1_1") (pintype "passive"))
      (node (ref "R693") (pin "2") (pinfunction "2_2") (pintype "passive"))
    )
    (net (code "388") (name "Net-(R694-Pad1)") (class "Default")
      (node (ref "R694") (pin "1") (pinfunction "1_1") (pintype "passive"))
      (node (ref "R699") (pin "2") (pinfunction "2_2") (pintype "passive"))
    )
    (net (code "389") (name "Net-(R700-Pad1)") (class "Default")
      (node (ref "R700") (pin "1") (pinfunction "1_1") (pintype "passive"))
      (node (ref "R705") (pin "2") (pinfunction "2_2") (pintype "passive"))
    )
    (net (code "390") (name "Net-(R706-Pad1)") (class "Default")
      (node (ref "R706") (pin "1") (pinfunction "1_1") (pintype "passive"))
      (node (ref "R711") (pin "2") (pinfunction "2_2") (pintype "passive"))
    )
    (net (code "391") (name "Net-(R712-Pad1)") (class "Default")
      (node (ref "R712") (pin "1") (pinfunction "1_1") (pintype "passive"))
      (node (ref "R717") (pin "2") (pinfunction "2_2") (pintype "passive"))
    )
    (net (code "392") (name "Net-(R718-Pad1)") (class "Default")
      (node (ref "R718") (pin "1") (pinfunction "1_1") (pintype "passive"))
      (node (ref "R723") (pin "2") (pinfunction "2_2") (pintype "passive"))
    )
    (net (code "393") (name "Net-(R724-Pad1)") (class "Default")
      (node (ref "R724") (pin "1") (pinfunction "1_1") (pintype "passive"))
      (node (ref "R729") (pin "2") (pinfunction "2_2") (pintype "passive"))
    )
    (net (code "394") (name "Net-(R730-Pad1)") (class "Default")
      (node (ref "R730") (pin "1") (pinfunction "1_1") (pintype "passive"))
      (node (ref "R735") (pin "2") (pinfunction "2_2") (pintype "passive"))
    )
    (net (code "395") (name "Net-(R736-Pad1)") (class "Default")
      (node (ref "R736") (pin "1") (pinfunction "1_1") (pintype "passive"))
      (node (ref "R737") (pin "2") (pinfunction "2_2") (pintype "passive"))
    )
    (net (code "396") (name "Net-(R737-Pad1)") (class "Default")
      (node (ref "R737") (pin "1") (pinfunction "1_1") (pintype "passive"))
      (node (ref "R739") (pin "1") (pinfunction "1_1") (pintype "passive"))
      (node (ref "U$135") (pin "1") (pinfunction "1_1") (pintype "passive"))
    )
    (net (code "397") (name "Net-(R738-Pad1)") (class "Default")
      (node (ref "R738") (pin "1") (pinfunction "1_1") (pintype "passive"))
      (node (ref "R739") (pin "2") (pinfunction "2_2") (pintype "passive"))
    )
    (net (code "398") (name "Net-(R740-Pad1)") (class "Default")
      (node (ref "R740") (pin "1") (pinfunction "1_1") (pintype "passive"))
      (node (ref "R741") (pin "2") (pinfunction "2_2") (pintype "passive"))
    )
    (net (code "399") (name "Net-(S-Pad1)") (class "Default")
      (node (ref "S") (pin "1") (pinfunction "1_1") (pintype "passive"))
      (node (ref "U$15") (pin "2") (pinfunction "2_2") (pintype "passive"))
    )
    (net (code "400") (name "Net-(S1-Pad1)") (class "Default")
      (node (ref "S1") (pin "1") (pinfunction "1_1") (pintype "passive"))
      (node (ref "U$60") (pin "2") (pinfunction "2_2") (pintype "passive"))
    )
    (net (code "401") (name "Net-(S2-Pad1)") (class "Default")
      (node (ref "S2") (pin "1") (pinfunction "1_1") (pintype "passive"))
      (node (ref "U$105") (pin "2") (pinfunction "2_2") (pintype "passive"))
    )
    (net (code "402") (name "Net-(U$1-CO)") (class "Default")
      (node (ref "C15") (pin "2") (pinfunction "2_2") (pintype "passive"))
      (node (ref "R83") (pin "2") (pinfunction "2_2") (pintype "passive"))
      (node (ref "U$1") (pin "26") (pinfunction "CO_26") (pintype "bidirectional"))
    )
    (net (code "403") (name "Net-(U$1-CSBI)") (class "Default")
      (node (ref "U$1") (pin "44") (pinfunction "CSBI_44") (pintype "bidirectional"))
      (node (ref "U$2") (pin "12") (pinfunction "B3_12") (pintype "bidirectional"))
    )
    (net (code "404") (name "Net-(U$1-SCKI)") (class "Default")
      (node (ref "U$1") (pin "41") (pinfunction "SCKI_41") (pintype "bidirectional"))
      (node (ref "U$2") (pin "14") (pinfunction "B1_14") (pintype "bidirectional"))
    )
    (net (code "405") (name "Net-(U$1-SDI)") (class "Default")
      (node (ref "U$1") (pin "42") (pinfunction "SDI_42") (pintype "bidirectional"))
      (node (ref "U$2") (pin "13") (pinfunction "B2_13") (pintype "bidirectional"))
    )
    (net (code "406") (name "Net-(U$1-SDO)") (class "Default")
      (node (ref "R85") (pin "2") (pinfunction "2_2") (pintype "passive"))
      (node (ref "U$1") (pin "43") (pinfunction "SDO_43") (pintype "bidirectional"))
      (node (ref "U$2") (pin "11") (pinfunction "B4_11") (pintype "bidirectional"))
    )
    (net (code "407") (name "Net-(U$1-VREFF)") (class "Default")
      (node (ref "C16") (pin "2") (pinfunction "2_2") (pintype "passive"))
      (node (ref "U$1") (pin "31") (pinfunction "VREFF_31") (pintype "bidirectional"))
    )
    (net (code "408") (name "Net-(U$1-VREG)") (class "Default")
      (node (ref "C17") (pin "2") (pinfunction "2_2") (pintype "passive"))
      (node (ref "R84") (pin "1") (pinfunction "1_1") (pintype "passive"))
      (node (ref "R85") (pin "1") (pinfunction "1_1") (pintype "passive"))
      (node (ref "U$1") (pin "32") (pinfunction "VREG_32") (pintype "bidirectional"))
      (node (ref "U$2") (pin "10") (pinfunction "EN2_10") (pintype "bidirectional"))
      (node (ref "U$2") (pin "16") (pinfunction "VDD2_16") (pintype "bidirectional"))
    )
    (net (code "409") (name "Net-(U$1-WDTB)") (class "Default")
      (node (ref "R84") (pin "2") (pinfunction "2_2") (pintype "passive"))
      (node (ref "U$1") (pin "34") (pinfunction "WDTB_34") (pintype "bidirectional"))
    )
    (net (code "410") (name "Net-(U$2-A4)") (class "Default")
      (node (ref "D33") (pin "C") (pinfunction "C_C") (pintype "passive"))
      (node (ref "U$2") (pin "6") (pinfunction "A4_6") (pintype "bidirectional"))
    )
    (net (code "411") (name "Net-(U$3-D)") (class "Default")
      (node (ref "R3") (pin "2") (pinfunction "2_2") (pintype "passive"))
      (node (ref "R6") (pin "2") (pinfunction "2_2") (pintype "passive"))
      (node (ref "U$3") (pin "3") (pinfunction "D_3") (pintype "passive"))
    )
    (net (code "412") (name "Net-(U$3-G)") (class "Default")
      (node (ref "R5") (pin "1") (pinfunction "1_1") (pintype "passive"))
      (node (ref "U$3") (pin "1") (pinfunction "G_1") (pintype "passive"))
    )
    (net (code "413") (name "Net-(U$3-S)") (class "Default")
      (node (ref "D1") (pin "C") (pinfunction "C_C") (pintype "passive"))
      (node (ref "D3") (pin "A") (pinfunction "A_A") (pintype "passive"))
      (node (ref "R1") (pin "2") (pinfunction "2_2") (pintype "passive"))
      (node (ref "R15") (pin "1") (pinfunction "1_1") (pintype "passive"))
      (node (ref "R18") (pin "1") (pinfunction "1_1") (pintype "passive"))
      (node (ref "R4") (pin "1") (pinfunction "1_1") (pintype "passive"))
      (node (ref "U$3") (pin "2") (pinfunction "S_2") (pintype "passive"))
    )
    (net (code "414") (name "Net-(U$4-D)") (class "Default")
      (node (ref "R12") (pin "2") (pinfunction "2_2") (pintype "passive"))
      (node (ref "R9") (pin "2") (pinfunction "2_2") (pintype "passive"))
      (node (ref "U$4") (pin "3") (pinfunction "D_3") (pintype "passive"))
    )
    (net (code "415") (name "Net-(U$4-G)") (class "Default")
      (node (ref "R11") (pin "1") (pinfunction "1_1") (pintype "passive"))
      (node (ref "U$4") (pin "1") (pinfunction "G_1") (pintype "passive"))
    )
    (net (code "416") (name "Net-(U$4-S)") (class "Default")
      (node (ref "D1") (pin "A") (pinfunction "A_A") (pintype "passive"))
      (node (ref "D13") (pin "C") (pinfunction "C_C") (pintype "passive"))
      (node (ref "D2") (pin "C") (pinfunction "C_C") (pintype "passive"))
      (node (ref "R10") (pin "1") (pinfunction "1_1") (pintype "passive"))
      (node (ref "R3") (pin "1") (pinfunction "1_1") (pintype "passive"))
      (node (ref "R6") (pin "1") (pinfunction "1_1") (pintype "passive"))
      (node (ref "R8") (pin "2") (pinfunction "2_2") (pintype "passive"))
      (node (ref "U$4") (pin "2") (pinfunction "S_2") (pintype "passive"))
    )
    (net (code "417") (name "Net-(U$5-D)") (class "Default")
      (node (ref "R15") (pin "2") (pinfunction "2_2") (pintype "passive"))
      (node (ref "R18") (pin "2") (pinfunction "2_2") (pintype "passive"))
      (node (ref "U$5") (pin "3") (pinfunction "D_3") (pintype "passive"))
    )
    (net (code "418") (name "Net-(U$5-G)") (class "Default")
      (node (ref "R17") (pin "1") (pinfunction "1_1") (pintype "passive"))
      (node (ref "U$5") (pin "1") (pinfunction "G_1") (pintype "passive"))
    )
    (net (code "419") (name "Net-(U$5-S)") (class "Default")
      (node (ref "D3") (pin "C") (pinfunction "C_C") (pintype "passive"))
      (node (ref "D4") (pin "A") (pinfunction "A_A") (pintype "passive"))
      (node (ref "R14") (pin "2") (pinfunction "2_2") (pintype "passive"))
      (node (ref "R16") (pin "1") (pinfunction "1_1") (pintype "passive"))
      (node (ref "R21") (pin "1") (pinfunction "1_1") (pintype "passive"))
      (node (ref "R24") (pin "1") (pinfunction "1_1") (pintype "passive"))
      (node (ref "U$5") (pin "2") (pinfunction "S_2") (pintype "passive"))
    )
    (net (code "420") (name "Net-(U$6-D)") (class "Default")
      (node (ref "R21") (pin "2") (pinfunction "2_2") (pintype "passive"))
      (node (ref "R24") (pin "2") (pinfunction "2_2") (pintype "passive"))
      (node (ref "U$6") (pin "3") (pinfunction "D_3") (pintype "passive"))
    )
    (net (code "421") (name "Net-(U$6-G)") (class "Default")
      (node (ref "R23") (pin "1") (pinfunction "1_1") (pintype "passive"))
      (node (ref "U$6") (pin "1") (pinfunction "G_1") (pintype "passive"))
    )
    (net (code "422") (name "Net-(U$6-S)") (class "Default")
      (node (ref "D4") (pin "C") (pinfunction "C_C") (pintype "passive"))
      (node (ref "D5") (pin "A") (pinfunction "A_A") (pintype "passive"))
      (node (ref "R20") (pin "2") (pinfunction "2_2") (pintype "passive"))
      (node (ref "R22") (pin "1") (pinfunction "1_1") (pintype "passive"))
      (node (ref "R27") (pin "1") (pinfunction "1_1") (pintype "passive"))
      (node (ref "R30") (pin "1") (pinfunction "1_1") (pintype "passive"))
      (node (ref "U$6") (pin "2") (pinfunction "S_2") (pintype "passive"))
    )
    (net (code "423") (name "Net-(U$7-D)") (class "Default")
      (node (ref "R27") (pin "2") (pinfunction "2_2") (pintype "passive"))
      (node (ref "R30") (pin "2") (pinfunction "2_2") (pintype "passive"))
      (node (ref "U$7") (pin "3") (pinfunction "D_3") (pintype "passive"))
    )
    (net (code "424") (name "Net-(U$7-G)") (class "Default")
      (node (ref "R29") (pin "1") (pinfunction "1_1") (pintype "passive"))
      (node (ref "U$7") (pin "1") (pinfunction "G_1") (pintype "passive"))
    )
    (net (code "425") (name "Net-(U$7-S)") (class "Default")
      (node (ref "D5") (pin "C") (pinfunction "C_C") (pintype "passive"))
      (node (ref "D6") (pin "A") (pinfunction "A_A") (pintype "passive"))
      (node (ref "R26") (pin "2") (pinfunction "2_2") (pintype "passive"))
      (node (ref "R28") (pin "1") (pinfunction "1_1") (pintype "passive"))
      (node (ref "R33") (pin "1") (pinfunction "1_1") (pintype "passive"))
      (node (ref "R36") (pin "1") (pinfunction "1_1") (pintype "passive"))
      (node (ref "U$7") (pin "2") (pinfunction "S_2") (pintype "passive"))
    )
    (net (code "426") (name "Net-(U$8-D)") (class "Default")
      (node (ref "R33") (pin "2") (pinfunction "2_2") (pintype "passive"))
      (node (ref "R36") (pin "2") (pinfunction "2_2") (pintype "passive"))
      (node (ref "U$8") (pin "3") (pinfunction "D_3") (pintype "passive"))
    )
    (net (code "427") (name "Net-(U$8-G)") (class "Default")
      (node (ref "R35") (pin "1") (pinfunction "1_1") (pintype "passive"))
      (node (ref "U$8") (pin "1") (pinfunction "G_1") (pintype "passive"))
    )
    (net (code "428") (name "Net-(U$8-S)") (class "Default")
      (node (ref "D6") (pin "C") (pinfunction "C_C") (pintype "passive"))
      (node (ref "D8") (pin "A") (pinfunction "A_A") (pintype "passive"))
      (node (ref "R32") (pin "2") (pinfunction "2_2") (pintype "passive"))
      (node (ref "R34") (pin "1") (pinfunction "1_1") (pintype "passive"))
      (node (ref "R45") (pin "1") (pinfunction "1_1") (pintype "passive"))
      (node (ref "R48") (pin "1") (pinfunction "1_1") (pintype "passive"))
      (node (ref "U$8") (pin "2") (pinfunction "S_2") (pintype "passive"))
    )
    (net (code "429") (name "Net-(U$9-D)") (class "Default")
      (node (ref "R39") (pin "2") (pinfunction "2_2") (pintype "passive"))
      (node (ref "R42") (pin "2") (pinfunction "2_2") (pintype "passive"))
      (node (ref "U$9") (pin "3") (pinfunction "D_3") (pintype "passive"))
    )
    (net (code "430") (name "Net-(U$9-G)") (class "Default")
      (node (ref "R41") (pin "1") (pinfunction "1_1") (pintype "passive"))
      (node (ref "U$9") (pin "1") (pinfunction "G_1") (pintype "passive"))
    )
    (net (code "431") (name "Net-(U$9-S)") (class "Default")
      (node (ref "D7") (pin "C") (pinfunction "C_C") (pintype "passive"))
      (node (ref "D9") (pin "A") (pinfunction "A_A") (pintype "passive"))
      (node (ref "R38") (pin "2") (pinfunction "2_2") (pintype "passive"))
      (node (ref "R40") (pin "1") (pinfunction "1_1") (pintype "passive"))
      (node (ref "R51") (pin "1") (pinfunction "1_1") (pintype "passive"))
      (node (ref "R54") (pin "1") (pinfunction "1_1") (pintype "passive"))
      (node (ref "U$9") (pin "2") (pinfunction "S_2") (pintype "passive"))
    )
    (net (code "432") (name "Net-(U$10-D)") (class "Default")
      (node (ref "R45") (pin "2") (pinfunction "2_2") (pintype "passive"))
      (node (ref "R48") (pin "2") (pinfunction "2_2") (pintype "passive"))
      (node (ref "U$10") (pin "3") (pinfunction "D_3") (pintype "passive"))
    )
    (net (code "433") (name "Net-(U$10-G)") (class "Default")
      (node (ref "R47") (pin "1") (pinfunction "1_1") (pintype "passive"))
      (node (ref "U$10") (pin "1") (pinfunction "G_1") (pintype "passive"))
    )
    (net (code "434") (name "Net-(U$10-S)") (class "Default")
      (node (ref "D7") (pin "A") (pinfunction "A_A") (pintype "passive"))
      (node (ref "D8") (pin "C") (pinfunction "C_C") (pintype "passive"))
      (node (ref "R39") (pin "1") (pinfunction "1_1") (pintype "passive"))
      (node (ref "R42") (pin "1") (pinfunction "1_1") (pintype "passive"))
      (node (ref "R44") (pin "2") (pinfunction "2_2") (pintype "passive"))
      (node (ref "R46") (pin "1") (pinfunction "1_1") (pintype "passive"))
      (node (ref "U$10") (pin "2") (pinfunction "S_2") (pintype "passive"))
    )
    (net (code "435") (name "Net-(U$11-D)") (class "Default")
      (node (ref "R51") (pin "2") (pinfunction "2_2") (pintype "passive"))
      (node (ref "R54") (pin "2") (pinfunction "2_2") (pintype "passive"))
      (node (ref "U$11") (pin "3") (pinfunction "D_3") (pintype "passive"))
    )
    (net (code "436") (name "Net-(U$11-G)") (class "Default")
      (node (ref "R53") (pin "1") (pinfunction "1_1") (pintype "passive"))
      (node (ref "U$11") (pin "1") (pinfunction "G_1") (pintype "passive"))
    )
    (net (code "437") (name "Net-(U$11-S)") (class "Default")
      (node (ref "D10") (pin "A") (pinfunction "A_A") (pintype "passive"))
      (node (ref "D9") (pin "C") (pinfunction "C_C") (pintype "passive"))
      (node (ref "R50") (pin "2") (pinfunction "2_2") (pintype "passive"))
      (node (ref "R52") (pin "1") (pinfunction "1_1") (pintype "passive"))
      (node (ref "R57") (pin "1") (pinfunction "1_1") (pintype "passive"))
      (node (ref "R60") (pin "1") (pinfunction "1_1") (pintype "passive"))
      (node (ref "U$11") (pin "2") (pinfunction "S_2") (pintype "passive"))
    )
    (net (code "438") (name "Net-(U$12-D)") (class "Default")
      (node (ref "R57") (pin "2") (pinfunction "2_2") (pintype "passive"))
      (node (ref "R60") (pin "2") (pinfunction "2_2") (pintype "passive"))
      (node (ref "U$12") (pin "3") (pinfunction "D_3") (pintype "passive"))
    )
    (net (code "439") (name "Net-(U$12-G)") (class "Default")
      (node (ref "R59") (pin "1") (pinfunction "1_1") (pintype "passive"))
      (node (ref "U$12") (pin "1") (pinfunction "G_1") (pintype "passive"))
    )
    (net (code "440") (name "Net-(U$12-S)") (class "Default")
      (node (ref "D10") (pin "C") (pinfunction "C_C") (pintype "passive"))
      (node (ref "D11") (pin "A") (pinfunction "A_A") (pintype "passive"))
      (node (ref "R56") (pin "2") (pinfunction "2_2") (pintype "passive"))
      (node (ref "R58") (pin "1") (pinfunction "1_1") (pintype "passive"))
      (node (ref "R63") (pin "1") (pinfunction "1_1") (pintype "passive"))
      (node (ref "R66") (pin "1") (pinfunction "1_1") (pintype "passive"))
      (node (ref "U$12") (pin "2") (pinfunction "S_2") (pintype "passive"))
    )
    (net (code "441") (name "Net-(U$13-D)") (class "Default")
      (node (ref "R63") (pin "2") (pinfunction "2_2") (pintype "passive"))
      (node (ref "R66") (pin "2") (pinfunction "2_2") (pintype "passive"))
      (node (ref "U$13") (pin "3") (pinfunction "D_3") (pintype "passive"))
    )
    (net (code "442") (name "Net-(U$13-G)") (class "Default")
      (node (ref "R65") (pin "1") (pinfunction "1_1") (pintype "passive"))
      (node (ref "U$13") (pin "1") (pinfunction "G_1") (pintype "passive"))
    )
    (net (code "443") (name "Net-(U$13-S)") (class "Default")
      (node (ref "D11") (pin "C") (pinfunction "C_C") (pintype "passive"))
      (node (ref "D12") (pin "A") (pinfunction "A_A") (pintype "passive"))
      (node (ref "D14") (pin "A") (pinfunction "A_A") (pintype "passive"))
      (node (ref "R62") (pin "2") (pinfunction "2_2") (pintype "passive"))
      (node (ref "R64") (pin "1") (pinfunction "1_1") (pintype "passive"))
      (node (ref "R69") (pin "1") (pinfunction "1_1") (pintype "passive"))
      (node (ref "R72") (pin "1") (pinfunction "1_1") (pintype "passive"))
      (node (ref "U$13") (pin "2") (pinfunction "S_2") (pintype "passive"))
    )
    (net (code "444") (name "Net-(U$14-D)") (class "Default")
      (node (ref "R69") (pin "2") (pinfunction "2_2") (pintype "passive"))
      (node (ref "R72") (pin "2") (pinfunction "2_2") (pintype "passive"))
      (node (ref "U$14") (pin "3") (pinfunction "D_3") (pintype "passive"))
    )
    (net (code "445") (name "Net-(U$14-G)") (class "Default")
      (node (ref "R71") (pin "1") (pinfunction "1_1") (pintype "passive"))
      (node (ref "U$14") (pin "1") (pinfunction "G_1") (pintype "passive"))
    )
    (net (code "446") (name "Net-(U$14-S)") (class "Default")
      (node (ref "D12") (pin "C") (pinfunction "C_C") (pintype "passive"))
      (node (ref "R68") (pin "2") (pinfunction "2_2") (pintype "passive"))
      (node (ref "R70") (pin "1") (pinfunction "1_1") (pintype "passive"))
      (node (ref "U$14") (pin "2") (pinfunction "S_2") (pintype "passive"))
    )
    (net (code "447") (name "Net-(U$16-A0)") (class "Default")
      (node (ref "C35") (pin "2") (pinfunction "2_2") (pintype "passive"))
      (node (ref "R169") (pin "1") (pinfunction "1_1") (pintype "passive"))
      (node (ref "R170") (pin "1") (pinfunction "1_1") (pintype "passive"))
      (node (ref "U$16") (pin "32") (pinfunction "VREG_32") (pintype "bidirectional"))
      (node (ref "U$16") (pin "37") (pinfunction "A0_37") (pintype "bidirectional"))
      (node (ref "U$17") (pin "10") (pinfunction "EN2_10") (pintype "bidirectional"))
      (node (ref "U$17") (pin "16") (pinfunction "VDD2_16") (pintype "bidirectional"))
    )
    (net (code "448") (name "Net-(U$16-CO)") (class "Default")
      (node (ref "C33") (pin "2") (pinfunction "2_2") (pintype "passive"))
      (node (ref "R168") (pin "2") (pinfunction "2_2") (pintype "passive"))
      (node (ref "U$16") (pin "26") (pinfunction "CO_26") (pintype "bidirectional"))
    )
    (net (code "449") (name "Net-(U$16-CSBI)") (class "Default")
      (node (ref "U$16") (pin "44") (pinfunction "CSBI_44") (pintype "bidirectional"))
      (node (ref "U$17") (pin "12") (pinfunction "B3_12") (pintype "bidirectional"))
    )
    (net (code "450") (name "Net-(U$16-SCKI)") (class "Default")
      (node (ref "U$16") (pin "41") (pinfunction "SCKI_41") (pintype "bidirectional"))
      (node (ref "U$17") (pin "14") (pinfunction "B1_14") (pintype "bidirectional"))
    )
    (net (code "451") (name "Net-(U$16-SDI)") (class "Default")
      (node (ref "U$16") (pin "42") (pinfunction "SDI_42") (pintype "bidirectional"))
      (node (ref "U$17") (pin "13") (pinfunction "B2_13") (pintype "bidirectional"))
    )
    (net (code "452") (name "Net-(U$16-SDO)") (class "Default")
      (node (ref "R170") (pin "2") (pinfunction "2_2") (pintype "passive"))
      (node (ref "U$16") (pin "43") (pinfunction "SDO_43") (pintype "bidirectional"))
      (node (ref "U$17") (pin "11") (pinfunction "B4_11") (pintype "bidirectional"))
    )
    (net (code "453") (name "Net-(U$16-VREFF)") (class "Default")
      (node (ref "C34") (pin "2") (pinfunction "2_2") (pintype "passive"))
      (node (ref "U$16") (pin "31") (pinfunction "VREFF_31") (pintype "bidirectional"))
    )
    (net (code "454") (name "Net-(U$16-WDTB)") (class "Default")
      (node (ref "R169") (pin "2") (pinfunction "2_2") (pintype "passive"))
      (node (ref "U$16") (pin "34") (pinfunction "WDTB_34") (pintype "bidirectional"))
    )
    (net (code "455") (name "Net-(U$17-A4)") (class "Default")
      (node (ref "D32") (pin "C") (pinfunction "C_C") (pintype "passive"))
      (node (ref "U$17") (pin "6") (pinfunction "A4_6") (pintype "bidirectional"))
    )
    (net (code "456") (name "Net-(U$18-D)") (class "Default")
      (node (ref "R88") (pin "2") (pinfunction "2_2") (pintype "passive"))
      (node (ref "R91") (pin "2") (pinfunction "2_2") (pintype "passive"))
      (node (ref "U$18") (pin "3") (pinfunction "D_3") (pintype "passive"))
    )
    (net (code "457") (name "Net-(U$18-G)") (class "Default")
      (node (ref "R90") (pin "1") (pinfunction "1_1") (pintype "passive"))
      (node (ref "U$18") (pin "1") (pinfunction "G_1") (pintype "passive"))
    )
    (net (code "458") (name "Net-(U$18-S)") (class "Default")
      (node (ref "D16") (pin "C") (pinfunction "C_C") (pintype "passive"))
      (node (ref "D18") (pin "A") (pinfunction "A_A") (pintype "passive"))
      (node (ref "R100") (pin "1") (pinfunction "1_1") (pintype "passive"))
      (node (ref "R103") (pin "1") (pinfunction "1_1") (pintype "passive"))
      (node (ref "R172") (pin "2") (pinfunction "2_2") (pintype "passive"))
      (node (ref "R89") (pin "1") (pinfunction "1_1") (pintype "passive"))
      (node (ref "U$18") (pin "2") (pinfunction "S_2") (pintype "passive"))
    )
    (net (code "459") (name "Net-(U$19-D)") (class "Default")
      (node (ref "R94") (pin "2") (pinfunction "2_2") (pintype "passive"))
      (node (ref "R97") (pin "2") (pinfunction "2_2") (pintype "passive"))
      (node (ref "U$19") (pin "3") (pinfunction "D_3") (pintype "passive"))
    )
    (net (code "460") (name "Net-(U$19-G)") (class "Default")
      (node (ref "R96") (pin "1") (pinfunction "1_1") (pintype "passive"))
      (node (ref "U$19") (pin "1") (pinfunction "G_1") (pintype "passive"))
    )
    (net (code "461") (name "Net-(U$19-S)") (class "Default")
      (node (ref "D16") (pin "A") (pinfunction "A_A") (pintype "passive"))
      (node (ref "D17") (pin "C") (pinfunction "C_C") (pintype "passive"))
      (node (ref "D28") (pin "C") (pinfunction "C_C") (pintype "passive"))
      (node (ref "R88") (pin "1") (pinfunction "1_1") (pintype "passive"))
      (node (ref "R91") (pin "1") (pinfunction "1_1") (pintype "passive"))
      (node (ref "R93") (pin "2") (pinfunction "2_2") (pintype "passive"))
      (node (ref "R95") (pin "1") (pinfunction "1_1") (pintype "passive"))
      (node (ref "U$19") (pin "2") (pinfunction "S_2") (pintype "passive"))
    )
    (net (code "462") (name "Net-(U$20-D)") (class "Default")
      (node (ref "R100") (pin "2") (pinfunction "2_2") (pintype "passive"))
      (node (ref "R103") (pin "2") (pinfunction "2_2") (pintype "passive"))
      (node (ref "U$20") (pin "3") (pinfunction "D_3") (pintype "passive"))
    )
    (net (code "463") (name "Net-(U$20-G)") (class "Default")
      (node (ref "R102") (pin "1") (pinfunction "1_1") (pintype "passive"))
      (node (ref "U$20") (pin "1") (pinfunction "G_1") (pintype "passive"))
    )
    (net (code "464") (name "Net-(U$20-S)") (class "Default")
      (node (ref "D18") (pin "C") (pinfunction "C_C") (pintype "passive"))
      (node (ref "D19") (pin "A") (pinfunction "A_A") (pintype "passive"))
      (node (ref "R101") (pin "1") (pinfunction "1_1") (pintype "passive"))
      (node (ref "R106") (pin "1") (pinfunction "1_1") (pintype "passive"))
      (node (ref "R109") (pin "1") (pinfunction "1_1") (pintype "passive"))
      (node (ref "R99") (pin "2") (pinfunction "2_2") (pintype "passive"))
      (node (ref "U$20") (pin "2") (pinfunction "S_2") (pintype "passive"))
    )
    (net (code "465") (name "Net-(U$21-D)") (class "Default")
      (node (ref "R106") (pin "2") (pinfunction "2_2") (pintype "passive"))
      (node (ref "R109") (pin "2") (pinfunction "2_2") (pintype "passive"))
      (node (ref "U$21") (pin "3") (pinfunction "D_3") (pintype "passive"))
    )
    (net (code "466") (name "Net-(U$21-G)") (class "Default")
      (node (ref "R108") (pin "1") (pinfunction "1_1") (pintype "passive"))
      (node (ref "U$21") (pin "1") (pinfunction "G_1") (pintype "passive"))
    )
    (net (code "467") (name "Net-(U$21-S)") (class "Default")
      (node (ref "D19") (pin "C") (pinfunction "C_C") (pintype "passive"))
      (node (ref "D20") (pin "A") (pinfunction "A_A") (pintype "passive"))
      (node (ref "R105") (pin "2") (pinfunction "2_2") (pintype "passive"))
      (node (ref "R107") (pin "1") (pinfunction "1_1") (pintype "passive"))
      (node (ref "R112") (pin "1") (pinfunction "1_1") (pintype "passive"))
      (node (ref "R115") (pin "1") (pinfunction "1_1") (pintype "passive"))
      (node (ref "U$21") (pin "2") (pinfunction "S_2") (pintype "passive"))
    )
    (net (code "468") (name "Net-(U$22-D)") (class "Default")
      (node (ref "R112") (pin "2") (pinfunction "2_2") (pintype "passive"))
      (node (ref "R115") (pin "2") (pinfunction "2_2") (pintype "passive"))
      (node (ref "U$22") (pin "3") (pinfunction "D_3") (pintype "passive"))
    )
    (net (code "469") (name "Net-(U$22-G)") (class "Default")
      (node (ref "R114") (pin "1") (pinfunction "1_1") (pintype "passive"))
      (node (ref "U$22") (pin "1") (pinfunction "G_1") (pintype "passive"))
    )
    (net (code "470") (name "Net-(U$22-S)") (class "Default")
      (node (ref "D20") (pin "C") (pinfunction "C_C") (pintype "passive"))
      (node (ref "D21") (pin "A") (pinfunction "A_A") (pintype "passive"))
      (node (ref "R111") (pin "2") (pinfunction "2_2") (pintype "passive"))
      (node (ref "R113") (pin "1") (pinfunction "1_1") (pintype "passive"))
      (node (ref "R118") (pin "1") (pinfunction "1_1") (pintype "passive"))
      (node (ref "R121") (pin "1") (pinfunction "1_1") (pintype "passive"))
      (node (ref "U$22") (pin "2") (pinfunction "S_2") (pintype "passive"))
    )
    (net (code "471") (name "Net-(U$23-D)") (class "Default")
      (node (ref "R118") (pin "2") (pinfunction "2_2") (pintype "passive"))
      (node (ref "R121") (pin "2") (pinfunction "2_2") (pintype "passive"))
      (node (ref "U$23") (pin "3") (pinfunction "D_3") (pintype "passive"))
    )
    (net (code "472") (name "Net-(U$23-G)") (class "Default")
      (node (ref "R120") (pin "1") (pinfunction "1_1") (pintype "passive"))
      (node (ref "U$23") (pin "1") (pinfunction "G_1") (pintype "passive"))
    )
    (net (code "473") (name "Net-(U$23-S)") (class "Default")
      (node (ref "D21") (pin "C") (pinfunction "C_C") (pintype "passive"))
      (node (ref "D23") (pin "A") (pinfunction "A_A") (pintype "passive"))
      (node (ref "R117") (pin "2") (pinfunction "2_2") (pintype "passive"))
      (node (ref "R119") (pin "1") (pinfunction "1_1") (pintype "passive"))
      (node (ref "R130") (pin "1") (pinfunction "1_1") (pintype "passive"))
      (node (ref "R133") (pin "1") (pinfunction "1_1") (pintype "passive"))
      (node (ref "U$23") (pin "2") (pinfunction "S_2") (pintype "passive"))
    )
    (net (code "474") (name "Net-(U$24-D)") (class "Default")
      (node (ref "R124") (pin "2") (pinfunction "2_2") (pintype "passive"))
      (node (ref "R127") (pin "2") (pinfunction "2_2") (pintype "passive"))
      (node (ref "U$24") (pin "3") (pinfunction "D_3") (pintype "passive"))
    )
    (net (code "475") (name "Net-(U$24-G)") (class "Default")
      (node (ref "R126") (pin "1") (pinfunction "1_1") (pintype "passive"))
      (node (ref "U$24") (pin "1") (pinfunction "G_1") (pintype "passive"))
    )
    (net (code "476") (name "Net-(U$24-S)") (class "Default")
      (node (ref "D22") (pin "C") (pinfunction "C_C") (pintype "passive"))
      (node (ref "D24") (pin "A") (pinfunction "A_A") (pintype "passive"))
      (node (ref "R123") (pin "2") (pinfunction "2_2") (pintype "passive"))
      (node (ref "R125") (pin "1") (pinfunction "1_1") (pintype "passive"))
      (node (ref "R136") (pin "1") (pinfunction "1_1") (pintype "passive"))
      (node (ref "R139") (pin "1") (pinfunction "1_1") (pintype "passive"))
      (node (ref "U$24") (pin "2") (pinfunction "S_2") (pintype "passive"))
    )
    (net (code "477") (name "Net-(U$25-D)") (class "Default")
      (node (ref "R130") (pin "2") (pinfunction "2_2") (pintype "passive"))
      (node (ref "R133") (pin "2") (pinfunction "2_2") (pintype "passive"))
      (node (ref "U$25") (pin "3") (pinfunction "D_3") (pintype "passive"))
    )
    (net (code "478") (name "Net-(U$25-G)") (class "Default")
      (node (ref "R132") (pin "1") (pinfunction "1_1") (pintype "passive"))
      (node (ref "U$25") (pin "1") (pinfunction "G_1") (pintype "passive"))
    )
    (net (code "479") (name "Net-(U$25-S)") (class "Default")
      (node (ref "D22") (pin "A") (pinfunction "A_A") (pintype "passive"))
      (node (ref "D23") (pin "C") (pinfunction "C_C") (pintype "passive"))
      (node (ref "R124") (pin "1") (pinfunction "1_1") (pintype "passive"))
      (node (ref "R127") (pin "1") (pinfunction "1_1") (pintype "passive"))
      (node (ref "R129") (pin "2") (pinfunction "2_2") (pintype "passive"))
      (node (ref "R131") (pin "1") (pinfunction "1_1") (pintype "passive"))
      (node (ref "U$25") (pin "2") (pinfunction "S_2") (pintype "passive"))
    )
    (net (code "480") (name "Net-(U$26-D)") (class "Default")
      (node (ref "R136") (pin "2") (pinfunction "2_2") (pintype "passive"))
      (node (ref "R139") (pin "2") (pinfunction "2_2") (pintype "passive"))
      (node (ref "U$26") (pin "3") (pinfunction "D_3") (pintype "passive"))
    )
    (net (code "481") (name "Net-(U$26-G)") (class "Default")
      (node (ref "R138") (pin "1") (pinfunction "1_1") (pintype "passive"))
      (node (ref "U$26") (pin "1") (pinfunction "G_1") (pintype "passive"))
    )
    (net (code "482") (name "Net-(U$26-S)") (class "Default")
      (node (ref "D24") (pin "C") (pinfunction "C_C") (pintype "passive"))
      (node (ref "D25") (pin "A") (pinfunction "A_A") (pintype "passive"))
      (node (ref "R135") (pin "2") (pinfunction "2_2") (pintype "passive"))
      (node (ref "R137") (pin "1") (pinfunction "1_1") (pintype "passive"))
      (node (ref "R142") (pin "1") (pinfunction "1_1") (pintype "passive"))
      (node (ref "R145") (pin "1") (pinfunction "1_1") (pintype "passive"))
      (node (ref "U$26") (pin "2") (pinfunction "S_2") (pintype "passive"))
    )
    (net (code "483") (name "Net-(U$27-D)") (class "Default")
      (node (ref "R142") (pin "2") (pinfunction "2_2") (pintype "passive"))
      (node (ref "R145") (pin "2") (pinfunction "2_2") (pintype "passive"))
      (node (ref "U$27") (pin "3") (pinfunction "D_3") (pintype "passive"))
    )
    (net (code "484") (name "Net-(U$27-G)") (class "Default")
      (node (ref "R144") (pin "1") (pinfunction "1_1") (pintype "passive"))
      (node (ref "U$27") (pin "1") (pinfunction "G_1") (pintype "passive"))
    )
    (net (code "485") (name "Net-(U$27-S)") (class "Default")
      (node (ref "D25") (pin "C") (pinfunction "C_C") (pintype "passive"))
      (node (ref "D26") (pin "A") (pinfunction "A_A") (pintype "passive"))
      (node (ref "R141") (pin "2") (pinfunction "2_2") (pintype "passive"))
      (node (ref "R143") (pin "1") (pinfunction "1_1") (pintype "passive"))
      (node (ref "R148") (pin "1") (pinfunction "1_1") (pintype "passive"))
      (node (ref "R151") (pin "1") (pinfunction "1_1") (pintype "passive"))
      (node (ref "U$27") (pin "2") (pinfunction "S_2") (pintype "passive"))
    )
    (net (code "486") (name "Net-(U$28-D)") (class "Default")
      (node (ref "R148") (pin "2") (pinfunction "2_2") (pintype "passive"))
      (node (ref "R151") (pin "2") (pinfunction "2_2") (pintype "passive"))
      (node (ref "U$28") (pin "3") (pinfunction "D_3") (pintype "passive"))
    )
    (net (code "487") (name "Net-(U$28-G)") (class "Default")
      (node (ref "R150") (pin "1") (pinfunction "1_1") (pintype "passive"))
      (node (ref "U$28") (pin "1") (pinfunction "G_1") (pintype "passive"))
    )
    (net (code "488") (name "Net-(U$28-S)") (class "Default")
      (node (ref "D26") (pin "C") (pinfunction "C_C") (pintype "passive"))
      (node (ref "D27") (pin "A") (pinfunction "A_A") (pintype "passive"))
      (node (ref "D29") (pin "A") (pinfunction "A_A") (pintype "passive"))
      (node (ref "R147") (pin "2") (pinfunction "2_2") (pintype "passive"))
      (node (ref "R149") (pin "1") (pinfunction "1_1") (pintype "passive"))
      (node (ref "R154") (pin "1") (pinfunction "1_1") (pintype "passive"))
      (node (ref "R157") (pin "1") (pinfunction "1_1") (pintype "passive"))
      (node (ref "U$28") (pin "2") (pinfunction "S_2") (pintype "passive"))
    )
    (net (code "489") (name "Net-(U$29-D)") (class "Default")
      (node (ref "R154") (pin "2") (pinfunction "2_2") (pintype "passive"))
      (node (ref "R157") (pin "2") (pinfunction "2_2") (pintype "passive"))
      (node (ref "U$29") (pin "3") (pinfunction "D_3") (pintype "passive"))
    )
    (net (code "490") (name "Net-(U$29-G)") (class "Default")
      (node (ref "R156") (pin "1") (pinfunction "1_1") (pintype "passive"))
      (node (ref "U$29") (pin "1") (pinfunction "G_1") (pintype "passive"))
    )
    (net (code "491") (name "Net-(U$29-S)") (class "Default")
      (node (ref "D27") (pin "C") (pinfunction "C_C") (pintype "passive"))
      (node (ref "R153") (pin "2") (pinfunction "2_2") (pintype "passive"))
      (node (ref "R155") (pin "1") (pinfunction "1_1") (pintype "passive"))
      (node (ref "U$29") (pin "2") (pinfunction "S_2") (pintype "passive"))
    )
    (net (code "492") (name "Net-(U$31-A0)") (class "Default")
      (node (ref "C53") (pin "2") (pinfunction "2_2") (pintype "passive"))
      (node (ref "R330") (pin "1") (pinfunction "1_1") (pintype "passive"))
      (node (ref "R331") (pin "1") (pinfunction "1_1") (pintype "passive"))
      (node (ref "U$31") (pin "32") (pinfunction "VREG_32") (pintype "bidirectional"))
      (node (ref "U$31") (pin "37") (pinfunction "A0_37") (pintype "bidirectional"))
      (node (ref "U$31") (pin "38") (pinfunction "A1_38") (pintype "bidirectional"))
      (node (ref "U$32") (pin "10") (pinfunction "EN2_10") (pintype "bidirectional"))
      (node (ref "U$32") (pin "16") (pinfunction "VDD2_16") (pintype "bidirectional"))
    )
    (net (code "493") (name "Net-(U$31-CO)") (class "Default")
      (node (ref "C51") (pin "2") (pinfunction "2_2") (pintype "passive"))
      (node (ref "R329") (pin "2") (pinfunction "2_2") (pintype "passive"))
      (node (ref "U$31") (pin "26") (pinfunction "CO_26") (pintype "bidirectional"))
    )
    (net (code "494") (name "Net-(U$31-CSBI)") (class "Default")
      (node (ref "U$31") (pin "44") (pinfunction "CSBI_44") (pintype "bidirectional"))
      (node (ref "U$32") (pin "12") (pinfunction "B3_12") (pintype "bidirectional"))
    )
    (net (code "495") (name "Net-(U$31-SCKI)") (class "Default")
      (node (ref "U$31") (pin "41") (pinfunction "SCKI_41") (pintype "bidirectional"))
      (node (ref "U$32") (pin "14") (pinfunction "B1_14") (pintype "bidirectional"))
    )
    (net (code "496") (name "Net-(U$31-SDI)") (class "Default")
      (node (ref "U$31") (pin "42") (pinfunction "SDI_42") (pintype "bidirectional"))
      (node (ref "U$32") (pin "13") (pinfunction "B2_13") (pintype "bidirectional"))
    )
    (net (code "497") (name "Net-(U$31-SDO)") (class "Default")
      (node (ref "R331") (pin "2") (pinfunction "2_2") (pintype "passive"))
      (node (ref "U$31") (pin "43") (pinfunction "SDO_43") (pintype "bidirectional"))
      (node (ref "U$32") (pin "11") (pinfunction "B4_11") (pintype "bidirectional"))
    )
    (net (code "498") (name "Net-(U$31-VREFF)") (class "Default")
      (node (ref "C52") (pin "2") (pinfunction "2_2") (pintype "passive"))
      (node (ref "U$31") (pin "31") (pinfunction "VREFF_31") (pintype "bidirectional"))
    )
    (net (code "499") (name "Net-(U$31-WDTB)") (class "Default")
      (node (ref "R330") (pin "2") (pinfunction "2_2") (pintype "passive"))
      (node (ref "U$31") (pin "34") (pinfunction "WDTB_34") (pintype "bidirectional"))
    )
    (net (code "500") (name "Net-(U$32-A4)") (class "Default")
      (node (ref "D60") (pin "C") (pinfunction "C_C") (pintype "passive"))
      (node (ref "U$32") (pin "6") (pinfunction "A4_6") (pintype "bidirectional"))
    )
    (net (code "501") (name "Net-(U$33-D)") (class "Default")
      (node (ref "R2") (pin "2") (pinfunction "2_2") (pintype "passive"))
      (node (ref "R87") (pin "2") (pinfunction "2_2") (pintype "passive"))
      (node (ref "U$33") (pin "3") (pinfunction "D_3") (pintype "passive"))
    )
    (net (code "502") (name "Net-(U$33-G)") (class "Default")
      (node (ref "R86") (pin "1") (pinfunction "1_1") (pintype "passive"))
      (node (ref "U$33") (pin "1") (pinfunction "G_1") (pintype "passive"))
    )
    (net (code "503") (name "Net-(U$33-S)") (class "Default")
      (node (ref "D34") (pin "C") (pinfunction "C_C") (pintype "passive"))
      (node (ref "D48") (pin "A") (pinfunction "A_A") (pintype "passive"))
      (node (ref "R179") (pin "1") (pinfunction "1_1") (pintype "passive"))
      (node (ref "R257") (pin "1") (pinfunction "1_1") (pintype "passive"))
      (node (ref "R332") (pin "2") (pinfunction "2_2") (pintype "passive"))
      (node (ref "R78") (pin "1") (pinfunction "1_1") (pintype "passive"))
      (node (ref "U$33") (pin "2") (pinfunction "S_2") (pintype "passive"))
    )
    (net (code "504") (name "Net-(U$34-A1)") (class "Default")
      (node (ref "C78") (pin "2") (pinfunction "2_2") (pintype "passive"))
      (node (ref "R263") (pin "1") (pinfunction "1_1") (pintype "passive"))
      (node (ref "R264") (pin "1") (pinfunction "1_1") (pintype "passive"))
      (node (ref "U$34") (pin "32") (pinfunction "VREG_32") (pintype "bidirectional"))
      (node (ref "U$34") (pin "38") (pinfunction "A1_38") (pintype "bidirectional"))
      (node (ref "U$35") (pin "10") (pinfunction "EN2_10") (pintype "bidirectional"))
      (node (ref "U$35") (pin "16") (pinfunction "VDD2_16") (pintype "bidirectional"))
    )
    (net (code "505") (name "Net-(U$34-CO)") (class "Default")
      (node (ref "C76") (pin "2") (pinfunction "2_2") (pintype "passive"))
      (node (ref "R262") (pin "2") (pinfunction "2_2") (pintype "passive"))
      (node (ref "U$34") (pin "26") (pinfunction "CO_26") (pintype "bidirectional"))
    )
    (net (code "506") (name "Net-(U$34-CSBI)") (class "Default")
      (node (ref "U$34") (pin "44") (pinfunction "CSBI_44") (pintype "bidirectional"))
      (node (ref "U$35") (pin "12") (pinfunction "B3_12") (pintype "bidirectional"))
    )
    (net (code "507") (name "Net-(U$34-SCKI)") (class "Default")
      (node (ref "U$34") (pin "41") (pinfunction "SCKI_41") (pintype "bidirectional"))
      (node (ref "U$35") (pin "14") (pinfunction "B1_14") (pintype "bidirectional"))
    )
    (net (code "508") (name "Net-(U$34-SDI)") (class "Default")
      (node (ref "U$34") (pin "42") (pinfunction "SDI_42") (pintype "bidirectional"))
      (node (ref "U$35") (pin "13") (pinfunction "B2_13") (pintype "bidirectional"))
    )
    (net (code "509") (name "Net-(U$34-SDO)") (class "Default")
      (node (ref "R264") (pin "2") (pinfunction "2_2") (pintype "passive"))
      (node (ref "U$34") (pin "43") (pinfunction "SDO_43") (pintype "bidirectional"))
      (node (ref "U$35") (pin "11") (pinfunction "B4_11") (pintype "bidirectional"))
    )
    (net (code "510") (name "Net-(U$34-VREFF)") (class "Default")
      (node (ref "C77") (pin "2") (pinfunction "2_2") (pintype "passive"))
      (node (ref "U$34") (pin "31") (pinfunction "VREFF_31") (pintype "bidirectional"))
    )
    (net (code "511") (name "Net-(U$34-WDTB)") (class "Default")
      (node (ref "R263") (pin "2") (pinfunction "2_2") (pintype "passive"))
      (node (ref "U$34") (pin "34") (pinfunction "WDTB_34") (pintype "bidirectional"))
    )
    (net (code "512") (name "Net-(U$35-A4)") (class "Default")
      (node (ref "D47") (pin "C") (pinfunction "C_C") (pintype "passive"))
      (node (ref "U$35") (pin "6") (pinfunction "A4_6") (pintype "bidirectional"))
    )
    (net (code "513") (name "Net-(U$36-D)") (class "Default")
      (node (ref "R181") (pin "2") (pinfunction "2_2") (pintype "passive"))
      (node (ref "R185") (pin "2") (pinfunction "2_2") (pintype "passive"))
      (node (ref "U$36") (pin "3") (pinfunction "D_3") (pintype "passive"))
    )
    (net (code "514") (name "Net-(U$36-G)") (class "Default")
      (node (ref "R184") (pin "1") (pinfunction "1_1") (pintype "passive"))
      (node (ref "U$36") (pin "1") (pinfunction "G_1") (pintype "passive"))
    )
    (net (code "515") (name "Net-(U$36-S)") (class "Default")
      (node (ref "D15") (pin "C") (pinfunction "C_C") (pintype "passive"))
      (node (ref "D31") (pin "A") (pinfunction "A_A") (pintype "passive"))
      (node (ref "R183") (pin "1") (pinfunction "1_1") (pintype "passive"))
      (node (ref "R194") (pin "1") (pinfunction "1_1") (pintype "passive"))
      (node (ref "R197") (pin "1") (pinfunction "1_1") (pintype "passive"))
      (node (ref "R265") (pin "2") (pinfunction "2_2") (pintype "passive"))
      (node (ref "U$36") (pin "2") (pinfunction "S_2") (pintype "passive"))
    )
    (net (code "516") (name "Net-(U$37-D)") (class "Default")
      (node (ref "R188") (pin "2") (pinfunction "2_2") (pintype "passive"))
      (node (ref "R191") (pin "2") (pinfunction "2_2") (pintype "passive"))
      (node (ref "U$37") (pin "3") (pinfunction "D_3") (pintype "passive"))
    )
    (net (code "517") (name "Net-(U$37-G)") (class "Default")
      (node (ref "R190") (pin "1") (pinfunction "1_1") (pintype "passive"))
      (node (ref "U$37") (pin "1") (pinfunction "G_1") (pintype "passive"))
    )
    (net (code "518") (name "Net-(U$37-S)") (class "Default")
      (node (ref "D15") (pin "A") (pinfunction "A_A") (pintype "passive"))
      (node (ref "D30") (pin "C") (pinfunction "C_C") (pintype "passive"))
      (node (ref "D45") (pin "C") (pinfunction "C_C") (pintype "passive"))
      (node (ref "R181") (pin "1") (pinfunction "1_1") (pintype "passive"))
      (node (ref "R185") (pin "1") (pinfunction "1_1") (pintype "passive"))
      (node (ref "R187") (pin "2") (pinfunction "2_2") (pintype "passive"))
      (node (ref "R189") (pin "1") (pinfunction "1_1") (pintype "passive"))
      (node (ref "U$37") (pin "2") (pinfunction "S_2") (pintype "passive"))
    )
    (net (code "519") (name "Net-(U$38-D)") (class "Default")
      (node (ref "R194") (pin "2") (pinfunction "2_2") (pintype "passive"))
      (node (ref "R197") (pin "2") (pinfunction "2_2") (pintype "passive"))
      (node (ref "U$38") (pin "3") (pinfunction "D_3") (pintype "passive"))
    )
    (net (code "520") (name "Net-(U$38-G)") (class "Default")
      (node (ref "R196") (pin "1") (pinfunction "1_1") (pintype "passive"))
      (node (ref "U$38") (pin "1") (pinfunction "G_1") (pintype "passive"))
    )
    (net (code "521") (name "Net-(U$38-S)") (class "Default")
      (node (ref "D31") (pin "C") (pinfunction "C_C") (pintype "passive"))
      (node (ref "D35") (pin "A") (pinfunction "A_A") (pintype "passive"))
      (node (ref "R193") (pin "2") (pinfunction "2_2") (pintype "passive"))
      (node (ref "R195") (pin "1") (pinfunction "1_1") (pintype "passive"))
      (node (ref "R200") (pin "1") (pinfunction "1_1") (pintype "passive"))
      (node (ref "R203") (pin "1") (pinfunction "1_1") (pintype "passive"))
      (node (ref "U$38") (pin "2") (pinfunction "S_2") (pintype "passive"))
    )
    (net (code "522") (name "Net-(U$39-D)") (class "Default")
      (node (ref "R200") (pin "2") (pinfunction "2_2") (pintype "passive"))
      (node (ref "R203") (pin "2") (pinfunction "2_2") (pintype "passive"))
      (node (ref "U$39") (pin "3") (pinfunction "D_3") (pintype "passive"))
    )
    (net (code "523") (name "Net-(U$39-G)") (class "Default")
      (node (ref "R202") (pin "1") (pinfunction "1_1") (pintype "passive"))
      (node (ref "U$39") (pin "1") (pinfunction "G_1") (pintype "passive"))
    )
    (net (code "524") (name "Net-(U$39-S)") (class "Default")
      (node (ref "D35") (pin "C") (pinfunction "C_C") (pintype "passive"))
      (node (ref "D37") (pin "A") (pinfunction "A_A") (pintype "passive"))
      (node (ref "R199") (pin "2") (pinfunction "2_2") (pintype "passive"))
      (node (ref "R201") (pin "1") (pinfunction "1_1") (pintype "passive"))
      (node (ref "R206") (pin "1") (pinfunction "1_1") (pintype "passive"))
      (node (ref "R209") (pin "1") (pinfunction "1_1") (pintype "passive"))
      (node (ref "U$39") (pin "2") (pinfunction "S_2") (pintype "passive"))
    )
    (net (code "525") (name "Net-(U$40-D)") (class "Default")
      (node (ref "R206") (pin "2") (pinfunction "2_2") (pintype "passive"))
      (node (ref "R209") (pin "2") (pinfunction "2_2") (pintype "passive"))
      (node (ref "U$40") (pin "3") (pinfunction "D_3") (pintype "passive"))
    )
    (net (code "526") (name "Net-(U$40-G)") (class "Default")
      (node (ref "R208") (pin "1") (pinfunction "1_1") (pintype "passive"))
      (node (ref "U$40") (pin "1") (pinfunction "G_1") (pintype "passive"))
    )
    (net (code "527") (name "Net-(U$40-S)") (class "Default")
      (node (ref "D37") (pin "C") (pinfunction "C_C") (pintype "passive"))
      (node (ref "D38") (pin "A") (pinfunction "A_A") (pintype "passive"))
      (node (ref "R205") (pin "2") (pinfunction "2_2") (pintype "passive"))
      (node (ref "R207") (pin "1") (pinfunction "1_1") (pintype "passive"))
      (node (ref "R212") (pin "1") (pinfunction "1_1") (pintype "passive"))
      (node (ref "R215") (pin "1") (pinfunction "1_1") (pintype "passive"))
      (node (ref "U$40") (pin "2") (pinfunction "S_2") (pintype "passive"))
    )
    (net (code "528") (name "Net-(U$41-D)") (class "Default")
      (node (ref "R212") (pin "2") (pinfunction "2_2") (pintype "passive"))
      (node (ref "R215") (pin "2") (pinfunction "2_2") (pintype "passive"))
      (node (ref "U$41") (pin "3") (pinfunction "D_3") (pintype "passive"))
    )
    (net (code "529") (name "Net-(U$41-G)") (class "Default")
      (node (ref "R214") (pin "1") (pinfunction "1_1") (pintype "passive"))
      (node (ref "U$41") (pin "1") (pinfunction "G_1") (pintype "passive"))
    )
    (net (code "530") (name "Net-(U$41-S)") (class "Default")
      (node (ref "D38") (pin "C") (pinfunction "C_C") (pintype "passive"))
      (node (ref "D40") (pin "A") (pinfunction "A_A") (pintype "passive"))
      (node (ref "R211") (pin "2") (pinfunction "2_2") (pintype "passive"))
      (node (ref "R213") (pin "1") (pinfunction "1_1") (pintype "passive"))
      (node (ref "R224") (pin "1") (pinfunction "1_1") (pintype "passive"))
      (node (ref "R227") (pin "1") (pinfunction "1_1") (pintype "passive"))
      (node (ref "U$41") (pin "2") (pinfunction "S_2") (pintype "passive"))
    )
    (net (code "531") (name "Net-(U$42-D)") (class "Default")
      (node (ref "R218") (pin "2") (pinfunction "2_2") (pintype "passive"))
      (node (ref "R221") (pin "2") (pinfunction "2_2") (pintype "passive"))
      (node (ref "U$42") (pin "3") (pinfunction "D_3") (pintype "passive"))
    )
    (net (code "532") (name "Net-(U$42-G)") (class "Default")
      (node (ref "R220") (pin "1") (pinfunction "1_1") (pintype "passive"))
      (node (ref "U$42") (pin "1") (pinfunction "G_1") (pintype "passive"))
    )
    (net (code "533") (name "Net-(U$42-S)") (class "Default")
      (node (ref "D39") (pin "C") (pinfunction "C_C") (pintype "passive"))
      (node (ref "D41") (pin "A") (pinfunction "A_A") (pintype "passive"))
      (node (ref "R217") (pin "2") (pinfunction "2_2") (pintype "passive"))
      (node (ref "R219") (pin "1") (pinfunction "1_1") (pintype "passive"))
      (node (ref "R230") (pin "1") (pinfunction "1_1") (pintype "passive"))
      (node (ref "R233") (pin "1") (pinfunction "1_1") (pintype "passive"))
      (node (ref "U$42") (pin "2") (pinfunction "S_2") (pintype "passive"))
    )
    (net (code "534") (name "Net-(U$43-D)") (class "Default")
      (node (ref "R173") (pin "2") (pinfunction "2_2") (pintype "passive"))
      (node (ref "R176") (pin "2") (pinfunction "2_2") (pintype "passive"))
      (node (ref "U$43") (pin "3") (pinfunction "D_3") (pintype "passive"))
    )
    (net (code "535") (name "Net-(U$43-G)") (class "Default")
      (node (ref "R175") (pin "1") (pinfunction "1_1") (pintype "passive"))
      (node (ref "U$43") (pin "1") (pinfunction "G_1") (pintype "passive"))
    )
    (net (code "536") (name "Net-(U$43-S)") (class "Default")
      (node (ref "D34") (pin "A") (pinfunction "A_A") (pintype "passive"))
      (node (ref "D36") (pin "C") (pinfunction "C_C") (pintype "passive"))
      (node (ref "D58") (pin "C") (pinfunction "C_C") (pintype "passive"))
      (node (ref "R171") (pin "2") (pinfunction "2_2") (pintype "passive"))
      (node (ref "R174") (pin "1") (pinfunction "1_1") (pintype "passive"))
      (node (ref "R2") (pin "1") (pinfunction "1_1") (pintype "passive"))
      (node (ref "R87") (pin "1") (pinfunction "1_1") (pintype "passive"))
      (node (ref "U$43") (pin "2") (pinfunction "S_2") (pintype "passive"))
    )
    (net (code "537") (name "Net-(U$44-D)") (class "Default")
      (node (ref "R179") (pin "2") (pinfunction "2_2") (pintype "passive"))
      (node (ref "R257") (pin "2") (pinfunction "2_2") (pintype "passive"))
      (node (ref "U$44") (pin "3") (pinfunction "D_3") (pintype "passive"))
    )
    (net (code "538") (name "Net-(U$44-G)") (class "Default")
      (node (ref "R182") (pin "1") (pinfunction "1_1") (pintype "passive"))
      (node (ref "U$44") (pin "1") (pinfunction "G_1") (pintype "passive"))
    )
    (net (code "539") (name "Net-(U$44-S)") (class "Default")
      (node (ref "D48") (pin "C") (pinfunction "C_C") (pintype "passive"))
      (node (ref "D49") (pin "A") (pinfunction "A_A") (pintype "passive"))
      (node (ref "R178") (pin "2") (pinfunction "2_2") (pintype "passive"))
      (node (ref "R180") (pin "1") (pinfunction "1_1") (pintype "passive"))
      (node (ref "R268") (pin "1") (pinfunction "1_1") (pintype "passive"))
      (node (ref "R271") (pin "1") (pinfunction "1_1") (pintype "passive"))
      (node (ref "U$44") (pin "2") (pinfunction "S_2") (pintype "passive"))
    )
    (net (code "540") (name "Net-(U$45-D)") (class "Default")
      (node (ref "R224") (pin "2") (pinfunction "2_2") (pintype "passive"))
      (node (ref "R227") (pin "2") (pinfunction "2_2") (pintype "passive"))
      (node (ref "U$45") (pin "3") (pinfunction "D_3") (pintype "passive"))
    )
    (net (code "541") (name "Net-(U$45-G)") (class "Default")
      (node (ref "R226") (pin "1") (pinfunction "1_1") (pintype "passive"))
      (node (ref "U$45") (pin "1") (pinfunction "G_1") (pintype "passive"))
    )
    (net (code "542") (name "Net-(U$45-S)") (class "Default")
      (node (ref "D39") (pin "A") (pinfunction "A_A") (pintype "passive"))
      (node (ref "D40") (pin "C") (pinfunction "C_C") (pintype "passive"))
      (node (ref "R218") (pin "1") (pinfunction "1_1") (pintype "passive"))
      (node (ref "R221") (pin "1") (pinfunction "1_1") (pintype "passive"))
      (node (ref "R223") (pin "2") (pinfunction "2_2") (pintype "passive"))
      (node (ref "R225") (pin "1") (pinfunction "1_1") (pintype "passive"))
      (node (ref "U$45") (pin "2") (pinfunction "S_2") (pintype "passive"))
    )
    (net (code "543") (name "Net-(U$46-D)") (class "Default")
      (node (ref "R230") (pin "2") (pinfunction "2_2") (pintype "passive"))
      (node (ref "R233") (pin "2") (pinfunction "2_2") (pintype "passive"))
      (node (ref "U$46") (pin "3") (pinfunction "D_3") (pintype "passive"))
    )
    (net (code "544") (name "Net-(U$46-G)") (class "Default")
      (node (ref "R232") (pin "1") (pinfunction "1_1") (pintype "passive"))
      (node (ref "U$46") (pin "1") (pinfunction "G_1") (pintype "passive"))
    )
    (net (code "545") (name "Net-(U$46-S)") (class "Default")
      (node (ref "D41") (pin "C") (pinfunction "C_C") (pintype "passive"))
      (node (ref "D42") (pin "A") (pinfunction "A_A") (pintype "passive"))
      (node (ref "R229") (pin "2") (pinfunction "2_2") (pintype "passive"))
      (node (ref "R231") (pin "1") (pinfunction "1_1") (pintype "passive"))
      (node (ref "R236") (pin "1") (pinfunction "1_1") (pintype "passive"))
      (node (ref "R239") (pin "1") (pinfunction "1_1") (pintype "passive"))
      (node (ref "U$46") (pin "2") (pinfunction "S_2") (pintype "passive"))
    )
    (net (code "546") (name "Net-(U$47-D)") (class "Default")
      (node (ref "R236") (pin "2") (pinfunction "2_2") (pintype "passive"))
      (node (ref "R239") (pin "2") (pinfunction "2_2") (pintype "passive"))
      (node (ref "U$47") (pin "3") (pinfunction "D_3") (pintype "passive"))
    )
    (net (code "547") (name "Net-(U$47-G)") (class "Default")
      (node (ref "R238") (pin "1") (pinfunction "1_1") (pintype "passive"))
      (node (ref "U$47") (pin "1") (pinfunction "G_1") (pintype "passive"))
    )
    (net (code "548") (name "Net-(U$47-S)") (class "Default")
      (node (ref "D42") (pin "C") (pinfunction "C_C") (pintype "passive"))
      (node (ref "D43") (pin "A") (pinfunction "A_A") (pintype "passive"))
      (node (ref "R235") (pin "2") (pinfunction "2_2") (pintype "passive"))
      (node (ref "R237") (pin "1") (pinfunction "1_1") (pintype "passive"))
      (node (ref "R242") (pin "1") (pinfunction "1_1") (pintype "passive"))
      (node (ref "R245") (pin "1") (pinfunction "1_1") (pintype "passive"))
      (node (ref "U$47") (pin "2") (pinfunction "S_2") (pintype "passive"))
    )
    (net (code "549") (name "Net-(U$48-D)") (class "Default")
      (node (ref "R242") (pin "2") (pinfunction "2_2") (pintype "passive"))
      (node (ref "R245") (pin "2") (pinfunction "2_2") (pintype "passive"))
      (node (ref "U$48") (pin "3") (pinfunction "D_3") (pintype "passive"))
    )
    (net (code "550") (name "Net-(U$48-G)") (class "Default")
      (node (ref "R244") (pin "1") (pinfunction "1_1") (pintype "passive"))
      (node (ref "U$48") (pin "1") (pinfunction "G_1") (pintype "passive"))
    )
    (net (code "551") (name "Net-(U$48-S)") (class "Default")
      (node (ref "D43") (pin "C") (pinfunction "C_C") (pintype "passive"))
      (node (ref "D44") (pin "A") (pinfunction "A_A") (pintype "passive"))
      (node (ref "D46") (pin "A") (pinfunction "A_A") (pintype "passive"))
      (node (ref "R241") (pin "2") (pinfunction "2_2") (pintype "passive"))
      (node (ref "R243") (pin "1") (pinfunction "1_1") (pintype "passive"))
      (node (ref "R248") (pin "1") (pinfunction "1_1") (pintype "passive"))
      (node (ref "R251") (pin "1") (pinfunction "1_1") (pintype "passive"))
      (node (ref "U$48") (pin "2") (pinfunction "S_2") (pintype "passive"))
    )
    (net (code "552") (name "Net-(U$49-D)") (class "Default")
      (node (ref "R248") (pin "2") (pinfunction "2_2") (pintype "passive"))
      (node (ref "R251") (pin "2") (pinfunction "2_2") (pintype "passive"))
      (node (ref "U$49") (pin "3") (pinfunction "D_3") (pintype "passive"))
    )
    (net (code "553") (name "Net-(U$49-G)") (class "Default")
      (node (ref "R250") (pin "1") (pinfunction "1_1") (pintype "passive"))
      (node (ref "U$49") (pin "1") (pinfunction "G_1") (pintype "passive"))
    )
    (net (code "554") (name "Net-(U$49-S)") (class "Default")
      (node (ref "D44") (pin "C") (pinfunction "C_C") (pintype "passive"))
      (node (ref "R247") (pin "2") (pinfunction "2_2") (pintype "passive"))
      (node (ref "R249") (pin "1") (pinfunction "1_1") (pintype "passive"))
      (node (ref "U$49") (pin "2") (pinfunction "S_2") (pintype "passive"))
    )
    (net (code "555") (name "Net-(U$51-D)") (class "Default")
      (node (ref "R268") (pin "2") (pinfunction "2_2") (pintype "passive"))
      (node (ref "R271") (pin "2") (pinfunction "2_2") (pintype "passive"))
      (node (ref "U$51") (pin "3") (pinfunction "D_3") (pintype "passive"))
    )
    (net (code "556") (name "Net-(U$51-G)") (class "Default")
      (node (ref "R270") (pin "1") (pinfunction "1_1") (pintype "passive"))
      (node (ref "U$51") (pin "1") (pinfunction "G_1") (pintype "passive"))
    )
    (net (code "557") (name "Net-(U$51-S)") (class "Default")
      (node (ref "D49") (pin "C") (pinfunction "C_C") (pintype "passive"))
      (node (ref "D50") (pin "A") (pinfunction "A_A") (pintype "passive"))
      (node (ref "R267") (pin "2") (pinfunction "2_2") (pintype "passive"))
      (node (ref "R269") (pin "1") (pinfunction "1_1") (pintype "passive"))
      (node (ref "R274") (pin "1") (pinfunction "1_1") (pintype "passive"))
      (node (ref "R277") (pin "1") (pinfunction "1_1") (pintype "passive"))
      (node (ref "U$51") (pin "2") (pinfunction "S_2") (pintype "passive"))
    )
    (net (code "558") (name "Net-(U$52-D)") (class "Default")
      (node (ref "R274") (pin "2") (pinfunction "2_2") (pintype "passive"))
      (node (ref "R277") (pin "2") (pinfunction "2_2") (pintype "passive"))
      (node (ref "U$52") (pin "3") (pinfunction "D_3") (pintype "passive"))
    )
    (net (code "559") (name "Net-(U$52-G)") (class "Default")
      (node (ref "R276") (pin "1") (pinfunction "1_1") (pintype "passive"))
      (node (ref "U$52") (pin "1") (pinfunction "G_1") (pintype "passive"))
    )
    (net (code "560") (name "Net-(U$52-S)") (class "Default")
      (node (ref "D50") (pin "C") (pinfunction "C_C") (pintype "passive"))
      (node (ref "D51") (pin "A") (pinfunction "A_A") (pintype "passive"))
      (node (ref "R273") (pin "2") (pinfunction "2_2") (pintype "passive"))
      (node (ref "R275") (pin "1") (pinfunction "1_1") (pintype "passive"))
      (node (ref "R280") (pin "1") (pinfunction "1_1") (pintype "passive"))
      (node (ref "R283") (pin "1") (pinfunction "1_1") (pintype "passive"))
      (node (ref "U$52") (pin "2") (pinfunction "S_2") (pintype "passive"))
    )
    (net (code "561") (name "Net-(U$53-D)") (class "Default")
      (node (ref "R280") (pin "2") (pinfunction "2_2") (pintype "passive"))
      (node (ref "R283") (pin "2") (pinfunction "2_2") (pintype "passive"))
      (node (ref "U$53") (pin "3") (pinfunction "D_3") (pintype "passive"))
    )
    (net (code "562") (name "Net-(U$53-G)") (class "Default")
      (node (ref "R282") (pin "1") (pinfunction "1_1") (pintype "passive"))
      (node (ref "U$53") (pin "1") (pinfunction "G_1") (pintype "passive"))
    )
    (net (code "563") (name "Net-(U$53-S)") (class "Default")
      (node (ref "D51") (pin "C") (pinfunction "C_C") (pintype "passive"))
      (node (ref "D53") (pin "A") (pinfunction "A_A") (pintype "passive"))
      (node (ref "R279") (pin "2") (pinfunction "2_2") (pintype "passive"))
      (node (ref "R281") (pin "1") (pinfunction "1_1") (pintype "passive"))
      (node (ref "R292") (pin "1") (pinfunction "1_1") (pintype "passive"))
      (node (ref "R295") (pin "1") (pinfunction "1_1") (pintype "passive"))
      (node (ref "U$53") (pin "2") (pinfunction "S_2") (pintype "passive"))
    )
    (net (code "564") (name "Net-(U$54-D)") (class "Default")
      (node (ref "R286") (pin "2") (pinfunction "2_2") (pintype "passive"))
      (node (ref "R289") (pin "2") (pinfunction "2_2") (pintype "passive"))
      (node (ref "U$54") (pin "3") (pinfunction "D_3") (pintype "passive"))
    )
    (net (code "565") (name "Net-(U$54-G)") (class "Default")
      (node (ref "R288") (pin "1") (pinfunction "1_1") (pintype "passive"))
      (node (ref "U$54") (pin "1") (pinfunction "G_1") (pintype "passive"))
    )
    (net (code "566") (name "Net-(U$54-S)") (class "Default")
      (node (ref "D52") (pin "C") (pinfunction "C_C") (pintype "passive"))
      (node (ref "D54") (pin "A") (pinfunction "A_A") (pintype "passive"))
      (node (ref "R285") (pin "2") (pinfunction "2_2") (pintype "passive"))
      (node (ref "R287") (pin "1") (pinfunction "1_1") (pintype "passive"))
      (node (ref "R298") (pin "1") (pinfunction "1_1") (pintype "passive"))
      (node (ref "R301") (pin "1") (pinfunction "1_1") (pintype "passive"))
      (node (ref "U$54") (pin "2") (pinfunction "S_2") (pintype "passive"))
    )
    (net (code "567") (name "Net-(U$55-D)") (class "Default")
      (node (ref "R292") (pin "2") (pinfunction "2_2") (pintype "passive"))
      (node (ref "R295") (pin "2") (pinfunction "2_2") (pintype "passive"))
      (node (ref "U$55") (pin "3") (pinfunction "D_3") (pintype "passive"))
    )
    (net (code "568") (name "Net-(U$55-G)") (class "Default")
      (node (ref "R294") (pin "1") (pinfunction "1_1") (pintype "passive"))
      (node (ref "U$55") (pin "1") (pinfunction "G_1") (pintype "passive"))
    )
    (net (code "569") (name "Net-(U$55-S)") (class "Default")
      (node (ref "D52") (pin "A") (pinfunction "A_A") (pintype "passive"))
      (node (ref "D53") (pin "C") (pinfunction "C_C") (pintype "passive"))
      (node (ref "R286") (pin "1") (pinfunction "1_1") (pintype "passive"))
      (node (ref "R289") (pin "1") (pinfunction "1_1") (pintype "passive"))
      (node (ref "R291") (pin "2") (pinfunction "2_2") (pintype "passive"))
      (node (ref "R293") (pin "1") (pinfunction "1_1") (pintype "passive"))
      (node (ref "U$55") (pin "2") (pinfunction "S_2") (pintype "passive"))
    )
    (net (code "570") (name "Net-(U$56-D)") (class "Default")
      (node (ref "R298") (pin "2") (pinfunction "2_2") (pintype "passive"))
      (node (ref "R301") (pin "2") (pinfunction "2_2") (pintype "passive"))
      (node (ref "U$56") (pin "3") (pinfunction "D_3") (pintype "passive"))
    )
    (net (code "571") (name "Net-(U$56-G)") (class "Default")
      (node (ref "R300") (pin "1") (pinfunction "1_1") (pintype "passive"))
      (node (ref "U$56") (pin "1") (pinfunction "G_1") (pintype "passive"))
    )
    (net (code "572") (name "Net-(U$56-S)") (class "Default")
      (node (ref "D54") (pin "C") (pinfunction "C_C") (pintype "passive"))
      (node (ref "D55") (pin "A") (pinfunction "A_A") (pintype "passive"))
      (node (ref "R297") (pin "2") (pinfunction "2_2") (pintype "passive"))
      (node (ref "R299") (pin "1") (pinfunction "1_1") (pintype "passive"))
      (node (ref "R304") (pin "1") (pinfunction "1_1") (pintype "passive"))
      (node (ref "R307") (pin "1") (pinfunction "1_1") (pintype "passive"))
      (node (ref "U$56") (pin "2") (pinfunction "S_2") (pintype "passive"))
    )
    (net (code "573") (name "Net-(U$57-D)") (class "Default")
      (node (ref "R304") (pin "2") (pinfunction "2_2") (pintype "passive"))
      (node (ref "R307") (pin "2") (pinfunction "2_2") (pintype "passive"))
      (node (ref "U$57") (pin "3") (pinfunction "D_3") (pintype "passive"))
    )
    (net (code "574") (name "Net-(U$57-G)") (class "Default")
      (node (ref "R306") (pin "1") (pinfunction "1_1") (pintype "passive"))
      (node (ref "U$57") (pin "1") (pinfunction "G_1") (pintype "passive"))
    )
    (net (code "575") (name "Net-(U$57-S)") (class "Default")
      (node (ref "D55") (pin "C") (pinfunction "C_C") (pintype "passive"))
      (node (ref "D56") (pin "A") (pinfunction "A_A") (pintype "passive"))
      (node (ref "R303") (pin "2") (pinfunction "2_2") (pintype "passive"))
      (node (ref "R305") (pin "1") (pinfunction "1_1") (pintype "passive"))
      (node (ref "R310") (pin "1") (pinfunction "1_1") (pintype "passive"))
      (node (ref "R313") (pin "1") (pinfunction "1_1") (pintype "passive"))
      (node (ref "U$57") (pin "2") (pinfunction "S_2") (pintype "passive"))
    )
    (net (code "576") (name "Net-(U$58-D)") (class "Default")
      (node (ref "R310") (pin "2") (pinfunction "2_2") (pintype "passive"))
      (node (ref "R313") (pin "2") (pinfunction "2_2") (pintype "passive"))
      (node (ref "U$58") (pin "3") (pinfunction "D_3") (pintype "passive"))
    )
    (net (code "577") (name "Net-(U$58-G)") (class "Default")
      (node (ref "R312") (pin "1") (pinfunction "1_1") (pintype "passive"))
      (node (ref "U$58") (pin "1") (pinfunction "G_1") (pintype "passive"))
    )
    (net (code "578") (name "Net-(U$58-S)") (class "Default")
      (node (ref "D56") (pin "C") (pinfunction "C_C") (pintype "passive"))
      (node (ref "D57") (pin "A") (pinfunction "A_A") (pintype "passive"))
      (node (ref "D59") (pin "A") (pinfunction "A_A") (pintype "passive"))
      (node (ref "R309") (pin "2") (pinfunction "2_2") (pintype "passive"))
      (node (ref "R311") (pin "1") (pinfunction "1_1") (pintype "passive"))
      (node (ref "R316") (pin "1") (pinfunction "1_1") (pintype "passive"))
      (node (ref "R319") (pin "1") (pinfunction "1_1") (pintype "passive"))
      (node (ref "U$58") (pin "2") (pinfunction "S_2") (pintype "passive"))
    )
    (net (code "579") (name "Net-(U$59-D)") (class "Default")
      (node (ref "R316") (pin "2") (pinfunction "2_2") (pintype "passive"))
      (node (ref "R319") (pin "2") (pinfunction "2_2") (pintype "passive"))
      (node (ref "U$59") (pin "3") (pinfunction "D_3") (pintype "passive"))
    )
    (net (code "580") (name "Net-(U$59-G)") (class "Default")
      (node (ref "R318") (pin "1") (pinfunction "1_1") (pintype "passive"))
      (node (ref "U$59") (pin "1") (pinfunction "G_1") (pintype "passive"))
    )
    (net (code "581") (name "Net-(U$59-S)") (class "Default")
      (node (ref "D57") (pin "C") (pinfunction "C_C") (pintype "passive"))
      (node (ref "R315") (pin "2") (pinfunction "2_2") (pintype "passive"))
      (node (ref "R317") (pin "1") (pinfunction "1_1") (pintype "passive"))
      (node (ref "U$59") (pin "2") (pinfunction "S_2") (pintype "passive"))
    )
    (net (code "582") (name "Net-(U$61-A2)") (class "Default")
      (node (ref "C85") (pin "2") (pinfunction "2_2") (pintype "passive"))
      (node (ref "R413") (pin "1") (pinfunction "1_1") (pintype "passive"))
      (node (ref "R414") (pin "1") (pinfunction "1_1") (pintype "passive"))
      (node (ref "U$61") (pin "32") (pinfunction "VREG_32") (pintype "bidirectional"))
      (node (ref "U$61") (pin "39") (pinfunction "A2_39") (pintype "bidirectional"))
      (node (ref "U$62") (pin "10") (pinfunction "EN2_10") (pintype "bidirectional"))
      (node (ref "U$62") (pin "16") (pinfunction "VDD2_16") (pintype "bidirectional"))
    )
    (net (code "583") (name "Net-(U$61-CO)") (class "Default")
      (node (ref "C83") (pin "2") (pinfunction "2_2") (pintype "passive"))
      (node (ref "R412") (pin "2") (pinfunction "2_2") (pintype "passive"))
      (node (ref "U$61") (pin "26") (pinfunction "CO_26") (pintype "bidirectional"))
    )
    (net (code "584") (name "Net-(U$61-CSBI)") (class "Default")
      (node (ref "U$61") (pin "44") (pinfunction "CSBI_44") (pintype "bidirectional"))
      (node (ref "U$62") (pin "12") (pinfunction "B3_12") (pintype "bidirectional"))
    )
    (net (code "585") (name "Net-(U$61-SCKI)") (class "Default")
      (node (ref "U$61") (pin "41") (pinfunction "SCKI_41") (pintype "bidirectional"))
      (node (ref "U$62") (pin "14") (pinfunction "B1_14") (pintype "bidirectional"))
    )
    (net (code "586") (name "Net-(U$61-SDI)") (class "Default")
      (node (ref "U$61") (pin "42") (pinfunction "SDI_42") (pintype "bidirectional"))
      (node (ref "U$62") (pin "13") (pinfunction "B2_13") (pintype "bidirectional"))
    )
    (net (code "587") (name "Net-(U$61-SDO)") (class "Default")
      (node (ref "R414") (pin "2") (pinfunction "2_2") (pintype "passive"))
      (node (ref "U$61") (pin "43") (pinfunction "SDO_43") (pintype "bidirectional"))
      (node (ref "U$62") (pin "11") (pinfunction "B4_11") (pintype "bidirectional"))
    )
    (net (code "588") (name "Net-(U$61-VREFF)") (class "Default")
      (node (ref "C84") (pin "2") (pinfunction "2_2") (pintype "passive"))
      (node (ref "U$61") (pin "31") (pinfunction "VREFF_31") (pintype "bidirectional"))
    )
    (net (code "589") (name "Net-(U$61-WDTB)") (class "Default")
      (node (ref "R413") (pin "2") (pinfunction "2_2") (pintype "passive"))
      (node (ref "U$61") (pin "34") (pinfunction "WDTB_34") (pintype "bidirectional"))
    )
    (net (code "590") (name "Net-(U$62-A4)") (class "Default")
      (node (ref "D75") (pin "C") (pinfunction "C_C") (pintype "passive"))
      (node (ref "U$62") (pin "6") (pinfunction "A4_6") (pintype "bidirectional"))
    )
    (net (code "591") (name "Net-(U$63-D)") (class "Default")
      (node (ref "R333") (pin "2") (pinfunction "2_2") (pintype "passive"))
      (node (ref "R336") (pin "2") (pinfunction "2_2") (pintype "passive"))
      (node (ref "U$63") (pin "3") (pinfunction "D_3") (pintype "passive"))
    )
    (net (code "592") (name "Net-(U$63-G)") (class "Default")
      (node (ref "R335") (pin "1") (pinfunction "1_1") (pintype "passive"))
      (node (ref "U$63") (pin "1") (pinfunction "G_1") (pintype "passive"))
    )
    (net (code "593") (name "Net-(U$63-S)") (class "Default")
      (node (ref "D61") (pin "C") (pinfunction "C_C") (pintype "passive"))
      (node (ref "D63") (pin "A") (pinfunction "A_A") (pintype "passive"))
      (node (ref "R334") (pin "1") (pinfunction "1_1") (pintype "passive"))
      (node (ref "R345") (pin "1") (pinfunction "1_1") (pintype "passive"))
      (node (ref "R348") (pin "1") (pinfunction "1_1") (pintype "passive"))
      (node (ref "R415") (pin "2") (pinfunction "2_2") (pintype "passive"))
      (node (ref "U$63") (pin "2") (pinfunction "S_2") (pintype "passive"))
    )
    (net (code "594") (name "Net-(U$64-D)") (class "Default")
      (node (ref "R339") (pin "2") (pinfunction "2_2") (pintype "passive"))
      (node (ref "R342") (pin "2") (pinfunction "2_2") (pintype "passive"))
      (node (ref "U$64") (pin "3") (pinfunction "D_3") (pintype "passive"))
    )
    (net (code "595") (name "Net-(U$64-G)") (class "Default")
      (node (ref "R341") (pin "1") (pinfunction "1_1") (pintype "passive"))
      (node (ref "U$64") (pin "1") (pinfunction "G_1") (pintype "passive"))
    )
    (net (code "596") (name "Net-(U$64-S)") (class "Default")
      (node (ref "D61") (pin "A") (pinfunction "A_A") (pintype "passive"))
      (node (ref "D62") (pin "C") (pinfunction "C_C") (pintype "passive"))
      (node (ref "D73") (pin "C") (pinfunction "C_C") (pintype "passive"))
      (node (ref "R333") (pin "1") (pinfunction "1_1") (pintype "passive"))
      (node (ref "R336") (pin "1") (pinfunction "1_1") (pintype "passive"))
      (node (ref "R338") (pin "2") (pinfunction "2_2") (pintype "passive"))
      (node (ref "R340") (pin "1") (pinfunction "1_1") (pintype "passive"))
      (node (ref "U$64") (pin "2") (pinfunction "S_2") (pintype "passive"))
    )
    (net (code "597") (name "Net-(U$65-D)") (class "Default")
      (node (ref "R345") (pin "2") (pinfunction "2_2") (pintype "passive"))
      (node (ref "R348") (pin "2") (pinfunction "2_2") (pintype "passive"))
      (node (ref "U$65") (pin "3") (pinfunction "D_3") (pintype "passive"))
    )
    (net (code "598") (name "Net-(U$65-G)") (class "Default")
      (node (ref "R347") (pin "1") (pinfunction "1_1") (pintype "passive"))
      (node (ref "U$65") (pin "1") (pinfunction "G_1") (pintype "passive"))
    )
    (net (code "599") (name "Net-(U$65-S)") (class "Default")
      (node (ref "D63") (pin "C") (pinfunction "C_C") (pintype "passive"))
      (node (ref "D64") (pin "A") (pinfunction "A_A") (pintype "passive"))
      (node (ref "R344") (pin "2") (pinfunction "2_2") (pintype "passive"))
      (node (ref "R346") (pin "1") (pinfunction "1_1") (pintype "passive"))
      (node (ref "R351") (pin "1") (pinfunction "1_1") (pintype "passive"))
      (node (ref "R354") (pin "1") (pinfunction "1_1") (pintype "passive"))
      (node (ref "U$65") (pin "2") (pinfunction "S_2") (pintype "passive"))
    )
    (net (code "600") (name "Net-(U$66-D)") (class "Default")
      (node (ref "R351") (pin "2") (pinfunction "2_2") (pintype "passive"))
      (node (ref "R354") (pin "2") (pinfunction "2_2") (pintype "passive"))
      (node (ref "U$66") (pin "3") (pinfunction "D_3") (pintype "passive"))
    )
    (net (code "601") (name "Net-(U$66-G)") (class "Default")
      (node (ref "R353") (pin "1") (pinfunction "1_1") (pintype "passive"))
      (node (ref "U$66") (pin "1") (pinfunction "G_1") (pintype "passive"))
    )
    (net (code "602") (name "Net-(U$66-S)") (class "Default")
      (node (ref "D64") (pin "C") (pinfunction "C_C") (pintype "passive"))
      (node (ref "D65") (pin "A") (pinfunction "A_A") (pintype "passive"))
      (node (ref "R350") (pin "2") (pinfunction "2_2") (pintype "passive"))
      (node (ref "R352") (pin "1") (pinfunction "1_1") (pintype "passive"))
      (node (ref "R357") (pin "1") (pinfunction "1_1") (pintype "passive"))
      (node (ref "R360") (pin "1") (pinfunction "1_1") (pintype "passive"))
      (node (ref "U$66") (pin "2") (pinfunction "S_2") (pintype "passive"))
    )
    (net (code "603") (name "Net-(U$67-D)") (class "Default")
      (node (ref "R357") (pin "2") (pinfunction "2_2") (pintype "passive"))
      (node (ref "R360") (pin "2") (pinfunction "2_2") (pintype "passive"))
      (node (ref "U$67") (pin "3") (pinfunction "D_3") (pintype "passive"))
    )
    (net (code "604") (name "Net-(U$67-G)") (class "Default")
      (node (ref "R359") (pin "1") (pinfunction "1_1") (pintype "passive"))
      (node (ref "U$67") (pin "1") (pinfunction "G_1") (pintype "passive"))
    )
    (net (code "605") (name "Net-(U$67-S)") (class "Default")
      (node (ref "D65") (pin "C") (pinfunction "C_C") (pintype "passive"))
      (node (ref "D66") (pin "A") (pinfunction "A_A") (pintype "passive"))
      (node (ref "R356") (pin "2") (pinfunction "2_2") (pintype "passive"))
      (node (ref "R358") (pin "1") (pinfunction "1_1") (pintype "passive"))
      (node (ref "R363") (pin "1") (pinfunction "1_1") (pintype "passive"))
      (node (ref "R366") (pin "1") (pinfunction "1_1") (pintype "passive"))
      (node (ref "U$67") (pin "2") (pinfunction "S_2") (pintype "passive"))
    )
    (net (code "606") (name "Net-(U$68-D)") (class "Default")
      (node (ref "R363") (pin "2") (pinfunction "2_2") (pintype "passive"))
      (node (ref "R366") (pin "2") (pinfunction "2_2") (pintype "passive"))
      (node (ref "U$68") (pin "3") (pinfunction "D_3") (pintype "passive"))
    )
    (net (code "607") (name "Net-(U$68-G)") (class "Default")
      (node (ref "R365") (pin "1") (pinfunction "1_1") (pintype "passive"))
      (node (ref "U$68") (pin "1") (pinfunction "G_1") (pintype "passive"))
    )
    (net (code "608") (name "Net-(U$68-S)") (class "Default")
      (node (ref "D66") (pin "C") (pinfunction "C_C") (pintype "passive"))
      (node (ref "D68") (pin "A") (pinfunction "A_A") (pintype "passive"))
      (node (ref "R362") (pin "2") (pinfunction "2_2") (pintype "passive"))
      (node (ref "R364") (pin "1") (pinfunction "1_1") (pintype "passive"))
      (node (ref "R375") (pin "1") (pinfunction "1_1") (pintype "passive"))
      (node (ref "R378") (pin "1") (pinfunction "1_1") (pintype "passive"))
      (node (ref "U$68") (pin "2") (pinfunction "S_2") (pintype "passive"))
    )
    (net (code "609") (name "Net-(U$69-D)") (class "Default")
      (node (ref "R369") (pin "2") (pinfunction "2_2") (pintype "passive"))
      (node (ref "R372") (pin "2") (pinfunction "2_2") (pintype "passive"))
      (node (ref "U$69") (pin "3") (pinfunction "D_3") (pintype "passive"))
    )
    (net (code "610") (name "Net-(U$69-G)") (class "Default")
      (node (ref "R371") (pin "1") (pinfunction "1_1") (pintype "passive"))
      (node (ref "U$69") (pin "1") (pinfunction "G_1") (pintype "passive"))
    )
    (net (code "611") (name "Net-(U$69-S)") (class "Default")
      (node (ref "D67") (pin "C") (pinfunction "C_C") (pintype "passive"))
      (node (ref "D69") (pin "A") (pinfunction "A_A") (pintype "passive"))
      (node (ref "R368") (pin "2") (pinfunction "2_2") (pintype "passive"))
      (node (ref "R370") (pin "1") (pinfunction "1_1") (pintype "passive"))
      (node (ref "R381") (pin "1") (pinfunction "1_1") (pintype "passive"))
      (node (ref "R384") (pin "1") (pinfunction "1_1") (pintype "passive"))
      (node (ref "U$69") (pin "2") (pinfunction "S_2") (pintype "passive"))
    )
    (net (code "612") (name "Net-(U$70-D)") (class "Default")
      (node (ref "R375") (pin "2") (pinfunction "2_2") (pintype "passive"))
      (node (ref "R378") (pin "2") (pinfunction "2_2") (pintype "passive"))
      (node (ref "U$70") (pin "3") (pinfunction "D_3") (pintype "passive"))
    )
    (net (code "613") (name "Net-(U$70-G)") (class "Default")
      (node (ref "R377") (pin "1") (pinfunction "1_1") (pintype "passive"))
      (node (ref "U$70") (pin "1") (pinfunction "G_1") (pintype "passive"))
    )
    (net (code "614") (name "Net-(U$70-S)") (class "Default")
      (node (ref "D67") (pin "A") (pinfunction "A_A") (pintype "passive"))
      (node (ref "D68") (pin "C") (pinfunction "C_C") (pintype "passive"))
      (node (ref "R369") (pin "1") (pinfunction "1_1") (pintype "passive"))
      (node (ref "R372") (pin "1") (pinfunction "1_1") (pintype "passive"))
      (node (ref "R374") (pin "2") (pinfunction "2_2") (pintype "passive"))
      (node (ref "R376") (pin "1") (pinfunction "1_1") (pintype "passive"))
      (node (ref "U$70") (pin "2") (pinfunction "S_2") (pintype "passive"))
    )
    (net (code "615") (name "Net-(U$71-D)") (class "Default")
      (node (ref "R381") (pin "2") (pinfunction "2_2") (pintype "passive"))
      (node (ref "R384") (pin "2") (pinfunction "2_2") (pintype "passive"))
      (node (ref "U$71") (pin "3") (pinfunction "D_3") (pintype "passive"))
    )
    (net (code "616") (name "Net-(U$71-G)") (class "Default")
      (node (ref "R383") (pin "1") (pinfunction "1_1") (pintype "passive"))
      (node (ref "U$71") (pin "1") (pinfunction "G_1") (pintype "passive"))
    )
    (net (code "617") (name "Net-(U$71-S)") (class "Default")
      (node (ref "D69") (pin "C") (pinfunction "C_C") (pintype "passive"))
      (node (ref "D70") (pin "A") (pinfunction "A_A") (pintype "passive"))
      (node (ref "R380") (pin "2") (pinfunction "2_2") (pintype "passive"))
      (node (ref "R382") (pin "1") (pinfunction "1_1") (pintype "passive"))
      (node (ref "R387") (pin "1") (pinfunction "1_1") (pintype "passive"))
      (node (ref "R390") (pin "1") (pinfunction "1_1") (pintype "passive"))
      (node (ref "U$71") (pin "2") (pinfunction "S_2") (pintype "passive"))
    )
    (net (code "618") (name "Net-(U$72-D)") (class "Default")
      (node (ref "R387") (pin "2") (pinfunction "2_2") (pintype "passive"))
      (node (ref "R390") (pin "2") (pinfunction "2_2") (pintype "passive"))
      (node (ref "U$72") (pin "3") (pinfunction "D_3") (pintype "passive"))
    )
    (net (code "619") (name "Net-(U$72-G)") (class "Default")
      (node (ref "R389") (pin "1") (pinfunction "1_1") (pintype "passive"))
      (node (ref "U$72") (pin "1") (pinfunction "G_1") (pintype "passive"))
    )
    (net (code "620") (name "Net-(U$72-S)") (class "Default")
      (node (ref "D70") (pin "C") (pinfunction "C_C") (pintype "passive"))
      (node (ref "D71") (pin "A") (pinfunction "A_A") (pintype "passive"))
      (node (ref "R386") (pin "2") (pinfunction "2_2") (pintype "passive"))
      (node (ref "R388") (pin "1") (pinfunction "1_1") (pintype "passive"))
      (node (ref "R393") (pin "1") (pinfunction "1_1") (pintype "passive"))
      (node (ref "R396") (pin "1") (pinfunction "1_1") (pintype "passive"))
      (node (ref "U$72") (pin "2") (pinfunction "S_2") (pintype "passive"))
    )
    (net (code "621") (name "Net-(U$73-D)") (class "Default")
      (node (ref "R393") (pin "2") (pinfunction "2_2") (pintype "passive"))
      (node (ref "R396") (pin "2") (pinfunction "2_2") (pintype "passive"))
      (node (ref "U$73") (pin "3") (pinfunction "D_3") (pintype "passive"))
    )
    (net (code "622") (name "Net-(U$73-G)") (class "Default")
      (node (ref "R395") (pin "1") (pinfunction "1_1") (pintype "passive"))
      (node (ref "U$73") (pin "1") (pinfunction "G_1") (pintype "passive"))
    )
    (net (code "623") (name "Net-(U$73-S)") (class "Default")
      (node (ref "D71") (pin "C") (pinfunction "C_C") (pintype "passive"))
      (node (ref "D72") (pin "A") (pinfunction "A_A") (pintype "passive"))
      (node (ref "D74") (pin "A") (pinfunction "A_A") (pintype "passive"))
      (node (ref "R392") (pin "2") (pinfunction "2_2") (pintype "passive"))
      (node (ref "R394") (pin "1") (pinfunction "1_1") (pintype "passive"))
      (node (ref "R399") (pin "1") (pinfunction "1_1") (pintype "passive"))
      (node (ref "R402") (pin "1") (pinfunction "1_1") (pintype "passive"))
      (node (ref "U$73") (pin "2") (pinfunction "S_2") (pintype "passive"))
    )
    (net (code "624") (name "Net-(U$74-D)") (class "Default")
      (node (ref "R399") (pin "2") (pinfunction "2_2") (pintype "passive"))
      (node (ref "R402") (pin "2") (pinfunction "2_2") (pintype "passive"))
      (node (ref "U$74") (pin "3") (pinfunction "D_3") (pintype "passive"))
    )
    (net (code "625") (name "Net-(U$74-G)") (class "Default")
      (node (ref "R401") (pin "1") (pinfunction "1_1") (pintype "passive"))
      (node (ref "U$74") (pin "1") (pinfunction "G_1") (pintype "passive"))
    )
    (net (code "626") (name "Net-(U$74-S)") (class "Default")
      (node (ref "D72") (pin "C") (pinfunction "C_C") (pintype "passive"))
      (node (ref "R398") (pin "2") (pinfunction "2_2") (pintype "passive"))
      (node (ref "R400") (pin "1") (pinfunction "1_1") (pintype "passive"))
      (node (ref "U$74") (pin "2") (pinfunction "S_2") (pintype "passive"))
    )
    (net (code "627") (name "Net-(U$76-A0)") (class "Default")
      (node (ref "C102") (pin "2") (pinfunction "2_2") (pintype "passive"))
      (node (ref "R496") (pin "1") (pinfunction "1_1") (pintype "passive"))
      (node (ref "R497") (pin "1") (pinfunction "1_1") (pintype "passive"))
      (node (ref "U$76") (pin "32") (pinfunction "VREG_32") (pintype "bidirectional"))
      (node (ref "U$76") (pin "37") (pinfunction "A0_37") (pintype "bidirectional"))
      (node (ref "U$76") (pin "39") (pinfunction "A2_39") (pintype "bidirectional"))
      (node (ref "U$77") (pin "10") (pinfunction "EN2_10") (pintype "bidirectional"))
      (node (ref "U$77") (pin "16") (pinfunction "VDD2_16") (pintype "bidirectional"))
    )
    (net (code "628") (name "Net-(U$76-CO)") (class "Default")
      (node (ref "C100") (pin "2") (pinfunction "2_2") (pintype "passive"))
      (node (ref "R495") (pin "2") (pinfunction "2_2") (pintype "passive"))
      (node (ref "U$76") (pin "26") (pinfunction "CO_26") (pintype "bidirectional"))
    )
    (net (code "629") (name "Net-(U$76-CSBI)") (class "Default")
      (node (ref "U$76") (pin "44") (pinfunction "CSBI_44") (pintype "bidirectional"))
      (node (ref "U$77") (pin "12") (pinfunction "B3_12") (pintype "bidirectional"))
    )
    (net (code "630") (name "Net-(U$76-SCKI)") (class "Default")
      (node (ref "U$76") (pin "41") (pinfunction "SCKI_41") (pintype "bidirectional"))
      (node (ref "U$77") (pin "14") (pinfunction "B1_14") (pintype "bidirectional"))
    )
    (net (code "631") (name "Net-(U$76-SDI)") (class "Default")
      (node (ref "U$76") (pin "42") (pinfunction "SDI_42") (pintype "bidirectional"))
      (node (ref "U$77") (pin "13") (pinfunction "B2_13") (pintype "bidirectional"))
    )
    (net (code "632") (name "Net-(U$76-SDO)") (class "Default")
      (node (ref "R497") (pin "2") (pinfunction "2_2") (pintype "passive"))
      (node (ref "U$76") (pin "43") (pinfunction "SDO_43") (pintype "bidirectional"))
      (node (ref "U$77") (pin "11") (pinfunction "B4_11") (pintype "bidirectional"))
    )
    (net (code "633") (name "Net-(U$76-VREFF)") (class "Default")
      (node (ref "C101") (pin "2") (pinfunction "2_2") (pintype "passive"))
      (node (ref "U$76") (pin "31") (pinfunction "VREFF_31") (pintype "bidirectional"))
    )
    (net (code "634") (name "Net-(U$76-WDTB)") (class "Default")
      (node (ref "R496") (pin "2") (pinfunction "2_2") (pintype "passive"))
      (node (ref "U$76") (pin "34") (pinfunction "WDTB_34") (pintype "bidirectional"))
    )
    (net (code "635") (name "Net-(U$77-A4)") (class "Default")
      (node (ref "D90") (pin "C") (pinfunction "C_C") (pintype "passive"))
      (node (ref "U$77") (pin "6") (pinfunction "A4_6") (pintype "bidirectional"))
    )
    (net (code "636") (name "Net-(U$78-D)") (class "Default")
      (node (ref "R416") (pin "2") (pinfunction "2_2") (pintype "passive"))
      (node (ref "R419") (pin "2") (pinfunction "2_2") (pintype "passive"))
      (node (ref "U$78") (pin "3") (pinfunction "D_3") (pintype "passive"))
    )
    (net (code "637") (name "Net-(U$78-G)") (class "Default")
      (node (ref "R418") (pin "1") (pinfunction "1_1") (pintype "passive"))
      (node (ref "U$78") (pin "1") (pinfunction "G_1") (pintype "passive"))
    )
    (net (code "638") (name "Net-(U$78-S)") (class "Default")
      (node (ref "D76") (pin "C") (pinfunction "C_C") (pintype "passive"))
      (node (ref "D78") (pin "A") (pinfunction "A_A") (pintype "passive"))
      (node (ref "R417") (pin "1") (pinfunction "1_1") (pintype "passive"))
      (node (ref "R428") (pin "1") (pinfunction "1_1") (pintype "passive"))
      (node (ref "R431") (pin "1") (pinfunction "1_1") (pintype "passive"))
      (node (ref "R498") (pin "2") (pinfunction "2_2") (pintype "passive"))
      (node (ref "U$78") (pin "2") (pinfunction "S_2") (pintype "passive"))
    )
    (net (code "639") (name "Net-(U$79-D)") (class "Default")
      (node (ref "R422") (pin "2") (pinfunction "2_2") (pintype "passive"))
      (node (ref "R425") (pin "2") (pinfunction "2_2") (pintype "passive"))
      (node (ref "U$79") (pin "3") (pinfunction "D_3") (pintype "passive"))
    )
    (net (code "640") (name "Net-(U$79-G)") (class "Default")
      (node (ref "R424") (pin "1") (pinfunction "1_1") (pintype "passive"))
      (node (ref "U$79") (pin "1") (pinfunction "G_1") (pintype "passive"))
    )
    (net (code "641") (name "Net-(U$79-S)") (class "Default")
      (node (ref "D76") (pin "A") (pinfunction "A_A") (pintype "passive"))
      (node (ref "D77") (pin "C") (pinfunction "C_C") (pintype "passive"))
      (node (ref "D88") (pin "C") (pinfunction "C_C") (pintype "passive"))
      (node (ref "R416") (pin "1") (pinfunction "1_1") (pintype "passive"))
      (node (ref "R419") (pin "1") (pinfunction "1_1") (pintype "passive"))
      (node (ref "R421") (pin "2") (pinfunction "2_2") (pintype "passive"))
      (node (ref "R423") (pin "1") (pinfunction "1_1") (pintype "passive"))
      (node (ref "U$79") (pin "2") (pinfunction "S_2") (pintype "passive"))
    )
    (net (code "642") (name "Net-(U$80-D)") (class "Default")
      (node (ref "R428") (pin "2") (pinfunction "2_2") (pintype "passive"))
      (node (ref "R431") (pin "2") (pinfunction "2_2") (pintype "passive"))
      (node (ref "U$80") (pin "3") (pinfunction "D_3") (pintype "passive"))
    )
    (net (code "643") (name "Net-(U$80-G)") (class "Default")
      (node (ref "R430") (pin "1") (pinfunction "1_1") (pintype "passive"))
      (node (ref "U$80") (pin "1") (pinfunction "G_1") (pintype "passive"))
    )
    (net (code "644") (name "Net-(U$80-S)") (class "Default")
      (node (ref "D78") (pin "C") (pinfunction "C_C") (pintype "passive"))
      (node (ref "D79") (pin "A") (pinfunction "A_A") (pintype "passive"))
      (node (ref "R427") (pin "2") (pinfunction "2_2") (pintype "passive"))
      (node (ref "R429") (pin "1") (pinfunction "1_1") (pintype "passive"))
      (node (ref "R434") (pin "1") (pinfunction "1_1") (pintype "passive"))
      (node (ref "R437") (pin "1") (pinfunction "1_1") (pintype "passive"))
      (node (ref "U$80") (pin "2") (pinfunction "S_2") (pintype "passive"))
    )
    (net (code "645") (name "Net-(U$81-D)") (class "Default")
      (node (ref "R434") (pin "2") (pinfunction "2_2") (pintype "passive"))
      (node (ref "R437") (pin "2") (pinfunction "2_2") (pintype "passive"))
      (node (ref "U$81") (pin "3") (pinfunction "D_3") (pintype "passive"))
    )
    (net (code "646") (name "Net-(U$81-G)") (class "Default")
      (node (ref "R436") (pin "1") (pinfunction "1_1") (pintype "passive"))
      (node (ref "U$81") (pin "1") (pinfunction "G_1") (pintype "passive"))
    )
    (net (code "647") (name "Net-(U$81-S)") (class "Default")
      (node (ref "D79") (pin "C") (pinfunction "C_C") (pintype "passive"))
      (node (ref "D80") (pin "A") (pinfunction "A_A") (pintype "passive"))
      (node (ref "R433") (pin "2") (pinfunction "2_2") (pintype "passive"))
      (node (ref "R435") (pin "1") (pinfunction "1_1") (pintype "passive"))
      (node (ref "R440") (pin "1") (pinfunction "1_1") (pintype "passive"))
      (node (ref "R443") (pin "1") (pinfunction "1_1") (pintype "passive"))
      (node (ref "U$81") (pin "2") (pinfunction "S_2") (pintype "passive"))
    )
    (net (code "648") (name "Net-(U$82-D)") (class "Default")
      (node (ref "R440") (pin "2") (pinfunction "2_2") (pintype "passive"))
      (node (ref "R443") (pin "2") (pinfunction "2_2") (pintype "passive"))
      (node (ref "U$82") (pin "3") (pinfunction "D_3") (pintype "passive"))
    )
    (net (code "649") (name "Net-(U$82-G)") (class "Default")
      (node (ref "R442") (pin "1") (pinfunction "1_1") (pintype "passive"))
      (node (ref "U$82") (pin "1") (pinfunction "G_1") (pintype "passive"))
    )
    (net (code "650") (name "Net-(U$82-S)") (class "Default")
      (node (ref "D80") (pin "C") (pinfunction "C_C") (pintype "passive"))
      (node (ref "D81") (pin "A") (pinfunction "A_A") (pintype "passive"))
      (node (ref "R439") (pin "2") (pinfunction "2_2") (pintype "passive"))
      (node (ref "R441") (pin "1") (pinfunction "1_1") (pintype "passive"))
      (node (ref "R446") (pin "1") (pinfunction "1_1") (pintype "passive"))
      (node (ref "R449") (pin "1") (pinfunction "1_1") (pintype "passive"))
      (node (ref "U$82") (pin "2") (pinfunction "S_2") (pintype "passive"))
    )
    (net (code "651") (name "Net-(U$83-D)") (class "Default")
      (node (ref "R446") (pin "2") (pinfunction "2_2") (pintype "passive"))
      (node (ref "R449") (pin "2") (pinfunction "2_2") (pintype "passive"))
      (node (ref "U$83") (pin "3") (pinfunction "D_3") (pintype "passive"))
    )
    (net (code "652") (name "Net-(U$83-G)") (class "Default")
      (node (ref "R448") (pin "1") (pinfunction "1_1") (pintype "passive"))
      (node (ref "U$83") (pin "1") (pinfunction "G_1") (pintype "passive"))
    )
    (net (code "653") (name "Net-(U$83-S)") (class "Default")
      (node (ref "D81") (pin "C") (pinfunction "C_C") (pintype "passive"))
      (node (ref "D83") (pin "A") (pinfunction "A_A") (pintype "passive"))
      (node (ref "R445") (pin "2") (pinfunction "2_2") (pintype "passive"))
      (node (ref "R447") (pin "1") (pinfunction "1_1") (pintype "passive"))
      (node (ref "R458") (pin "1") (pinfunction "1_1") (pintype "passive"))
      (node (ref "R461") (pin "1") (pinfunction "1_1") (pintype "passive"))
      (node (ref "U$83") (pin "2") (pinfunction "S_2") (pintype "passive"))
    )
    (net (code "654") (name "Net-(U$84-D)") (class "Default")
      (node (ref "R452") (pin "2") (pinfunction "2_2") (pintype "passive"))
      (node (ref "R455") (pin "2") (pinfunction "2_2") (pintype "passive"))
      (node (ref "U$84") (pin "3") (pinfunction "D_3") (pintype "passive"))
    )
    (net (code "655") (name "Net-(U$84-G)") (class "Default")
      (node (ref "R454") (pin "1") (pinfunction "1_1") (pintype "passive"))
      (node (ref "U$84") (pin "1") (pinfunction "G_1") (pintype "passive"))
    )
    (net (code "656") (name "Net-(U$84-S)") (class "Default")
      (node (ref "D82") (pin "C") (pinfunction "C_C") (pintype "passive"))
      (node (ref "D84") (pin "A") (pinfunction "A_A") (pintype "passive"))
      (node (ref "R451") (pin "2") (pinfunction "2_2") (pintype "passive"))
      (node (ref "R453") (pin "1") (pinfunction "1_1") (pintype "passive"))
      (node (ref "R464") (pin "1") (pinfunction "1_1") (pintype "passive"))
      (node (ref "R467") (pin "1") (pinfunction "1_1") (pintype "passive"))
      (node (ref "U$84") (pin "2") (pinfunction "S_2") (pintype "passive"))
    )
    (net (code "657") (name "Net-(U$85-D)") (class "Default")
      (node (ref "R458") (pin "2") (pinfunction "2_2") (pintype "passive"))
      (node (ref "R461") (pin "2") (pinfunction "2_2") (pintype "passive"))
      (node (ref "U$85") (pin "3") (pinfunction "D_3") (pintype "passive"))
    )
    (net (code "658") (name "Net-(U$85-G)") (class "Default")
      (node (ref "R460") (pin "1") (pinfunction "1_1") (pintype "passive"))
      (node (ref "U$85") (pin "1") (pinfunction "G_1") (pintype "passive"))
    )
    (net (code "659") (name "Net-(U$85-S)") (class "Default")
      (node (ref "D82") (pin "A") (pinfunction "A_A") (pintype "passive"))
      (node (ref "D83") (pin "C") (pinfunction "C_C") (pintype "passive"))
      (node (ref "R452") (pin "1") (pinfunction "1_1") (pintype "passive"))
      (node (ref "R455") (pin "1") (pinfunction "1_1") (pintype "passive"))
      (node (ref "R457") (pin "2") (pinfunction "2_2") (pintype "passive"))
      (node (ref "R459") (pin "1") (pinfunction "1_1") (pintype "passive"))
      (node (ref "U$85") (pin "2") (pinfunction "S_2") (pintype "passive"))
    )
    (net (code "660") (name "Net-(U$86-D)") (class "Default")
      (node (ref "R464") (pin "2") (pinfunction "2_2") (pintype "passive"))
      (node (ref "R467") (pin "2") (pinfunction "2_2") (pintype "passive"))
      (node (ref "U$86") (pin "3") (pinfunction "D_3") (pintype "passive"))
    )
    (net (code "661") (name "Net-(U$86-G)") (class "Default")
      (node (ref "R466") (pin "1") (pinfunction "1_1") (pintype "passive"))
      (node (ref "U$86") (pin "1") (pinfunction "G_1") (pintype "passive"))
    )
    (net (code "662") (name "Net-(U$86-S)") (class "Default")
      (node (ref "D84") (pin "C") (pinfunction "C_C") (pintype "passive"))
      (node (ref "D85") (pin "A") (pinfunction "A_A") (pintype "passive"))
      (node (ref "R463") (pin "2") (pinfunction "2_2") (pintype "passive"))
      (node (ref "R465") (pin "1") (pinfunction "1_1") (pintype "passive"))
      (node (ref "R470") (pin "1") (pinfunction "1_1") (pintype "passive"))
      (node (ref "R473") (pin "1") (pinfunction "1_1") (pintype "passive"))
      (node (ref "U$86") (pin "2") (pinfunction "S_2") (pintype "passive"))
    )
    (net (code "663") (name "Net-(U$87-D)") (class "Default")
      (node (ref "R470") (pin "2") (pinfunction "2_2") (pintype "passive"))
      (node (ref "R473") (pin "2") (pinfunction "2_2") (pintype "passive"))
      (node (ref "U$87") (pin "3") (pinfunction "D_3") (pintype "passive"))
    )
    (net (code "664") (name "Net-(U$87-G)") (class "Default")
      (node (ref "R472") (pin "1") (pinfunction "1_1") (pintype "passive"))
      (node (ref "U$87") (pin "1") (pinfunction "G_1") (pintype "passive"))
    )
    (net (code "665") (name "Net-(U$87-S)") (class "Default")
      (node (ref "D85") (pin "C") (pinfunction "C_C") (pintype "passive"))
      (node (ref "D86") (pin "A") (pinfunction "A_A") (pintype "passive"))
      (node (ref "R469") (pin "2") (pinfunction "2_2") (pintype "passive"))
      (node (ref "R471") (pin "1") (pinfunction "1_1") (pintype "passive"))
      (node (ref "R476") (pin "1") (pinfunction "1_1") (pintype "passive"))
      (node (ref "R479") (pin "1") (pinfunction "1_1") (pintype "passive"))
      (node (ref "U$87") (pin "2") (pinfunction "S_2") (pintype "passive"))
    )
    (net (code "666") (name "Net-(U$88-D)") (class "Default")
      (node (ref "R476") (pin "2") (pinfunction "2_2") (pintype "passive"))
      (node (ref "R479") (pin "2") (pinfunction "2_2") (pintype "passive"))
      (node (ref "U$88") (pin "3") (pinfunction "D_3") (pintype "passive"))
    )
    (net (code "667") (name "Net-(U$88-G)") (class "Default")
      (node (ref "R478") (pin "1") (pinfunction "1_1") (pintype "passive"))
      (node (ref "U$88") (pin "1") (pinfunction "G_1") (pintype "passive"))
    )
    (net (code "668") (name "Net-(U$88-S)") (class "Default")
      (node (ref "D86") (pin "C") (pinfunction "C_C") (pintype "passive"))
      (node (ref "D87") (pin "A") (pinfunction "A_A") (pintype "passive"))
      (node (ref "D89") (pin "A") (pinfunction "A_A") (pintype "passive"))
      (node (ref "R475") (pin "2") (pinfunction "2_2") (pintype "passive"))
      (node (ref "R477") (pin "1") (pinfunction "1_1") (pintype "passive"))
      (node (ref "R482") (pin "1") (pinfunction "1_1") (pintype "passive"))
      (node (ref "R485") (pin "1") (pinfunction "1_1") (pintype "passive"))
      (node (ref "U$88") (pin "2") (pinfunction "S_2") (pintype "passive"))
    )
    (net (code "669") (name "Net-(U$89-D)") (class "Default")
      (node (ref "R482") (pin "2") (pinfunction "2_2") (pintype "passive"))
      (node (ref "R485") (pin "2") (pinfunction "2_2") (pintype "passive"))
      (node (ref "U$89") (pin "3") (pinfunction "D_3") (pintype "passive"))
    )
    (net (code "670") (name "Net-(U$89-G)") (class "Default")
      (node (ref "R484") (pin "1") (pinfunction "1_1") (pintype "passive"))
      (node (ref "U$89") (pin "1") (pinfunction "G_1") (pintype "passive"))
    )
    (net (code "671") (name "Net-(U$89-S)") (class "Default")
      (node (ref "D87") (pin "C") (pinfunction "C_C") (pintype "passive"))
      (node (ref "R481") (pin "2") (pinfunction "2_2") (pintype "passive"))
      (node (ref "R483") (pin "1") (pinfunction "1_1") (pintype "passive"))
      (node (ref "U$89") (pin "2") (pinfunction "S_2") (pintype "passive"))
    )
    (net (code "672") (name "Net-(U$91-A1)") (class "Default")
      (node (ref "C119") (pin "2") (pinfunction "2_2") (pintype "passive"))
      (node (ref "R579") (pin "1") (pinfunction "1_1") (pintype "passive"))
      (node (ref "R580") (pin "1") (pinfunction "1_1") (pintype "passive"))
      (node (ref "U$91") (pin "32") (pinfunction "VREG_32") (pintype "bidirectional"))
      (node (ref "U$91") (pin "38") (pinfunction "A1_38") (pintype "bidirectional"))
      (node (ref "U$91") (pin "39") (pinfunction "A2_39") (pintype "bidirectional"))
      (node (ref "U$92") (pin "10") (pinfunction "EN2_10") (pintype "bidirectional"))
      (node (ref "U$92") (pin "16") (pinfunction "VDD2_16") (pintype "bidirectional"))
    )
    (net (code "673") (name "Net-(U$91-CO)") (class "Default")
      (node (ref "C117") (pin "2") (pinfunction "2_2") (pintype "passive"))
      (node (ref "R578") (pin "2") (pinfunction "2_2") (pintype "passive"))
      (node (ref "U$91") (pin "26") (pinfunction "CO_26") (pintype "bidirectional"))
    )
    (net (code "674") (name "Net-(U$91-CSBI)") (class "Default")
      (node (ref "U$91") (pin "44") (pinfunction "CSBI_44") (pintype "bidirectional"))
      (node (ref "U$92") (pin "12") (pinfunction "B3_12") (pintype "bidirectional"))
    )
    (net (code "675") (name "Net-(U$91-SCKI)") (class "Default")
      (node (ref "U$91") (pin "41") (pinfunction "SCKI_41") (pintype "bidirectional"))
      (node (ref "U$92") (pin "14") (pinfunction "B1_14") (pintype "bidirectional"))
    )
    (net (code "676") (name "Net-(U$91-SDI)") (class "Default")
      (node (ref "U$91") (pin "42") (pinfunction "SDI_42") (pintype "bidirectional"))
      (node (ref "U$92") (pin "13") (pinfunction "B2_13") (pintype "bidirectional"))
    )
    (net (code "677") (name "Net-(U$91-SDO)") (class "Default")
      (node (ref "R580") (pin "2") (pinfunction "2_2") (pintype "passive"))
      (node (ref "U$91") (pin "43") (pinfunction "SDO_43") (pintype "bidirectional"))
      (node (ref "U$92") (pin "11") (pinfunction "B4_11") (pintype "bidirectional"))
    )
    (net (code "678") (name "Net-(U$91-VREFF)") (class "Default")
      (node (ref "C118") (pin "2") (pinfunction "2_2") (pintype "passive"))
      (node (ref "U$91") (pin "31") (pinfunction "VREFF_31") (pintype "bidirectional"))
    )
    (net (code "679") (name "Net-(U$91-WDTB)") (class "Default")
      (node (ref "R579") (pin "2") (pinfunction "2_2") (pintype "passive"))
      (node (ref "U$91") (pin "34") (pinfunction "WDTB_34") (pintype "bidirectional"))
    )
    (net (code "680") (name "Net-(U$92-A4)") (class "Default")
      (node (ref "D105") (pin "C") (pinfunction "C_C") (pintype "passive"))
      (node (ref "U$92") (pin "6") (pinfunction "A4_6") (pintype "bidirectional"))
    )
    (net (code "681") (name "Net-(U$93-D)") (class "Default")
      (node (ref "R499") (pin "2") (pinfunction "2_2") (pintype "passive"))
      (node (ref "R502") (pin "2") (pinfunction "2_2") (pintype "passive"))
      (node (ref "U$93") (pin "3") (pinfunction "D_3") (pintype "passive"))
    )
    (net (code "682") (name "Net-(U$93-G)") (class "Default")
      (node (ref "R501") (pin "1") (pinfunction "1_1") (pintype "passive"))
      (node (ref "U$93") (pin "1") (pinfunction "G_1") (pintype "passive"))
    )
    (net (code "683") (name "Net-(U$93-S)") (class "Default")
      (node (ref "D91") (pin "C") (pinfunction "C_C") (pintype "passive"))
      (node (ref "D93") (pin "A") (pinfunction "A_A") (pintype "passive"))
      (node (ref "R500") (pin "1") (pinfunction "1_1") (pintype "passive"))
      (node (ref "R511") (pin "1") (pinfunction "1_1") (pintype "passive"))
      (node (ref "R514") (pin "1") (pinfunction "1_1") (pintype "passive"))
      (node (ref "R581") (pin "2") (pinfunction "2_2") (pintype "passive"))
      (node (ref "U$93") (pin "2") (pinfunction "S_2") (pintype "passive"))
    )
    (net (code "684") (name "Net-(U$94-D)") (class "Default")
      (node (ref "R505") (pin "2") (pinfunction "2_2") (pintype "passive"))
      (node (ref "R508") (pin "2") (pinfunction "2_2") (pintype "passive"))
      (node (ref "U$94") (pin "3") (pinfunction "D_3") (pintype "passive"))
    )
    (net (code "685") (name "Net-(U$94-G)") (class "Default")
      (node (ref "R507") (pin "1") (pinfunction "1_1") (pintype "passive"))
      (node (ref "U$94") (pin "1") (pinfunction "G_1") (pintype "passive"))
    )
    (net (code "686") (name "Net-(U$94-S)") (class "Default")
      (node (ref "D103") (pin "C") (pinfunction "C_C") (pintype "passive"))
      (node (ref "D91") (pin "A") (pinfunction "A_A") (pintype "passive"))
      (node (ref "D92") (pin "C") (pinfunction "C_C") (pintype "passive"))
      (node (ref "R499") (pin "1") (pinfunction "1_1") (pintype "passive"))
      (node (ref "R502") (pin "1") (pinfunction "1_1") (pintype "passive"))
      (node (ref "R504") (pin "2") (pinfunction "2_2") (pintype "passive"))
      (node (ref "R506") (pin "1") (pinfunction "1_1") (pintype "passive"))
      (node (ref "U$94") (pin "2") (pinfunction "S_2") (pintype "passive"))
    )
    (net (code "687") (name "Net-(U$95-D)") (class "Default")
      (node (ref "R511") (pin "2") (pinfunction "2_2") (pintype "passive"))
      (node (ref "R514") (pin "2") (pinfunction "2_2") (pintype "passive"))
      (node (ref "U$95") (pin "3") (pinfunction "D_3") (pintype "passive"))
    )
    (net (code "688") (name "Net-(U$95-G)") (class "Default")
      (node (ref "R513") (pin "1") (pinfunction "1_1") (pintype "passive"))
      (node (ref "U$95") (pin "1") (pinfunction "G_1") (pintype "passive"))
    )
    (net (code "689") (name "Net-(U$95-S)") (class "Default")
      (node (ref "D93") (pin "C") (pinfunction "C_C") (pintype "passive"))
      (node (ref "D94") (pin "A") (pinfunction "A_A") (pintype "passive"))
      (node (ref "R510") (pin "2") (pinfunction "2_2") (pintype "passive"))
      (node (ref "R512") (pin "1") (pinfunction "1_1") (pintype "passive"))
      (node (ref "R517") (pin "1") (pinfunction "1_1") (pintype "passive"))
      (node (ref "R520") (pin "1") (pinfunction "1_1") (pintype "passive"))
      (node (ref "U$95") (pin "2") (pinfunction "S_2") (pintype "passive"))
    )
    (net (code "690") (name "Net-(U$96-D)") (class "Default")
      (node (ref "R517") (pin "2") (pinfunction "2_2") (pintype "passive"))
      (node (ref "R520") (pin "2") (pinfunction "2_2") (pintype "passive"))
      (node (ref "U$96") (pin "3") (pinfunction "D_3") (pintype "passive"))
    )
    (net (code "691") (name "Net-(U$96-G)") (class "Default")
      (node (ref "R519") (pin "1") (pinfunction "1_1") (pintype "passive"))
      (node (ref "U$96") (pin "1") (pinfunction "G_1") (pintype "passive"))
    )
    (net (code "692") (name "Net-(U$96-S)") (class "Default")
      (node (ref "D94") (pin "C") (pinfunction "C_C") (pintype "passive"))
      (node (ref "D95") (pin "A") (pinfunction "A_A") (pintype "passive"))
      (node (ref "R516") (pin "2") (pinfunction "2_2") (pintype "passive"))
      (node (ref "R518") (pin "1") (pinfunction "1_1") (pintype "passive"))
      (node (ref "R523") (pin "1") (pinfunction "1_1") (pintype "passive"))
      (node (ref "R526") (pin "1") (pinfunction "1_1") (pintype "passive"))
      (node (ref "U$96") (pin "2") (pinfunction "S_2") (pintype "passive"))
    )
    (net (code "693") (name "Net-(U$97-D)") (class "Default")
      (node (ref "R523") (pin "2") (pinfunction "2_2") (pintype "passive"))
      (node (ref "R526") (pin "2") (pinfunction "2_2") (pintype "passive"))
      (node (ref "U$97") (pin "3") (pinfunction "D_3") (pintype "passive"))
    )
    (net (code "694") (name "Net-(U$97-G)") (class "Default")
      (node (ref "R525") (pin "1") (pinfunction "1_1") (pintype "passive"))
      (node (ref "U$97") (pin "1") (pinfunction "G_1") (pintype "passive"))
    )
    (net (code "695") (name "Net-(U$97-S)") (class "Default")
      (node (ref "D95") (pin "C") (pinfunction "C_C") (pintype "passive"))
      (node (ref "D96") (pin "A") (pinfunction "A_A") (pintype "passive"))
      (node (ref "R522") (pin "2") (pinfunction "2_2") (pintype "passive"))
      (node (ref "R524") (pin "1") (pinfunction "1_1") (pintype "passive"))
      (node (ref "R529") (pin "1") (pinfunction "1_1") (pintype "passive"))
      (node (ref "R532") (pin "1") (pinfunction "1_1") (pintype "passive"))
      (node (ref "U$97") (pin "2") (pinfunction "S_2") (pintype "passive"))
    )
    (net (code "696") (name "Net-(U$98-D)") (class "Default")
      (node (ref "R529") (pin "2") (pinfunction "2_2") (pintype "passive"))
      (node (ref "R532") (pin "2") (pinfunction "2_2") (pintype "passive"))
      (node (ref "U$98") (pin "3") (pinfunction "D_3") (pintype "passive"))
    )
    (net (code "697") (name "Net-(U$98-G)") (class "Default")
      (node (ref "R531") (pin "1") (pinfunction "1_1") (pintype "passive"))
      (node (ref "U$98") (pin "1") (pinfunction "G_1") (pintype "passive"))
    )
    (net (code "698") (name "Net-(U$98-S)") (class "Default")
      (node (ref "D96") (pin "C") (pinfunction "C_C") (pintype "passive"))
      (node (ref "D98") (pin "A") (pinfunction "A_A") (pintype "passive"))
      (node (ref "R528") (pin "2") (pinfunction "2_2") (pintype "passive"))
      (node (ref "R530") (pin "1") (pinfunction "1_1") (pintype "passive"))
      (node (ref "R541") (pin "1") (pinfunction "1_1") (pintype "passive"))
      (node (ref "R544") (pin "1") (pinfunction "1_1") (pintype "passive"))
      (node (ref "U$98") (pin "2") (pinfunction "S_2") (pintype "passive"))
    )
    (net (code "699") (name "Net-(U$99-D)") (class "Default")
      (node (ref "R535") (pin "2") (pinfunction "2_2") (pintype "passive"))
      (node (ref "R538") (pin "2") (pinfunction "2_2") (pintype "passive"))
      (node (ref "U$99") (pin "3") (pinfunction "D_3") (pintype "passive"))
    )
    (net (code "700") (name "Net-(U$99-G)") (class "Default")
      (node (ref "R537") (pin "1") (pinfunction "1_1") (pintype "passive"))
      (node (ref "U$99") (pin "1") (pinfunction "G_1") (pintype "passive"))
    )
    (net (code "701") (name "Net-(U$99-S)") (class "Default")
      (node (ref "D97") (pin "C") (pinfunction "C_C") (pintype "passive"))
      (node (ref "D99") (pin "A") (pinfunction "A_A") (pintype "passive"))
      (node (ref "R534") (pin "2") (pinfunction "2_2") (pintype "passive"))
      (node (ref "R536") (pin "1") (pinfunction "1_1") (pintype "passive"))
      (node (ref "R547") (pin "1") (pinfunction "1_1") (pintype "passive"))
      (node (ref "R550") (pin "1") (pinfunction "1_1") (pintype "passive"))
      (node (ref "U$99") (pin "2") (pinfunction "S_2") (pintype "passive"))
    )
    (net (code "702") (name "Net-(U$100-D)") (class "Default")
      (node (ref "R541") (pin "2") (pinfunction "2_2") (pintype "passive"))
      (node (ref "R544") (pin "2") (pinfunction "2_2") (pintype "passive"))
      (node (ref "U$100") (pin "3") (pinfunction "D_3") (pintype "passive"))
    )
    (net (code "703") (name "Net-(U$100-G)") (class "Default")
      (node (ref "R543") (pin "1") (pinfunction "1_1") (pintype "passive"))
      (node (ref "U$100") (pin "1") (pinfunction "G_1") (pintype "passive"))
    )
    (net (code "704") (name "Net-(U$100-S)") (class "Default")
      (node (ref "D97") (pin "A") (pinfunction "A_A") (pintype "passive"))
      (node (ref "D98") (pin "C") (pinfunction "C_C") (pintype "passive"))
      (node (ref "R535") (pin "1") (pinfunction "1_1") (pintype "passive"))
      (node (ref "R538") (pin "1") (pinfunction "1_1") (pintype "passive"))
      (node (ref "R540") (pin "2") (pinfunction "2_2") (pintype "passive"))
      (node (ref "R542") (pin "1") (pinfunction "1_1") (pintype "passive"))
      (node (ref "U$100") (pin "2") (pinfunction "S_2") (pintype "passive"))
    )
    (net (code "705") (name "Net-(U$101-D)") (class "Default")
      (node (ref "R547") (pin "2") (pinfunction "2_2") (pintype "passive"))
      (node (ref "R550") (pin "2") (pinfunction "2_2") (pintype "passive"))
      (node (ref "U$101") (pin "3") (pinfunction "D_3") (pintype "passive"))
    )
    (net (code "706") (name "Net-(U$101-G)") (class "Default")
      (node (ref "R549") (pin "1") (pinfunction "1_1") (pintype "passive"))
      (node (ref "U$101") (pin "1") (pinfunction "G_1") (pintype "passive"))
    )
    (net (code "707") (name "Net-(U$101-S)") (class "Default")
      (node (ref "D100") (pin "A") (pinfunction "A_A") (pintype "passive"))
      (node (ref "D99") (pin "C") (pinfunction "C_C") (pintype "passive"))
      (node (ref "R546") (pin "2") (pinfunction "2_2") (pintype "passive"))
      (node (ref "R548") (pin "1") (pinfunction "1_1") (pintype "passive"))
      (node (ref "R553") (pin "1") (pinfunction "1_1") (pintype "passive"))
      (node (ref "R556") (pin "1") (pinfunction "1_1") (pintype "passive"))
      (node (ref "U$101") (pin "2") (pinfunction "S_2") (pintype "passive"))
    )
    (net (code "708") (name "Net-(U$102-D)") (class "Default")
      (node (ref "R553") (pin "2") (pinfunction "2_2") (pintype "passive"))
      (node (ref "R556") (pin "2") (pinfunction "2_2") (pintype "passive"))
      (node (ref "U$102") (pin "3") (pinfunction "D_3") (pintype "passive"))
    )
    (net (code "709") (name "Net-(U$102-G)") (class "Default")
      (node (ref "R555") (pin "1") (pinfunction "1_1") (pintype "passive"))
      (node (ref "U$102") (pin "1") (pinfunction "G_1") (pintype "passive"))
    )
    (net (code "710") (name "Net-(U$102-S)") (class "Default")
      (node (ref "D100") (pin "C") (pinfunction "C_C") (pintype "passive"))
      (node (ref "D101") (pin "A") (pinfunction "A_A") (pintype "passive"))
      (node (ref "R552") (pin "2") (pinfunction "2_2") (pintype "passive"))
      (node (ref "R554") (pin "1") (pinfunction "1_1") (pintype "passive"))
      (node (ref "R559") (pin "1") (pinfunction "1_1") (pintype "passive"))
      (node (ref "R562") (pin "1") (pinfunction "1_1") (pintype "passive"))
      (node (ref "U$102") (pin "2") (pinfunction "S_2") (pintype "passive"))
    )
    (net (code "711") (name "Net-(U$103-D)") (class "Default")
      (node (ref "R559") (pin "2") (pinfunction "2_2") (pintype "passive"))
      (node (ref "R562") (pin "2") (pinfunction "2_2") (pintype "passive"))
      (node (ref "U$103") (pin "3") (pinfunction "D_3") (pintype "passive"))
    )
    (net (code "712") (name "Net-(U$103-G)") (class "Default")
      (node (ref "R561") (pin "1") (pinfunction "1_1") (pintype "passive"))
      (node (ref "U$103") (pin "1") (pinfunction "G_1") (pintype "passive"))
    )
    (net (code "713") (name "Net-(U$103-S)") (class "Default")
      (node (ref "D101") (pin "C") (pinfunction "C_C") (pintype "passive"))
      (node (ref "D102") (pin "A") (pinfunction "A_A") (pintype "passive"))
      (node (ref "D104") (pin "A") (pinfunction "A_A") (pintype "passive"))
      (node (ref "R558") (pin "2") (pinfunction "2_2") (pintype "passive"))
      (node (ref "R560") (pin "1") (pinfunction "1_1") (pintype "passive"))
      (node (ref "R565") (pin "1") (pinfunction "1_1") (pintype "passive"))
      (node (ref "R568") (pin "1") (pinfunction "1_1") (pintype "passive"))
      (node (ref "U$103") (pin "2") (pinfunction "S_2") (pintype "passive"))
    )
    (net (code "714") (name "Net-(U$104-D)") (class "Default")
      (node (ref "R565") (pin "2") (pinfunction "2_2") (pintype "passive"))
      (node (ref "R568") (pin "2") (pinfunction "2_2") (pintype "passive"))
      (node (ref "U$104") (pin "3") (pinfunction "D_3") (pintype "passive"))
    )
    (net (code "715") (name "Net-(U$104-G)") (class "Default")
      (node (ref "R567") (pin "1") (pinfunction "1_1") (pintype "passive"))
      (node (ref "U$104") (pin "1") (pinfunction "G_1") (pintype "passive"))
    )
    (net (code "716") (name "Net-(U$104-S)") (class "Default")
      (node (ref "D102") (pin "C") (pinfunction "C_C") (pintype "passive"))
      (node (ref "R564") (pin "2") (pinfunction "2_2") (pintype "passive"))
      (node (ref "R566") (pin "1") (pinfunction "1_1") (pintype "passive"))
      (node (ref "U$104") (pin "2") (pinfunction "S_2") (pintype "passive"))
    )
    (net (code "717") (name "Net-(U$106-A0)") (class "Default")
      (node (ref "C136") (pin "2") (pinfunction "2_2") (pintype "passive"))
      (node (ref "R662") (pin "1") (pinfunction "1_1") (pintype "passive"))
      (node (ref "R663") (pin "1") (pinfunction "1_1") (pintype "passive"))
      (node (ref "U$106") (pin "32") (pinfunction "VREG_32") (pintype "bidirectional"))
      (node (ref "U$106") (pin "37") (pinfunction "A0_37") (pintype "bidirectional"))
      (node (ref "U$106") (pin "38") (pinfunction "A1_38") (pintype "bidirectional"))
      (node (ref "U$106") (pin "39") (pinfunction "A2_39") (pintype "bidirectional"))
      (node (ref "U$107") (pin "10") (pinfunction "EN2_10") (pintype "bidirectional"))
      (node (ref "U$107") (pin "16") (pinfunction "VDD2_16") (pintype "bidirectional"))
    )
    (net (code "718") (name "Net-(U$106-CO)") (class "Default")
      (node (ref "C134") (pin "2") (pinfunction "2_2") (pintype "passive"))
      (node (ref "R661") (pin "2") (pinfunction "2_2") (pintype "passive"))
      (node (ref "U$106") (pin "26") (pinfunction "CO_26") (pintype "bidirectional"))
    )
    (net (code "719") (name "Net-(U$106-CSBI)") (class "Default")
      (node (ref "U$106") (pin "44") (pinfunction "CSBI_44") (pintype "bidirectional"))
      (node (ref "U$107") (pin "12") (pinfunction "B3_12") (pintype "bidirectional"))
    )
    (net (code "720") (name "Net-(U$106-SCKI)") (class "Default")
      (node (ref "U$106") (pin "41") (pinfunction "SCKI_41") (pintype "bidirectional"))
      (node (ref "U$107") (pin "14") (pinfunction "B1_14") (pintype "bidirectional"))
    )
    (net (code "721") (name "Net-(U$106-SDI)") (class "Default")
      (node (ref "U$106") (pin "42") (pinfunction "SDI_42") (pintype "bidirectional"))
      (node (ref "U$107") (pin "13") (pinfunction "B2_13") (pintype "bidirectional"))
    )
    (net (code "722") (name "Net-(U$106-SDO)") (class "Default")
      (node (ref "R663") (pin "2") (pinfunction "2_2") (pintype "passive"))
      (node (ref "U$106") (pin "43") (pinfunction "SDO_43") (pintype "bidirectional"))
      (node (ref "U$107") (pin "11") (pinfunction "B4_11") (pintype "bidirectional"))
    )
    (net (code "723") (name "Net-(U$106-VREFF)") (class "Default")
      (node (ref "C135") (pin "2") (pinfunction "2_2") (pintype "passive"))
      (node (ref "U$106") (pin "31") (pinfunction "VREFF_31") (pintype "bidirectional"))
    )
    (net (code "724") (name "Net-(U$106-WDTB)") (class "Default")
      (node (ref "R662") (pin "2") (pinfunction "2_2") (pintype "passive"))
      (node (ref "U$106") (pin "34") (pinfunction "WDTB_34") (pintype "bidirectional"))
    )
    (net (code "725") (name "Net-(U$107-A4)") (class "Default")
      (node (ref "D120") (pin "C") (pinfunction "C_C") (pintype "passive"))
      (node (ref "U$107") (pin "6") (pinfunction "A4_6") (pintype "bidirectional"))
    )
    (net (code "726") (name "Net-(U$108-D)") (class "Default")
      (node (ref "R582") (pin "2") (pinfunction "2_2") (pintype "passive"))
      (node (ref "R585") (pin "2") (pinfunction "2_2") (pintype "passive"))
      (node (ref "U$108") (pin "3") (pinfunction "D_3") (pintype "passive"))
    )
    (net (code "727") (name "Net-(U$108-G)") (class "Default")
      (node (ref "R584") (pin "1") (pinfunction "1_1") (pintype "passive"))
      (node (ref "U$108") (pin "1") (pinfunction "G_1") (pintype "passive"))
    )
    (net (code "728") (name "Net-(U$108-S)") (class "Default")
      (node (ref "D106") (pin "C") (pinfunction "C_C") (pintype "passive"))
      (node (ref "D108") (pin "A") (pinfunction "A_A") (pintype "passive"))
      (node (ref "R583") (pin "1") (pinfunction "1_1") (pintype "passive"))
      (node (ref "R594") (pin "1") (pinfunction "1_1") (pintype "passive"))
      (node (ref "R597") (pin "1") (pinfunction "1_1") (pintype "passive"))
      (node (ref "R664") (pin "2") (pinfunction "2_2") (pintype "passive"))
      (node (ref "U$108") (pin "2") (pinfunction "S_2") (pintype "passive"))
    )
    (net (code "729") (name "Net-(U$109-D)") (class "Default")
      (node (ref "R588") (pin "2") (pinfunction "2_2") (pintype "passive"))
      (node (ref "R591") (pin "2") (pinfunction "2_2") (pintype "passive"))
      (node (ref "U$109") (pin "3") (pinfunction "D_3") (pintype "passive"))
    )
    (net (code "730") (name "Net-(U$109-G)") (class "Default")
      (node (ref "R590") (pin "1") (pinfunction "1_1") (pintype "passive"))
      (node (ref "U$109") (pin "1") (pinfunction "G_1") (pintype "passive"))
    )
    (net (code "731") (name "Net-(U$109-S)") (class "Default")
      (node (ref "D106") (pin "A") (pinfunction "A_A") (pintype "passive"))
      (node (ref "D107") (pin "C") (pinfunction "C_C") (pintype "passive"))
      (node (ref "D118") (pin "C") (pinfunction "C_C") (pintype "passive"))
      (node (ref "R582") (pin "1") (pinfunction "1_1") (pintype "passive"))
      (node (ref "R585") (pin "1") (pinfunction "1_1") (pintype "passive"))
      (node (ref "R587") (pin "2") (pinfunction "2_2") (pintype "passive"))
      (node (ref "R589") (pin "1") (pinfunction "1_1") (pintype "passive"))
      (node (ref "U$109") (pin "2") (pinfunction "S_2") (pintype "passive"))
    )
    (net (code "732") (name "Net-(U$110-D)") (class "Default")
      (node (ref "R594") (pin "2") (pinfunction "2_2") (pintype "passive"))
      (node (ref "R597") (pin "2") (pinfunction "2_2") (pintype "passive"))
      (node (ref "U$110") (pin "3") (pinfunction "D_3") (pintype "passive"))
    )
    (net (code "733") (name "Net-(U$110-G)") (class "Default")
      (node (ref "R596") (pin "1") (pinfunction "1_1") (pintype "passive"))
      (node (ref "U$110") (pin "1") (pinfunction "G_1") (pintype "passive"))
    )
    (net (code "734") (name "Net-(U$110-S)") (class "Default")
      (node (ref "D108") (pin "C") (pinfunction "C_C") (pintype "passive"))
      (node (ref "D109") (pin "A") (pinfunction "A_A") (pintype "passive"))
      (node (ref "R593") (pin "2") (pinfunction "2_2") (pintype "passive"))
      (node (ref "R595") (pin "1") (pinfunction "1_1") (pintype "passive"))
      (node (ref "R600") (pin "1") (pinfunction "1_1") (pintype "passive"))
      (node (ref "R603") (pin "1") (pinfunction "1_1") (pintype "passive"))
      (node (ref "U$110") (pin "2") (pinfunction "S_2") (pintype "passive"))
    )
    (net (code "735") (name "Net-(U$111-D)") (class "Default")
      (node (ref "R600") (pin "2") (pinfunction "2_2") (pintype "passive"))
      (node (ref "R603") (pin "2") (pinfunction "2_2") (pintype "passive"))
      (node (ref "U$111") (pin "3") (pinfunction "D_3") (pintype "passive"))
    )
    (net (code "736") (name "Net-(U$111-G)") (class "Default")
      (node (ref "R602") (pin "1") (pinfunction "1_1") (pintype "passive"))
      (node (ref "U$111") (pin "1") (pinfunction "G_1") (pintype "passive"))
    )
    (net (code "737") (name "Net-(U$111-S)") (class "Default")
      (node (ref "D109") (pin "C") (pinfunction "C_C") (pintype "passive"))
      (node (ref "D110") (pin "A") (pinfunction "A_A") (pintype "passive"))
      (node (ref "R599") (pin "2") (pinfunction "2_2") (pintype "passive"))
      (node (ref "R601") (pin "1") (pinfunction "1_1") (pintype "passive"))
      (node (ref "R606") (pin "1") (pinfunction "1_1") (pintype "passive"))
      (node (ref "R609") (pin "1") (pinfunction "1_1") (pintype "passive"))
      (node (ref "U$111") (pin "2") (pinfunction "S_2") (pintype "passive"))
    )
    (net (code "738") (name "Net-(U$112-D)") (class "Default")
      (node (ref "R606") (pin "2") (pinfunction "2_2") (pintype "passive"))
      (node (ref "R609") (pin "2") (pinfunction "2_2") (pintype "passive"))
      (node (ref "U$112") (pin "3") (pinfunction "D_3") (pintype "passive"))
    )
    (net (code "739") (name "Net-(U$112-G)") (class "Default")
      (node (ref "R608") (pin "1") (pinfunction "1_1") (pintype "passive"))
      (node (ref "U$112") (pin "1") (pinfunction "G_1") (pintype "passive"))
    )
    (net (code "740") (name "Net-(U$112-S)") (class "Default")
      (node (ref "D110") (pin "C") (pinfunction "C_C") (pintype "passive"))
      (node (ref "D111") (pin "A") (pinfunction "A_A") (pintype "passive"))
      (node (ref "R605") (pin "2") (pinfunction "2_2") (pintype "passive"))
      (node (ref "R607") (pin "1") (pinfunction "1_1") (pintype "passive"))
      (node (ref "R612") (pin "1") (pinfunction "1_1") (pintype "passive"))
      (node (ref "R615") (pin "1") (pinfunction "1_1") (pintype "passive"))
      (node (ref "U$112") (pin "2") (pinfunction "S_2") (pintype "passive"))
    )
    (net (code "741") (name "Net-(U$113-D)") (class "Default")
      (node (ref "R612") (pin "2") (pinfunction "2_2") (pintype "passive"))
      (node (ref "R615") (pin "2") (pinfunction "2_2") (pintype "passive"))
      (node (ref "U$113") (pin "3") (pinfunction "D_3") (pintype "passive"))
    )
    (net (code "742") (name "Net-(U$113-G)") (class "Default")
      (node (ref "R614") (pin "1") (pinfunction "1_1") (pintype "passive"))
      (node (ref "U$113") (pin "1") (pinfunction "G_1") (pintype "passive"))
    )
    (net (code "743") (name "Net-(U$113-S)") (class "Default")
      (node (ref "D111") (pin "C") (pinfunction "C_C") (pintype "passive"))
      (node (ref "D113") (pin "A") (pinfunction "A_A") (pintype "passive"))
      (node (ref "R611") (pin "2") (pinfunction "2_2") (pintype "passive"))
      (node (ref "R613") (pin "1") (pinfunction "1_1") (pintype "passive"))
      (node (ref "R624") (pin "1") (pinfunction "1_1") (pintype "passive"))
      (node (ref "R627") (pin "1") (pinfunction "1_1") (pintype "passive"))
      (node (ref "U$113") (pin "2") (pinfunction "S_2") (pintype "passive"))
    )
    (net (code "744") (name "Net-(U$114-D)") (class "Default")
      (node (ref "R618") (pin "2") (pinfunction "2_2") (pintype "passive"))
      (node (ref "R621") (pin "2") (pinfunction "2_2") (pintype "passive"))
      (node (ref "U$114") (pin "3") (pinfunction "D_3") (pintype "passive"))
    )
    (net (code "745") (name "Net-(U$114-G)") (class "Default")
      (node (ref "R620") (pin "1") (pinfunction "1_1") (pintype "passive"))
      (node (ref "U$114") (pin "1") (pinfunction "G_1") (pintype "passive"))
    )
    (net (code "746") (name "Net-(U$114-S)") (class "Default")
      (node (ref "D112") (pin "C") (pinfunction "C_C") (pintype "passive"))
      (node (ref "D114") (pin "A") (pinfunction "A_A") (pintype "passive"))
      (node (ref "R617") (pin "2") (pinfunction "2_2") (pintype "passive"))
      (node (ref "R619") (pin "1") (pinfunction "1_1") (pintype "passive"))
      (node (ref "R630") (pin "1") (pinfunction "1_1") (pintype "passive"))
      (node (ref "R633") (pin "1") (pinfunction "1_1") (pintype "passive"))
      (node (ref "U$114") (pin "2") (pinfunction "S_2") (pintype "passive"))
    )
    (net (code "747") (name "Net-(U$115-D)") (class "Default")
      (node (ref "R624") (pin "2") (pinfunction "2_2") (pintype "passive"))
      (node (ref "R627") (pin "2") (pinfunction "2_2") (pintype "passive"))
      (node (ref "U$115") (pin "3") (pinfunction "D_3") (pintype "passive"))
    )
    (net (code "748") (name "Net-(U$115-G)") (class "Default")
      (node (ref "R626") (pin "1") (pinfunction "1_1") (pintype "passive"))
      (node (ref "U$115") (pin "1") (pinfunction "G_1") (pintype "passive"))
    )
    (net (code "749") (name "Net-(U$115-S)") (class "Default")
      (node (ref "D112") (pin "A") (pinfunction "A_A") (pintype "passive"))
      (node (ref "D113") (pin "C") (pinfunction "C_C") (pintype "passive"))
      (node (ref "R618") (pin "1") (pinfunction "1_1") (pintype "passive"))
      (node (ref "R621") (pin "1") (pinfunction "1_1") (pintype "passive"))
      (node (ref "R623") (pin "2") (pinfunction "2_2") (pintype "passive"))
      (node (ref "R625") (pin "1") (pinfunction "1_1") (pintype "passive"))
      (node (ref "U$115") (pin "2") (pinfunction "S_2") (pintype "passive"))
    )
    (net (code "750") (name "Net-(U$116-D)") (class "Default")
      (node (ref "R630") (pin "2") (pinfunction "2_2") (pintype "passive"))
      (node (ref "R633") (pin "2") (pinfunction "2_2") (pintype "passive"))
      (node (ref "U$116") (pin "3") (pinfunction "D_3") (pintype "passive"))
    )
    (net (code "751") (name "Net-(U$116-G)") (class "Default")
      (node (ref "R632") (pin "1") (pinfunction "1_1") (pintype "passive"))
      (node (ref "U$116") (pin "1") (pinfunction "G_1") (pintype "passive"))
    )
    (net (code "752") (name "Net-(U$116-S)") (class "Default")
      (node (ref "D114") (pin "C") (pinfunction "C_C") (pintype "passive"))
      (node (ref "D115") (pin "A") (pinfunction "A_A") (pintype "passive"))
      (node (ref "R629") (pin "2") (pinfunction "2_2") (pintype "passive"))
      (node (ref "R631") (pin "1") (pinfunction "1_1") (pintype "passive"))
      (node (ref "R636") (pin "1") (pinfunction "1_1") (pintype "passive"))
      (node (ref "R639") (pin "1") (pinfunction "1_1") (pintype "passive"))
      (node (ref "U$116") (pin "2") (pinfunction "S_2") (pintype "passive"))
    )
    (net (code "753") (name "Net-(U$117-D)") (class "Default")
      (node (ref "R636") (pin "2") (pinfunction "2_2") (pintype "passive"))
      (node (ref "R639") (pin "2") (pinfunction "2_2") (pintype "passive"))
      (node (ref "U$117") (pin "3") (pinfunction "D_3") (pintype "passive"))
    )
    (net (code "754") (name "Net-(U$117-G)") (class "Default")
      (node (ref "R638") (pin "1") (pinfunction "1_1") (pintype "passive"))
      (node (ref "U$117") (pin "1") (pinfunction "G_1") (pintype "passive"))
    )
    (net (code "755") (name "Net-(U$117-S)") (class "Default")
      (node (ref "D115") (pin "C") (pinfunction "C_C") (pintype "passive"))
      (node (ref "D116") (pin "A") (pinfunction "A_A") (pintype "passive"))
      (node (ref "R635") (pin "2") (pinfunction "2_2") (pintype "passive"))
      (node (ref "R637") (pin "1") (pinfunction "1_1") (pintype "passive"))
      (node (ref "R642") (pin "1") (pinfunction "1_1") (pintype "passive"))
      (node (ref "R645") (pin "1") (pinfunction "1_1") (pintype "passive"))
      (node (ref "U$117") (pin "2") (pinfunction "S_2") (pintype "passive"))
    )
    (net (code "756") (name "Net-(U$118-D)") (class "Default")
      (node (ref "R642") (pin "2") (pinfunction "2_2") (pintype "passive"))
      (node (ref "R645") (pin "2") (pinfunction "2_2") (pintype "passive"))
      (node (ref "U$118") (pin "3") (pinfunction "D_3") (pintype "passive"))
    )
    (net (code "757") (name "Net-(U$118-G)") (class "Default")
      (node (ref "R644") (pin "1") (pinfunction "1_1") (pintype "passive"))
      (node (ref "U$118") (pin "1") (pinfunction "G_1") (pintype "passive"))
    )
    (net (code "758") (name "Net-(U$118-S)") (class "Default")
      (node (ref "D116") (pin "C") (pinfunction "C_C") (pintype "passive"))
      (node (ref "D117") (pin "A") (pinfunction "A_A") (pintype "passive"))
      (node (ref "D119") (pin "A") (pinfunction "A_A") (pintype "passive"))
      (node (ref "R641") (pin "2") (pinfunction "2_2") (pintype "passive"))
      (node (ref "R643") (pin "1") (pinfunction "1_1") (pintype "passive"))
      (node (ref "R648") (pin "1") (pinfunction "1_1") (pintype "passive"))
      (node (ref "R651") (pin "1") (pinfunction "1_1") (pintype "passive"))
      (node (ref "U$118") (pin "2") (pinfunction "S_2") (pintype "passive"))
    )
    (net (code "759") (name "Net-(U$119-D)") (class "Default")
      (node (ref "R648") (pin "2") (pinfunction "2_2") (pintype "passive"))
      (node (ref "R651") (pin "2") (pinfunction "2_2") (pintype "passive"))
      (node (ref "U$119") (pin "3") (pinfunction "D_3") (pintype "passive"))
    )
    (net (code "760") (name "Net-(U$119-G)") (class "Default")
      (node (ref "R650") (pin "1") (pinfunction "1_1") (pintype "passive"))
      (node (ref "U$119") (pin "1") (pinfunction "G_1") (pintype "passive"))
    )
    (net (code "761") (name "Net-(U$119-S)") (class "Default")
      (node (ref "D117") (pin "C") (pinfunction "C_C") (pintype "passive"))
      (node (ref "R647") (pin "2") (pinfunction "2_2") (pintype "passive"))
      (node (ref "R649") (pin "1") (pinfunction "1_1") (pintype "passive"))
      (node (ref "U$119") (pin "2") (pinfunction "S_2") (pintype "passive"))
    )
    (net (code "762") (name "Net-(U$121-A3)") (class "Default")
      (node (ref "C153") (pin "2") (pinfunction "2_2") (pintype "passive"))
      (node (ref "R745") (pin "1") (pinfunction "1_1") (pintype "passive"))
      (node (ref "R746") (pin "1") (pinfunction "1_1") (pintype "passive"))
      (node (ref "U$121") (pin "32") (pinfunction "VREG_32") (pintype "bidirectional"))
      (node (ref "U$121") (pin "40") (pinfunction "A3_40") (pintype "bidirectional"))
      (node (ref "U$122") (pin "10") (pinfunction "EN2_10") (pintype "bidirectional"))
      (node (ref "U$122") (pin "16") (pinfunction "VDD2_16") (pintype "bidirectional"))
    )
    (net (code "763") (name "Net-(U$121-CO)") (class "Default")
      (node (ref "C151") (pin "2") (pinfunction "2_2") (pintype "passive"))
      (node (ref "R744") (pin "2") (pinfunction "2_2") (pintype "passive"))
      (node (ref "U$121") (pin "26") (pinfunction "CO_26") (pintype "bidirectional"))
    )
    (net (code "764") (name "Net-(U$121-CSBI)") (class "Default")
      (node (ref "U$121") (pin "44") (pinfunction "CSBI_44") (pintype "bidirectional"))
      (node (ref "U$122") (pin "12") (pinfunction "B3_12") (pintype "bidirectional"))
    )
    (net (code "765") (name "Net-(U$121-SCKI)") (class "Default")
      (node (ref "U$121") (pin "41") (pinfunction "SCKI_41") (pintype "bidirectional"))
      (node (ref "U$122") (pin "14") (pinfunction "B1_14") (pintype "bidirectional"))
    )
    (net (code "766") (name "Net-(U$121-SDI)") (class "Default")
      (node (ref "U$121") (pin "42") (pinfunction "SDI_42") (pintype "bidirectional"))
      (node (ref "U$122") (pin "13") (pinfunction "B2_13") (pintype "bidirectional"))
    )
    (net (code "767") (name "Net-(U$121-SDO)") (class "Default")
      (node (ref "R746") (pin "2") (pinfunction "2_2") (pintype "passive"))
      (node (ref "U$121") (pin "43") (pinfunction "SDO_43") (pintype "bidirectional"))
      (node (ref "U$122") (pin "11") (pinfunction "B4_11") (pintype "bidirectional"))
    )
    (net (code "768") (name "Net-(U$121-VREFF)") (class "Default")
      (node (ref "C152") (pin "2") (pinfunction "2_2") (pintype "passive"))
      (node (ref "U$121") (pin "31") (pinfunction "VREFF_31") (pintype "bidirectional"))
    )
    (net (code "769") (name "Net-(U$121-WDTB)") (class "Default")
      (node (ref "R745") (pin "2") (pinfunction "2_2") (pintype "passive"))
      (node (ref "U$121") (pin "34") (pinfunction "WDTB_34") (pintype "bidirectional"))
    )
    (net (code "770") (name "Net-(U$122-A4)") (class "Default")
      (node (ref "D135") (pin "C") (pinfunction "C_C") (pintype "passive"))
      (node (ref "U$122") (pin "6") (pinfunction "A4_6") (pintype "bidirectional"))
    )
    (net (code "771") (name "Net-(U$123-D)") (class "Default")
      (node (ref "R665") (pin "2") (pinfunction "2_2") (pintype "passive"))
      (node (ref "R668") (pin "2") (pinfunction "2_2") (pintype "passive"))
      (node (ref "U$123") (pin "3") (pinfunction "D_3") (pintype "passive"))
    )
    (net (code "772") (name "Net-(U$123-G)") (class "Default")
      (node (ref "R667") (pin "1") (pinfunction "1_1") (pintype "passive"))
      (node (ref "U$123") (pin "1") (pinfunction "G_1") (pintype "passive"))
    )
    (net (code "773") (name "Net-(U$123-S)") (class "Default")
      (node (ref "D121") (pin "C") (pinfunction "C_C") (pintype "passive"))
      (node (ref "D123") (pin "A") (pinfunction "A_A") (pintype "passive"))
      (node (ref "R666") (pin "1") (pinfunction "1_1") (pintype "passive"))
      (node (ref "R677") (pin "1") (pinfunction "1_1") (pintype "passive"))
      (node (ref "R680") (pin "1") (pinfunction "1_1") (pintype "passive"))
      (node (ref "R747") (pin "2") (pinfunction "2_2") (pintype "passive"))
      (node (ref "U$123") (pin "2") (pinfunction "S_2") (pintype "passive"))
    )
    (net (code "774") (name "Net-(U$124-D)") (class "Default")
      (node (ref "R671") (pin "2") (pinfunction "2_2") (pintype "passive"))
      (node (ref "R674") (pin "2") (pinfunction "2_2") (pintype "passive"))
      (node (ref "U$124") (pin "3") (pinfunction "D_3") (pintype "passive"))
    )
    (net (code "775") (name "Net-(U$124-G)") (class "Default")
      (node (ref "R673") (pin "1") (pinfunction "1_1") (pintype "passive"))
      (node (ref "U$124") (pin "1") (pinfunction "G_1") (pintype "passive"))
    )
    (net (code "776") (name "Net-(U$124-S)") (class "Default")
      (node (ref "D121") (pin "A") (pinfunction "A_A") (pintype "passive"))
      (node (ref "D122") (pin "C") (pinfunction "C_C") (pintype "passive"))
      (node (ref "D133") (pin "C") (pinfunction "C_C") (pintype "passive"))
      (node (ref "R665") (pin "1") (pinfunction "1_1") (pintype "passive"))
      (node (ref "R668") (pin "1") (pinfunction "1_1") (pintype "passive"))
      (node (ref "R670") (pin "2") (pinfunction "2_2") (pintype "passive"))
      (node (ref "R672") (pin "1") (pinfunction "1_1") (pintype "passive"))
      (node (ref "U$124") (pin "2") (pinfunction "S_2") (pintype "passive"))
    )
    (net (code "777") (name "Net-(U$125-D)") (class "Default")
      (node (ref "R677") (pin "2") (pinfunction "2_2") (pintype "passive"))
      (node (ref "R680") (pin "2") (pinfunction "2_2") (pintype "passive"))
      (node (ref "U$125") (pin "3") (pinfunction "D_3") (pintype "passive"))
    )
    (net (code "778") (name "Net-(U$125-G)") (class "Default")
      (node (ref "R679") (pin "1") (pinfunction "1_1") (pintype "passive"))
      (node (ref "U$125") (pin "1") (pinfunction "G_1") (pintype "passive"))
    )
    (net (code "779") (name "Net-(U$125-S)") (class "Default")
      (node (ref "D123") (pin "C") (pinfunction "C_C") (pintype "passive"))
      (node (ref "D124") (pin "A") (pinfunction "A_A") (pintype "passive"))
      (node (ref "R676") (pin "2") (pinfunction "2_2") (pintype "passive"))
      (node (ref "R678") (pin "1") (pinfunction "1_1") (pintype "passive"))
      (node (ref "R683") (pin "1") (pinfunction "1_1") (pintype "passive"))
      (node (ref "R686") (pin "1") (pinfunction "1_1") (pintype "passive"))
      (node (ref "U$125") (pin "2") (pinfunction "S_2") (pintype "passive"))
    )
    (net (code "780") (name "Net-(U$126-D)") (class "Default")
      (node (ref "R683") (pin "2") (pinfunction "2_2") (pintype "passive"))
      (node (ref "R686") (pin "2") (pinfunction "2_2") (pintype "passive"))
      (node (ref "U$126") (pin "3") (pinfunction "D_3") (pintype "passive"))
    )
    (net (code "781") (name "Net-(U$126-G)") (class "Default")
      (node (ref "R685") (pin "1") (pinfunction "1_1") (pintype "passive"))
      (node (ref "U$126") (pin "1") (pinfunction "G_1") (pintype "passive"))
    )
    (net (code "782") (name "Net-(U$126-S)") (class "Default")
      (node (ref "D124") (pin "C") (pinfunction "C_C") (pintype "passive"))
      (node (ref "D125") (pin "A") (pinfunction "A_A") (pintype "passive"))
      (node (ref "R682") (pin "2") (pinfunction "2_2") (pintype "passive"))
      (node (ref "R684") (pin "1") (pinfunction "1_1") (pintype "passive"))
      (node (ref "R689") (pin "1") (pinfunction "1_1") (pintype "passive"))
      (node (ref "R692") (pin "1") (pinfunction "1_1") (pintype "passive"))
      (node (ref "U$126") (pin "2") (pinfunction "S_2") (pintype "passive"))
    )
    (net (code "783") (name "Net-(U$127-D)") (class "Default")
      (node (ref "R689") (pin "2") (pinfunction "2_2") (pintype "passive"))
      (node (ref "R692") (pin "2") (pinfunction "2_2") (pintype "passive"))
      (node (ref "U$127") (pin "3") (pinfunction "D_3") (pintype "passive"))
    )
    (net (code "784") (name "Net-(U$127-G)") (class "Default")
      (node (ref "R691") (pin "1") (pinfunction "1_1") (pintype "passive"))
      (node (ref "U$127") (pin "1") (pinfunction "G_1") (pintype "passive"))
    )
    (net (code "785") (name "Net-(U$127-S)") (class "Default")
      (node (ref "D125") (pin "C") (pinfunction "C_C") (pintype "passive"))
      (node (ref "D126") (pin "A") (pinfunction "A_A") (pintype "passive"))
      (node (ref "R688") (pin "2") (pinfunction "2_2") (pintype "passive"))
      (node (ref "R690") (pin "1") (pinfunction "1_1") (pintype "passive"))
      (node (ref "R695") (pin "1") (pinfunction "1_1") (pintype "passive"))
      (node (ref "R698") (pin "1") (pinfunction "1_1") (pintype "passive"))
      (node (ref "U$127") (pin "2") (pinfunction "S_2") (pintype "passive"))
    )
    (net (code "786") (name "Net-(U$128-D)") (class "Default")
      (node (ref "R695") (pin "2") (pinfunction "2_2") (pintype "passive"))
      (node (ref "R698") (pin "2") (pinfunction "2_2") (pintype "passive"))
      (node (ref "U$128") (pin "3") (pinfunction "D_3") (pintype "passive"))
    )
    (net (code "787") (name "Net-(U$128-G)") (class "Default")
      (node (ref "R697") (pin "1") (pinfunction "1_1") (pintype "passive"))
      (node (ref "U$128") (pin "1") (pinfunction "G_1") (pintype "passive"))
    )
    (net (code "788") (name "Net-(U$128-S)") (class "Default")
      (node (ref "D126") (pin "C") (pinfunction "C_C") (pintype "passive"))
      (node (ref "D128") (pin "A") (pinfunction "A_A") (pintype "passive"))
      (node (ref "R694") (pin "2") (pinfunction "2_2") (pintype "passive"))
      (node (ref "R696") (pin "1") (pinfunction "1_1") (pintype "passive"))
      (node (ref "R707") (pin "1") (pinfunction "1_1") (pintype "passive"))
      (node (ref "R710") (pin "1") (pinfunction "1_1") (pintype "passive"))
      (node (ref "U$128") (pin "2") (pinfunction "S_2") (pintype "passive"))
    )
    (net (code "789") (name "Net-(U$129-D)") (class "Default")
      (node (ref "R701") (pin "2") (pinfunction "2_2") (pintype "passive"))
      (node (ref "R704") (pin "2") (pinfunction "2_2") (pintype "passive"))
      (node (ref "U$129") (pin "3") (pinfunction "D_3") (pintype "passive"))
    )
    (net (code "790") (name "Net-(U$129-G)") (class "Default")
      (node (ref "R703") (pin "1") (pinfunction "1_1") (pintype "passive"))
      (node (ref "U$129") (pin "1") (pinfunction "G_1") (pintype "passive"))
    )
    (net (code "791") (name "Net-(U$129-S)") (class "Default")
      (node (ref "D127") (pin "C") (pinfunction "C_C") (pintype "passive"))
      (node (ref "D129") (pin "A") (pinfunction "A_A") (pintype "passive"))
      (node (ref "R700") (pin "2") (pinfunction "2_2") (pintype "passive"))
      (node (ref "R702") (pin "1") (pinfunction "1_1") (pintype "passive"))
      (node (ref "R713") (pin "1") (pinfunction "1_1") (pintype "passive"))
      (node (ref "R716") (pin "1") (pinfunction "1_1") (pintype "passive"))
      (node (ref "U$129") (pin "2") (pinfunction "S_2") (pintype "passive"))
    )
    (net (code "792") (name "Net-(U$130-D)") (class "Default")
      (node (ref "R707") (pin "2") (pinfunction "2_2") (pintype "passive"))
      (node (ref "R710") (pin "2") (pinfunction "2_2") (pintype "passive"))
      (node (ref "U$130") (pin "3") (pinfunction "D_3") (pintype "passive"))
    )
    (net (code "793") (name "Net-(U$130-G)") (class "Default")
      (node (ref "R709") (pin "1") (pinfunction "1_1") (pintype "passive"))
      (node (ref "U$130") (pin "1") (pinfunction "G_1") (pintype "passive"))
    )
    (net (code "794") (name "Net-(U$130-S)") (class "Default")
      (node (ref "D127") (pin "A") (pinfunction "A_A") (pintype "passive"))
      (node (ref "D128") (pin "C") (pinfunction "C_C") (pintype "passive"))
      (node (ref "R701") (pin "1") (pinfunction "1_1") (pintype "passive"))
      (node (ref "R704") (pin "1") (pinfunction "1_1") (pintype "passive"))
      (node (ref "R706") (pin "2") (pinfunction "2_2") (pintype "passive"))
      (node (ref "R708") (pin "1") (pinfunction "1_1") (pintype "passive"))
      (node (ref "U$130") (pin "2") (pinfunction "S_2") (pintype "passive"))
    )
    (net (code "795") (name "Net-(U$131-D)") (class "Default")
      (node (ref "R713") (pin "2") (pinfunction "2_2") (pintype "passive"))
      (node (ref "R716") (pin "2") (pinfunction "2_2") (pintype "passive"))
      (node (ref "U$131") (pin "3") (pinfunction "D_3") (pintype "passive"))
    )
    (net (code "796") (name "Net-(U$131-G)") (class "Default")
      (node (ref "R715") (pin "1") (pinfunction "1_1") (pintype "passive"))
      (node (ref "U$131") (pin "1") (pinfunction "G_1") (pintype "passive"))
    )
    (net (code "797") (name "Net-(U$131-S)") (class "Default")
      (node (ref "D129") (pin "C") (pinfunction "C_C") (pintype "passive"))
      (node (ref "D130") (pin "A") (pinfunction "A_A") (pintype "passive"))
      (node (ref "R712") (pin "2") (pinfunction "2_2") (pintype "passive"))
      (node (ref "R714") (pin "1") (pinfunction "1_1") (pintype "passive"))
      (node (ref "R719") (pin "1") (pinfunction "1_1") (pintype "passive"))
      (node (ref "R722") (pin "1") (pinfunction "1_1") (pintype "passive"))
      (node (ref "U$131") (pin "2") (pinfunction "S_2") (pintype "passive"))
    )
    (net (code "798") (name "Net-(U$132-D)") (class "Default")
      (node (ref "R719") (pin "2") (pinfunction "2_2") (pintype "passive"))
      (node (ref "R722") (pin "2") (pinfunction "2_2") (pintype "passive"))
      (node (ref "U$132") (pin "3") (pinfunction "D_3") (pintype "passive"))
    )
    (net (code "799") (name "Net-(U$132-G)") (class "Default")
      (node (ref "R721") (pin "1") (pinfunction "1_1") (pintype "passive"))
      (node (ref "U$132") (pin "1") (pinfunction "G_1") (pintype "passive"))
    )
    (net (code "800") (name "Net-(U$132-S)") (class "Default")
      (node (ref "D130") (pin "C") (pinfunction "C_C") (pintype "passive"))
      (node (ref "D131") (pin "A") (pinfunction "A_A") (pintype "passive"))
      (node (ref "R718") (pin "2") (pinfunction "2_2") (pintype "passive"))
      (node (ref "R720") (pin "1") (pinfunction "1_1") (pintype "passive"))
      (node (ref "R725") (pin "1") (pinfunction "1_1") (pintype "passive"))
      (node (ref "R728") (pin "1") (pinfunction "1_1") (pintype "passive"))
      (node (ref "U$132") (pin "2") (pinfunction "S_2") (pintype "passive"))
    )
    (net (code "801") (name "Net-(U$133-D)") (class "Default")
      (node (ref "R725") (pin "2") (pinfunction "2_2") (pintype "passive"))
      (node (ref "R728") (pin "2") (pinfunction "2_2") (pintype "passive"))
      (node (ref "U$133") (pin "3") (pinfunction "D_3") (pintype "passive"))
    )
    (net (code "802") (name "Net-(U$133-G)") (class "Default")
      (node (ref "R727") (pin "1") (pinfunction "1_1") (pintype "passive"))
      (node (ref "U$133") (pin "1") (pinfunction "G_1") (pintype "passive"))
    )
    (net (code "803") (name "Net-(U$133-S)") (class "Default")
      (node (ref "D131") (pin "C") (pinfunction "C_C") (pintype "passive"))
      (node (ref "D132") (pin "A") (pinfunction "A_A") (pintype "passive"))
      (node (ref "D134") (pin "A") (pinfunction "A_A") (pintype "passive"))
      (node (ref "R724") (pin "2") (pinfunction "2_2") (pintype "passive"))
      (node (ref "R726") (pin "1") (pinfunction "1_1") (pintype "passive"))
      (node (ref "R731") (pin "1") (pinfunction "1_1") (pintype "passive"))
      (node (ref "R734") (pin "1") (pinfunction "1_1") (pintype "passive"))
      (node (ref "U$133") (pin "2") (pinfunction "S_2") (pintype "passive"))
    )
    (net (code "804") (name "Net-(U$134-D)") (class "Default")
      (node (ref "R731") (pin "2") (pinfunction "2_2") (pintype "passive"))
      (node (ref "R734") (pin "2") (pinfunction "2_2") (pintype "passive"))
      (node (ref "U$134") (pin "3") (pinfunction "D_3") (pintype "passive"))
    )
    (net (code "805") (name "Net-(U$134-G)") (class "Default")
      (node (ref "R733") (pin "1") (pinfunction "1_1") (pintype "passive"))
      (node (ref "U$134") (pin "1") (pinfunction "G_1") (pintype "passive"))
    )
    (net (code "806") (name "Net-(U$134-S)") (class "Default")
      (node (ref "D132") (pin "C") (pinfunction "C_C") (pintype "passive"))
      (node (ref "R730") (pin "2") (pinfunction "2_2") (pintype "passive"))
      (node (ref "R732") (pin "1") (pinfunction "1_1") (pintype "passive"))
      (node (ref "U$134") (pin "2") (pinfunction "S_2") (pintype "passive"))
    )
    (net (code "807") (name "S1") (class "Default")
      (node (ref "R11") (pin "2") (pinfunction "2_2") (pintype "passive"))
      (node (ref "U$1") (pin "25") (pinfunction "S1_25") (pintype "bidirectional"))
    )
    (net (code "808") (name "S1-2") (class "Default")
      (node (ref "R96") (pin "2") (pinfunction "2_2") (pintype "passive"))
      (node (ref "U$16") (pin "25") (pinfunction "S1_25") (pintype "bidirectional"))
    )
    (net (code "809") (name "S1-3") (class "Default")
      (node (ref "R190") (pin "2") (pinfunction "2_2") (pintype "passive"))
      (node (ref "U$34") (pin "25") (pinfunction "S1_25") (pintype "bidirectional"))
    )
    (net (code "810") (name "S1-4") (class "Default")
      (node (ref "R175") (pin "2") (pinfunction "2_2") (pintype "passive"))
      (node (ref "U$31") (pin "25") (pinfunction "S1_25") (pintype "bidirectional"))
    )
    (net (code "811") (name "S1-5") (class "Default")
      (node (ref "R341") (pin "2") (pinfunction "2_2") (pintype "passive"))
      (node (ref "U$61") (pin "25") (pinfunction "S1_25") (pintype "bidirectional"))
    )
    (net (code "812") (name "S1-6") (class "Default")
      (node (ref "R424") (pin "2") (pinfunction "2_2") (pintype "passive"))
      (node (ref "U$76") (pin "25") (pinfunction "S1_25") (pintype "bidirectional"))
    )
    (net (code "813") (name "S1-7") (class "Default")
      (node (ref "R507") (pin "2") (pinfunction "2_2") (pintype "passive"))
      (node (ref "U$91") (pin "25") (pinfunction "S1_25") (pintype "bidirectional"))
    )
    (net (code "814") (name "S1-8") (class "Default")
      (node (ref "R590") (pin "2") (pinfunction "2_2") (pintype "passive"))
      (node (ref "U$106") (pin "25") (pinfunction "S1_25") (pintype "bidirectional"))
    )
    (net (code "815") (name "S1-9") (class "Default")
      (node (ref "R673") (pin "2") (pinfunction "2_2") (pintype "passive"))
      (node (ref "U$121") (pin "25") (pinfunction "S1_25") (pintype "bidirectional"))
    )
    (net (code "816") (name "S2") (class "Default")
      (node (ref "R5") (pin "2") (pinfunction "2_2") (pintype "passive"))
      (node (ref "U$1") (pin "23") (pinfunction "S2_23") (pintype "bidirectional"))
    )
    (net (code "817") (name "S2-2") (class "Default")
      (node (ref "R90") (pin "2") (pinfunction "2_2") (pintype "passive"))
      (node (ref "U$16") (pin "23") (pinfunction "S2_23") (pintype "bidirectional"))
    )
    (net (code "818") (name "S2-3") (class "Default")
      (node (ref "R184") (pin "2") (pinfunction "2_2") (pintype "passive"))
      (node (ref "U$34") (pin "23") (pinfunction "S2_23") (pintype "bidirectional"))
    )
    (net (code "819") (name "S2-4") (class "Default")
      (node (ref "R86") (pin "2") (pinfunction "2_2") (pintype "passive"))
      (node (ref "U$31") (pin "23") (pinfunction "S2_23") (pintype "bidirectional"))
    )
    (net (code "820") (name "S2-5") (class "Default")
      (node (ref "R335") (pin "2") (pinfunction "2_2") (pintype "passive"))
      (node (ref "U$61") (pin "23") (pinfunction "S2_23") (pintype "bidirectional"))
    )
    (net (code "821") (name "S2-6") (class "Default")
      (node (ref "R418") (pin "2") (pinfunction "2_2") (pintype "passive"))
      (node (ref "U$76") (pin "23") (pinfunction "S2_23") (pintype "bidirectional"))
    )
    (net (code "822") (name "S2-7") (class "Default")
      (node (ref "R501") (pin "2") (pinfunction "2_2") (pintype "passive"))
      (node (ref "U$91") (pin "23") (pinfunction "S2_23") (pintype "bidirectional"))
    )
    (net (code "823") (name "S2-8") (class "Default")
      (node (ref "R584") (pin "2") (pinfunction "2_2") (pintype "passive"))
      (node (ref "U$106") (pin "23") (pinfunction "S2_23") (pintype "bidirectional"))
    )
    (net (code "824") (name "S2-9") (class "Default")
      (node (ref "R667") (pin "2") (pinfunction "2_2") (pintype "passive"))
      (node (ref "U$121") (pin "23") (pinfunction "S2_23") (pintype "bidirectional"))
    )
    (net (code "825") (name "S3") (class "Default")
      (node (ref "R17") (pin "2") (pinfunction "2_2") (pintype "passive"))
      (node (ref "U$1") (pin "P$21") (pinfunction "S3_P$21") (pintype "bidirectional"))
    )
    (net (code "826") (name "S3-2") (class "Default")
      (node (ref "R102") (pin "2") (pinfunction "2_2") (pintype "passive"))
      (node (ref "U$16") (pin "P$21") (pinfunction "S3_P$21") (pintype "bidirectional"))
    )
    (net (code "827") (name "S3-3") (class "Default")
      (node (ref "R196") (pin "2") (pinfunction "2_2") (pintype "passive"))
      (node (ref "U$34") (pin "P$21") (pinfunction "S3_P$21") (pintype "bidirectional"))
    )
    (net (code "828") (name "S3-4") (class "Default")
      (node (ref "R182") (pin "2") (pinfunction "2_2") (pintype "passive"))
      (node (ref "U$31") (pin "P$21") (pinfunction "S3_P$21") (pintype "bidirectional"))
    )
    (net (code "829") (name "S3-5") (class "Default")
      (node (ref "R347") (pin "2") (pinfunction "2_2") (pintype "passive"))
      (node (ref "U$61") (pin "P$21") (pinfunction "S3_P$21") (pintype "bidirectional"))
    )
    (net (code "830") (name "S3-6") (class "Default")
      (node (ref "R430") (pin "2") (pinfunction "2_2") (pintype "passive"))
      (node (ref "U$76") (pin "P$21") (pinfunction "S3_P$21") (pintype "bidirectional"))
    )
    (net (code "831") (name "S3-7") (class "Default")
      (node (ref "R513") (pin "2") (pinfunction "2_2") (pintype "passive"))
      (node (ref "U$91") (pin "P$21") (pinfunction "S3_P$21") (pintype "bidirectional"))
    )
    (net (code "832") (name "S3-8") (class "Default")
      (node (ref "R596") (pin "2") (pinfunction "2_2") (pintype "passive"))
      (node (ref "U$106") (pin "P$21") (pinfunction "S3_P$21") (pintype "bidirectional"))
    )
    (net (code "833") (name "S3-9") (class "Default")
      (node (ref "R679") (pin "2") (pinfunction "2_2") (pintype "passive"))
      (node (ref "U$121") (pin "P$21") (pinfunction "S3_P$21") (pintype "bidirectional"))
    )
    (net (code "834") (name "S4") (class "Default")
      (node (ref "R23") (pin "2") (pinfunction "2_2") (pintype "passive"))
      (node (ref "U$1") (pin "P$19") (pinfunction "S4_P$19") (pintype "bidirectional"))
    )
    (net (code "835") (name "S4-2") (class "Default")
      (node (ref "R108") (pin "2") (pinfunction "2_2") (pintype "passive"))
      (node (ref "U$16") (pin "P$19") (pinfunction "S4_P$19") (pintype "bidirectional"))
    )
    (net (code "836") (name "S4-3") (class "Default")
      (node (ref "R202") (pin "2") (pinfunction "2_2") (pintype "passive"))
      (node (ref "U$34") (pin "P$19") (pinfunction "S4_P$19") (pintype "bidirectional"))
    )
    (net (code "837") (name "S4-4") (class "Default")
      (node (ref "R270") (pin "2") (pinfunction "2_2") (pintype "passive"))
      (node (ref "U$31") (pin "P$19") (pinfunction "S4_P$19") (pintype "bidirectional"))
    )
    (net (code "838") (name "S4-5") (class "Default")
      (node (ref "R353") (pin "2") (pinfunction "2_2") (pintype "passive"))
      (node (ref "U$61") (pin "P$19") (pinfunction "S4_P$19") (pintype "bidirectional"))
    )
    (net (code "839") (name "S4-6") (class "Default")
      (node (ref "R436") (pin "2") (pinfunction "2_2") (pintype "passive"))
      (node (ref "U$76") (pin "P$19") (pinfunction "S4_P$19") (pintype "bidirectional"))
    )
    (net (code "840") (name "S4-7") (class "Default")
      (node (ref "R519") (pin "2") (pinfunction "2_2") (pintype "passive"))
      (node (ref "U$91") (pin "P$19") (pinfunction "S4_P$19") (pintype "bidirectional"))
    )
    (net (code "841") (name "S4-8") (class "Default")
      (node (ref "R602") (pin "2") (pinfunction "2_2") (pintype "passive"))
      (node (ref "U$106") (pin "P$19") (pinfunction "S4_P$19") (pintype "bidirectional"))
    )
    (net (code "842") (name "S4-9") (class "Default")
      (node (ref "R685") (pin "2") (pinfunction "2_2") (pintype "passive"))
      (node (ref "U$121") (pin "P$19") (pinfunction "S4_P$19") (pintype "bidirectional"))
    )
    (net (code "843") (name "S5") (class "Default")
      (node (ref "R29") (pin "2") (pinfunction "2_2") (pintype "passive"))
      (node (ref "U$1") (pin "P$17") (pinfunction "S5_P$17") (pintype "bidirectional"))
    )
    (net (code "844") (name "S5-2") (class "Default")
      (node (ref "R114") (pin "2") (pinfunction "2_2") (pintype "passive"))
      (node (ref "U$16") (pin "P$17") (pinfunction "S5_P$17") (pintype "bidirectional"))
    )
    (net (code "845") (name "S5-3") (class "Default")
      (node (ref "R208") (pin "2") (pinfunction "2_2") (pintype "passive"))
      (node (ref "U$34") (pin "P$17") (pinfunction "S5_P$17") (pintype "bidirectional"))
    )
    (net (code "846") (name "S5-4") (class "Default")
      (node (ref "R276") (pin "2") (pinfunction "2_2") (pintype "passive"))
      (node (ref "U$31") (pin "P$17") (pinfunction "S5_P$17") (pintype "bidirectional"))
    )
    (net (code "847") (name "S5-5") (class "Default")
      (node (ref "R359") (pin "2") (pinfunction "2_2") (pintype "passive"))
      (node (ref "U$61") (pin "P$17") (pinfunction "S5_P$17") (pintype "bidirectional"))
    )
    (net (code "848") (name "S5-6") (class "Default")
      (node (ref "R442") (pin "2") (pinfunction "2_2") (pintype "passive"))
      (node (ref "U$76") (pin "P$17") (pinfunction "S5_P$17") (pintype "bidirectional"))
    )
    (net (code "849") (name "S5-7") (class "Default")
      (node (ref "R525") (pin "2") (pinfunction "2_2") (pintype "passive"))
      (node (ref "U$91") (pin "P$17") (pinfunction "S5_P$17") (pintype "bidirectional"))
    )
    (net (code "850") (name "S5-8") (class "Default")
      (node (ref "R608") (pin "2") (pinfunction "2_2") (pintype "passive"))
      (node (ref "U$106") (pin "P$17") (pinfunction "S5_P$17") (pintype "bidirectional"))
    )
    (net (code "851") (name "S5-9") (class "Default")
      (node (ref "R691") (pin "2") (pinfunction "2_2") (pintype "passive"))
      (node (ref "U$121") (pin "P$17") (pinfunction "S5_P$17") (pintype "bidirectional"))
    )
    (net (code "852") (name "S6") (class "Default")
      (node (ref "R35") (pin "2") (pinfunction "2_2") (pintype "passive"))
      (node (ref "U$1") (pin "P$15") (pinfunction "S6_P$15") (pintype "bidirectional"))
    )
    (net (code "853") (name "S6-2") (class "Default")
      (node (ref "R120") (pin "2") (pinfunction "2_2") (pintype "passive"))
      (node (ref "U$16") (pin "P$15") (pinfunction "S6_P$15") (pintype "bidirectional"))
    )
    (net (code "854") (name "S6-3") (class "Default")
      (node (ref "R214") (pin "2") (pinfunction "2_2") (pintype "passive"))
      (node (ref "U$34") (pin "P$15") (pinfunction "S6_P$15") (pintype "bidirectional"))
    )
    (net (code "855") (name "S6-4") (class "Default")
      (node (ref "R282") (pin "2") (pinfunction "2_2") (pintype "passive"))
      (node (ref "U$31") (pin "P$15") (pinfunction "S6_P$15") (pintype "bidirectional"))
    )
    (net (code "856") (name "S6-5") (class "Default")
      (node (ref "R365") (pin "2") (pinfunction "2_2") (pintype "passive"))
      (node (ref "U$61") (pin "P$15") (pinfunction "S6_P$15") (pintype "bidirectional"))
    )
    (net (code "857") (name "S6-6") (class "Default")
      (node (ref "R448") (pin "2") (pinfunction "2_2") (pintype "passive"))
      (node (ref "U$76") (pin "P$15") (pinfunction "S6_P$15") (pintype "bidirectional"))
    )
    (net (code "858") (name "S6-7") (class "Default")
      (node (ref "R531") (pin "2") (pinfunction "2_2") (pintype "passive"))
      (node (ref "U$91") (pin "P$15") (pinfunction "S6_P$15") (pintype "bidirectional"))
    )
    (net (code "859") (name "S6-8") (class "Default")
      (node (ref "R614") (pin "2") (pinfunction "2_2") (pintype "passive"))
      (node (ref "U$106") (pin "P$15") (pinfunction "S6_P$15") (pintype "bidirectional"))
    )
    (net (code "860") (name "S6-9") (class "Default")
      (node (ref "R697") (pin "2") (pinfunction "2_2") (pintype "passive"))
      (node (ref "U$121") (pin "P$15") (pinfunction "S6_P$15") (pintype "bidirectional"))
    )
    (net (code "861") (name "S7") (class "Default")
      (node (ref "R47") (pin "2") (pinfunction "2_2") (pintype "passive"))
      (node (ref "U$1") (pin "P$13") (pinfunction "S7_P$13") (pintype "bidirectional"))
    )
    (net (code "862") (name "S7-2") (class "Default")
      (node (ref "R132") (pin "2") (pinfunction "2_2") (pintype "passive"))
      (node (ref "U$16") (pin "P$13") (pinfunction "S7_P$13") (pintype "bidirectional"))
    )
    (net (code "863") (name "S7-3") (class "Default")
      (node (ref "R226") (pin "2") (pinfunction "2_2") (pintype "passive"))
      (node (ref "U$34") (pin "P$13") (pinfunction "S7_P$13") (pintype "bidirectional"))
    )
    (net (code "864") (name "S7-4") (class "Default")
      (node (ref "R294") (pin "2") (pinfunction "2_2") (pintype "passive"))
      (node (ref "U$31") (pin "P$13") (pinfunction "S7_P$13") (pintype "bidirectional"))
    )
    (net (code "865") (name "S7-5") (class "Default")
      (node (ref "R377") (pin "2") (pinfunction "2_2") (pintype "passive"))
      (node (ref "U$61") (pin "P$13") (pinfunction "S7_P$13") (pintype "bidirectional"))
    )
    (net (code "866") (name "S7-6") (class "Default")
      (node (ref "R460") (pin "2") (pinfunction "2_2") (pintype "passive"))
      (node (ref "U$76") (pin "P$13") (pinfunction "S7_P$13") (pintype "bidirectional"))
    )
    (net (code "867") (name "S7-7") (class "Default")
      (node (ref "R543") (pin "2") (pinfunction "2_2") (pintype "passive"))
      (node (ref "U$91") (pin "P$13") (pinfunction "S7_P$13") (pintype "bidirectional"))
    )
    (net (code "868") (name "S7-8") (class "Default")
      (node (ref "R626") (pin "2") (pinfunction "2_2") (pintype "passive"))
      (node (ref "U$106") (pin "P$13") (pinfunction "S7_P$13") (pintype "bidirectional"))
    )
    (net (code "869") (name "S7-9") (class "Default")
      (node (ref "R709") (pin "2") (pinfunction "2_2") (pintype "passive"))
      (node (ref "U$121") (pin "P$13") (pinfunction "S7_P$13") (pintype "bidirectional"))
    )
    (net (code "870") (name "S8") (class "Default")
      (node (ref "R41") (pin "2") (pinfunction "2_2") (pintype "passive"))
      (node (ref "U$1") (pin "P$11") (pinfunction "S8_P$11") (pintype "bidirectional"))
    )
    (net (code "871") (name "S8-2") (class "Default")
      (node (ref "R126") (pin "2") (pinfunction "2_2") (pintype "passive"))
      (node (ref "U$16") (pin "P$11") (pinfunction "S8_P$11") (pintype "bidirectional"))
    )
    (net (code "872") (name "S8-3") (class "Default")
      (node (ref "R220") (pin "2") (pinfunction "2_2") (pintype "passive"))
      (node (ref "U$34") (pin "P$11") (pinfunction "S8_P$11") (pintype "bidirectional"))
    )
    (net (code "873") (name "S8-4") (class "Default")
      (node (ref "R288") (pin "2") (pinfunction "2_2") (pintype "passive"))
      (node (ref "U$31") (pin "P$11") (pinfunction "S8_P$11") (pintype "bidirectional"))
    )
    (net (code "874") (name "S8-5") (class "Default")
      (node (ref "R371") (pin "2") (pinfunction "2_2") (pintype "passive"))
      (node (ref "U$61") (pin "P$11") (pinfunction "S8_P$11") (pintype "bidirectional"))
    )
    (net (code "875") (name "S8-6") (class "Default")
      (node (ref "R454") (pin "2") (pinfunction "2_2") (pintype "passive"))
      (node (ref "U$76") (pin "P$11") (pinfunction "S8_P$11") (pintype "bidirectional"))
    )
    (net (code "876") (name "S8-7") (class "Default")
      (node (ref "R537") (pin "2") (pinfunction "2_2") (pintype "passive"))
      (node (ref "U$91") (pin "P$11") (pinfunction "S8_P$11") (pintype "bidirectional"))
    )
    (net (code "877") (name "S8-8") (class "Default")
      (node (ref "R620") (pin "2") (pinfunction "2_2") (pintype "passive"))
      (node (ref "U$106") (pin "P$11") (pinfunction "S8_P$11") (pintype "bidirectional"))
    )
    (net (code "878") (name "S8-9") (class "Default")
      (node (ref "R703") (pin "2") (pinfunction "2_2") (pintype "passive"))
      (node (ref "U$121") (pin "P$11") (pinfunction "S8_P$11") (pintype "bidirectional"))
    )
    (net (code "879") (name "S9") (class "Default")
      (node (ref "R53") (pin "2") (pinfunction "2_2") (pintype "passive"))
      (node (ref "U$1") (pin "P$9") (pinfunction "S9_P$9") (pintype "bidirectional"))
    )
    (net (code "880") (name "S9-2") (class "Default")
      (node (ref "R138") (pin "2") (pinfunction "2_2") (pintype "passive"))
      (node (ref "U$16") (pin "P$9") (pinfunction "S9_P$9") (pintype "bidirectional"))
    )
    (net (code "881") (name "S9-3") (class "Default")
      (node (ref "R232") (pin "2") (pinfunction "2_2") (pintype "passive"))
      (node (ref "U$34") (pin "P$9") (pinfunction "S9_P$9") (pintype "bidirectional"))
    )
    (net (code "882") (name "S9-4") (class "Default")
      (node (ref "R300") (pin "2") (pinfunction "2_2") (pintype "passive"))
      (node (ref "U$31") (pin "P$9") (pinfunction "S9_P$9") (pintype "bidirectional"))
    )
    (net (code "883") (name "S9-5") (class "Default")
      (node (ref "R383") (pin "2") (pinfunction "2_2") (pintype "passive"))
      (node (ref "U$61") (pin "P$9") (pinfunction "S9_P$9") (pintype "bidirectional"))
    )
    (net (code "884") (name "S9-6") (class "Default")
      (node (ref "R466") (pin "2") (pinfunction "2_2") (pintype "passive"))
      (node (ref "U$76") (pin "P$9") (pinfunction "S9_P$9") (pintype "bidirectional"))
    )
    (net (code "885") (name "S9-7") (class "Default")
      (node (ref "R549") (pin "2") (pinfunction "2_2") (pintype "passive"))
      (node (ref "U$91") (pin "P$9") (pinfunction "S9_P$9") (pintype "bidirectional"))
    )
    (net (code "886") (name "S9-8") (class "Default")
      (node (ref "R632") (pin "2") (pinfunction "2_2") (pintype "passive"))
      (node (ref "U$106") (pin "P$9") (pinfunction "S9_P$9") (pintype "bidirectional"))
    )
    (net (code "887") (name "S9-9") (class "Default")
      (node (ref "R715") (pin "2") (pinfunction "2_2") (pintype "passive"))
      (node (ref "U$121") (pin "P$9") (pinfunction "S9_P$9") (pintype "bidirectional"))
    )
    (net (code "888") (name "S10") (class "Default")
      (node (ref "R59") (pin "2") (pinfunction "2_2") (pintype "passive"))
      (node (ref "U$1") (pin "P$7") (pinfunction "S10_P$7") (pintype "bidirectional"))
    )
    (net (code "889") (name "S10-2") (class "Default")
      (node (ref "R144") (pin "2") (pinfunction "2_2") (pintype "passive"))
      (node (ref "U$16") (pin "P$7") (pinfunction "S10_P$7") (pintype "bidirectional"))
    )
    (net (code "890") (name "S10-3") (class "Default")
      (node (ref "R238") (pin "2") (pinfunction "2_2") (pintype "passive"))
      (node (ref "U$34") (pin "P$7") (pinfunction "S10_P$7") (pintype "bidirectional"))
    )
    (net (code "891") (name "S10-4") (class "Default")
      (node (ref "R306") (pin "2") (pinfunction "2_2") (pintype "passive"))
      (node (ref "U$31") (pin "P$7") (pinfunction "S10_P$7") (pintype "bidirectional"))
    )
    (net (code "892") (name "S10-5") (class "Default")
      (node (ref "R389") (pin "2") (pinfunction "2_2") (pintype "passive"))
      (node (ref "U$61") (pin "P$7") (pinfunction "S10_P$7") (pintype "bidirectional"))
    )
    (net (code "893") (name "S10-6") (class "Default")
      (node (ref "R472") (pin "2") (pinfunction "2_2") (pintype "passive"))
      (node (ref "U$76") (pin "P$7") (pinfunction "S10_P$7") (pintype "bidirectional"))
    )
    (net (code "894") (name "S10-7") (class "Default")
      (node (ref "R555") (pin "2") (pinfunction "2_2") (pintype "passive"))
      (node (ref "U$91") (pin "P$7") (pinfunction "S10_P$7") (pintype "bidirectional"))
    )
    (net (code "895") (name "S10-8") (class "Default")
      (node (ref "R638") (pin "2") (pinfunction "2_2") (pintype "passive"))
      (node (ref "U$106") (pin "P$7") (pinfunction "S10_P$7") (pintype "bidirectional"))
    )
    (net (code "896") (name "S10-9") (class "Default")
      (node (ref "R721") (pin "2") (pinfunction "2_2") (pintype "passive"))
      (node (ref "U$121") (pin "P$7") (pinfunction "S10_P$7") (pintype "bidirectional"))
    )
    (net (code "897") (name "S11") (class "Default")
      (node (ref "R65") (pin "2") (pinfunction "2_2") (pintype "passive"))
      (node (ref "U$1") (pin "P$5") (pinfunction "S11_P$5") (pintype "bidirectional"))
    )
    (net (code "898") (name "S11-2") (class "Default")
      (node (ref "R150") (pin "2") (pinfunction "2_2") (pintype "passive"))
      (node (ref "U$16") (pin "P$5") (pinfunction "S11_P$5") (pintype "bidirectional"))
    )
    (net (code "899") (name "S11-3") (class "Default")
      (node (ref "R244") (pin "2") (pinfunction "2_2") (pintype "passive"))
      (node (ref "U$34") (pin "P$5") (pinfunction "S11_P$5") (pintype "bidirectional"))
    )
    (net (code "900") (name "S11-4") (class "Default")
      (node (ref "R312") (pin "2") (pinfunction "2_2") (pintype "passive"))
      (node (ref "U$31") (pin "P$5") (pinfunction "S11_P$5") (pintype "bidirectional"))
    )
    (net (code "901") (name "S11-5") (class "Default")
      (node (ref "R395") (pin "2") (pinfunction "2_2") (pintype "passive"))
      (node (ref "U$61") (pin "P$5") (pinfunction "S11_P$5") (pintype "bidirectional"))
    )
    (net (code "902") (name "S11-6") (class "Default")
      (node (ref "R478") (pin "2") (pinfunction "2_2") (pintype "passive"))
      (node (ref "U$76") (pin "P$5") (pinfunction "S11_P$5") (pintype "bidirectional"))
    )
    (net (code "903") (name "S11-7") (class "Default")
      (node (ref "R561") (pin "2") (pinfunction "2_2") (pintype "passive"))
      (node (ref "U$91") (pin "P$5") (pinfunction "S11_P$5") (pintype "bidirectional"))
    )
    (net (code "904") (name "S11-8") (class "Default")
      (node (ref "R644") (pin "2") (pinfunction "2_2") (pintype "passive"))
      (node (ref "U$106") (pin "P$5") (pinfunction "S11_P$5") (pintype "bidirectional"))
    )
    (net (code "905") (name "S11-9") (class "Default")
      (node (ref "R727") (pin "2") (pinfunction "2_2") (pintype "passive"))
      (node (ref "U$121") (pin "P$5") (pinfunction "S11_P$5") (pintype "bidirectional"))
    )
    (net (code "906") (name "S12") (class "Default")
      (node (ref "R71") (pin "2") (pinfunction "2_2") (pintype "passive"))
      (node (ref "U$1") (pin "P$3") (pinfunction "S12_P$3") (pintype "bidirectional"))
    )
    (net (code "907") (name "S12-2") (class "Default")
      (node (ref "R156") (pin "2") (pinfunction "2_2") (pintype "passive"))
      (node (ref "U$16") (pin "P$3") (pinfunction "S12_P$3") (pintype "bidirectional"))
    )
    (net (code "908") (name "S12-3") (class "Default")
      (node (ref "R250") (pin "2") (pinfunction "2_2") (pintype "passive"))
      (node (ref "U$34") (pin "P$3") (pinfunction "S12_P$3") (pintype "bidirectional"))
    )
    (net (code "909") (name "S12-4") (class "Default")
      (node (ref "R318") (pin "2") (pinfunction "2_2") (pintype "passive"))
      (node (ref "U$31") (pin "P$3") (pinfunction "S12_P$3") (pintype "bidirectional"))
    )
    (net (code "910") (name "S12-5") (class "Default")
      (node (ref "R401") (pin "2") (pinfunction "2_2") (pintype "passive"))
      (node (ref "U$61") (pin "P$3") (pinfunction "S12_P$3") (pintype "bidirectional"))
    )
    (net (code "911") (name "S12-6") (class "Default")
      (node (ref "R484") (pin "2") (pinfunction "2_2") (pintype "passive"))
      (node (ref "U$76") (pin "P$3") (pinfunction "S12_P$3") (pintype "bidirectional"))
    )
    (net (code "912") (name "S12-7") (class "Default")
      (node (ref "R567") (pin "2") (pinfunction "2_2") (pintype "passive"))
      (node (ref "U$91") (pin "P$3") (pinfunction "S12_P$3") (pintype "bidirectional"))
    )
    (net (code "913") (name "S12-8") (class "Default")
      (node (ref "R650") (pin "2") (pinfunction "2_2") (pintype "passive"))
      (node (ref "U$106") (pin "P$3") (pinfunction "S12_P$3") (pintype "bidirectional"))
    )
    (net (code "914") (name "S12-9") (class "Default")
      (node (ref "R733") (pin "2") (pinfunction "2_2") (pintype "passive"))
      (node (ref "U$121") (pin "P$3") (pinfunction "S12_P$3") (pintype "bidirectional"))
    )
    (net (code "915") (name "SCK") (class "Default")
      (node (ref "JP1") (pin "5") (pinfunction "5_5") (pintype "passive"))
      (node (ref "U$107") (pin "3") (pinfunction "A1_3") (pintype "bidirectional"))
      (node (ref "U$122") (pin "3") (pinfunction "A1_3") (pintype "bidirectional"))
      (node (ref "U$17") (pin "3") (pinfunction "A1_3") (pintype "bidirectional"))
      (node (ref "U$2") (pin "3") (pinfunction "A1_3") (pintype "bidirectional"))
      (node (ref "U$32") (pin "3") (pinfunction "A1_3") (pintype "bidirectional"))
      (node (ref "U$35") (pin "3") (pinfunction "A1_3") (pintype "bidirectional"))
      (node (ref "U$62") (pin "3") (pinfunction "A1_3") (pintype "bidirectional"))
      (node (ref "U$77") (pin "3") (pinfunction "A1_3") (pintype "bidirectional"))
      (node (ref "U$92") (pin "3") (pinfunction "A1_3") (pintype "bidirectional"))
    )
    (net (code "916") (name "SDI") (class "Default")
      (node (ref "JP1") (pin "4") (pinfunction "4_4") (pintype "passive"))
      (node (ref "U$107") (pin "4") (pinfunction "A2_4") (pintype "bidirectional"))
      (node (ref "U$122") (pin "4") (pinfunction "A2_4") (pintype "bidirectional"))
      (node (ref "U$17") (pin "4") (pinfunction "A2_4") (pintype "bidirectional"))
      (node (ref "U$2") (pin "4") (pinfunction "A2_4") (pintype "bidirectional"))
      (node (ref "U$32") (pin "4") (pinfunction "A2_4") (pintype "bidirectional"))
      (node (ref "U$35") (pin "4") (pinfunction "A2_4") (pintype "bidirectional"))
      (node (ref "U$62") (pin "4") (pinfunction "A2_4") (pintype "bidirectional"))
      (node (ref "U$77") (pin "4") (pinfunction "A2_4") (pintype "bidirectional"))
      (node (ref "U$92") (pin "4") (pinfunction "A2_4") (pintype "bidirectional"))
    )
    (net (code "917") (name "SDO") (class "Default")
      (node (ref "D105") (pin "A") (pinfunction "A_A") (pintype "passive"))
      (node (ref "D120") (pin "A") (pinfunction "A_A") (pintype "passive"))
      (node (ref "D135") (pin "A") (pinfunction "A_A") (pintype "passive"))
      (node (ref "D32") (pin "A") (pinfunction "A_A") (pintype "passive"))
      (node (ref "D33") (pin "A") (pinfunction "A_A") (pintype "passive"))
      (node (ref "D47") (pin "A") (pinfunction "A_A") (pintype "passive"))
      (node (ref "D60") (pin "A") (pinfunction "A_A") (pintype "passive"))
      (node (ref "D75") (pin "A") (pinfunction "A_A") (pintype "passive"))
      (node (ref "D90") (pin "A") (pinfunction "A_A") (pintype "passive"))
      (node (ref "JP1") (pin "2") (pinfunction "2_2") (pintype "passive"))
    )
    (net (code "918") (name "V1+") (class "Default")
      (node (ref "C13") (pin "2") (pinfunction "2_2") (pintype "passive"))
      (node (ref "C14") (pin "2") (pinfunction "2_2") (pintype "passive"))
      (node (ref "R81") (pin "2") (pinfunction "2_2") (pintype "passive"))
      (node (ref "R82") (pin "2") (pinfunction "2_2") (pintype "passive"))
      (node (ref "U$1") (pin "P$1") (pinfunction "V+_P$1") (pintype "bidirectional"))
    )
    (net (code "919") (name "V1+2") (class "Default")
      (node (ref "C31") (pin "2") (pinfunction "2_2") (pintype "passive"))
      (node (ref "C32") (pin "2") (pinfunction "2_2") (pintype "passive"))
      (node (ref "R166") (pin "2") (pinfunction "2_2") (pintype "passive"))
      (node (ref "R167") (pin "2") (pinfunction "2_2") (pintype "passive"))
      (node (ref "U$16") (pin "P$1") (pinfunction "V+_P$1") (pintype "bidirectional"))
    )
    (net (code "920") (name "V1+3") (class "Default")
      (node (ref "C74") (pin "2") (pinfunction "2_2") (pintype "passive"))
      (node (ref "C75") (pin "2") (pinfunction "2_2") (pintype "passive"))
      (node (ref "R260") (pin "2") (pinfunction "2_2") (pintype "passive"))
      (node (ref "R261") (pin "2") (pinfunction "2_2") (pintype "passive"))
      (node (ref "U$34") (pin "P$1") (pinfunction "V+_P$1") (pintype "bidirectional"))
    )
    (net (code "921") (name "V1+4") (class "Default")
      (node (ref "C49") (pin "2") (pinfunction "2_2") (pintype "passive"))
      (node (ref "C50") (pin "2") (pinfunction "2_2") (pintype "passive"))
      (node (ref "R327") (pin "2") (pinfunction "2_2") (pintype "passive"))
      (node (ref "R328") (pin "2") (pinfunction "2_2") (pintype "passive"))
      (node (ref "U$31") (pin "P$1") (pinfunction "V+_P$1") (pintype "bidirectional"))
    )
    (net (code "922") (name "V1+5") (class "Default")
      (node (ref "C81") (pin "2") (pinfunction "2_2") (pintype "passive"))
      (node (ref "C82") (pin "2") (pinfunction "2_2") (pintype "passive"))
      (node (ref "R410") (pin "2") (pinfunction "2_2") (pintype "passive"))
      (node (ref "R411") (pin "2") (pinfunction "2_2") (pintype "passive"))
      (node (ref "U$61") (pin "P$1") (pinfunction "V+_P$1") (pintype "bidirectional"))
    )
    (net (code "923") (name "V1+6") (class "Default")
      (node (ref "C98") (pin "2") (pinfunction "2_2") (pintype "passive"))
      (node (ref "C99") (pin "2") (pinfunction "2_2") (pintype "passive"))
      (node (ref "R493") (pin "2") (pinfunction "2_2") (pintype "passive"))
      (node (ref "R494") (pin "2") (pinfunction "2_2") (pintype "passive"))
      (node (ref "U$76") (pin "P$1") (pinfunction "V+_P$1") (pintype "bidirectional"))
    )
    (net (code "924") (name "V1+7") (class "Default")
      (node (ref "C115") (pin "2") (pinfunction "2_2") (pintype "passive"))
      (node (ref "C116") (pin "2") (pinfunction "2_2") (pintype "passive"))
      (node (ref "R576") (pin "2") (pinfunction "2_2") (pintype "passive"))
      (node (ref "R577") (pin "2") (pinfunction "2_2") (pintype "passive"))
      (node (ref "U$91") (pin "P$1") (pinfunction "V+_P$1") (pintype "bidirectional"))
    )
    (net (code "925") (name "V1+8") (class "Default")
      (node (ref "C132") (pin "2") (pinfunction "2_2") (pintype "passive"))
      (node (ref "C133") (pin "2") (pinfunction "2_2") (pintype "passive"))
      (node (ref "R659") (pin "2") (pinfunction "2_2") (pintype "passive"))
      (node (ref "R660") (pin "2") (pinfunction "2_2") (pintype "passive"))
      (node (ref "U$106") (pin "P$1") (pinfunction "V+_P$1") (pintype "bidirectional"))
    )
    (net (code "926") (name "V1+9") (class "Default")
      (node (ref "C149") (pin "2") (pinfunction "2_2") (pintype "passive"))
      (node (ref "C150") (pin "2") (pinfunction "2_2") (pintype "passive"))
      (node (ref "R742") (pin "2") (pinfunction "2_2") (pintype "passive"))
      (node (ref "R743") (pin "2") (pinfunction "2_2") (pintype "passive"))
      (node (ref "U$121") (pin "P$1") (pinfunction "V+_P$1") (pintype "bidirectional"))
    )
    (net (code "927") (name "VDD") (class "Default")
      (node (ref "JP1") (pin "6") (pinfunction "6_6") (pintype "passive"))
      (node (ref "U$107") (pin "1") (pinfunction "VDD1_1") (pintype "bidirectional"))
      (node (ref "U$107") (pin "7") (pinfunction "EN1_7") (pintype "bidirectional"))
      (node (ref "U$122") (pin "1") (pinfunction "VDD1_1") (pintype "bidirectional"))
      (node (ref "U$122") (pin "7") (pinfunction "EN1_7") (pintype "bidirectional"))
      (node (ref "U$17") (pin "1") (pinfunction "VDD1_1") (pintype "bidirectional"))
      (node (ref "U$17") (pin "7") (pinfunction "EN1_7") (pintype "bidirectional"))
      (node (ref "U$2") (pin "1") (pinfunction "VDD1_1") (pintype "bidirectional"))
      (node (ref "U$2") (pin "7") (pinfunction "EN1_7") (pintype "bidirectional"))
      (node (ref "U$32") (pin "1") (pinfunction "VDD1_1") (pintype "bidirectional"))
      (node (ref "U$32") (pin "7") (pinfunction "EN1_7") (pintype "bidirectional"))
      (node (ref "U$35") (pin "1") (pinfunction "VDD1_1") (pintype "bidirectional"))
      (node (ref "U$35") (pin "7") (pinfunction "EN1_7") (pintype "bidirectional"))
      (node (ref "U$62") (pin "1") (pinfunction "VDD1_1") (pintype "bidirectional"))
      (node (ref "U$62") (pin "7") (pinfunction "EN1_7") (pintype "bidirectional"))
      (node (ref "U$77") (pin "1") (pinfunction "VDD1_1") (pintype "bidirectional"))
      (node (ref "U$77") (pin "7") (pinfunction "EN1_7") (pintype "bidirectional"))
      (node (ref "U$92") (pin "1") (pinfunction "VDD1_1") (pintype "bidirectional"))
      (node (ref "U$92") (pin "7") (pinfunction "EN1_7") (pintype "bidirectional"))
    )
    (net (code "928") (name "unconnected-(U$1-GPIO1-Pad35)") (class "Default")
      (node (ref "U$1") (pin "35") (pinfunction "GPIO1_35") (pintype "bidirectional"))
    )
    (net (code "929") (name "unconnected-(U$1-GPIO2-Pad36)") (class "Default")
      (node (ref "U$1") (pin "36") (pinfunction "GPIO2_36") (pintype "bidirectional"))
    )
    (net (code "930") (name "unconnected-(U$1-VTEMP1-Pad29)") (class "Default")
      (node (ref "U$1") (pin "29") (pinfunction "VTEMP1_29") (pintype "bidirectional"))
    )
    (net (code "931") (name "unconnected-(U$1-VTEMP2-Pad30)") (class "Default")
      (node (ref "U$1") (pin "30") (pinfunction "VTEMP2_30") (pintype "bidirectional"))
    )
    (net (code "932") (name "unconnected-(U$16-GPIO1-Pad35)") (class "Default")
      (node (ref "U$16") (pin "35") (pinfunction "GPIO1_35") (pintype "bidirectional"))
    )
    (net (code "933") (name "unconnected-(U$16-GPIO2-Pad36)") (class "Default")
      (node (ref "U$16") (pin "36") (pinfunction "GPIO2_36") (pintype "bidirectional"))
    )
    (net (code "934") (name "unconnected-(U$16-VTEMP1-Pad29)") (class "Default")
      (node (ref "U$16") (pin "29") (pinfunction "VTEMP1_29") (pintype "bidirectional"))
    )
    (net (code "935") (name "unconnected-(U$16-VTEMP2-Pad30)") (class "Default")
      (node (ref "U$16") (pin "30") (pinfunction "VTEMP2_30") (pintype "bidirectional"))
    )
    (net (code "936") (name "unconnected-(U$31-GPIO1-Pad35)") (class "Default")
      (node (ref "U$31") (pin "35") (pinfunction "GPIO1_35") (pintype "bidirectional"))
    )
    (net (code "937") (name "unconnected-(U$31-GPIO2-Pad36)") (class "Default")
      (node (ref "U$31") (pin "36") (pinfunction "GPIO2_36") (pintype "bidirectional"))
    )
    (net (code "938") (name "unconnected-(U$31-VTEMP1-Pad29)") (class "Default")
      (node (ref "U$31") (pin "29") (pinfunction "VTEMP1_29") (pintype "bidirectional"))
    )
    (net (code "939") (name "unconnected-(U$31-VTEMP2-Pad30)") (class "Default")
      (node (ref "U$31") (pin "30") (pinfunction "VTEMP2_30") (pintype "bidirectional"))
    )
    (net (code "940") (name "unconnected-(U$34-GPIO1-Pad35)") (class "Default")
      (node (ref "U$34") (pin "35") (pinfunction "GPIO1_35") (pintype "bidirectional"))
    )
    (net (code "941") (name "unconnected-(U$34-GPIO2-Pad36)") (class "Default")
      (node (ref "U$34") (pin "36") (pinfunction "GPIO2_36") (pintype "bidirectional"))
    )
    (net (code "942") (name "unconnected-(U$34-VTEMP1-Pad29)") (class "Default")
      (node (ref "U$34") (pin "29") (pinfunction "VTEMP1_29") (pintype "bidirectional"))
    )
    (net (code "943") (name "unconnected-(U$34-VTEMP2-Pad30)") (class "Default")
      (node (ref "U$34") (pin "30") (pinfunction "VTEMP2_30") (pintype "bidirectional"))
    )
    (net (code "944") (name "unconnected-(U$61-GPIO1-Pad35)") (class "Default")
      (node (ref "U$61") (pin "35") (pinfunction "GPIO1_35") (pintype "bidirectional"))
    )
    (net (code "945") (name "unconnected-(U$61-GPIO2-Pad36)") (class "Default")
      (node (ref "U$61") (pin "36") (pinfunction "GPIO2_36") (pintype "bidirectional"))
    )
    (net (code "946") (name "unconnected-(U$61-VTEMP1-Pad29)") (class "Default")
      (node (ref "U$61") (pin "29") (pinfunction "VTEMP1_29") (pintype "bidirectional"))
    )
    (net (code "947") (name "unconnected-(U$61-VTEMP2-Pad30)") (class "Default")
      (node (ref "U$61") (pin "30") (pinfunction "VTEMP2_30") (pintype "bidirectional"))
    )
    (net (code "948") (name "unconnected-(U$76-GPIO1-Pad35)") (class "Default")
      (node (ref "U$76") (pin "35") (pinfunction "GPIO1_35") (pintype "bidirectional"))
    )
    (net (code "949") (name "unconnected-(U$76-GPIO2-Pad36)") (class "Default")
      (node (ref "U$76") (pin "36") (pinfunction "GPIO2_36") (pintype "bidirectional"))
    )
    (net (code "950") (name "unconnected-(U$76-VTEMP1-Pad29)") (class "Default")
      (node (ref "U$76") (pin "29") (pinfunction "VTEMP1_29") (pintype "bidirectional"))
    )
    (net (code "951") (name "unconnected-(U$76-VTEMP2-Pad30)") (class "Default")
      (node (ref "U$76") (pin "30") (pinfunction "VTEMP2_30") (pintype "bidirectional"))
    )
    (net (code "952") (name "unconnected-(U$91-GPIO1-Pad35)") (class "Default")
      (node (ref "U$91") (pin "35") (pinfunction "GPIO1_35") (pintype "bidirectional"))
    )
    (net (code "953") (name "unconnected-(U$91-GPIO2-Pad36)") (class "Default")
      (node (ref "U$91") (pin "36") (pinfunction "GPIO2_36") (pintype "bidirectional"))
    )
    (net (code "954") (name "unconnected-(U$91-VTEMP1-Pad29)") (class "Default")
      (node (ref "U$91") (pin "29") (pinfunction "VTEMP1_29") (pintype "bidirectional"))
    )
    (net (code "955") (name "unconnected-(U$91-VTEMP2-Pad30)") (class "Default")
      (node (ref "U$91") (pin "30") (pinfunction "VTEMP2_30") (pintype "bidirectional"))
    )
    (net (code "956") (name "unconnected-(U$106-GPIO1-Pad35)") (class "Default")
      (node (ref "U$106") (pin "35") (pinfunction "GPIO1_35") (pintype "bidirectional"))
    )
    (net (code "957") (name "unconnected-(U$106-GPIO2-Pad36)") (class "Default")
      (node (ref "U$106") (pin "36") (pinfunction "GPIO2_36") (pintype "bidirectional"))
    )
    (net (code "958") (name "unconnected-(U$106-VTEMP1-Pad29)") (class "Default")
      (node (ref "U$106") (pin "29") (pinfunction "VTEMP1_29") (pintype "bidirectional"))
    )
    (net (code "959") (name "unconnected-(U$106-VTEMP2-Pad30)") (class "Default")
      (node (ref "U$106") (pin "30") (pinfunction "VTEMP2_30") (pintype "bidirectional"))
    )
    (net (code "960") (name "unconnected-(U$121-GPIO1-Pad35)") (class "Default")
      (node (ref "U$121") (pin "35") (pinfunction "GPIO1_35") (pintype "bidirectional"))
    )
    (net (code "961") (name "unconnected-(U$121-GPIO2-Pad36)") (class "Default")
      (node (ref "U$121") (pin "36") (pinfunction "GPIO2_36") (pintype "bidirectional"))
    )
    (net (code "962") (name "unconnected-(U$121-VTEMP1-Pad29)") (class "Default")
      (node (ref "U$121") (pin "29") (pinfunction "VTEMP1_29") (pintype "bidirectional"))
    )
    (net (code "963") (name "unconnected-(U$121-VTEMP2-Pad30)") (class "Default")
      (node (ref "U$121") (pin "30") (pinfunction "VTEMP2_30") (pintype "bidirectional"))
    )
  )
)
